# DRI-21700-compactpcb-12s4p-v2.net
KiCad netlist of a schematic drawn in EAGLE
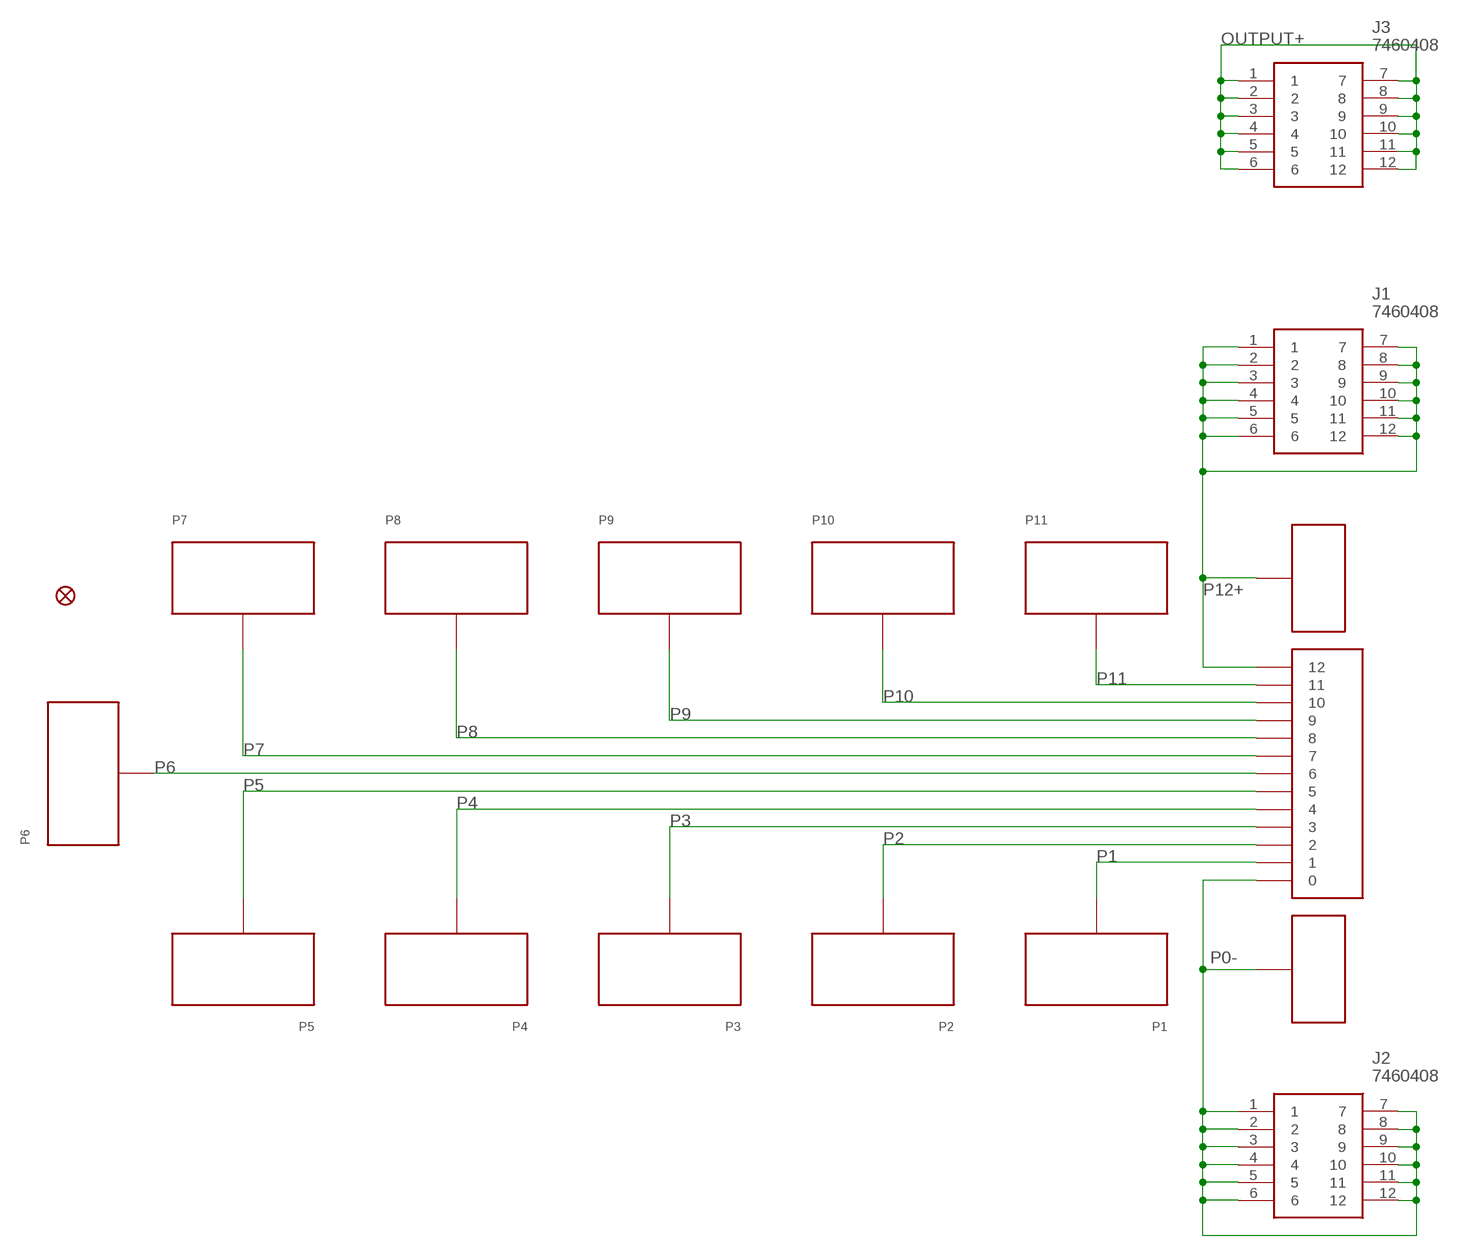
[diagram p0: schematic, sheet 1]

(export (version "E")
  (design (tool "Eeschema 10.0.6"))
  (components
    (comp (ref "FD2")
      (value "FIDUCIAL1X2")
      (footprint "eagle-import:FIDUCIAL-1X2")
      (libsource (lib "eagle-import") (part "FIDUCIAL1X2"))
    )
    (comp (ref "J1")
      (value "7460408")
      (footprint "eagle-import:7460408")
      (fields (field (name "MOUSER_PART_NUMBER") "710-7460408"))
      (libsource (lib "eagle-import") (part "7460408"))
    )
    (comp (ref "J2")
      (value "7460408")
      (footprint "eagle-import:7460408")
      (fields (field (name "MOUSER_PART_NUMBER") "710-7460408"))
      (libsource (lib "eagle-import") (part "7460408"))
    )
    (comp (ref "J3")
      (value "7460408")
      (footprint "eagle-import:7460408")
      (fields (field (name "MOUSER_PART_NUMBER") "710-7460408"))
      (libsource (lib "eagle-import") (part "7460408"))
    )
    (comp (ref "JP1")
      (value "13P-JST-2MM")
      (footprint "eagle-import:13P-JST-2MM")
      (libsource (lib "eagle-import") (part "13P-JST-2MM"))
    )
    (comp (ref "P0")
      (value "BUS-TERM-PAD-")
      (footprint "eagle-import:TERM-PAD-")
      (libsource (lib "eagle-import") (part "BUS-TERM-PAD-"))
    )
    (comp (ref "P1")
      (value "BAT-TERM-L")
      (footprint "eagle-import:BAT-TERM-L")
      (libsource (lib "eagle-import") (part "BAT-TERM-L"))
    )
    (comp (ref "P2")
      (value "BAT-TERM-L")
      (footprint "eagle-import:BAT-TERM-L")
      (libsource (lib "eagle-import") (part "BAT-TERM-L"))
    )
    (comp (ref "P3")
      (value "BAT-TERM-L")
      (footprint "eagle-import:BAT-TERM-L")
      (libsource (lib "eagle-import") (part "BAT-TERM-L"))
    )
    (comp (ref "P4")
      (value "BAT-TERM-L")
      (footprint "eagle-import:BAT-TERM-L")
      (libsource (lib "eagle-import") (part "BAT-TERM-L"))
    )
    (comp (ref "P5")
      (value "BAT-TERM-L")
      (footprint "eagle-import:BAT-TERM-L")
      (libsource (lib "eagle-import") (part "BAT-TERM-L"))
    )
    (comp (ref "P6")
      (value "BAT-TERM-END")
      (footprint "eagle-import:BAT-TERM-END")
      (libsource (lib "eagle-import") (part "BAT-TERM-END"))
    )
    (comp (ref "P7")
      (value "BAT-TERM-L")
      (footprint "eagle-import:BAT-TERM-L")
      (libsource (lib "eagle-import") (part "BAT-TERM-L"))
    )
    (comp (ref "P8")
      (value "BAT-TERM-L")
      (footprint "eagle-import:BAT-TERM-L")
      (libsource (lib "eagle-import") (part "BAT-TERM-L"))
    )
    (comp (ref "P9")
      (value "BAT-TERM-L")
      (footprint "eagle-import:BAT-TERM-L")
      (libsource (lib "eagle-import") (part "BAT-TERM-L"))
    )
    (comp (ref "P10")
      (value "BAT-TERM-L")
      (footprint "eagle-import:BAT-TERM-L")
      (libsource (lib "eagle-import") (part "BAT-TERM-L"))
    )
    (comp (ref "P11")
      (value "BAT-TERM-L")
      (footprint "eagle-import:BAT-TERM-L")
      (libsource (lib "eagle-import") (part "BAT-TERM-L"))
    )
    (comp (ref "P12")
      (value "BUS-TERM-PAD+")
      (footprint "eagle-import:TERM-PAD-")
      (libsource (lib "eagle-import") (part "BUS-TERM-PAD+"))
    )
  )
  (nets
    (net (code "1") (name "/OUTPUT+") (class "Default")
      (node (ref "J3") (pin "1") (pinfunction "1_1") (pintype "bidirectional"))
      (node (ref "J3") (pin "10") (pinfunction "10_10") (pintype "bidirectional"))
      (node (ref "J3") (pin "11") (pinfunction "11_11") (pintype "bidirectional"))
      (node (ref "J3") (pin "12") (pinfunction "12_12") (pintype "bidirectional"))
      (node (ref "J3") (pin "2") (pinfunction "2_2") (pintype "bidirectional"))
      (node (ref "J3") (pin "3") (pinfunction "3_3") (pintype "bidirectional"))
      (node (ref "J3") (pin "4") (pinfunction "4_4") (pintype "bidirectional"))
      (node (ref "J3") (pin "5") (pinfunction "5_5") (pintype "bidirectional"))
      (node (ref "J3") (pin "6") (pinfunction "6_6") (pintype "bidirectional"))
      (node (ref "J3") (pin "7") (pinfunction "7_7") (pintype "bidirectional"))
      (node (ref "J3") (pin "8") (pinfunction "8_8") (pintype "bidirectional"))
      (node (ref "J3") (pin "9") (pinfunction "9_9") (pintype "bidirectional"))
    )
    (net (code "2") (name "/P0-") (class "Default")
      (node (ref "J2") (pin "1") (pinfunction "1_1") (pintype "bidirectional"))
      (node (ref "J2") (pin "10") (pinfunction "10_10") (pintype "bidirectional"))
      (node (ref "J2") (pin "11") (pinfunction "11_11") (pintype "bidirectional"))
      (node (ref "J2") (pin "12") (pinfunction "12_12") (pintype "bidirectional"))
      (node (ref "J2") (pin "2") (pinfunction "2_2") (pintype "bidirectional"))
      (node (ref "J2") (pin "3") (pinfunction "3_3") (pintype "bidirectional"))
      (node (ref "J2") (pin "4") (pinfunction "4_4") (pintype "bidirectional"))
      (node (ref "J2") (pin "5") (pinfunction "5_5") (pintype "bidirectional"))
      (node (ref "J2") (pin "6") (pinfunction "6_6") (pintype "bidirectional"))
      (node (ref "J2") (pin "7") (pinfunction "7_7") (pintype "bidirectional"))
      (node (ref "J2") (pin "8") (pinfunction "8_8") (pintype "bidirectional"))
      (node (ref "J2") (pin "9") (pinfunction "9_9") (pintype "bidirectional"))
      (node (ref "JP1") (pin "P$1") (pinfunction "0_P$1") (pintype "bidirectional"))
      (node (ref "P0") (pin "P$10") (pinfunction "P$0_P$10") (pintype "power_in"))
      (node (ref "P0") (pin "P$100") (pinfunction "P$0_P$100") (pintype "power_in"))
      (node (ref "P0") (pin "P$101") (pinfunction "P$0_P$101") (pintype "power_in"))
      (node (ref "P0") (pin "P$102") (pinfunction "P$0_P$102") (pintype "power_in"))
      (node (ref "P0") (pin "P$103") (pinfunction "P$0_P$103") (pintype "power_in"))
      (node (ref "P0") (pin "P$104") (pinfunction "P$0_P$104") (pintype "power_in"))
      (node (ref "P0") (pin "P$105") (pinfunction "P$0_P$105") (pintype "power_in"))
      (node (ref "P0") (pin "P$106") (pinfunction "P$0_P$106") (pintype "power_in"))
      (node (ref "P0") (pin "P$107") (pinfunction "P$0_P$107") (pintype "power_in"))
      (node (ref "P0") (pin "P$108") (pinfunction "P$0_P$108") (pintype "power_in"))
      (node (ref "P0") (pin "P$109") (pinfunction "P$0_P$109") (pintype "power_in"))
      (node (ref "P0") (pin "P$11") (pinfunction "P$0_P$11") (pintype "power_in"))
      (node (ref "P0") (pin "P$110") (pinfunction "P$0_P$110") (pintype "power_in"))
      (node (ref "P0") (pin "P$12") (pinfunction "P$0_P$12") (pintype "power_in"))
      (node (ref "P0") (pin "P$13") (pinfunction "P$0_P$13") (pintype "power_in"))
      (node (ref "P0") (pin "P$14") (pinfunction "P$0_P$14") (pintype "power_in"))
      (node (ref "P0") (pin "P$15") (pinfunction "P$0_P$15") (pintype "power_in"))
      (node (ref "P0") (pin "P$16") (pinfunction "P$0_P$16") (pintype "power_in"))
      (node (ref "P0") (pin "P$17") (pinfunction "P$0_P$17") (pintype "power_in"))
      (node (ref "P0") (pin "P$18") (pinfunction "P$0_P$18") (pintype "power_in"))
      (node (ref "P0") (pin "P$19") (pinfunction "P$0_P$19") (pintype "power_in"))
      (node (ref "P0") (pin "P$20") (pinfunction "P$0_P$20") (pintype "power_in"))
      (node (ref "P0") (pin "P$21") (pinfunction "P$0_P$21") (pintype "power_in"))
      (node (ref "P0") (pin "P$22") (pinfunction "P$0_P$22") (pintype "power_in"))
      (node (ref "P0") (pin "P$23") (pinfunction "P$0_P$23") (pintype "power_in"))
      (node (ref "P0") (pin "P$24") (pinfunction "P$0_P$24") (pintype "power_in"))
      (node (ref "P0") (pin "P$25") (pinfunction "P$0_P$25") (pintype "power_in"))
      (node (ref "P0") (pin "P$26") (pinfunction "P$0_P$26") (pintype "power_in"))
      (node (ref "P0") (pin "P$27") (pinfunction "P$0_P$27") (pintype "power_in"))
      (node (ref "P0") (pin "P$28") (pinfunction "P$0_P$28") (pintype "power_in"))
      (node (ref "P0") (pin "P$29") (pinfunction "P$0_P$29") (pintype "power_in"))
      (node (ref "P0") (pin "P$3") (pinfunction "P$0_P$3") (pintype "power_in"))
      (node (ref "P0") (pin "P$30") (pinfunction "P$0_P$30") (pintype "power_in"))
      (node (ref "P0") (pin "P$31") (pinfunction "P$0_P$31") (pintype "power_in"))
      (node (ref "P0") (pin "P$32") (pinfunction "P$0_P$32") (pintype "power_in"))
      (node (ref "P0") (pin "P$33") (pinfunction "P$0_P$33") (pintype "power_in"))
      (node (ref "P0") (pin "P$34") (pinfunction "P$0_P$34") (pintype "power_in"))
      (node (ref "P0") (pin "P$35") (pinfunction "P$0_P$35") (pintype "power_in"))
      (node (ref "P0") (pin "P$36") (pinfunction "P$0_P$36") (pintype "power_in"))
      (node (ref "P0") (pin "P$37") (pinfunction "P$0_P$37") (pintype "power_in"))
      (node (ref "P0") (pin "P$38") (pinfunction "P$0_P$38") (pintype "power_in"))
      (node (ref "P0") (pin "P$39") (pinfunction "P$0_P$39") (pintype "power_in"))
      (node (ref "P0") (pin "P$4") (pinfunction "P$0_P$4") (pintype "power_in"))
      (node (ref "P0") (pin "P$40") (pinfunction "P$0_P$40") (pintype "power_in"))
      (node (ref "P0") (pin "P$41") (pinfunction "P$0_P$41") (pintype "power_in"))
      (node (ref "P0") (pin "P$42") (pinfunction "P$0_P$42") (pintype "power_in"))
      (node (ref "P0") (pin "P$43") (pinfunction "P$0_P$43") (pintype "power_in"))
      (node (ref "P0") (pin "P$44") (pinfunction "P$0_P$44") (pintype "power_in"))
      (node (ref "P0") (pin "P$45") (pinfunction "P$0_P$45") (pintype "power_in"))
      (node (ref "P0") (pin "P$46") (pinfunction "P$0_P$46") (pintype "power_in"))
      (node (ref "P0") (pin "P$47") (pinfunction "P$0_P$47") (pintype "power_in"))
      (node (ref "P0") (pin "P$48") (pinfunction "P$0_P$48") (pintype "power_in"))
      (node (ref "P0") (pin "P$49") (pinfunction "P$0_P$49") (pintype "power_in"))
      (node (ref "P0") (pin "P$5") (pinfunction "P$0_P$5") (pintype "power_in"))
      (node (ref "P0") (pin "P$50") (pinfunction "P$0_P$50") (pintype "power_in"))
      (node (ref "P0") (pin "P$51") (pinfunction "P$0_P$51") (pintype "power_in"))
      (node (ref "P0") (pin "P$52") (pinfunction "P$0_P$52") (pintype "power_in"))
      (node (ref "P0") (pin "P$53") (pinfunction "P$0_P$53") (pintype "power_in"))
      (node (ref "P0") (pin "P$54") (pinfunction "P$0_P$54") (pintype "power_in"))
      (node (ref "P0") (pin "P$55") (pinfunction "P$0_P$55") (pintype "power_in"))
      (node (ref "P0") (pin "P$56") (pinfunction "P$0_P$56") (pintype "power_in"))
      (node (ref "P0") (pin "P$57") (pinfunction "P$0_P$57") (pintype "power_in"))
      (node (ref "P0") (pin "P$58") (pinfunction "P$0_P$58") (pintype "power_in"))
      (node (ref "P0") (pin "P$59") (pinfunction "P$0_P$59") (pintype "power_in"))
      (node (ref "P0") (pin "P$6") (pinfunction "P$0_P$6") (pintype "power_in"))
      (node (ref "P0") (pin "P$60") (pinfunction "P$0_P$60") (pintype "power_in"))
      (node (ref "P0") (pin "P$61") (pinfunction "P$0_P$61") (pintype "power_in"))
      (node (ref "P0") (pin "P$62") (pinfunction "P$0_P$62") (pintype "power_in"))
      (node (ref "P0") (pin "P$63") (pinfunction "P$0_P$63") (pintype "power_in"))
      (node (ref "P0") (pin "P$64") (pinfunction "P$0_P$64") (pintype "power_in"))
      (node (ref "P0") (pin "P$65") (pinfunction "P$0_P$65") (pintype "power_in"))
      (node (ref "P0") (pin "P$66") (pinfunction "P$0_P$66") (pintype "power_in"))
      (node (ref "P0") (pin "P$67") (pinfunction "P$0_P$67") (pintype "power_in"))
      (node (ref "P0") (pin "P$68") (pinfunction "P$0_P$68") (pintype "power_in"))
      (node (ref "P0") (pin "P$69") (pinfunction "P$0_P$69") (pintype "power_in"))
      (node (ref "P0") (pin "P$7") (pinfunction "P$0_P$7") (pintype "power_in"))
      (node (ref "P0") (pin "P$70") (pinfunction "P$0_P$70") (pintype "power_in"))
      (node (ref "P0") (pin "P$71") (pinfunction "P$0_P$71") (pintype "power_in"))
      (node (ref "P0") (pin "P$72") (pinfunction "P$0_P$72") (pintype "power_in"))
      (node (ref "P0") (pin "P$73") (pinfunction "P$0_P$73") (pintype "power_in"))
      (node (ref "P0") (pin "P$74") (pinfunction "P$0_P$74") (pintype "power_in"))
      (node (ref "P0") (pin "P$75") (pinfunction "P$0_P$75") (pintype "power_in"))
      (node (ref "P0") (pin "P$76") (pinfunction "P$0_P$76") (pintype "power_in"))
      (node (ref "P0") (pin "P$77") (pinfunction "P$0_P$77") (pintype "power_in"))
      (node (ref "P0") (pin "P$78") (pinfunction "P$0_P$78") (pintype "power_in"))
      (node (ref "P0") (pin "P$79") (pinfunction "P$0_P$79") (pintype "power_in"))
      (node (ref "P0") (pin "P$8") (pinfunction "P$0_P$8") (pintype "power_in"))
      (node (ref "P0") (pin "P$80") (pinfunction "P$0_P$80") (pintype "power_in"))
      (node (ref "P0") (pin "P$81") (pinfunction "P$0_P$81") (pintype "power_in"))
      (node (ref "P0") (pin "P$82") (pinfunction "P$0_P$82") (pintype "power_in"))
      (node (ref "P0") (pin "P$83") (pinfunction "P$0_P$83") (pintype "power_in"))
      (node (ref "P0") (pin "P$84") (pinfunction "P$0_P$84") (pintype "power_in"))
      (node (ref "P0") (pin "P$85") (pinfunction "P$0_P$85") (pintype "power_in"))
      (node (ref "P0") (pin "P$86") (pinfunction "P$0_P$86") (pintype "power_in"))
      (node (ref "P0") (pin "P$87") (pinfunction "P$0_P$87") (pintype "power_in"))
      (node (ref "P0") (pin "P$88") (pinfunction "P$0_P$88") (pintype "power_in"))
      (node (ref "P0") (pin "P$89") (pinfunction "P$0_P$89") (pintype "power_in"))
      (node (ref "P0") (pin "P$9") (pinfunction "P$0_P$9") (pintype "power_in"))
      (node (ref "P0") (pin "P$90") (pinfunction "P$0_P$90") (pintype "power_in"))
      (node (ref "P0") (pin "P$91") (pinfunction "P$0_P$91") (pintype "power_in"))
      (node (ref "P0") (pin "P$92") (pinfunction "P$0_P$92") (pintype "power_in"))
      (node (ref "P0") (pin "P$93") (pinfunction "P$0_P$93") (pintype "power_in"))
      (node (ref "P0") (pin "P$94") (pinfunction "P$0_P$94") (pintype "power_in"))
      (node (ref "P0") (pin "P$95") (pinfunction "P$0_P$95") (pintype "power_in"))
      (node (ref "P0") (pin "P$96") (pinfunction "P$0_P$96") (pintype "power_in"))
      (node (ref "P0") (pin "P$97") (pinfunction "P$0_P$97") (pintype "power_in"))
      (node (ref "P0") (pin "P$98") (pinfunction "P$0_P$98") (pintype "power_in"))
      (node (ref "P0") (pin "P$99") (pinfunction "P$0_P$99") (pintype "power_in"))
    )
    (net (code "3") (name "/P1") (class "Default")
      (node (ref "JP1") (pin "P$2") (pinfunction "1_P$2") (pintype "bidirectional"))
      (node (ref "P1") (pin "P$1") (pinfunction "P$1_P$1") (pintype "power_in"))
      (node (ref "P1") (pin "P$10") (pinfunction "P$1_P$10") (pintype "power_in"))
      (node (ref "P1") (pin "P$100") (pinfunction "P$1_P$100") (pintype "power_in"))
      (node (ref "P1") (pin "P$101") (pinfunction "P$1_P$101") (pintype "power_in"))
      (node (ref "P1") (pin "P$102") (pinfunction "P$1_P$102") (pintype "power_in"))
      (node (ref "P1") (pin "P$103") (pinfunction "P$1_P$103") (pintype "power_in"))
      (node (ref "P1") (pin "P$104") (pinfunction "P$1_P$104") (pintype "power_in"))
      (node (ref "P1") (pin "P$105") (pinfunction "P$1_P$105") (pintype "power_in"))
      (node (ref "P1") (pin "P$106") (pinfunction "P$1_P$106") (pintype "power_in"))
      (node (ref "P1") (pin "P$107") (pinfunction "P$1_P$107") (pintype "power_in"))
      (node (ref "P1") (pin "P$108") (pinfunction "P$1_P$108") (pintype "power_in"))
      (node (ref "P1") (pin "P$109") (pinfunction "P$1_P$109") (pintype "power_in"))
      (node (ref "P1") (pin "P$11") (pinfunction "P$1_P$11") (pintype "power_in"))
      (node (ref "P1") (pin "P$110") (pinfunction "P$1_P$110") (pintype "power_in"))
      (node (ref "P1") (pin "P$111") (pinfunction "P$1_P$111") (pintype "power_in"))
      (node (ref "P1") (pin "P$112") (pinfunction "P$1_P$112") (pintype "power_in"))
      (node (ref "P1") (pin "P$113") (pinfunction "P$1_P$113") (pintype "power_in"))
      (node (ref "P1") (pin "P$114") (pinfunction "P$1_P$114") (pintype "power_in"))
      (node (ref "P1") (pin "P$115") (pinfunction "P$1_P$115") (pintype "power_in"))
      (node (ref "P1") (pin "P$116") (pinfunction "P$1_P$116") (pintype "power_in"))
      (node (ref "P1") (pin "P$117") (pinfunction "P$1_P$117") (pintype "power_in"))
      (node (ref "P1") (pin "P$118") (pinfunction "P$1_P$118") (pintype "power_in"))
      (node (ref "P1") (pin "P$119") (pinfunction "P$1_P$119") (pintype "power_in"))
      (node (ref "P1") (pin "P$12") (pinfunction "P$1_P$12") (pintype "power_in"))
      (node (ref "P1") (pin "P$120") (pinfunction "P$1_P$120") (pintype "power_in"))
      (node (ref "P1") (pin "P$121") (pinfunction "P$1_P$121") (pintype "power_in"))
      (node (ref "P1") (pin "P$122") (pinfunction "P$1_P$122") (pintype "power_in"))
      (node (ref "P1") (pin "P$123") (pinfunction "P$1_P$123") (pintype "power_in"))
      (node (ref "P1") (pin "P$124") (pinfunction "P$1_P$124") (pintype "power_in"))
      (node (ref "P1") (pin "P$125") (pinfunction "P$1_P$125") (pintype "power_in"))
      (node (ref "P1") (pin "P$126") (pinfunction "P$1_P$126") (pintype "power_in"))
      (node (ref "P1") (pin "P$127") (pinfunction "P$1_P$127") (pintype "power_in"))
      (node (ref "P1") (pin "P$128") (pinfunction "P$1_P$128") (pintype "power_in"))
      (node (ref "P1") (pin "P$129") (pinfunction "P$1_P$129") (pintype "power_in"))
      (node (ref "P1") (pin "P$13") (pinfunction "P$1_P$13") (pintype "power_in"))
      (node (ref "P1") (pin "P$130") (pinfunction "P$1_P$130") (pintype "power_in"))
      (node (ref "P1") (pin "P$131") (pinfunction "P$1_P$131") (pintype "power_in"))
      (node (ref "P1") (pin "P$132") (pinfunction "P$1_P$132") (pintype "power_in"))
      (node (ref "P1") (pin "P$133") (pinfunction "P$1_P$133") (pintype "power_in"))
      (node (ref "P1") (pin "P$134") (pinfunction "P$1_P$134") (pintype "power_in"))
      (node (ref "P1") (pin "P$135") (pinfunction "P$1_P$135") (pintype "power_in"))
      (node (ref "P1") (pin "P$136") (pinfunction "P$1_P$136") (pintype "power_in"))
      (node (ref "P1") (pin "P$137") (pinfunction "P$1_P$137") (pintype "power_in"))
      (node (ref "P1") (pin "P$138") (pinfunction "P$1_P$138") (pintype "power_in"))
      (node (ref "P1") (pin "P$139") (pinfunction "P$1_P$139") (pintype "power_in"))
      (node (ref "P1") (pin "P$14") (pinfunction "P$1_P$14") (pintype "power_in"))
      (node (ref "P1") (pin "P$140") (pinfunction "P$1_P$140") (pintype "power_in"))
      (node (ref "P1") (pin "P$141") (pinfunction "P$1_P$141") (pintype "power_in"))
      (node (ref "P1") (pin "P$142") (pinfunction "P$1_P$142") (pintype "power_in"))
      (node (ref "P1") (pin "P$143") (pinfunction "P$1_P$143") (pintype "power_in"))
      (node (ref "P1") (pin "P$144") (pinfunction "P$1_P$144") (pintype "power_in"))
      (node (ref "P1") (pin "P$145") (pinfunction "P$1_P$145") (pintype "power_in"))
      (node (ref "P1") (pin "P$146") (pinfunction "P$1_P$146") (pintype "power_in"))
      (node (ref "P1") (pin "P$147") (pinfunction "P$1_P$147") (pintype "power_in"))
      (node (ref "P1") (pin "P$148") (pinfunction "P$1_P$148") (pintype "power_in"))
      (node (ref "P1") (pin "P$149") (pinfunction "P$1_P$149") (pintype "power_in"))
      (node (ref "P1") (pin "P$15") (pinfunction "P$1_P$15") (pintype "power_in"))
      (node (ref "P1") (pin "P$150") (pinfunction "P$1_P$150") (pintype "power_in"))
      (node (ref "P1") (pin "P$151") (pinfunction "P$1_P$151") (pintype "power_in"))
      (node (ref "P1") (pin "P$152") (pinfunction "P$1_P$152") (pintype "power_in"))
      (node (ref "P1") (pin "P$153") (pinfunction "P$1_P$153") (pintype "power_in"))
      (node (ref "P1") (pin "P$154") (pinfunction "P$1_P$154") (pintype "power_in"))
      (node (ref "P1") (pin "P$155") (pinfunction "P$1_P$155") (pintype "power_in"))
      (node (ref "P1") (pin "P$156") (pinfunction "P$1_P$156") (pintype "power_in"))
      (node (ref "P1") (pin "P$157") (pinfunction "P$1_P$157") (pintype "power_in"))
      (node (ref "P1") (pin "P$158") (pinfunction "P$1_P$158") (pintype "power_in"))
      (node (ref "P1") (pin "P$159") (pinfunction "P$1_P$159") (pintype "power_in"))
      (node (ref "P1") (pin "P$16") (pinfunction "P$1_P$16") (pintype "power_in"))
      (node (ref "P1") (pin "P$160") (pinfunction "P$1_P$160") (pintype "power_in"))
      (node (ref "P1") (pin "P$161") (pinfunction "P$1_P$161") (pintype "power_in"))
      (node (ref "P1") (pin "P$162") (pinfunction "P$1_P$162") (pintype "power_in"))
      (node (ref "P1") (pin "P$163") (pinfunction "P$1_P$163") (pintype "power_in"))
      (node (ref "P1") (pin "P$164") (pinfunction "P$1_P$164") (pintype "power_in"))
      (node (ref "P1") (pin "P$165") (pinfunction "P$1_P$165") (pintype "power_in"))
      (node (ref "P1") (pin "P$166") (pinfunction "P$1_P$166") (pintype "power_in"))
      (node (ref "P1") (pin "P$167") (pinfunction "P$1_P$167") (pintype "power_in"))
      (node (ref "P1") (pin "P$168") (pinfunction "P$1_P$168") (pintype "power_in"))
      (node (ref "P1") (pin "P$169") (pinfunction "P$1_P$169") (pintype "power_in"))
      (node (ref "P1") (pin "P$17") (pinfunction "P$1_P$17") (pintype "power_in"))
      (node (ref "P1") (pin "P$170") (pinfunction "P$1_P$170") (pintype "power_in"))
      (node (ref "P1") (pin "P$171") (pinfunction "P$1_P$171") (pintype "power_in"))
      (node (ref "P1") (pin "P$172") (pinfunction "P$1_P$172") (pintype "power_in"))
      (node (ref "P1") (pin "P$173") (pinfunction "P$1_P$173") (pintype "power_in"))
      (node (ref "P1") (pin "P$174") (pinfunction "P$1_P$174") (pintype "power_in"))
      (node (ref "P1") (pin "P$175") (pinfunction "P$1_P$175") (pintype "power_in"))
      (node (ref "P1") (pin "P$176") (pinfunction "P$1_P$176") (pintype "power_in"))
      (node (ref "P1") (pin "P$177") (pinfunction "P$1_P$177") (pintype "power_in"))
      (node (ref "P1") (pin "P$178") (pinfunction "P$1_P$178") (pintype "power_in"))
      (node (ref "P1") (pin "P$179") (pinfunction "P$1_P$179") (pintype "power_in"))
      (node (ref "P1") (pin "P$18") (pinfunction "P$1_P$18") (pintype "power_in"))
      (node (ref "P1") (pin "P$180") (pinfunction "P$1_P$180") (pintype "power_in"))
      (node (ref "P1") (pin "P$181") (pinfunction "P$1_P$181") (pintype "power_in"))
      (node (ref "P1") (pin "P$182") (pinfunction "P$1_P$182") (pintype "power_in"))
      (node (ref "P1") (pin "P$183") (pinfunction "P$1_P$183") (pintype "power_in"))
      (node (ref "P1") (pin "P$184") (pinfunction "P$1_P$184") (pintype "power_in"))
      (node (ref "P1") (pin "P$185") (pinfunction "P$1_P$185") (pintype "power_in"))
      (node (ref "P1") (pin "P$186") (pinfunction "P$1_P$186") (pintype "power_in"))
      (node (ref "P1") (pin "P$187") (pinfunction "P$1_P$187") (pintype "power_in"))
      (node (ref "P1") (pin "P$188") (pinfunction "P$1_P$188") (pintype "power_in"))
      (node (ref "P1") (pin "P$189") (pinfunction "P$1_P$189") (pintype "power_in"))
      (node (ref "P1") (pin "P$19") (pinfunction "P$1_P$19") (pintype "power_in"))
      (node (ref "P1") (pin "P$190") (pinfunction "P$1_P$190") (pintype "power_in"))
      (node (ref "P1") (pin "P$191") (pinfunction "P$1_P$191") (pintype "power_in"))
      (node (ref "P1") (pin "P$192") (pinfunction "P$1_P$192") (pintype "power_in"))
      (node (ref "P1") (pin "P$193") (pinfunction "P$1_P$193") (pintype "power_in"))
      (node (ref "P1") (pin "P$194") (pinfunction "P$1_P$194") (pintype "power_in"))
      (node (ref "P1") (pin "P$195") (pinfunction "P$1_P$195") (pintype "power_in"))
      (node (ref "P1") (pin "P$196") (pinfunction "P$1_P$196") (pintype "power_in"))
      (node (ref "P1") (pin "P$197") (pinfunction "P$1_P$197") (pintype "power_in"))
      (node (ref "P1") (pin "P$198") (pinfunction "P$1_P$198") (pintype "power_in"))
      (node (ref "P1") (pin "P$199") (pinfunction "P$1_P$199") (pintype "power_in"))
      (node (ref "P1") (pin "P$2") (pinfunction "P$1_P$2") (pintype "power_in"))
      (node (ref "P1") (pin "P$20") (pinfunction "P$1_P$20") (pintype "power_in"))
      (node (ref "P1") (pin "P$200") (pinfunction "P$1_P$200") (pintype "power_in"))
      (node (ref "P1") (pin "P$201") (pinfunction "P$1_P$201") (pintype "power_in"))
      (node (ref "P1") (pin "P$202") (pinfunction "P$1_P$202") (pintype "power_in"))
      (node (ref "P1") (pin "P$203") (pinfunction "P$1_P$203") (pintype "power_in"))
      (node (ref "P1") (pin "P$204") (pinfunction "P$1_P$204") (pintype "power_in"))
      (node (ref "P1") (pin "P$205") (pinfunction "P$1_P$205") (pintype "power_in"))
      (node (ref "P1") (pin "P$206") (pinfunction "P$1_P$206") (pintype "power_in"))
      (node (ref "P1") (pin "P$207") (pinfunction "P$1_P$207") (pintype "power_in"))
      (node (ref "P1") (pin "P$208") (pinfunction "P$1_P$208") (pintype "power_in"))
      (node (ref "P1") (pin "P$209") (pinfunction "P$1_P$209") (pintype "power_in"))
      (node (ref "P1") (pin "P$21") (pinfunction "P$1_P$21") (pintype "power_in"))
      (node (ref "P1") (pin "P$210") (pinfunction "P$1_P$210") (pintype "power_in"))
      (node (ref "P1") (pin "P$211") (pinfunction "P$1_P$211") (pintype "power_in"))
      (node (ref "P1") (pin "P$212") (pinfunction "P$1_P$212") (pintype "power_in"))
      (node (ref "P1") (pin "P$213") (pinfunction "P$1_P$213") (pintype "power_in"))
      (node (ref "P1") (pin "P$214") (pinfunction "P$1_P$214") (pintype "power_in"))
      (node (ref "P1") (pin "P$215") (pinfunction "P$1_P$215") (pintype "power_in"))
      (node (ref "P1") (pin "P$216") (pinfunction "P$1_P$216") (pintype "power_in"))
      (node (ref "P1") (pin "P$217") (pinfunction "P$1_P$217") (pintype "power_in"))
      (node (ref "P1") (pin "P$218") (pinfunction "P$1_P$218") (pintype "power_in"))
      (node (ref "P1") (pin "P$219") (pinfunction "P$1_P$219") (pintype "power_in"))
      (node (ref "P1") (pin "P$22") (pinfunction "P$1_P$22") (pintype "power_in"))
      (node (ref "P1") (pin "P$220") (pinfunction "P$1_P$220") (pintype "power_in"))
      (node (ref "P1") (pin "P$221") (pinfunction "P$1_P$221") (pintype "power_in"))
      (node (ref "P1") (pin "P$222") (pinfunction "P$1_P$222") (pintype "power_in"))
      (node (ref "P1") (pin "P$223") (pinfunction "P$1_P$223") (pintype "power_in"))
      (node (ref "P1") (pin "P$224") (pinfunction "P$1_P$224") (pintype "power_in"))
      (node (ref "P1") (pin "P$225") (pinfunction "P$1_P$225") (pintype "power_in"))
      (node (ref "P1") (pin "P$226") (pinfunction "P$1_P$226") (pintype "power_in"))
      (node (ref "P1") (pin "P$227") (pinfunction "P$1_P$227") (pintype "power_in"))
      (node (ref "P1") (pin "P$228") (pinfunction "P$1_P$228") (pintype "power_in"))
      (node (ref "P1") (pin "P$229") (pinfunction "P$1_P$229") (pintype "power_in"))
      (node (ref "P1") (pin "P$23") (pinfunction "P$1_P$23") (pintype "power_in"))
      (node (ref "P1") (pin "P$230") (pinfunction "P$1_P$230") (pintype "power_in"))
      (node (ref "P1") (pin "P$231") (pinfunction "P$1_P$231") (pintype "power_in"))
      (node (ref "P1") (pin "P$232") (pinfunction "P$1_P$232") (pintype "power_in"))
      (node (ref "P1") (pin "P$233") (pinfunction "P$1_P$233") (pintype "power_in"))
      (node (ref "P1") (pin "P$234") (pinfunction "P$1_P$234") (pintype "power_in"))
      (node (ref "P1") (pin "P$235") (pinfunction "P$1_P$235") (pintype "power_in"))
      (node (ref "P1") (pin "P$236") (pinfunction "P$1_P$236") (pintype "power_in"))
      (node (ref "P1") (pin "P$237") (pinfunction "P$1_P$237") (pintype "power_in"))
      (node (ref "P1") (pin "P$238") (pinfunction "P$1_P$238") (pintype "power_in"))
      (node (ref "P1") (pin "P$239") (pinfunction "P$1_P$239") (pintype "power_in"))
      (node (ref "P1") (pin "P$24") (pinfunction "P$1_P$24") (pintype "power_in"))
      (node (ref "P1") (pin "P$240") (pinfunction "P$1_P$240") (pintype "power_in"))
      (node (ref "P1") (pin "P$241") (pinfunction "P$1_P$241") (pintype "power_in"))
      (node (ref "P1") (pin "P$242") (pinfunction "P$1_P$242") (pintype "power_in"))
      (node (ref "P1") (pin "P$243") (pinfunction "P$1_P$243") (pintype "power_in"))
      (node (ref "P1") (pin "P$244") (pinfunction "P$1_P$244") (pintype "power_in"))
      (node (ref "P1") (pin "P$245") (pinfunction "P$1_P$245") (pintype "power_in"))
      (node (ref "P1") (pin "P$246") (pinfunction "P$1_P$246") (pintype "power_in"))
      (node (ref "P1") (pin "P$247") (pinfunction "P$1_P$247") (pintype "power_in"))
      (node (ref "P1") (pin "P$248") (pinfunction "P$1_P$248") (pintype "power_in"))
      (node (ref "P1") (pin "P$249") (pinfunction "P$1_P$249") (pintype "power_in"))
      (node (ref "P1") (pin "P$25") (pinfunction "P$1_P$25") (pintype "power_in"))
      (node (ref "P1") (pin "P$250") (pinfunction "P$1_P$250") (pintype "power_in"))
      (node (ref "P1") (pin "P$251") (pinfunction "P$1_P$251") (pintype "power_in"))
      (node (ref "P1") (pin "P$252") (pinfunction "P$1_P$252") (pintype "power_in"))
      (node (ref "P1") (pin "P$253") (pinfunction "P$1_P$253") (pintype "power_in"))
      (node (ref "P1") (pin "P$254") (pinfunction "P$1_P$254") (pintype "power_in"))
      (node (ref "P1") (pin "P$255") (pinfunction "P$1_P$255") (pintype "power_in"))
      (node (ref "P1") (pin "P$256") (pinfunction "P$1_P$256") (pintype "power_in"))
      (node (ref "P1") (pin "P$257") (pinfunction "P$1_P$257") (pintype "power_in"))
      (node (ref "P1") (pin "P$258") (pinfunction "P$1_P$258") (pintype "power_in"))
      (node (ref "P1") (pin "P$259") (pinfunction "P$1_P$259") (pintype "power_in"))
      (node (ref "P1") (pin "P$26") (pinfunction "P$1_P$26") (pintype "power_in"))
      (node (ref "P1") (pin "P$260") (pinfunction "P$1_P$260") (pintype "power_in"))
      (node (ref "P1") (pin "P$261") (pinfunction "P$1_P$261") (pintype "power_in"))
      (node (ref "P1") (pin "P$262") (pinfunction "P$1_P$262") (pintype "power_in"))
      (node (ref "P1") (pin "P$263") (pinfunction "P$1_P$263") (pintype "power_in"))
      (node (ref "P1") (pin "P$264") (pinfunction "P$1_P$264") (pintype "power_in"))
      (node (ref "P1") (pin "P$265") (pinfunction "P$1_P$265") (pintype "power_in"))
      (node (ref "P1") (pin "P$266") (pinfunction "P$1_P$266") (pintype "power_in"))
      (node (ref "P1") (pin "P$267") (pinfunction "P$1_P$267") (pintype "power_in"))
      (node (ref "P1") (pin "P$268") (pinfunction "P$1_P$268") (pintype "power_in"))
      (node (ref "P1") (pin "P$269") (pinfunction "P$1_P$269") (pintype "power_in"))
      (node (ref "P1") (pin "P$27") (pinfunction "P$1_P$27") (pintype "power_in"))
      (node (ref "P1") (pin "P$270") (pinfunction "P$1_P$270") (pintype "power_in"))
      (node (ref "P1") (pin "P$271") (pinfunction "P$1_P$271") (pintype "power_in"))
      (node (ref "P1") (pin "P$272") (pinfunction "P$1_P$272") (pintype "power_in"))
      (node (ref "P1") (pin "P$273") (pinfunction "P$1_P$273") (pintype "power_in"))
      (node (ref "P1") (pin "P$274") (pinfunction "P$1_P$274") (pintype "power_in"))
      (node (ref "P1") (pin "P$275") (pinfunction "P$1_P$275") (pintype "power_in"))
      (node (ref "P1") (pin "P$276") (pinfunction "P$1_P$276") (pintype "power_in"))
      (node (ref "P1") (pin "P$277") (pinfunction "P$1_P$277") (pintype "power_in"))
      (node (ref "P1") (pin "P$278") (pinfunction "P$1_P$278") (pintype "power_in"))
      (node (ref "P1") (pin "P$279") (pinfunction "P$1_P$279") (pintype "power_in"))
      (node (ref "P1") (pin "P$28") (pinfunction "P$1_P$28") (pintype "power_in"))
      (node (ref "P1") (pin "P$280") (pinfunction "P$1_P$280") (pintype "power_in"))
      (node (ref "P1") (pin "P$281") (pinfunction "P$1_P$281") (pintype "power_in"))
      (node (ref "P1") (pin "P$282") (pinfunction "P$1_P$282") (pintype "power_in"))
      (node (ref "P1") (pin "P$283") (pinfunction "P$1_P$283") (pintype "power_in"))
      (node (ref "P1") (pin "P$284") (pinfunction "P$1_P$284") (pintype "power_in"))
      (node (ref "P1") (pin "P$285") (pinfunction "P$1_P$285") (pintype "power_in"))
      (node (ref "P1") (pin "P$286") (pinfunction "P$1_P$286") (pintype "power_in"))
      (node (ref "P1") (pin "P$287") (pinfunction "P$1_P$287") (pintype "power_in"))
      (node (ref "P1") (pin "P$288") (pinfunction "P$1_P$288") (pintype "power_in"))
      (node (ref "P1") (pin "P$29") (pinfunction "P$1_P$29") (pintype "power_in"))
      (node (ref "P1") (pin "P$3") (pinfunction "P$1_P$3") (pintype "power_in"))
      (node (ref "P1") (pin "P$30") (pinfunction "P$1_P$30") (pintype "power_in"))
      (node (ref "P1") (pin "P$31") (pinfunction "P$1_P$31") (pintype "power_in"))
      (node (ref "P1") (pin "P$32") (pinfunction "P$1_P$32") (pintype "power_in"))
      (node (ref "P1") (pin "P$33") (pinfunction "P$1_P$33") (pintype "power_in"))
      (node (ref "P1") (pin "P$34") (pinfunction "P$1_P$34") (pintype "power_in"))
      (node (ref "P1") (pin "P$35") (pinfunction "P$1_P$35") (pintype "power_in"))
      (node (ref "P1") (pin "P$36") (pinfunction "P$1_P$36") (pintype "power_in"))
      (node (ref "P1") (pin "P$37") (pinfunction "P$1_P$37") (pintype "power_in"))
      (node (ref "P1") (pin "P$38") (pinfunction "P$1_P$38") (pintype "power_in"))
      (node (ref "P1") (pin "P$39") (pinfunction "P$1_P$39") (pintype "power_in"))
      (node (ref "P1") (pin "P$4") (pinfunction "P$1_P$4") (pintype "power_in"))
      (node (ref "P1") (pin "P$40") (pinfunction "P$1_P$40") (pintype "power_in"))
      (node (ref "P1") (pin "P$41") (pinfunction "P$1_P$41") (pintype "power_in"))
      (node (ref "P1") (pin "P$42") (pinfunction "P$1_P$42") (pintype "power_in"))
      (node (ref "P1") (pin "P$43") (pinfunction "P$1_P$43") (pintype "power_in"))
      (node (ref "P1") (pin "P$44") (pinfunction "P$1_P$44") (pintype "power_in"))
      (node (ref "P1") (pin "P$45") (pinfunction "P$1_P$45") (pintype "power_in"))
      (node (ref "P1") (pin "P$46") (pinfunction "P$1_P$46") (pintype "power_in"))
      (node (ref "P1") (pin "P$47") (pinfunction "P$1_P$47") (pintype "power_in"))
      (node (ref "P1") (pin "P$48") (pinfunction "P$1_P$48") (pintype "power_in"))
      (node (ref "P1") (pin "P$49") (pinfunction "P$1_P$49") (pintype "power_in"))
      (node (ref "P1") (pin "P$5") (pinfunction "P$1_P$5") (pintype "power_in"))
      (node (ref "P1") (pin "P$50") (pinfunction "P$1_P$50") (pintype "power_in"))
      (node (ref "P1") (pin "P$51") (pinfunction "P$1_P$51") (pintype "power_in"))
      (node (ref "P1") (pin "P$52") (pinfunction "P$1_P$52") (pintype "power_in"))
      (node (ref "P1") (pin "P$53") (pinfunction "P$1_P$53") (pintype "power_in"))
      (node (ref "P1") (pin "P$54") (pinfunction "P$1_P$54") (pintype "power_in"))
      (node (ref "P1") (pin "P$55") (pinfunction "P$1_P$55") (pintype "power_in"))
      (node (ref "P1") (pin "P$56") (pinfunction "P$1_P$56") (pintype "power_in"))
      (node (ref "P1") (pin "P$57") (pinfunction "P$1_P$57") (pintype "power_in"))
      (node (ref "P1") (pin "P$58") (pinfunction "P$1_P$58") (pintype "power_in"))
      (node (ref "P1") (pin "P$59") (pinfunction "P$1_P$59") (pintype "power_in"))
      (node (ref "P1") (pin "P$6") (pinfunction "P$1_P$6") (pintype "power_in"))
      (node (ref "P1") (pin "P$60") (pinfunction "P$1_P$60") (pintype "power_in"))
      (node (ref "P1") (pin "P$61") (pinfunction "P$1_P$61") (pintype "power_in"))
      (node (ref "P1") (pin "P$62") (pinfunction "P$1_P$62") (pintype "power_in"))
      (node (ref "P1") (pin "P$63") (pinfunction "P$1_P$63") (pintype "power_in"))
      (node (ref "P1") (pin "P$64") (pinfunction "P$1_P$64") (pintype "power_in"))
      (node (ref "P1") (pin "P$65") (pinfunction "P$1_P$65") (pintype "power_in"))
      (node (ref "P1") (pin "P$66") (pinfunction "P$1_P$66") (pintype "power_in"))
      (node (ref "P1") (pin "P$67") (pinfunction "P$1_P$67") (pintype "power_in"))
      (node (ref "P1") (pin "P$68") (pinfunction "P$1_P$68") (pintype "power_in"))
      (node (ref "P1") (pin "P$69") (pinfunction "P$1_P$69") (pintype "power_in"))
      (node (ref "P1") (pin "P$7") (pinfunction "P$1_P$7") (pintype "power_in"))
      (node (ref "P1") (pin "P$70") (pinfunction "P$1_P$70") (pintype "power_in"))
      (node (ref "P1") (pin "P$71") (pinfunction "P$1_P$71") (pintype "power_in"))
      (node (ref "P1") (pin "P$72") (pinfunction "P$1_P$72") (pintype "power_in"))
      (node (ref "P1") (pin "P$73") (pinfunction "P$1_P$73") (pintype "power_in"))
      (node (ref "P1") (pin "P$74") (pinfunction "P$1_P$74") (pintype "power_in"))
      (node (ref "P1") (pin "P$75") (pinfunction "P$1_P$75") (pintype "power_in"))
      (node (ref "P1") (pin "P$76") (pinfunction "P$1_P$76") (pintype "power_in"))
      (node (ref "P1") (pin "P$77") (pinfunction "P$1_P$77") (pintype "power_in"))
      (node (ref "P1") (pin "P$78") (pinfunction "P$1_P$78") (pintype "power_in"))
      (node (ref "P1") (pin "P$79") (pinfunction "P$1_P$79") (pintype "power_in"))
      (node (ref "P1") (pin "P$8") (pinfunction "P$1_P$8") (pintype "power_in"))
      (node (ref "P1") (pin "P$80") (pinfunction "P$1_P$80") (pintype "power_in"))
      (node (ref "P1") (pin "P$81") (pinfunction "P$1_P$81") (pintype "power_in"))
      (node (ref "P1") (pin "P$82") (pinfunction "P$1_P$82") (pintype "power_in"))
      (node (ref "P1") (pin "P$83") (pinfunction "P$1_P$83") (pintype "power_in"))
      (node (ref "P1") (pin "P$84") (pinfunction "P$1_P$84") (pintype "power_in"))
      (node (ref "P1") (pin "P$85") (pinfunction "P$1_P$85") (pintype "power_in"))
      (node (ref "P1") (pin "P$86") (pinfunction "P$1_P$86") (pintype "power_in"))
      (node (ref "P1") (pin "P$87") (pinfunction "P$1_P$87") (pintype "power_in"))
      (node (ref "P1") (pin "P$88") (pinfunction "P$1_P$88") (pintype "power_in"))
      (node (ref "P1") (pin "P$89") (pinfunction "P$1_P$89") (pintype "power_in"))
      (node (ref "P1") (pin "P$9") (pinfunction "P$1_P$9") (pintype "power_in"))
      (node (ref "P1") (pin "P$90") (pinfunction "P$1_P$90") (pintype "power_in"))
      (node (ref "P1") (pin "P$91") (pinfunction "P$1_P$91") (pintype "power_in"))
      (node (ref "P1") (pin "P$92") (pinfunction "P$1_P$92") (pintype "power_in"))
      (node (ref "P1") (pin "P$93") (pinfunction "P$1_P$93") (pintype "power_in"))
      (node (ref "P1") (pin "P$94") (pinfunction "P$1_P$94") (pintype "power_in"))
      (node (ref "P1") (pin "P$95") (pinfunction "P$1_P$95") (pintype "power_in"))
      (node (ref "P1") (pin "P$96") (pinfunction "P$1_P$96") (pintype "power_in"))
      (node (ref "P1") (pin "P$97") (pinfunction "P$1_P$97") (pintype "power_in"))
      (node (ref "P1") (pin "P$98") (pinfunction "P$1_P$98") (pintype "power_in"))
      (node (ref "P1") (pin "P$99") (pinfunction "P$1_P$99") (pintype "power_in"))
    )
    (net (code "4") (name "/P2") (class "Default")
      (node (ref "JP1") (pin "P$3") (pinfunction "2_P$3") (pintype "bidirectional"))
      (node (ref "P2") (pin "P$1") (pinfunction "P$1_P$1") (pintype "power_in"))
      (node (ref "P2") (pin "P$10") (pinfunction "P$1_P$10") (pintype "power_in"))
      (node (ref "P2") (pin "P$100") (pinfunction "P$1_P$100") (pintype "power_in"))
      (node (ref "P2") (pin "P$101") (pinfunction "P$1_P$101") (pintype "power_in"))
      (node (ref "P2") (pin "P$102") (pinfunction "P$1_P$102") (pintype "power_in"))
      (node (ref "P2") (pin "P$103") (pinfunction "P$1_P$103") (pintype "power_in"))
      (node (ref "P2") (pin "P$104") (pinfunction "P$1_P$104") (pintype "power_in"))
      (node (ref "P2") (pin "P$105") (pinfunction "P$1_P$105") (pintype "power_in"))
      (node (ref "P2") (pin "P$106") (pinfunction "P$1_P$106") (pintype "power_in"))
      (node (ref "P2") (pin "P$107") (pinfunction "P$1_P$107") (pintype "power_in"))
      (node (ref "P2") (pin "P$108") (pinfunction "P$1_P$108") (pintype "power_in"))
      (node (ref "P2") (pin "P$109") (pinfunction "P$1_P$109") (pintype "power_in"))
      (node (ref "P2") (pin "P$11") (pinfunction "P$1_P$11") (pintype "power_in"))
      (node (ref "P2") (pin "P$110") (pinfunction "P$1_P$110") (pintype "power_in"))
      (node (ref "P2") (pin "P$111") (pinfunction "P$1_P$111") (pintype "power_in"))
      (node (ref "P2") (pin "P$112") (pinfunction "P$1_P$112") (pintype "power_in"))
      (node (ref "P2") (pin "P$113") (pinfunction "P$1_P$113") (pintype "power_in"))
      (node (ref "P2") (pin "P$114") (pinfunction "P$1_P$114") (pintype "power_in"))
      (node (ref "P2") (pin "P$115") (pinfunction "P$1_P$115") (pintype "power_in"))
      (node (ref "P2") (pin "P$116") (pinfunction "P$1_P$116") (pintype "power_in"))
      (node (ref "P2") (pin "P$117") (pinfunction "P$1_P$117") (pintype "power_in"))
      (node (ref "P2") (pin "P$118") (pinfunction "P$1_P$118") (pintype "power_in"))
      (node (ref "P2") (pin "P$119") (pinfunction "P$1_P$119") (pintype "power_in"))
      (node (ref "P2") (pin "P$12") (pinfunction "P$1_P$12") (pintype "power_in"))
      (node (ref "P2") (pin "P$120") (pinfunction "P$1_P$120") (pintype "power_in"))
      (node (ref "P2") (pin "P$121") (pinfunction "P$1_P$121") (pintype "power_in"))
      (node (ref "P2") (pin "P$122") (pinfunction "P$1_P$122") (pintype "power_in"))
      (node (ref "P2") (pin "P$123") (pinfunction "P$1_P$123") (pintype "power_in"))
      (node (ref "P2") (pin "P$124") (pinfunction "P$1_P$124") (pintype "power_in"))
      (node (ref "P2") (pin "P$125") (pinfunction "P$1_P$125") (pintype "power_in"))
      (node (ref "P2") (pin "P$126") (pinfunction "P$1_P$126") (pintype "power_in"))
      (node (ref "P2") (pin "P$127") (pinfunction "P$1_P$127") (pintype "power_in"))
      (node (ref "P2") (pin "P$128") (pinfunction "P$1_P$128") (pintype "power_in"))
      (node (ref "P2") (pin "P$129") (pinfunction "P$1_P$129") (pintype "power_in"))
      (node (ref "P2") (pin "P$13") (pinfunction "P$1_P$13") (pintype "power_in"))
      (node (ref "P2") (pin "P$130") (pinfunction "P$1_P$130") (pintype "power_in"))
      (node (ref "P2") (pin "P$131") (pinfunction "P$1_P$131") (pintype "power_in"))
      (node (ref "P2") (pin "P$132") (pinfunction "P$1_P$132") (pintype "power_in"))
      (node (ref "P2") (pin "P$133") (pinfunction "P$1_P$133") (pintype "power_in"))
      (node (ref "P2") (pin "P$134") (pinfunction "P$1_P$134") (pintype "power_in"))
      (node (ref "P2") (pin "P$135") (pinfunction "P$1_P$135") (pintype "power_in"))
      (node (ref "P2") (pin "P$136") (pinfunction "P$1_P$136") (pintype "power_in"))
      (node (ref "P2") (pin "P$137") (pinfunction "P$1_P$137") (pintype "power_in"))
      (node (ref "P2") (pin "P$138") (pinfunction "P$1_P$138") (pintype "power_in"))
      (node (ref "P2") (pin "P$139") (pinfunction "P$1_P$139") (pintype "power_in"))
      (node (ref "P2") (pin "P$14") (pinfunction "P$1_P$14") (pintype "power_in"))
      (node (ref "P2") (pin "P$140") (pinfunction "P$1_P$140") (pintype "power_in"))
      (node (ref "P2") (pin "P$141") (pinfunction "P$1_P$141") (pintype "power_in"))
      (node (ref "P2") (pin "P$142") (pinfunction "P$1_P$142") (pintype "power_in"))
      (node (ref "P2") (pin "P$143") (pinfunction "P$1_P$143") (pintype "power_in"))
      (node (ref "P2") (pin "P$144") (pinfunction "P$1_P$144") (pintype "power_in"))
      (node (ref "P2") (pin "P$145") (pinfunction "P$1_P$145") (pintype "power_in"))
      (node (ref "P2") (pin "P$146") (pinfunction "P$1_P$146") (pintype "power_in"))
      (node (ref "P2") (pin "P$147") (pinfunction "P$1_P$147") (pintype "power_in"))
      (node (ref "P2") (pin "P$148") (pinfunction "P$1_P$148") (pintype "power_in"))
      (node (ref "P2") (pin "P$149") (pinfunction "P$1_P$149") (pintype "power_in"))
      (node (ref "P2") (pin "P$15") (pinfunction "P$1_P$15") (pintype "power_in"))
      (node (ref "P2") (pin "P$150") (pinfunction "P$1_P$150") (pintype "power_in"))
      (node (ref "P2") (pin "P$151") (pinfunction "P$1_P$151") (pintype "power_in"))
      (node (ref "P2") (pin "P$152") (pinfunction "P$1_P$152") (pintype "power_in"))
      (node (ref "P2") (pin "P$153") (pinfunction "P$1_P$153") (pintype "power_in"))
      (node (ref "P2") (pin "P$154") (pinfunction "P$1_P$154") (pintype "power_in"))
      (node (ref "P2") (pin "P$155") (pinfunction "P$1_P$155") (pintype "power_in"))
      (node (ref "P2") (pin "P$156") (pinfunction "P$1_P$156") (pintype "power_in"))
      (node (ref "P2") (pin "P$157") (pinfunction "P$1_P$157") (pintype "power_in"))
      (node (ref "P2") (pin "P$158") (pinfunction "P$1_P$158") (pintype "power_in"))
      (node (ref "P2") (pin "P$159") (pinfunction "P$1_P$159") (pintype "power_in"))
      (node (ref "P2") (pin "P$16") (pinfunction "P$1_P$16") (pintype "power_in"))
      (node (ref "P2") (pin "P$160") (pinfunction "P$1_P$160") (pintype "power_in"))
      (node (ref "P2") (pin "P$161") (pinfunction "P$1_P$161") (pintype "power_in"))
      (node (ref "P2") (pin "P$162") (pinfunction "P$1_P$162") (pintype "power_in"))
      (node (ref "P2") (pin "P$163") (pinfunction "P$1_P$163") (pintype "power_in"))
      (node (ref "P2") (pin "P$164") (pinfunction "P$1_P$164") (pintype "power_in"))
      (node (ref "P2") (pin "P$165") (pinfunction "P$1_P$165") (pintype "power_in"))
      (node (ref "P2") (pin "P$166") (pinfunction "P$1_P$166") (pintype "power_in"))
      (node (ref "P2") (pin "P$167") (pinfunction "P$1_P$167") (pintype "power_in"))
      (node (ref "P2") (pin "P$168") (pinfunction "P$1_P$168") (pintype "power_in"))
      (node (ref "P2") (pin "P$169") (pinfunction "P$1_P$169") (pintype "power_in"))
      (node (ref "P2") (pin "P$17") (pinfunction "P$1_P$17") (pintype "power_in"))
      (node (ref "P2") (pin "P$170") (pinfunction "P$1_P$170") (pintype "power_in"))
      (node (ref "P2") (pin "P$171") (pinfunction "P$1_P$171") (pintype "power_in"))
      (node (ref "P2") (pin "P$172") (pinfunction "P$1_P$172") (pintype "power_in"))
      (node (ref "P2") (pin "P$173") (pinfunction "P$1_P$173") (pintype "power_in"))
      (node (ref "P2") (pin "P$174") (pinfunction "P$1_P$174") (pintype "power_in"))
      (node (ref "P2") (pin "P$175") (pinfunction "P$1_P$175") (pintype "power_in"))
      (node (ref "P2") (pin "P$176") (pinfunction "P$1_P$176") (pintype "power_in"))
      (node (ref "P2") (pin "P$177") (pinfunction "P$1_P$177") (pintype "power_in"))
      (node (ref "P2") (pin "P$178") (pinfunction "P$1_P$178") (pintype "power_in"))
      (node (ref "P2") (pin "P$179") (pinfunction "P$1_P$179") (pintype "power_in"))
      (node (ref "P2") (pin "P$18") (pinfunction "P$1_P$18") (pintype "power_in"))
      (node (ref "P2") (pin "P$180") (pinfunction "P$1_P$180") (pintype "power_in"))
      (node (ref "P2") (pin "P$181") (pinfunction "P$1_P$181") (pintype "power_in"))
      (node (ref "P2") (pin "P$182") (pinfunction "P$1_P$182") (pintype "power_in"))
      (node (ref "P2") (pin "P$183") (pinfunction "P$1_P$183") (pintype "power_in"))
      (node (ref "P2") (pin "P$184") (pinfunction "P$1_P$184") (pintype "power_in"))
      (node (ref "P2") (pin "P$185") (pinfunction "P$1_P$185") (pintype "power_in"))
      (node (ref "P2") (pin "P$186") (pinfunction "P$1_P$186") (pintype "power_in"))
      (node (ref "P2") (pin "P$187") (pinfunction "P$1_P$187") (pintype "power_in"))
      (node (ref "P2") (pin "P$188") (pinfunction "P$1_P$188") (pintype "power_in"))
      (node (ref "P2") (pin "P$189") (pinfunction "P$1_P$189") (pintype "power_in"))
      (node (ref "P2") (pin "P$19") (pinfunction "P$1_P$19") (pintype "power_in"))
      (node (ref "P2") (pin "P$190") (pinfunction "P$1_P$190") (pintype "power_in"))
      (node (ref "P2") (pin "P$191") (pinfunction "P$1_P$191") (pintype "power_in"))
      (node (ref "P2") (pin "P$192") (pinfunction "P$1_P$192") (pintype "power_in"))
      (node (ref "P2") (pin "P$193") (pinfunction "P$1_P$193") (pintype "power_in"))
      (node (ref "P2") (pin "P$194") (pinfunction "P$1_P$194") (pintype "power_in"))
      (node (ref "P2") (pin "P$195") (pinfunction "P$1_P$195") (pintype "power_in"))
      (node (ref "P2") (pin "P$196") (pinfunction "P$1_P$196") (pintype "power_in"))
      (node (ref "P2") (pin "P$197") (pinfunction "P$1_P$197") (pintype "power_in"))
      (node (ref "P2") (pin "P$198") (pinfunction "P$1_P$198") (pintype "power_in"))
      (node (ref "P2") (pin "P$199") (pinfunction "P$1_P$199") (pintype "power_in"))
      (node (ref "P2") (pin "P$2") (pinfunction "P$1_P$2") (pintype "power_in"))
      (node (ref "P2") (pin "P$20") (pinfunction "P$1_P$20") (pintype "power_in"))
      (node (ref "P2") (pin "P$200") (pinfunction "P$1_P$200") (pintype "power_in"))
      (node (ref "P2") (pin "P$201") (pinfunction "P$1_P$201") (pintype "power_in"))
      (node (ref "P2") (pin "P$202") (pinfunction "P$1_P$202") (pintype "power_in"))
      (node (ref "P2") (pin "P$203") (pinfunction "P$1_P$203") (pintype "power_in"))
      (node (ref "P2") (pin "P$204") (pinfunction "P$1_P$204") (pintype "power_in"))
      (node (ref "P2") (pin "P$205") (pinfunction "P$1_P$205") (pintype "power_in"))
      (node (ref "P2") (pin "P$206") (pinfunction "P$1_P$206") (pintype "power_in"))
      (node (ref "P2") (pin "P$207") (pinfunction "P$1_P$207") (pintype "power_in"))
      (node (ref "P2") (pin "P$208") (pinfunction "P$1_P$208") (pintype "power_in"))
      (node (ref "P2") (pin "P$209") (pinfunction "P$1_P$209") (pintype "power_in"))
      (node (ref "P2") (pin "P$21") (pinfunction "P$1_P$21") (pintype "power_in"))
      (node (ref "P2") (pin "P$210") (pinfunction "P$1_P$210") (pintype "power_in"))
      (node (ref "P2") (pin "P$211") (pinfunction "P$1_P$211") (pintype "power_in"))
      (node (ref "P2") (pin "P$212") (pinfunction "P$1_P$212") (pintype "power_in"))
      (node (ref "P2") (pin "P$213") (pinfunction "P$1_P$213") (pintype "power_in"))
      (node (ref "P2") (pin "P$214") (pinfunction "P$1_P$214") (pintype "power_in"))
      (node (ref "P2") (pin "P$215") (pinfunction "P$1_P$215") (pintype "power_in"))
      (node (ref "P2") (pin "P$216") (pinfunction "P$1_P$216") (pintype "power_in"))
      (node (ref "P2") (pin "P$217") (pinfunction "P$1_P$217") (pintype "power_in"))
      (node (ref "P2") (pin "P$218") (pinfunction "P$1_P$218") (pintype "power_in"))
      (node (ref "P2") (pin "P$219") (pinfunction "P$1_P$219") (pintype "power_in"))
      (node (ref "P2") (pin "P$22") (pinfunction "P$1_P$22") (pintype "power_in"))
      (node (ref "P2") (pin "P$220") (pinfunction "P$1_P$220") (pintype "power_in"))
      (node (ref "P2") (pin "P$221") (pinfunction "P$1_P$221") (pintype "power_in"))
      (node (ref "P2") (pin "P$222") (pinfunction "P$1_P$222") (pintype "power_in"))
      (node (ref "P2") (pin "P$223") (pinfunction "P$1_P$223") (pintype "power_in"))
      (node (ref "P2") (pin "P$224") (pinfunction "P$1_P$224") (pintype "power_in"))
      (node (ref "P2") (pin "P$225") (pinfunction "P$1_P$225") (pintype "power_in"))
      (node (ref "P2") (pin "P$226") (pinfunction "P$1_P$226") (pintype "power_in"))
      (node (ref "P2") (pin "P$227") (pinfunction "P$1_P$227") (pintype "power_in"))
      (node (ref "P2") (pin "P$228") (pinfunction "P$1_P$228") (pintype "power_in"))
      (node (ref "P2") (pin "P$229") (pinfunction "P$1_P$229") (pintype "power_in"))
      (node (ref "P2") (pin "P$23") (pinfunction "P$1_P$23") (pintype "power_in"))
      (node (ref "P2") (pin "P$230") (pinfunction "P$1_P$230") (pintype "power_in"))
      (node (ref "P2") (pin "P$231") (pinfunction "P$1_P$231") (pintype "power_in"))
      (node (ref "P2") (pin "P$232") (pinfunction "P$1_P$232") (pintype "power_in"))
      (node (ref "P2") (pin "P$233") (pinfunction "P$1_P$233") (pintype "power_in"))
      (node (ref "P2") (pin "P$234") (pinfunction "P$1_P$234") (pintype "power_in"))
      (node (ref "P2") (pin "P$235") (pinfunction "P$1_P$235") (pintype "power_in"))
      (node (ref "P2") (pin "P$236") (pinfunction "P$1_P$236") (pintype "power_in"))
      (node (ref "P2") (pin "P$237") (pinfunction "P$1_P$237") (pintype "power_in"))
      (node (ref "P2") (pin "P$238") (pinfunction "P$1_P$238") (pintype "power_in"))
      (node (ref "P2") (pin "P$239") (pinfunction "P$1_P$239") (pintype "power_in"))
      (node (ref "P2") (pin "P$24") (pinfunction "P$1_P$24") (pintype "power_in"))
      (node (ref "P2") (pin "P$240") (pinfunction "P$1_P$240") (pintype "power_in"))
      (node (ref "P2") (pin "P$241") (pinfunction "P$1_P$241") (pintype "power_in"))
      (node (ref "P2") (pin "P$242") (pinfunction "P$1_P$242") (pintype "power_in"))
      (node (ref "P2") (pin "P$243") (pinfunction "P$1_P$243") (pintype "power_in"))
      (node (ref "P2") (pin "P$244") (pinfunction "P$1_P$244") (pintype "power_in"))
      (node (ref "P2") (pin "P$245") (pinfunction "P$1_P$245") (pintype "power_in"))
      (node (ref "P2") (pin "P$246") (pinfunction "P$1_P$246") (pintype "power_in"))
      (node (ref "P2") (pin "P$247") (pinfunction "P$1_P$247") (pintype "power_in"))
      (node (ref "P2") (pin "P$248") (pinfunction "P$1_P$248") (pintype "power_in"))
      (node (ref "P2") (pin "P$249") (pinfunction "P$1_P$249") (pintype "power_in"))
      (node (ref "P2") (pin "P$25") (pinfunction "P$1_P$25") (pintype "power_in"))
      (node (ref "P2") (pin "P$250") (pinfunction "P$1_P$250") (pintype "power_in"))
      (node (ref "P2") (pin "P$251") (pinfunction "P$1_P$251") (pintype "power_in"))
      (node (ref "P2") (pin "P$252") (pinfunction "P$1_P$252") (pintype "power_in"))
      (node (ref "P2") (pin "P$253") (pinfunction "P$1_P$253") (pintype "power_in"))
      (node (ref "P2") (pin "P$254") (pinfunction "P$1_P$254") (pintype "power_in"))
      (node (ref "P2") (pin "P$255") (pinfunction "P$1_P$255") (pintype "power_in"))
      (node (ref "P2") (pin "P$256") (pinfunction "P$1_P$256") (pintype "power_in"))
      (node (ref "P2") (pin "P$257") (pinfunction "P$1_P$257") (pintype "power_in"))
      (node (ref "P2") (pin "P$258") (pinfunction "P$1_P$258") (pintype "power_in"))
      (node (ref "P2") (pin "P$259") (pinfunction "P$1_P$259") (pintype "power_in"))
      (node (ref "P2") (pin "P$26") (pinfunction "P$1_P$26") (pintype "power_in"))
      (node (ref "P2") (pin "P$260") (pinfunction "P$1_P$260") (pintype "power_in"))
      (node (ref "P2") (pin "P$261") (pinfunction "P$1_P$261") (pintype "power_in"))
      (node (ref "P2") (pin "P$262") (pinfunction "P$1_P$262") (pintype "power_in"))
      (node (ref "P2") (pin "P$263") (pinfunction "P$1_P$263") (pintype "power_in"))
      (node (ref "P2") (pin "P$264") (pinfunction "P$1_P$264") (pintype "power_in"))
      (node (ref "P2") (pin "P$265") (pinfunction "P$1_P$265") (pintype "power_in"))
      (node (ref "P2") (pin "P$266") (pinfunction "P$1_P$266") (pintype "power_in"))
      (node (ref "P2") (pin "P$267") (pinfunction "P$1_P$267") (pintype "power_in"))
      (node (ref "P2") (pin "P$268") (pinfunction "P$1_P$268") (pintype "power_in"))
      (node (ref "P2") (pin "P$269") (pinfunction "P$1_P$269") (pintype "power_in"))
      (node (ref "P2") (pin "P$27") (pinfunction "P$1_P$27") (pintype "power_in"))
      (node (ref "P2") (pin "P$270") (pinfunction "P$1_P$270") (pintype "power_in"))
      (node (ref "P2") (pin "P$271") (pinfunction "P$1_P$271") (pintype "power_in"))
      (node (ref "P2") (pin "P$272") (pinfunction "P$1_P$272") (pintype "power_in"))
      (node (ref "P2") (pin "P$273") (pinfunction "P$1_P$273") (pintype "power_in"))
      (node (ref "P2") (pin "P$274") (pinfunction "P$1_P$274") (pintype "power_in"))
      (node (ref "P2") (pin "P$275") (pinfunction "P$1_P$275") (pintype "power_in"))
      (node (ref "P2") (pin "P$276") (pinfunction "P$1_P$276") (pintype "power_in"))
      (node (ref "P2") (pin "P$277") (pinfunction "P$1_P$277") (pintype "power_in"))
      (node (ref "P2") (pin "P$278") (pinfunction "P$1_P$278") (pintype "power_in"))
      (node (ref "P2") (pin "P$279") (pinfunction "P$1_P$279") (pintype "power_in"))
      (node (ref "P2") (pin "P$28") (pinfunction "P$1_P$28") (pintype "power_in"))
      (node (ref "P2") (pin "P$280") (pinfunction "P$1_P$280") (pintype "power_in"))
      (node (ref "P2") (pin "P$281") (pinfunction "P$1_P$281") (pintype "power_in"))
      (node (ref "P2") (pin "P$282") (pinfunction "P$1_P$282") (pintype "power_in"))
      (node (ref "P2") (pin "P$283") (pinfunction "P$1_P$283") (pintype "power_in"))
      (node (ref "P2") (pin "P$284") (pinfunction "P$1_P$284") (pintype "power_in"))
      (node (ref "P2") (pin "P$285") (pinfunction "P$1_P$285") (pintype "power_in"))
      (node (ref "P2") (pin "P$286") (pinfunction "P$1_P$286") (pintype "power_in"))
      (node (ref "P2") (pin "P$287") (pinfunction "P$1_P$287") (pintype "power_in"))
      (node (ref "P2") (pin "P$288") (pinfunction "P$1_P$288") (pintype "power_in"))
      (node (ref "P2") (pin "P$29") (pinfunction "P$1_P$29") (pintype "power_in"))
      (node (ref "P2") (pin "P$3") (pinfunction "P$1_P$3") (pintype "power_in"))
      (node (ref "P2") (pin "P$30") (pinfunction "P$1_P$30") (pintype "power_in"))
      (node (ref "P2") (pin "P$31") (pinfunction "P$1_P$31") (pintype "power_in"))
      (node (ref "P2") (pin "P$32") (pinfunction "P$1_P$32") (pintype "power_in"))
      (node (ref "P2") (pin "P$33") (pinfunction "P$1_P$33") (pintype "power_in"))
      (node (ref "P2") (pin "P$34") (pinfunction "P$1_P$34") (pintype "power_in"))
      (node (ref "P2") (pin "P$35") (pinfunction "P$1_P$35") (pintype "power_in"))
      (node (ref "P2") (pin "P$36") (pinfunction "P$1_P$36") (pintype "power_in"))
      (node (ref "P2") (pin "P$37") (pinfunction "P$1_P$37") (pintype "power_in"))
      (node (ref "P2") (pin "P$38") (pinfunction "P$1_P$38") (pintype "power_in"))
      (node (ref "P2") (pin "P$39") (pinfunction "P$1_P$39") (pintype "power_in"))
      (node (ref "P2") (pin "P$4") (pinfunction "P$1_P$4") (pintype "power_in"))
      (node (ref "P2") (pin "P$40") (pinfunction "P$1_P$40") (pintype "power_in"))
      (node (ref "P2") (pin "P$41") (pinfunction "P$1_P$41") (pintype "power_in"))
      (node (ref "P2") (pin "P$42") (pinfunction "P$1_P$42") (pintype "power_in"))
      (node (ref "P2") (pin "P$43") (pinfunction "P$1_P$43") (pintype "power_in"))
      (node (ref "P2") (pin "P$44") (pinfunction "P$1_P$44") (pintype "power_in"))
      (node (ref "P2") (pin "P$45") (pinfunction "P$1_P$45") (pintype "power_in"))
      (node (ref "P2") (pin "P$46") (pinfunction "P$1_P$46") (pintype "power_in"))
      (node (ref "P2") (pin "P$47") (pinfunction "P$1_P$47") (pintype "power_in"))
      (node (ref "P2") (pin "P$48") (pinfunction "P$1_P$48") (pintype "power_in"))
      (node (ref "P2") (pin "P$49") (pinfunction "P$1_P$49") (pintype "power_in"))
      (node (ref "P2") (pin "P$5") (pinfunction "P$1_P$5") (pintype "power_in"))
      (node (ref "P2") (pin "P$50") (pinfunction "P$1_P$50") (pintype "power_in"))
      (node (ref "P2") (pin "P$51") (pinfunction "P$1_P$51") (pintype "power_in"))
      (node (ref "P2") (pin "P$52") (pinfunction "P$1_P$52") (pintype "power_in"))
      (node (ref "P2") (pin "P$53") (pinfunction "P$1_P$53") (pintype "power_in"))
      (node (ref "P2") (pin "P$54") (pinfunction "P$1_P$54") (pintype "power_in"))
      (node (ref "P2") (pin "P$55") (pinfunction "P$1_P$55") (pintype "power_in"))
      (node (ref "P2") (pin "P$56") (pinfunction "P$1_P$56") (pintype "power_in"))
      (node (ref "P2") (pin "P$57") (pinfunction "P$1_P$57") (pintype "power_in"))
      (node (ref "P2") (pin "P$58") (pinfunction "P$1_P$58") (pintype "power_in"))
      (node (ref "P2") (pin "P$59") (pinfunction "P$1_P$59") (pintype "power_in"))
      (node (ref "P2") (pin "P$6") (pinfunction "P$1_P$6") (pintype "power_in"))
      (node (ref "P2") (pin "P$60") (pinfunction "P$1_P$60") (pintype "power_in"))
      (node (ref "P2") (pin "P$61") (pinfunction "P$1_P$61") (pintype "power_in"))
      (node (ref "P2") (pin "P$62") (pinfunction "P$1_P$62") (pintype "power_in"))
      (node (ref "P2") (pin "P$63") (pinfunction "P$1_P$63") (pintype "power_in"))
      (node (ref "P2") (pin "P$64") (pinfunction "P$1_P$64") (pintype "power_in"))
      (node (ref "P2") (pin "P$65") (pinfunction "P$1_P$65") (pintype "power_in"))
      (node (ref "P2") (pin "P$66") (pinfunction "P$1_P$66") (pintype "power_in"))
      (node (ref "P2") (pin "P$67") (pinfunction "P$1_P$67") (pintype "power_in"))
      (node (ref "P2") (pin "P$68") (pinfunction "P$1_P$68") (pintype "power_in"))
      (node (ref "P2") (pin "P$69") (pinfunction "P$1_P$69") (pintype "power_in"))
      (node (ref "P2") (pin "P$7") (pinfunction "P$1_P$7") (pintype "power_in"))
      (node (ref "P2") (pin "P$70") (pinfunction "P$1_P$70") (pintype "power_in"))
      (node (ref "P2") (pin "P$71") (pinfunction "P$1_P$71") (pintype "power_in"))
      (node (ref "P2") (pin "P$72") (pinfunction "P$1_P$72") (pintype "power_in"))
      (node (ref "P2") (pin "P$73") (pinfunction "P$1_P$73") (pintype "power_in"))
      (node (ref "P2") (pin "P$74") (pinfunction "P$1_P$74") (pintype "power_in"))
      (node (ref "P2") (pin "P$75") (pinfunction "P$1_P$75") (pintype "power_in"))
      (node (ref "P2") (pin "P$76") (pinfunction "P$1_P$76") (pintype "power_in"))
      (node (ref "P2") (pin "P$77") (pinfunction "P$1_P$77") (pintype "power_in"))
      (node (ref "P2") (pin "P$78") (pinfunction "P$1_P$78") (pintype "power_in"))
      (node (ref "P2") (pin "P$79") (pinfunction "P$1_P$79") (pintype "power_in"))
      (node (ref "P2") (pin "P$8") (pinfunction "P$1_P$8") (pintype "power_in"))
      (node (ref "P2") (pin "P$80") (pinfunction "P$1_P$80") (pintype "power_in"))
      (node (ref "P2") (pin "P$81") (pinfunction "P$1_P$81") (pintype "power_in"))
      (node (ref "P2") (pin "P$82") (pinfunction "P$1_P$82") (pintype "power_in"))
      (node (ref "P2") (pin "P$83") (pinfunction "P$1_P$83") (pintype "power_in"))
      (node (ref "P2") (pin "P$84") (pinfunction "P$1_P$84") (pintype "power_in"))
      (node (ref "P2") (pin "P$85") (pinfunction "P$1_P$85") (pintype "power_in"))
      (node (ref "P2") (pin "P$86") (pinfunction "P$1_P$86") (pintype "power_in"))
      (node (ref "P2") (pin "P$87") (pinfunction "P$1_P$87") (pintype "power_in"))
      (node (ref "P2") (pin "P$88") (pinfunction "P$1_P$88") (pintype "power_in"))
      (node (ref "P2") (pin "P$89") (pinfunction "P$1_P$89") (pintype "power_in"))
      (node (ref "P2") (pin "P$9") (pinfunction "P$1_P$9") (pintype "power_in"))
      (node (ref "P2") (pin "P$90") (pinfunction "P$1_P$90") (pintype "power_in"))
      (node (ref "P2") (pin "P$91") (pinfunction "P$1_P$91") (pintype "power_in"))
      (node (ref "P2") (pin "P$92") (pinfunction "P$1_P$92") (pintype "power_in"))
      (node (ref "P2") (pin "P$93") (pinfunction "P$1_P$93") (pintype "power_in"))
      (node (ref "P2") (pin "P$94") (pinfunction "P$1_P$94") (pintype "power_in"))
      (node (ref "P2") (pin "P$95") (pinfunction "P$1_P$95") (pintype "power_in"))
      (node (ref "P2") (pin "P$96") (pinfunction "P$1_P$96") (pintype "power_in"))
      (node (ref "P2") (pin "P$97") (pinfunction "P$1_P$97") (pintype "power_in"))
      (node (ref "P2") (pin "P$98") (pinfunction "P$1_P$98") (pintype "power_in"))
      (node (ref "P2") (pin "P$99") (pinfunction "P$1_P$99") (pintype "power_in"))
    )
    (net (code "5") (name "/P3") (class "Default")
      (node (ref "JP1") (pin "P$4") (pinfunction "3_P$4") (pintype "bidirectional"))
      (node (ref "P3") (pin "P$1") (pinfunction "P$1_P$1") (pintype "power_in"))
      (node (ref "P3") (pin "P$10") (pinfunction "P$1_P$10") (pintype "power_in"))
      (node (ref "P3") (pin "P$100") (pinfunction "P$1_P$100") (pintype "power_in"))
      (node (ref "P3") (pin "P$101") (pinfunction "P$1_P$101") (pintype "power_in"))
      (node (ref "P3") (pin "P$102") (pinfunction "P$1_P$102") (pintype "power_in"))
      (node (ref "P3") (pin "P$103") (pinfunction "P$1_P$103") (pintype "power_in"))
      (node (ref "P3") (pin "P$104") (pinfunction "P$1_P$104") (pintype "power_in"))
      (node (ref "P3") (pin "P$105") (pinfunction "P$1_P$105") (pintype "power_in"))
      (node (ref "P3") (pin "P$106") (pinfunction "P$1_P$106") (pintype "power_in"))
      (node (ref "P3") (pin "P$107") (pinfunction "P$1_P$107") (pintype "power_in"))
      (node (ref "P3") (pin "P$108") (pinfunction "P$1_P$108") (pintype "power_in"))
      (node (ref "P3") (pin "P$109") (pinfunction "P$1_P$109") (pintype "power_in"))
      (node (ref "P3") (pin "P$11") (pinfunction "P$1_P$11") (pintype "power_in"))
      (node (ref "P3") (pin "P$110") (pinfunction "P$1_P$110") (pintype "power_in"))
      (node (ref "P3") (pin "P$111") (pinfunction "P$1_P$111") (pintype "power_in"))
      (node (ref "P3") (pin "P$112") (pinfunction "P$1_P$112") (pintype "power_in"))
      (node (ref "P3") (pin "P$113") (pinfunction "P$1_P$113") (pintype "power_in"))
      (node (ref "P3") (pin "P$114") (pinfunction "P$1_P$114") (pintype "power_in"))
      (node (ref "P3") (pin "P$115") (pinfunction "P$1_P$115") (pintype "power_in"))
      (node (ref "P3") (pin "P$116") (pinfunction "P$1_P$116") (pintype "power_in"))
      (node (ref "P3") (pin "P$117") (pinfunction "P$1_P$117") (pintype "power_in"))
      (node (ref "P3") (pin "P$118") (pinfunction "P$1_P$118") (pintype "power_in"))
      (node (ref "P3") (pin "P$119") (pinfunction "P$1_P$119") (pintype "power_in"))
      (node (ref "P3") (pin "P$12") (pinfunction "P$1_P$12") (pintype "power_in"))
      (node (ref "P3") (pin "P$120") (pinfunction "P$1_P$120") (pintype "power_in"))
      (node (ref "P3") (pin "P$121") (pinfunction "P$1_P$121") (pintype "power_in"))
      (node (ref "P3") (pin "P$122") (pinfunction "P$1_P$122") (pintype "power_in"))
      (node (ref "P3") (pin "P$123") (pinfunction "P$1_P$123") (pintype "power_in"))
      (node (ref "P3") (pin "P$124") (pinfunction "P$1_P$124") (pintype "power_in"))
      (node (ref "P3") (pin "P$125") (pinfunction "P$1_P$125") (pintype "power_in"))
      (node (ref "P3") (pin "P$126") (pinfunction "P$1_P$126") (pintype "power_in"))
      (node (ref "P3") (pin "P$127") (pinfunction "P$1_P$127") (pintype "power_in"))
      (node (ref "P3") (pin "P$128") (pinfunction "P$1_P$128") (pintype "power_in"))
      (node (ref "P3") (pin "P$129") (pinfunction "P$1_P$129") (pintype "power_in"))
      (node (ref "P3") (pin "P$13") (pinfunction "P$1_P$13") (pintype "power_in"))
      (node (ref "P3") (pin "P$130") (pinfunction "P$1_P$130") (pintype "power_in"))
      (node (ref "P3") (pin "P$131") (pinfunction "P$1_P$131") (pintype "power_in"))
      (node (ref "P3") (pin "P$132") (pinfunction "P$1_P$132") (pintype "power_in"))
      (node (ref "P3") (pin "P$133") (pinfunction "P$1_P$133") (pintype "power_in"))
      (node (ref "P3") (pin "P$134") (pinfunction "P$1_P$134") (pintype "power_in"))
      (node (ref "P3") (pin "P$135") (pinfunction "P$1_P$135") (pintype "power_in"))
      (node (ref "P3") (pin "P$136") (pinfunction "P$1_P$136") (pintype "power_in"))
      (node (ref "P3") (pin "P$137") (pinfunction "P$1_P$137") (pintype "power_in"))
      (node (ref "P3") (pin "P$138") (pinfunction "P$1_P$138") (pintype "power_in"))
      (node (ref "P3") (pin "P$139") (pinfunction "P$1_P$139") (pintype "power_in"))
      (node (ref "P3") (pin "P$14") (pinfunction "P$1_P$14") (pintype "power_in"))
      (node (ref "P3") (pin "P$140") (pinfunction "P$1_P$140") (pintype "power_in"))
      (node (ref "P3") (pin "P$141") (pinfunction "P$1_P$141") (pintype "power_in"))
      (node (ref "P3") (pin "P$142") (pinfunction "P$1_P$142") (pintype "power_in"))
      (node (ref "P3") (pin "P$143") (pinfunction "P$1_P$143") (pintype "power_in"))
      (node (ref "P3") (pin "P$144") (pinfunction "P$1_P$144") (pintype "power_in"))
      (node (ref "P3") (pin "P$145") (pinfunction "P$1_P$145") (pintype "power_in"))
      (node (ref "P3") (pin "P$146") (pinfunction "P$1_P$146") (pintype "power_in"))
      (node (ref "P3") (pin "P$147") (pinfunction "P$1_P$147") (pintype "power_in"))
      (node (ref "P3") (pin "P$148") (pinfunction "P$1_P$148") (pintype "power_in"))
      (node (ref "P3") (pin "P$149") (pinfunction "P$1_P$149") (pintype "power_in"))
      (node (ref "P3") (pin "P$15") (pinfunction "P$1_P$15") (pintype "power_in"))
      (node (ref "P3") (pin "P$150") (pinfunction "P$1_P$150") (pintype "power_in"))
      (node (ref "P3") (pin "P$151") (pinfunction "P$1_P$151") (pintype "power_in"))
      (node (ref "P3") (pin "P$152") (pinfunction "P$1_P$152") (pintype "power_in"))
      (node (ref "P3") (pin "P$153") (pinfunction "P$1_P$153") (pintype "power_in"))
      (node (ref "P3") (pin "P$154") (pinfunction "P$1_P$154") (pintype "power_in"))
      (node (ref "P3") (pin "P$155") (pinfunction "P$1_P$155") (pintype "power_in"))
      (node (ref "P3") (pin "P$156") (pinfunction "P$1_P$156") (pintype "power_in"))
      (node (ref "P3") (pin "P$157") (pinfunction "P$1_P$157") (pintype "power_in"))
      (node (ref "P3") (pin "P$158") (pinfunction "P$1_P$158") (pintype "power_in"))
      (node (ref "P3") (pin "P$159") (pinfunction "P$1_P$159") (pintype "power_in"))
      (node (ref "P3") (pin "P$16") (pinfunction "P$1_P$16") (pintype "power_in"))
      (node (ref "P3") (pin "P$160") (pinfunction "P$1_P$160") (pintype "power_in"))
      (node (ref "P3") (pin "P$161") (pinfunction "P$1_P$161") (pintype "power_in"))
      (node (ref "P3") (pin "P$162") (pinfunction "P$1_P$162") (pintype "power_in"))
      (node (ref "P3") (pin "P$163") (pinfunction "P$1_P$163") (pintype "power_in"))
      (node (ref "P3") (pin "P$164") (pinfunction "P$1_P$164") (pintype "power_in"))
      (node (ref "P3") (pin "P$165") (pinfunction "P$1_P$165") (pintype "power_in"))
      (node (ref "P3") (pin "P$166") (pinfunction "P$1_P$166") (pintype "power_in"))
      (node (ref "P3") (pin "P$167") (pinfunction "P$1_P$167") (pintype "power_in"))
      (node (ref "P3") (pin "P$168") (pinfunction "P$1_P$168") (pintype "power_in"))
      (node (ref "P3") (pin "P$169") (pinfunction "P$1_P$169") (pintype "power_in"))
      (node (ref "P3") (pin "P$17") (pinfunction "P$1_P$17") (pintype "power_in"))
      (node (ref "P3") (pin "P$170") (pinfunction "P$1_P$170") (pintype "power_in"))
      (node (ref "P3") (pin "P$171") (pinfunction "P$1_P$171") (pintype "power_in"))
      (node (ref "P3") (pin "P$172") (pinfunction "P$1_P$172") (pintype "power_in"))
      (node (ref "P3") (pin "P$173") (pinfunction "P$1_P$173") (pintype "power_in"))
      (node (ref "P3") (pin "P$174") (pinfunction "P$1_P$174") (pintype "power_in"))
      (node (ref "P3") (pin "P$175") (pinfunction "P$1_P$175") (pintype "power_in"))
      (node (ref "P3") (pin "P$176") (pinfunction "P$1_P$176") (pintype "power_in"))
      (node (ref "P3") (pin "P$177") (pinfunction "P$1_P$177") (pintype "power_in"))
      (node (ref "P3") (pin "P$178") (pinfunction "P$1_P$178") (pintype "power_in"))
      (node (ref "P3") (pin "P$179") (pinfunction "P$1_P$179") (pintype "power_in"))
      (node (ref "P3") (pin "P$18") (pinfunction "P$1_P$18") (pintype "power_in"))
      (node (ref "P3") (pin "P$180") (pinfunction "P$1_P$180") (pintype "power_in"))
      (node (ref "P3") (pin "P$181") (pinfunction "P$1_P$181") (pintype "power_in"))
      (node (ref "P3") (pin "P$182") (pinfunction "P$1_P$182") (pintype "power_in"))
      (node (ref "P3") (pin "P$183") (pinfunction "P$1_P$183") (pintype "power_in"))
      (node (ref "P3") (pin "P$184") (pinfunction "P$1_P$184") (pintype "power_in"))
      (node (ref "P3") (pin "P$185") (pinfunction "P$1_P$185") (pintype "power_in"))
      (node (ref "P3") (pin "P$186") (pinfunction "P$1_P$186") (pintype "power_in"))
      (node (ref "P3") (pin "P$187") (pinfunction "P$1_P$187") (pintype "power_in"))
      (node (ref "P3") (pin "P$188") (pinfunction "P$1_P$188") (pintype "power_in"))
      (node (ref "P3") (pin "P$189") (pinfunction "P$1_P$189") (pintype "power_in"))
      (node (ref "P3") (pin "P$19") (pinfunction "P$1_P$19") (pintype "power_in"))
      (node (ref "P3") (pin "P$190") (pinfunction "P$1_P$190") (pintype "power_in"))
      (node (ref "P3") (pin "P$191") (pinfunction "P$1_P$191") (pintype "power_in"))
      (node (ref "P3") (pin "P$192") (pinfunction "P$1_P$192") (pintype "power_in"))
      (node (ref "P3") (pin "P$193") (pinfunction "P$1_P$193") (pintype "power_in"))
      (node (ref "P3") (pin "P$194") (pinfunction "P$1_P$194") (pintype "power_in"))
      (node (ref "P3") (pin "P$195") (pinfunction "P$1_P$195") (pintype "power_in"))
      (node (ref "P3") (pin "P$196") (pinfunction "P$1_P$196") (pintype "power_in"))
      (node (ref "P3") (pin "P$197") (pinfunction "P$1_P$197") (pintype "power_in"))
      (node (ref "P3") (pin "P$198") (pinfunction "P$1_P$198") (pintype "power_in"))
      (node (ref "P3") (pin "P$199") (pinfunction "P$1_P$199") (pintype "power_in"))
      (node (ref "P3") (pin "P$2") (pinfunction "P$1_P$2") (pintype "power_in"))
      (node (ref "P3") (pin "P$20") (pinfunction "P$1_P$20") (pintype "power_in"))
      (node (ref "P3") (pin "P$200") (pinfunction "P$1_P$200") (pintype "power_in"))
      (node (ref "P3") (pin "P$201") (pinfunction "P$1_P$201") (pintype "power_in"))
      (node (ref "P3") (pin "P$202") (pinfunction "P$1_P$202") (pintype "power_in"))
      (node (ref "P3") (pin "P$203") (pinfunction "P$1_P$203") (pintype "power_in"))
      (node (ref "P3") (pin "P$204") (pinfunction "P$1_P$204") (pintype "power_in"))
      (node (ref "P3") (pin "P$205") (pinfunction "P$1_P$205") (pintype "power_in"))
      (node (ref "P3") (pin "P$206") (pinfunction "P$1_P$206") (pintype "power_in"))
      (node (ref "P3") (pin "P$207") (pinfunction "P$1_P$207") (pintype "power_in"))
      (node (ref "P3") (pin "P$208") (pinfunction "P$1_P$208") (pintype "power_in"))
      (node (ref "P3") (pin "P$209") (pinfunction "P$1_P$209") (pintype "power_in"))
      (node (ref "P3") (pin "P$21") (pinfunction "P$1_P$21") (pintype "power_in"))
      (node (ref "P3") (pin "P$210") (pinfunction "P$1_P$210") (pintype "power_in"))
      (node (ref "P3") (pin "P$211") (pinfunction "P$1_P$211") (pintype "power_in"))
      (node (ref "P3") (pin "P$212") (pinfunction "P$1_P$212") (pintype "power_in"))
      (node (ref "P3") (pin "P$213") (pinfunction "P$1_P$213") (pintype "power_in"))
      (node (ref "P3") (pin "P$214") (pinfunction "P$1_P$214") (pintype "power_in"))
      (node (ref "P3") (pin "P$215") (pinfunction "P$1_P$215") (pintype "power_in"))
      (node (ref "P3") (pin "P$216") (pinfunction "P$1_P$216") (pintype "power_in"))
      (node (ref "P3") (pin "P$217") (pinfunction "P$1_P$217") (pintype "power_in"))
      (node (ref "P3") (pin "P$218") (pinfunction "P$1_P$218") (pintype "power_in"))
      (node (ref "P3") (pin "P$219") (pinfunction "P$1_P$219") (pintype "power_in"))
      (node (ref "P3") (pin "P$22") (pinfunction "P$1_P$22") (pintype "power_in"))
      (node (ref "P3") (pin "P$220") (pinfunction "P$1_P$220") (pintype "power_in"))
      (node (ref "P3") (pin "P$221") (pinfunction "P$1_P$221") (pintype "power_in"))
      (node (ref "P3") (pin "P$222") (pinfunction "P$1_P$222") (pintype "power_in"))
      (node (ref "P3") (pin "P$223") (pinfunction "P$1_P$223") (pintype "power_in"))
      (node (ref "P3") (pin "P$224") (pinfunction "P$1_P$224") (pintype "power_in"))
      (node (ref "P3") (pin "P$225") (pinfunction "P$1_P$225") (pintype "power_in"))
      (node (ref "P3") (pin "P$226") (pinfunction "P$1_P$226") (pintype "power_in"))
      (node (ref "P3") (pin "P$227") (pinfunction "P$1_P$227") (pintype "power_in"))
      (node (ref "P3") (pin "P$228") (pinfunction "P$1_P$228") (pintype "power_in"))
      (node (ref "P3") (pin "P$229") (pinfunction "P$1_P$229") (pintype "power_in"))
      (node (ref "P3") (pin "P$23") (pinfunction "P$1_P$23") (pintype "power_in"))
      (node (ref "P3") (pin "P$230") (pinfunction "P$1_P$230") (pintype "power_in"))
      (node (ref "P3") (pin "P$231") (pinfunction "P$1_P$231") (pintype "power_in"))
      (node (ref "P3") (pin "P$232") (pinfunction "P$1_P$232") (pintype "power_in"))
      (node (ref "P3") (pin "P$233") (pinfunction "P$1_P$233") (pintype "power_in"))
      (node (ref "P3") (pin "P$234") (pinfunction "P$1_P$234") (pintype "power_in"))
      (node (ref "P3") (pin "P$235") (pinfunction "P$1_P$235") (pintype "power_in"))
      (node (ref "P3") (pin "P$236") (pinfunction "P$1_P$236") (pintype "power_in"))
      (node (ref "P3") (pin "P$237") (pinfunction "P$1_P$237") (pintype "power_in"))
      (node (ref "P3") (pin "P$238") (pinfunction "P$1_P$238") (pintype "power_in"))
      (node (ref "P3") (pin "P$239") (pinfunction "P$1_P$239") (pintype "power_in"))
      (node (ref "P3") (pin "P$24") (pinfunction "P$1_P$24") (pintype "power_in"))
      (node (ref "P3") (pin "P$240") (pinfunction "P$1_P$240") (pintype "power_in"))
      (node (ref "P3") (pin "P$241") (pinfunction "P$1_P$241") (pintype "power_in"))
      (node (ref "P3") (pin "P$242") (pinfunction "P$1_P$242") (pintype "power_in"))
      (node (ref "P3") (pin "P$243") (pinfunction "P$1_P$243") (pintype "power_in"))
      (node (ref "P3") (pin "P$244") (pinfunction "P$1_P$244") (pintype "power_in"))
      (node (ref "P3") (pin "P$245") (pinfunction "P$1_P$245") (pintype "power_in"))
      (node (ref "P3") (pin "P$246") (pinfunction "P$1_P$246") (pintype "power_in"))
      (node (ref "P3") (pin "P$247") (pinfunction "P$1_P$247") (pintype "power_in"))
      (node (ref "P3") (pin "P$248") (pinfunction "P$1_P$248") (pintype "power_in"))
      (node (ref "P3") (pin "P$249") (pinfunction "P$1_P$249") (pintype "power_in"))
      (node (ref "P3") (pin "P$25") (pinfunction "P$1_P$25") (pintype "power_in"))
      (node (ref "P3") (pin "P$250") (pinfunction "P$1_P$250") (pintype "power_in"))
      (node (ref "P3") (pin "P$251") (pinfunction "P$1_P$251") (pintype "power_in"))
      (node (ref "P3") (pin "P$252") (pinfunction "P$1_P$252") (pintype "power_in"))
      (node (ref "P3") (pin "P$253") (pinfunction "P$1_P$253") (pintype "power_in"))
      (node (ref "P3") (pin "P$254") (pinfunction "P$1_P$254") (pintype "power_in"))
      (node (ref "P3") (pin "P$255") (pinfunction "P$1_P$255") (pintype "power_in"))
      (node (ref "P3") (pin "P$256") (pinfunction "P$1_P$256") (pintype "power_in"))
      (node (ref "P3") (pin "P$257") (pinfunction "P$1_P$257") (pintype "power_in"))
      (node (ref "P3") (pin "P$258") (pinfunction "P$1_P$258") (pintype "power_in"))
      (node (ref "P3") (pin "P$259") (pinfunction "P$1_P$259") (pintype "power_in"))
      (node (ref "P3") (pin "P$26") (pinfunction "P$1_P$26") (pintype "power_in"))
      (node (ref "P3") (pin "P$260") (pinfunction "P$1_P$260") (pintype "power_in"))
      (node (ref "P3") (pin "P$261") (pinfunction "P$1_P$261") (pintype "power_in"))
      (node (ref "P3") (pin "P$262") (pinfunction "P$1_P$262") (pintype "power_in"))
      (node (ref "P3") (pin "P$263") (pinfunction "P$1_P$263") (pintype "power_in"))
      (node (ref "P3") (pin "P$264") (pinfunction "P$1_P$264") (pintype "power_in"))
      (node (ref "P3") (pin "P$265") (pinfunction "P$1_P$265") (pintype "power_in"))
      (node (ref "P3") (pin "P$266") (pinfunction "P$1_P$266") (pintype "power_in"))
      (node (ref "P3") (pin "P$267") (pinfunction "P$1_P$267") (pintype "power_in"))
      (node (ref "P3") (pin "P$268") (pinfunction "P$1_P$268") (pintype "power_in"))
      (node (ref "P3") (pin "P$269") (pinfunction "P$1_P$269") (pintype "power_in"))
      (node (ref "P3") (pin "P$27") (pinfunction "P$1_P$27") (pintype "power_in"))
      (node (ref "P3") (pin "P$270") (pinfunction "P$1_P$270") (pintype "power_in"))
      (node (ref "P3") (pin "P$271") (pinfunction "P$1_P$271") (pintype "power_in"))
      (node (ref "P3") (pin "P$272") (pinfunction "P$1_P$272") (pintype "power_in"))
      (node (ref "P3") (pin "P$273") (pinfunction "P$1_P$273") (pintype "power_in"))
      (node (ref "P3") (pin "P$274") (pinfunction "P$1_P$274") (pintype "power_in"))
      (node (ref "P3") (pin "P$275") (pinfunction "P$1_P$275") (pintype "power_in"))
      (node (ref "P3") (pin "P$276") (pinfunction "P$1_P$276") (pintype "power_in"))
      (node (ref "P3") (pin "P$277") (pinfunction "P$1_P$277") (pintype "power_in"))
      (node (ref "P3") (pin "P$278") (pinfunction "P$1_P$278") (pintype "power_in"))
      (node (ref "P3") (pin "P$279") (pinfunction "P$1_P$279") (pintype "power_in"))
      (node (ref "P3") (pin "P$28") (pinfunction "P$1_P$28") (pintype "power_in"))
      (node (ref "P3") (pin "P$280") (pinfunction "P$1_P$280") (pintype "power_in"))
      (node (ref "P3") (pin "P$281") (pinfunction "P$1_P$281") (pintype "power_in"))
      (node (ref "P3") (pin "P$282") (pinfunction "P$1_P$282") (pintype "power_in"))
      (node (ref "P3") (pin "P$283") (pinfunction "P$1_P$283") (pintype "power_in"))
      (node (ref "P3") (pin "P$284") (pinfunction "P$1_P$284") (pintype "power_in"))
      (node (ref "P3") (pin "P$285") (pinfunction "P$1_P$285") (pintype "power_in"))
      (node (ref "P3") (pin "P$286") (pinfunction "P$1_P$286") (pintype "power_in"))
      (node (ref "P3") (pin "P$287") (pinfunction "P$1_P$287") (pintype "power_in"))
      (node (ref "P3") (pin "P$288") (pinfunction "P$1_P$288") (pintype "power_in"))
      (node (ref "P3") (pin "P$29") (pinfunction "P$1_P$29") (pintype "power_in"))
      (node (ref "P3") (pin "P$3") (pinfunction "P$1_P$3") (pintype "power_in"))
      (node (ref "P3") (pin "P$30") (pinfunction "P$1_P$30") (pintype "power_in"))
      (node (ref "P3") (pin "P$31") (pinfunction "P$1_P$31") (pintype "power_in"))
      (node (ref "P3") (pin "P$32") (pinfunction "P$1_P$32") (pintype "power_in"))
      (node (ref "P3") (pin "P$33") (pinfunction "P$1_P$33") (pintype "power_in"))
      (node (ref "P3") (pin "P$34") (pinfunction "P$1_P$34") (pintype "power_in"))
      (node (ref "P3") (pin "P$35") (pinfunction "P$1_P$35") (pintype "power_in"))
      (node (ref "P3") (pin "P$36") (pinfunction "P$1_P$36") (pintype "power_in"))
      (node (ref "P3") (pin "P$37") (pinfunction "P$1_P$37") (pintype "power_in"))
      (node (ref "P3") (pin "P$38") (pinfunction "P$1_P$38") (pintype "power_in"))
      (node (ref "P3") (pin "P$39") (pinfunction "P$1_P$39") (pintype "power_in"))
      (node (ref "P3") (pin "P$4") (pinfunction "P$1_P$4") (pintype "power_in"))
      (node (ref "P3") (pin "P$40") (pinfunction "P$1_P$40") (pintype "power_in"))
      (node (ref "P3") (pin "P$41") (pinfunction "P$1_P$41") (pintype "power_in"))
      (node (ref "P3") (pin "P$42") (pinfunction "P$1_P$42") (pintype "power_in"))
      (node (ref "P3") (pin "P$43") (pinfunction "P$1_P$43") (pintype "power_in"))
      (node (ref "P3") (pin "P$44") (pinfunction "P$1_P$44") (pintype "power_in"))
      (node (ref "P3") (pin "P$45") (pinfunction "P$1_P$45") (pintype "power_in"))
      (node (ref "P3") (pin "P$46") (pinfunction "P$1_P$46") (pintype "power_in"))
      (node (ref "P3") (pin "P$47") (pinfunction "P$1_P$47") (pintype "power_in"))
      (node (ref "P3") (pin "P$48") (pinfunction "P$1_P$48") (pintype "power_in"))
      (node (ref "P3") (pin "P$49") (pinfunction "P$1_P$49") (pintype "power_in"))
      (node (ref "P3") (pin "P$5") (pinfunction "P$1_P$5") (pintype "power_in"))
      (node (ref "P3") (pin "P$50") (pinfunction "P$1_P$50") (pintype "power_in"))
      (node (ref "P3") (pin "P$51") (pinfunction "P$1_P$51") (pintype "power_in"))
      (node (ref "P3") (pin "P$52") (pinfunction "P$1_P$52") (pintype "power_in"))
      (node (ref "P3") (pin "P$53") (pinfunction "P$1_P$53") (pintype "power_in"))
      (node (ref "P3") (pin "P$54") (pinfunction "P$1_P$54") (pintype "power_in"))
      (node (ref "P3") (pin "P$55") (pinfunction "P$1_P$55") (pintype "power_in"))
      (node (ref "P3") (pin "P$56") (pinfunction "P$1_P$56") (pintype "power_in"))
      (node (ref "P3") (pin "P$57") (pinfunction "P$1_P$57") (pintype "power_in"))
      (node (ref "P3") (pin "P$58") (pinfunction "P$1_P$58") (pintype "power_in"))
      (node (ref "P3") (pin "P$59") (pinfunction "P$1_P$59") (pintype "power_in"))
      (node (ref "P3") (pin "P$6") (pinfunction "P$1_P$6") (pintype "power_in"))
      (node (ref "P3") (pin "P$60") (pinfunction "P$1_P$60") (pintype "power_in"))
      (node (ref "P3") (pin "P$61") (pinfunction "P$1_P$61") (pintype "power_in"))
      (node (ref "P3") (pin "P$62") (pinfunction "P$1_P$62") (pintype "power_in"))
      (node (ref "P3") (pin "P$63") (pinfunction "P$1_P$63") (pintype "power_in"))
      (node (ref "P3") (pin "P$64") (pinfunction "P$1_P$64") (pintype "power_in"))
      (node (ref "P3") (pin "P$65") (pinfunction "P$1_P$65") (pintype "power_in"))
      (node (ref "P3") (pin "P$66") (pinfunction "P$1_P$66") (pintype "power_in"))
      (node (ref "P3") (pin "P$67") (pinfunction "P$1_P$67") (pintype "power_in"))
      (node (ref "P3") (pin "P$68") (pinfunction "P$1_P$68") (pintype "power_in"))
      (node (ref "P3") (pin "P$69") (pinfunction "P$1_P$69") (pintype "power_in"))
      (node (ref "P3") (pin "P$7") (pinfunction "P$1_P$7") (pintype "power_in"))
      (node (ref "P3") (pin "P$70") (pinfunction "P$1_P$70") (pintype "power_in"))
      (node (ref "P3") (pin "P$71") (pinfunction "P$1_P$71") (pintype "power_in"))
      (node (ref "P3") (pin "P$72") (pinfunction "P$1_P$72") (pintype "power_in"))
      (node (ref "P3") (pin "P$73") (pinfunction "P$1_P$73") (pintype "power_in"))
      (node (ref "P3") (pin "P$74") (pinfunction "P$1_P$74") (pintype "power_in"))
      (node (ref "P3") (pin "P$75") (pinfunction "P$1_P$75") (pintype "power_in"))
      (node (ref "P3") (pin "P$76") (pinfunction "P$1_P$76") (pintype "power_in"))
      (node (ref "P3") (pin "P$77") (pinfunction "P$1_P$77") (pintype "power_in"))
      (node (ref "P3") (pin "P$78") (pinfunction "P$1_P$78") (pintype "power_in"))
      (node (ref "P3") (pin "P$79") (pinfunction "P$1_P$79") (pintype "power_in"))
      (node (ref "P3") (pin "P$8") (pinfunction "P$1_P$8") (pintype "power_in"))
      (node (ref "P3") (pin "P$80") (pinfunction "P$1_P$80") (pintype "power_in"))
      (node (ref "P3") (pin "P$81") (pinfunction "P$1_P$81") (pintype "power_in"))
      (node (ref "P3") (pin "P$82") (pinfunction "P$1_P$82") (pintype "power_in"))
      (node (ref "P3") (pin "P$83") (pinfunction "P$1_P$83") (pintype "power_in"))
      (node (ref "P3") (pin "P$84") (pinfunction "P$1_P$84") (pintype "power_in"))
      (node (ref "P3") (pin "P$85") (pinfunction "P$1_P$85") (pintype "power_in"))
      (node (ref "P3") (pin "P$86") (pinfunction "P$1_P$86") (pintype "power_in"))
      (node (ref "P3") (pin "P$87") (pinfunction "P$1_P$87") (pintype "power_in"))
      (node (ref "P3") (pin "P$88") (pinfunction "P$1_P$88") (pintype "power_in"))
      (node (ref "P3") (pin "P$89") (pinfunction "P$1_P$89") (pintype "power_in"))
      (node (ref "P3") (pin "P$9") (pinfunction "P$1_P$9") (pintype "power_in"))
      (node (ref "P3") (pin "P$90") (pinfunction "P$1_P$90") (pintype "power_in"))
      (node (ref "P3") (pin "P$91") (pinfunction "P$1_P$91") (pintype "power_in"))
      (node (ref "P3") (pin "P$92") (pinfunction "P$1_P$92") (pintype "power_in"))
      (node (ref "P3") (pin "P$93") (pinfunction "P$1_P$93") (pintype "power_in"))
      (node (ref "P3") (pin "P$94") (pinfunction "P$1_P$94") (pintype "power_in"))
      (node (ref "P3") (pin "P$95") (pinfunction "P$1_P$95") (pintype "power_in"))
      (node (ref "P3") (pin "P$96") (pinfunction "P$1_P$96") (pintype "power_in"))
      (node (ref "P3") (pin "P$97") (pinfunction "P$1_P$97") (pintype "power_in"))
      (node (ref "P3") (pin "P$98") (pinfunction "P$1_P$98") (pintype "power_in"))
      (node (ref "P3") (pin "P$99") (pinfunction "P$1_P$99") (pintype "power_in"))
    )
    (net (code "6") (name "/P4") (class "Default")
      (node (ref "JP1") (pin "P$5") (pinfunction "4_P$5") (pintype "bidirectional"))
      (node (ref "P4") (pin "P$1") (pinfunction "P$1_P$1") (pintype "power_in"))
      (node (ref "P4") (pin "P$10") (pinfunction "P$1_P$10") (pintype "power_in"))
      (node (ref "P4") (pin "P$100") (pinfunction "P$1_P$100") (pintype "power_in"))
      (node (ref "P4") (pin "P$101") (pinfunction "P$1_P$101") (pintype "power_in"))
      (node (ref "P4") (pin "P$102") (pinfunction "P$1_P$102") (pintype "power_in"))
      (node (ref "P4") (pin "P$103") (pinfunction "P$1_P$103") (pintype "power_in"))
      (node (ref "P4") (pin "P$104") (pinfunction "P$1_P$104") (pintype "power_in"))
      (node (ref "P4") (pin "P$105") (pinfunction "P$1_P$105") (pintype "power_in"))
      (node (ref "P4") (pin "P$106") (pinfunction "P$1_P$106") (pintype "power_in"))
      (node (ref "P4") (pin "P$107") (pinfunction "P$1_P$107") (pintype "power_in"))
      (node (ref "P4") (pin "P$108") (pinfunction "P$1_P$108") (pintype "power_in"))
      (node (ref "P4") (pin "P$109") (pinfunction "P$1_P$109") (pintype "power_in"))
      (node (ref "P4") (pin "P$11") (pinfunction "P$1_P$11") (pintype "power_in"))
      (node (ref "P4") (pin "P$110") (pinfunction "P$1_P$110") (pintype "power_in"))
      (node (ref "P4") (pin "P$111") (pinfunction "P$1_P$111") (pintype "power_in"))
      (node (ref "P4") (pin "P$112") (pinfunction "P$1_P$112") (pintype "power_in"))
      (node (ref "P4") (pin "P$113") (pinfunction "P$1_P$113") (pintype "power_in"))
      (node (ref "P4") (pin "P$114") (pinfunction "P$1_P$114") (pintype "power_in"))
      (node (ref "P4") (pin "P$115") (pinfunction "P$1_P$115") (pintype "power_in"))
      (node (ref "P4") (pin "P$116") (pinfunction "P$1_P$116") (pintype "power_in"))
      (node (ref "P4") (pin "P$117") (pinfunction "P$1_P$117") (pintype "power_in"))
      (node (ref "P4") (pin "P$118") (pinfunction "P$1_P$118") (pintype "power_in"))
      (node (ref "P4") (pin "P$119") (pinfunction "P$1_P$119") (pintype "power_in"))
      (node (ref "P4") (pin "P$12") (pinfunction "P$1_P$12") (pintype "power_in"))
      (node (ref "P4") (pin "P$120") (pinfunction "P$1_P$120") (pintype "power_in"))
      (node (ref "P4") (pin "P$121") (pinfunction "P$1_P$121") (pintype "power_in"))
      (node (ref "P4") (pin "P$122") (pinfunction "P$1_P$122") (pintype "power_in"))
      (node (ref "P4") (pin "P$123") (pinfunction "P$1_P$123") (pintype "power_in"))
      (node (ref "P4") (pin "P$124") (pinfunction "P$1_P$124") (pintype "power_in"))
      (node (ref "P4") (pin "P$125") (pinfunction "P$1_P$125") (pintype "power_in"))
      (node (ref "P4") (pin "P$126") (pinfunction "P$1_P$126") (pintype "power_in"))
      (node (ref "P4") (pin "P$127") (pinfunction "P$1_P$127") (pintype "power_in"))
      (node (ref "P4") (pin "P$128") (pinfunction "P$1_P$128") (pintype "power_in"))
      (node (ref "P4") (pin "P$129") (pinfunction "P$1_P$129") (pintype "power_in"))
      (node (ref "P4") (pin "P$13") (pinfunction "P$1_P$13") (pintype "power_in"))
      (node (ref "P4") (pin "P$130") (pinfunction "P$1_P$130") (pintype "power_in"))
      (node (ref "P4") (pin "P$131") (pinfunction "P$1_P$131") (pintype "power_in"))
      (node (ref "P4") (pin "P$132") (pinfunction "P$1_P$132") (pintype "power_in"))
      (node (ref "P4") (pin "P$133") (pinfunction "P$1_P$133") (pintype "power_in"))
      (node (ref "P4") (pin "P$134") (pinfunction "P$1_P$134") (pintype "power_in"))
      (node (ref "P4") (pin "P$135") (pinfunction "P$1_P$135") (pintype "power_in"))
      (node (ref "P4") (pin "P$136") (pinfunction "P$1_P$136") (pintype "power_in"))
      (node (ref "P4") (pin "P$137") (pinfunction "P$1_P$137") (pintype "power_in"))
      (node (ref "P4") (pin "P$138") (pinfunction "P$1_P$138") (pintype "power_in"))
      (node (ref "P4") (pin "P$139") (pinfunction "P$1_P$139") (pintype "power_in"))
      (node (ref "P4") (pin "P$14") (pinfunction "P$1_P$14") (pintype "power_in"))
      (node (ref "P4") (pin "P$140") (pinfunction "P$1_P$140") (pintype "power_in"))
      (node (ref "P4") (pin "P$141") (pinfunction "P$1_P$141") (pintype "power_in"))
      (node (ref "P4") (pin "P$142") (pinfunction "P$1_P$142") (pintype "power_in"))
      (node (ref "P4") (pin "P$143") (pinfunction "P$1_P$143") (pintype "power_in"))
      (node (ref "P4") (pin "P$144") (pinfunction "P$1_P$144") (pintype "power_in"))
      (node (ref "P4") (pin "P$145") (pinfunction "P$1_P$145") (pintype "power_in"))
      (node (ref "P4") (pin "P$146") (pinfunction "P$1_P$146") (pintype "power_in"))
      (node (ref "P4") (pin "P$147") (pinfunction "P$1_P$147") (pintype "power_in"))
      (node (ref "P4") (pin "P$148") (pinfunction "P$1_P$148") (pintype "power_in"))
      (node (ref "P4") (pin "P$149") (pinfunction "P$1_P$149") (pintype "power_in"))
      (node (ref "P4") (pin "P$15") (pinfunction "P$1_P$15") (pintype "power_in"))
      (node (ref "P4") (pin "P$150") (pinfunction "P$1_P$150") (pintype "power_in"))
      (node (ref "P4") (pin "P$151") (pinfunction "P$1_P$151") (pintype "power_in"))
      (node (ref "P4") (pin "P$152") (pinfunction "P$1_P$152") (pintype "power_in"))
      (node (ref "P4") (pin "P$153") (pinfunction "P$1_P$153") (pintype "power_in"))
      (node (ref "P4") (pin "P$154") (pinfunction "P$1_P$154") (pintype "power_in"))
      (node (ref "P4") (pin "P$155") (pinfunction "P$1_P$155") (pintype "power_in"))
      (node (ref "P4") (pin "P$156") (pinfunction "P$1_P$156") (pintype "power_in"))
      (node (ref "P4") (pin "P$157") (pinfunction "P$1_P$157") (pintype "power_in"))
      (node (ref "P4") (pin "P$158") (pinfunction "P$1_P$158") (pintype "power_in"))
      (node (ref "P4") (pin "P$159") (pinfunction "P$1_P$159") (pintype "power_in"))
      (node (ref "P4") (pin "P$16") (pinfunction "P$1_P$16") (pintype "power_in"))
      (node (ref "P4") (pin "P$160") (pinfunction "P$1_P$160") (pintype "power_in"))
      (node (ref "P4") (pin "P$161") (pinfunction "P$1_P$161") (pintype "power_in"))
      (node (ref "P4") (pin "P$162") (pinfunction "P$1_P$162") (pintype "power_in"))
      (node (ref "P4") (pin "P$163") (pinfunction "P$1_P$163") (pintype "power_in"))
      (node (ref "P4") (pin "P$164") (pinfunction "P$1_P$164") (pintype "power_in"))
      (node (ref "P4") (pin "P$165") (pinfunction "P$1_P$165") (pintype "power_in"))
      (node (ref "P4") (pin "P$166") (pinfunction "P$1_P$166") (pintype "power_in"))
      (node (ref "P4") (pin "P$167") (pinfunction "P$1_P$167") (pintype "power_in"))
      (node (ref "P4") (pin "P$168") (pinfunction "P$1_P$168") (pintype "power_in"))
      (node (ref "P4") (pin "P$169") (pinfunction "P$1_P$169") (pintype "power_in"))
      (node (ref "P4") (pin "P$17") (pinfunction "P$1_P$17") (pintype "power_in"))
      (node (ref "P4") (pin "P$170") (pinfunction "P$1_P$170") (pintype "power_in"))
      (node (ref "P4") (pin "P$171") (pinfunction "P$1_P$171") (pintype "power_in"))
      (node (ref "P4") (pin "P$172") (pinfunction "P$1_P$172") (pintype "power_in"))
      (node (ref "P4") (pin "P$173") (pinfunction "P$1_P$173") (pintype "power_in"))
      (node (ref "P4") (pin "P$174") (pinfunction "P$1_P$174") (pintype "power_in"))
      (node (ref "P4") (pin "P$175") (pinfunction "P$1_P$175") (pintype "power_in"))
      (node (ref "P4") (pin "P$176") (pinfunction "P$1_P$176") (pintype "power_in"))
      (node (ref "P4") (pin "P$177") (pinfunction "P$1_P$177") (pintype "power_in"))
      (node (ref "P4") (pin "P$178") (pinfunction "P$1_P$178") (pintype "power_in"))
      (node (ref "P4") (pin "P$179") (pinfunction "P$1_P$179") (pintype "power_in"))
      (node (ref "P4") (pin "P$18") (pinfunction "P$1_P$18") (pintype "power_in"))
      (node (ref "P4") (pin "P$180") (pinfunction "P$1_P$180") (pintype "power_in"))
      (node (ref "P4") (pin "P$181") (pinfunction "P$1_P$181") (pintype "power_in"))
      (node (ref "P4") (pin "P$182") (pinfunction "P$1_P$182") (pintype "power_in"))
      (node (ref "P4") (pin "P$183") (pinfunction "P$1_P$183") (pintype "power_in"))
      (node (ref "P4") (pin "P$184") (pinfunction "P$1_P$184") (pintype "power_in"))
      (node (ref "P4") (pin "P$185") (pinfunction "P$1_P$185") (pintype "power_in"))
      (node (ref "P4") (pin "P$186") (pinfunction "P$1_P$186") (pintype "power_in"))
      (node (ref "P4") (pin "P$187") (pinfunction "P$1_P$187") (pintype "power_in"))
      (node (ref "P4") (pin "P$188") (pinfunction "P$1_P$188") (pintype "power_in"))
      (node (ref "P4") (pin "P$189") (pinfunction "P$1_P$189") (pintype "power_in"))
      (node (ref "P4") (pin "P$19") (pinfunction "P$1_P$19") (pintype "power_in"))
      (node (ref "P4") (pin "P$190") (pinfunction "P$1_P$190") (pintype "power_in"))
      (node (ref "P4") (pin "P$191") (pinfunction "P$1_P$191") (pintype "power_in"))
      (node (ref "P4") (pin "P$192") (pinfunction "P$1_P$192") (pintype "power_in"))
      (node (ref "P4") (pin "P$193") (pinfunction "P$1_P$193") (pintype "power_in"))
      (node (ref "P4") (pin "P$194") (pinfunction "P$1_P$194") (pintype "power_in"))
      (node (ref "P4") (pin "P$195") (pinfunction "P$1_P$195") (pintype "power_in"))
      (node (ref "P4") (pin "P$196") (pinfunction "P$1_P$196") (pintype "power_in"))
      (node (ref "P4") (pin "P$197") (pinfunction "P$1_P$197") (pintype "power_in"))
      (node (ref "P4") (pin "P$198") (pinfunction "P$1_P$198") (pintype "power_in"))
      (node (ref "P4") (pin "P$199") (pinfunction "P$1_P$199") (pintype "power_in"))
      (node (ref "P4") (pin "P$2") (pinfunction "P$1_P$2") (pintype "power_in"))
      (node (ref "P4") (pin "P$20") (pinfunction "P$1_P$20") (pintype "power_in"))
      (node (ref "P4") (pin "P$200") (pinfunction "P$1_P$200") (pintype "power_in"))
      (node (ref "P4") (pin "P$201") (pinfunction "P$1_P$201") (pintype "power_in"))
      (node (ref "P4") (pin "P$202") (pinfunction "P$1_P$202") (pintype "power_in"))
      (node (ref "P4") (pin "P$203") (pinfunction "P$1_P$203") (pintype "power_in"))
      (node (ref "P4") (pin "P$204") (pinfunction "P$1_P$204") (pintype "power_in"))
      (node (ref "P4") (pin "P$205") (pinfunction "P$1_P$205") (pintype "power_in"))
      (node (ref "P4") (pin "P$206") (pinfunction "P$1_P$206") (pintype "power_in"))
      (node (ref "P4") (pin "P$207") (pinfunction "P$1_P$207") (pintype "power_in"))
      (node (ref "P4") (pin "P$208") (pinfunction "P$1_P$208") (pintype "power_in"))
      (node (ref "P4") (pin "P$209") (pinfunction "P$1_P$209") (pintype "power_in"))
      (node (ref "P4") (pin "P$21") (pinfunction "P$1_P$21") (pintype "power_in"))
      (node (ref "P4") (pin "P$210") (pinfunction "P$1_P$210") (pintype "power_in"))
      (node (ref "P4") (pin "P$211") (pinfunction "P$1_P$211") (pintype "power_in"))
      (node (ref "P4") (pin "P$212") (pinfunction "P$1_P$212") (pintype "power_in"))
      (node (ref "P4") (pin "P$213") (pinfunction "P$1_P$213") (pintype "power_in"))
      (node (ref "P4") (pin "P$214") (pinfunction "P$1_P$214") (pintype "power_in"))
      (node (ref "P4") (pin "P$215") (pinfunction "P$1_P$215") (pintype "power_in"))
      (node (ref "P4") (pin "P$216") (pinfunction "P$1_P$216") (pintype "power_in"))
      (node (ref "P4") (pin "P$217") (pinfunction "P$1_P$217") (pintype "power_in"))
      (node (ref "P4") (pin "P$218") (pinfunction "P$1_P$218") (pintype "power_in"))
      (node (ref "P4") (pin "P$219") (pinfunction "P$1_P$219") (pintype "power_in"))
      (node (ref "P4") (pin "P$22") (pinfunction "P$1_P$22") (pintype "power_in"))
      (node (ref "P4") (pin "P$220") (pinfunction "P$1_P$220") (pintype "power_in"))
      (node (ref "P4") (pin "P$221") (pinfunction "P$1_P$221") (pintype "power_in"))
      (node (ref "P4") (pin "P$222") (pinfunction "P$1_P$222") (pintype "power_in"))
      (node (ref "P4") (pin "P$223") (pinfunction "P$1_P$223") (pintype "power_in"))
      (node (ref "P4") (pin "P$224") (pinfunction "P$1_P$224") (pintype "power_in"))
      (node (ref "P4") (pin "P$225") (pinfunction "P$1_P$225") (pintype "power_in"))
      (node (ref "P4") (pin "P$226") (pinfunction "P$1_P$226") (pintype "power_in"))
      (node (ref "P4") (pin "P$227") (pinfunction "P$1_P$227") (pintype "power_in"))
      (node (ref "P4") (pin "P$228") (pinfunction "P$1_P$228") (pintype "power_in"))
      (node (ref "P4") (pin "P$229") (pinfunction "P$1_P$229") (pintype "power_in"))
      (node (ref "P4") (pin "P$23") (pinfunction "P$1_P$23") (pintype "power_in"))
      (node (ref "P4") (pin "P$230") (pinfunction "P$1_P$230") (pintype "power_in"))
      (node (ref "P4") (pin "P$231") (pinfunction "P$1_P$231") (pintype "power_in"))
      (node (ref "P4") (pin "P$232") (pinfunction "P$1_P$232") (pintype "power_in"))
      (node (ref "P4") (pin "P$233") (pinfunction "P$1_P$233") (pintype "power_in"))
      (node (ref "P4") (pin "P$234") (pinfunction "P$1_P$234") (pintype "power_in"))
      (node (ref "P4") (pin "P$235") (pinfunction "P$1_P$235") (pintype "power_in"))
      (node (ref "P4") (pin "P$236") (pinfunction "P$1_P$236") (pintype "power_in"))
      (node (ref "P4") (pin "P$237") (pinfunction "P$1_P$237") (pintype "power_in"))
      (node (ref "P4") (pin "P$238") (pinfunction "P$1_P$238") (pintype "power_in"))
      (node (ref "P4") (pin "P$239") (pinfunction "P$1_P$239") (pintype "power_in"))
      (node (ref "P4") (pin "P$24") (pinfunction "P$1_P$24") (pintype "power_in"))
      (node (ref "P4") (pin "P$240") (pinfunction "P$1_P$240") (pintype "power_in"))
      (node (ref "P4") (pin "P$241") (pinfunction "P$1_P$241") (pintype "power_in"))
      (node (ref "P4") (pin "P$242") (pinfunction "P$1_P$242") (pintype "power_in"))
      (node (ref "P4") (pin "P$243") (pinfunction "P$1_P$243") (pintype "power_in"))
      (node (ref "P4") (pin "P$244") (pinfunction "P$1_P$244") (pintype "power_in"))
      (node (ref "P4") (pin "P$245") (pinfunction "P$1_P$245") (pintype "power_in"))
      (node (ref "P4") (pin "P$246") (pinfunction "P$1_P$246") (pintype "power_in"))
      (node (ref "P4") (pin "P$247") (pinfunction "P$1_P$247") (pintype "power_in"))
      (node (ref "P4") (pin "P$248") (pinfunction "P$1_P$248") (pintype "power_in"))
      (node (ref "P4") (pin "P$249") (pinfunction "P$1_P$249") (pintype "power_in"))
      (node (ref "P4") (pin "P$25") (pinfunction "P$1_P$25") (pintype "power_in"))
      (node (ref "P4") (pin "P$250") (pinfunction "P$1_P$250") (pintype "power_in"))
      (node (ref "P4") (pin "P$251") (pinfunction "P$1_P$251") (pintype "power_in"))
      (node (ref "P4") (pin "P$252") (pinfunction "P$1_P$252") (pintype "power_in"))
      (node (ref "P4") (pin "P$253") (pinfunction "P$1_P$253") (pintype "power_in"))
      (node (ref "P4") (pin "P$254") (pinfunction "P$1_P$254") (pintype "power_in"))
      (node (ref "P4") (pin "P$255") (pinfunction "P$1_P$255") (pintype "power_in"))
      (node (ref "P4") (pin "P$256") (pinfunction "P$1_P$256") (pintype "power_in"))
      (node (ref "P4") (pin "P$257") (pinfunction "P$1_P$257") (pintype "power_in"))
      (node (ref "P4") (pin "P$258") (pinfunction "P$1_P$258") (pintype "power_in"))
      (node (ref "P4") (pin "P$259") (pinfunction "P$1_P$259") (pintype "power_in"))
      (node (ref "P4") (pin "P$26") (pinfunction "P$1_P$26") (pintype "power_in"))
      (node (ref "P4") (pin "P$260") (pinfunction "P$1_P$260") (pintype "power_in"))
      (node (ref "P4") (pin "P$261") (pinfunction "P$1_P$261") (pintype "power_in"))
      (node (ref "P4") (pin "P$262") (pinfunction "P$1_P$262") (pintype "power_in"))
      (node (ref "P4") (pin "P$263") (pinfunction "P$1_P$263") (pintype "power_in"))
      (node (ref "P4") (pin "P$264") (pinfunction "P$1_P$264") (pintype "power_in"))
      (node (ref "P4") (pin "P$265") (pinfunction "P$1_P$265") (pintype "power_in"))
      (node (ref "P4") (pin "P$266") (pinfunction "P$1_P$266") (pintype "power_in"))
      (node (ref "P4") (pin "P$267") (pinfunction "P$1_P$267") (pintype "power_in"))
      (node (ref "P4") (pin "P$268") (pinfunction "P$1_P$268") (pintype "power_in"))
      (node (ref "P4") (pin "P$269") (pinfunction "P$1_P$269") (pintype "power_in"))
      (node (ref "P4") (pin "P$27") (pinfunction "P$1_P$27") (pintype "power_in"))
      (node (ref "P4") (pin "P$270") (pinfunction "P$1_P$270") (pintype "power_in"))
      (node (ref "P4") (pin "P$271") (pinfunction "P$1_P$271") (pintype "power_in"))
      (node (ref "P4") (pin "P$272") (pinfunction "P$1_P$272") (pintype "power_in"))
      (node (ref "P4") (pin "P$273") (pinfunction "P$1_P$273") (pintype "power_in"))
      (node (ref "P4") (pin "P$274") (pinfunction "P$1_P$274") (pintype "power_in"))
      (node (ref "P4") (pin "P$275") (pinfunction "P$1_P$275") (pintype "power_in"))
      (node (ref "P4") (pin "P$276") (pinfunction "P$1_P$276") (pintype "power_in"))
      (node (ref "P4") (pin "P$277") (pinfunction "P$1_P$277") (pintype "power_in"))
      (node (ref "P4") (pin "P$278") (pinfunction "P$1_P$278") (pintype "power_in"))
      (node (ref "P4") (pin "P$279") (pinfunction "P$1_P$279") (pintype "power_in"))
      (node (ref "P4") (pin "P$28") (pinfunction "P$1_P$28") (pintype "power_in"))
      (node (ref "P4") (pin "P$280") (pinfunction "P$1_P$280") (pintype "power_in"))
      (node (ref "P4") (pin "P$281") (pinfunction "P$1_P$281") (pintype "power_in"))
      (node (ref "P4") (pin "P$282") (pinfunction "P$1_P$282") (pintype "power_in"))
      (node (ref "P4") (pin "P$283") (pinfunction "P$1_P$283") (pintype "power_in"))
      (node (ref "P4") (pin "P$284") (pinfunction "P$1_P$284") (pintype "power_in"))
      (node (ref "P4") (pin "P$285") (pinfunction "P$1_P$285") (pintype "power_in"))
      (node (ref "P4") (pin "P$286") (pinfunction "P$1_P$286") (pintype "power_in"))
      (node (ref "P4") (pin "P$287") (pinfunction "P$1_P$287") (pintype "power_in"))
      (node (ref "P4") (pin "P$288") (pinfunction "P$1_P$288") (pintype "power_in"))
      (node (ref "P4") (pin "P$29") (pinfunction "P$1_P$29") (pintype "power_in"))
      (node (ref "P4") (pin "P$3") (pinfunction "P$1_P$3") (pintype "power_in"))
      (node (ref "P4") (pin "P$30") (pinfunction "P$1_P$30") (pintype "power_in"))
      (node (ref "P4") (pin "P$31") (pinfunction "P$1_P$31") (pintype "power_in"))
      (node (ref "P4") (pin "P$32") (pinfunction "P$1_P$32") (pintype "power_in"))
      (node (ref "P4") (pin "P$33") (pinfunction "P$1_P$33") (pintype "power_in"))
      (node (ref "P4") (pin "P$34") (pinfunction "P$1_P$34") (pintype "power_in"))
      (node (ref "P4") (pin "P$35") (pinfunction "P$1_P$35") (pintype "power_in"))
      (node (ref "P4") (pin "P$36") (pinfunction "P$1_P$36") (pintype "power_in"))
      (node (ref "P4") (pin "P$37") (pinfunction "P$1_P$37") (pintype "power_in"))
      (node (ref "P4") (pin "P$38") (pinfunction "P$1_P$38") (pintype "power_in"))
      (node (ref "P4") (pin "P$39") (pinfunction "P$1_P$39") (pintype "power_in"))
      (node (ref "P4") (pin "P$4") (pinfunction "P$1_P$4") (pintype "power_in"))
      (node (ref "P4") (pin "P$40") (pinfunction "P$1_P$40") (pintype "power_in"))
      (node (ref "P4") (pin "P$41") (pinfunction "P$1_P$41") (pintype "power_in"))
      (node (ref "P4") (pin "P$42") (pinfunction "P$1_P$42") (pintype "power_in"))
      (node (ref "P4") (pin "P$43") (pinfunction "P$1_P$43") (pintype "power_in"))
      (node (ref "P4") (pin "P$44") (pinfunction "P$1_P$44") (pintype "power_in"))
      (node (ref "P4") (pin "P$45") (pinfunction "P$1_P$45") (pintype "power_in"))
      (node (ref "P4") (pin "P$46") (pinfunction "P$1_P$46") (pintype "power_in"))
      (node (ref "P4") (pin "P$47") (pinfunction "P$1_P$47") (pintype "power_in"))
      (node (ref "P4") (pin "P$48") (pinfunction "P$1_P$48") (pintype "power_in"))
      (node (ref "P4") (pin "P$49") (pinfunction "P$1_P$49") (pintype "power_in"))
      (node (ref "P4") (pin "P$5") (pinfunction "P$1_P$5") (pintype "power_in"))
      (node (ref "P4") (pin "P$50") (pinfunction "P$1_P$50") (pintype "power_in"))
      (node (ref "P4") (pin "P$51") (pinfunction "P$1_P$51") (pintype "power_in"))
      (node (ref "P4") (pin "P$52") (pinfunction "P$1_P$52") (pintype "power_in"))
      (node (ref "P4") (pin "P$53") (pinfunction "P$1_P$53") (pintype "power_in"))
      (node (ref "P4") (pin "P$54") (pinfunction "P$1_P$54") (pintype "power_in"))
      (node (ref "P4") (pin "P$55") (pinfunction "P$1_P$55") (pintype "power_in"))
      (node (ref "P4") (pin "P$56") (pinfunction "P$1_P$56") (pintype "power_in"))
      (node (ref "P4") (pin "P$57") (pinfunction "P$1_P$57") (pintype "power_in"))
      (node (ref "P4") (pin "P$58") (pinfunction "P$1_P$58") (pintype "power_in"))
      (node (ref "P4") (pin "P$59") (pinfunction "P$1_P$59") (pintype "power_in"))
      (node (ref "P4") (pin "P$6") (pinfunction "P$1_P$6") (pintype "power_in"))
      (node (ref "P4") (pin "P$60") (pinfunction "P$1_P$60") (pintype "power_in"))
      (node (ref "P4") (pin "P$61") (pinfunction "P$1_P$61") (pintype "power_in"))
      (node (ref "P4") (pin "P$62") (pinfunction "P$1_P$62") (pintype "power_in"))
      (node (ref "P4") (pin "P$63") (pinfunction "P$1_P$63") (pintype "power_in"))
      (node (ref "P4") (pin "P$64") (pinfunction "P$1_P$64") (pintype "power_in"))
      (node (ref "P4") (pin "P$65") (pinfunction "P$1_P$65") (pintype "power_in"))
      (node (ref "P4") (pin "P$66") (pinfunction "P$1_P$66") (pintype "power_in"))
      (node (ref "P4") (pin "P$67") (pinfunction "P$1_P$67") (pintype "power_in"))
      (node (ref "P4") (pin "P$68") (pinfunction "P$1_P$68") (pintype "power_in"))
      (node (ref "P4") (pin "P$69") (pinfunction "P$1_P$69") (pintype "power_in"))
      (node (ref "P4") (pin "P$7") (pinfunction "P$1_P$7") (pintype "power_in"))
      (node (ref "P4") (pin "P$70") (pinfunction "P$1_P$70") (pintype "power_in"))
      (node (ref "P4") (pin "P$71") (pinfunction "P$1_P$71") (pintype "power_in"))
      (node (ref "P4") (pin "P$72") (pinfunction "P$1_P$72") (pintype "power_in"))
      (node (ref "P4") (pin "P$73") (pinfunction "P$1_P$73") (pintype "power_in"))
      (node (ref "P4") (pin "P$74") (pinfunction "P$1_P$74") (pintype "power_in"))
      (node (ref "P4") (pin "P$75") (pinfunction "P$1_P$75") (pintype "power_in"))
      (node (ref "P4") (pin "P$76") (pinfunction "P$1_P$76") (pintype "power_in"))
      (node (ref "P4") (pin "P$77") (pinfunction "P$1_P$77") (pintype "power_in"))
      (node (ref "P4") (pin "P$78") (pinfunction "P$1_P$78") (pintype "power_in"))
      (node (ref "P4") (pin "P$79") (pinfunction "P$1_P$79") (pintype "power_in"))
      (node (ref "P4") (pin "P$8") (pinfunction "P$1_P$8") (pintype "power_in"))
      (node (ref "P4") (pin "P$80") (pinfunction "P$1_P$80") (pintype "power_in"))
      (node (ref "P4") (pin "P$81") (pinfunction "P$1_P$81") (pintype "power_in"))
      (node (ref "P4") (pin "P$82") (pinfunction "P$1_P$82") (pintype "power_in"))
      (node (ref "P4") (pin "P$83") (pinfunction "P$1_P$83") (pintype "power_in"))
      (node (ref "P4") (pin "P$84") (pinfunction "P$1_P$84") (pintype "power_in"))
      (node (ref "P4") (pin "P$85") (pinfunction "P$1_P$85") (pintype "power_in"))
      (node (ref "P4") (pin "P$86") (pinfunction "P$1_P$86") (pintype "power_in"))
      (node (ref "P4") (pin "P$87") (pinfunction "P$1_P$87") (pintype "power_in"))
      (node (ref "P4") (pin "P$88") (pinfunction "P$1_P$88") (pintype "power_in"))
      (node (ref "P4") (pin "P$89") (pinfunction "P$1_P$89") (pintype "power_in"))
      (node (ref "P4") (pin "P$9") (pinfunction "P$1_P$9") (pintype "power_in"))
      (node (ref "P4") (pin "P$90") (pinfunction "P$1_P$90") (pintype "power_in"))
      (node (ref "P4") (pin "P$91") (pinfunction "P$1_P$91") (pintype "power_in"))
      (node (ref "P4") (pin "P$92") (pinfunction "P$1_P$92") (pintype "power_in"))
      (node (ref "P4") (pin "P$93") (pinfunction "P$1_P$93") (pintype "power_in"))
      (node (ref "P4") (pin "P$94") (pinfunction "P$1_P$94") (pintype "power_in"))
      (node (ref "P4") (pin "P$95") (pinfunction "P$1_P$95") (pintype "power_in"))
      (node (ref "P4") (pin "P$96") (pinfunction "P$1_P$96") (pintype "power_in"))
      (node (ref "P4") (pin "P$97") (pinfunction "P$1_P$97") (pintype "power_in"))
      (node (ref "P4") (pin "P$98") (pinfunction "P$1_P$98") (pintype "power_in"))
      (node (ref "P4") (pin "P$99") (pinfunction "P$1_P$99") (pintype "power_in"))
    )
    (net (code "7") (name "/P5") (class "Default")
      (node (ref "JP1") (pin "P$6") (pinfunction "5_P$6") (pintype "bidirectional"))
      (node (ref "P5") (pin "P$1") (pinfunction "P$1_P$1") (pintype "power_in"))
      (node (ref "P5") (pin "P$10") (pinfunction "P$1_P$10") (pintype "power_in"))
      (node (ref "P5") (pin "P$100") (pinfunction "P$1_P$100") (pintype "power_in"))
      (node (ref "P5") (pin "P$101") (pinfunction "P$1_P$101") (pintype "power_in"))
      (node (ref "P5") (pin "P$102") (pinfunction "P$1_P$102") (pintype "power_in"))
      (node (ref "P5") (pin "P$103") (pinfunction "P$1_P$103") (pintype "power_in"))
      (node (ref "P5") (pin "P$104") (pinfunction "P$1_P$104") (pintype "power_in"))
      (node (ref "P5") (pin "P$105") (pinfunction "P$1_P$105") (pintype "power_in"))
      (node (ref "P5") (pin "P$106") (pinfunction "P$1_P$106") (pintype "power_in"))
      (node (ref "P5") (pin "P$107") (pinfunction "P$1_P$107") (pintype "power_in"))
      (node (ref "P5") (pin "P$108") (pinfunction "P$1_P$108") (pintype "power_in"))
      (node (ref "P5") (pin "P$109") (pinfunction "P$1_P$109") (pintype "power_in"))
      (node (ref "P5") (pin "P$11") (pinfunction "P$1_P$11") (pintype "power_in"))
      (node (ref "P5") (pin "P$110") (pinfunction "P$1_P$110") (pintype "power_in"))
      (node (ref "P5") (pin "P$111") (pinfunction "P$1_P$111") (pintype "power_in"))
      (node (ref "P5") (pin "P$112") (pinfunction "P$1_P$112") (pintype "power_in"))
      (node (ref "P5") (pin "P$113") (pinfunction "P$1_P$113") (pintype "power_in"))
      (node (ref "P5") (pin "P$114") (pinfunction "P$1_P$114") (pintype "power_in"))
      (node (ref "P5") (pin "P$115") (pinfunction "P$1_P$115") (pintype "power_in"))
      (node (ref "P5") (pin "P$116") (pinfunction "P$1_P$116") (pintype "power_in"))
      (node (ref "P5") (pin "P$117") (pinfunction "P$1_P$117") (pintype "power_in"))
      (node (ref "P5") (pin "P$118") (pinfunction "P$1_P$118") (pintype "power_in"))
      (node (ref "P5") (pin "P$119") (pinfunction "P$1_P$119") (pintype "power_in"))
      (node (ref "P5") (pin "P$12") (pinfunction "P$1_P$12") (pintype "power_in"))
      (node (ref "P5") (pin "P$120") (pinfunction "P$1_P$120") (pintype "power_in"))
      (node (ref "P5") (pin "P$121") (pinfunction "P$1_P$121") (pintype "power_in"))
      (node (ref "P5") (pin "P$122") (pinfunction "P$1_P$122") (pintype "power_in"))
      (node (ref "P5") (pin "P$123") (pinfunction "P$1_P$123") (pintype "power_in"))
      (node (ref "P5") (pin "P$124") (pinfunction "P$1_P$124") (pintype "power_in"))
      (node (ref "P5") (pin "P$125") (pinfunction "P$1_P$125") (pintype "power_in"))
      (node (ref "P5") (pin "P$126") (pinfunction "P$1_P$126") (pintype "power_in"))
      (node (ref "P5") (pin "P$127") (pinfunction "P$1_P$127") (pintype "power_in"))
      (node (ref "P5") (pin "P$128") (pinfunction "P$1_P$128") (pintype "power_in"))
      (node (ref "P5") (pin "P$129") (pinfunction "P$1_P$129") (pintype "power_in"))
      (node (ref "P5") (pin "P$13") (pinfunction "P$1_P$13") (pintype "power_in"))
      (node (ref "P5") (pin "P$130") (pinfunction "P$1_P$130") (pintype "power_in"))
      (node (ref "P5") (pin "P$131") (pinfunction "P$1_P$131") (pintype "power_in"))
      (node (ref "P5") (pin "P$132") (pinfunction "P$1_P$132") (pintype "power_in"))
      (node (ref "P5") (pin "P$133") (pinfunction "P$1_P$133") (pintype "power_in"))
      (node (ref "P5") (pin "P$134") (pinfunction "P$1_P$134") (pintype "power_in"))
      (node (ref "P5") (pin "P$135") (pinfunction "P$1_P$135") (pintype "power_in"))
      (node (ref "P5") (pin "P$136") (pinfunction "P$1_P$136") (pintype "power_in"))
      (node (ref "P5") (pin "P$137") (pinfunction "P$1_P$137") (pintype "power_in"))
      (node (ref "P5") (pin "P$138") (pinfunction "P$1_P$138") (pintype "power_in"))
      (node (ref "P5") (pin "P$139") (pinfunction "P$1_P$139") (pintype "power_in"))
      (node (ref "P5") (pin "P$14") (pinfunction "P$1_P$14") (pintype "power_in"))
      (node (ref "P5") (pin "P$140") (pinfunction "P$1_P$140") (pintype "power_in"))
      (node (ref "P5") (pin "P$141") (pinfunction "P$1_P$141") (pintype "power_in"))
      (node (ref "P5") (pin "P$142") (pinfunction "P$1_P$142") (pintype "power_in"))
      (node (ref "P5") (pin "P$143") (pinfunction "P$1_P$143") (pintype "power_in"))
      (node (ref "P5") (pin "P$144") (pinfunction "P$1_P$144") (pintype "power_in"))
      (node (ref "P5") (pin "P$145") (pinfunction "P$1_P$145") (pintype "power_in"))
      (node (ref "P5") (pin "P$146") (pinfunction "P$1_P$146") (pintype "power_in"))
      (node (ref "P5") (pin "P$147") (pinfunction "P$1_P$147") (pintype "power_in"))
      (node (ref "P5") (pin "P$148") (pinfunction "P$1_P$148") (pintype "power_in"))
      (node (ref "P5") (pin "P$149") (pinfunction "P$1_P$149") (pintype "power_in"))
      (node (ref "P5") (pin "P$15") (pinfunction "P$1_P$15") (pintype "power_in"))
      (node (ref "P5") (pin "P$150") (pinfunction "P$1_P$150") (pintype "power_in"))
      (node (ref "P5") (pin "P$151") (pinfunction "P$1_P$151") (pintype "power_in"))
      (node (ref "P5") (pin "P$152") (pinfunction "P$1_P$152") (pintype "power_in"))
      (node (ref "P5") (pin "P$153") (pinfunction "P$1_P$153") (pintype "power_in"))
      (node (ref "P5") (pin "P$154") (pinfunction "P$1_P$154") (pintype "power_in"))
      (node (ref "P5") (pin "P$155") (pinfunction "P$1_P$155") (pintype "power_in"))
      (node (ref "P5") (pin "P$156") (pinfunction "P$1_P$156") (pintype "power_in"))
      (node (ref "P5") (pin "P$157") (pinfunction "P$1_P$157") (pintype "power_in"))
      (node (ref "P5") (pin "P$158") (pinfunction "P$1_P$158") (pintype "power_in"))
      (node (ref "P5") (pin "P$159") (pinfunction "P$1_P$159") (pintype "power_in"))
      (node (ref "P5") (pin "P$16") (pinfunction "P$1_P$16") (pintype "power_in"))
      (node (ref "P5") (pin "P$160") (pinfunction "P$1_P$160") (pintype "power_in"))
      (node (ref "P5") (pin "P$161") (pinfunction "P$1_P$161") (pintype "power_in"))
      (node (ref "P5") (pin "P$162") (pinfunction "P$1_P$162") (pintype "power_in"))
      (node (ref "P5") (pin "P$163") (pinfunction "P$1_P$163") (pintype "power_in"))
      (node (ref "P5") (pin "P$164") (pinfunction "P$1_P$164") (pintype "power_in"))
      (node (ref "P5") (pin "P$165") (pinfunction "P$1_P$165") (pintype "power_in"))
      (node (ref "P5") (pin "P$166") (pinfunction "P$1_P$166") (pintype "power_in"))
      (node (ref "P5") (pin "P$167") (pinfunction "P$1_P$167") (pintype "power_in"))
      (node (ref "P5") (pin "P$168") (pinfunction "P$1_P$168") (pintype "power_in"))
      (node (ref "P5") (pin "P$169") (pinfunction "P$1_P$169") (pintype "power_in"))
      (node (ref "P5") (pin "P$17") (pinfunction "P$1_P$17") (pintype "power_in"))
      (node (ref "P5") (pin "P$170") (pinfunction "P$1_P$170") (pintype "power_in"))
      (node (ref "P5") (pin "P$171") (pinfunction "P$1_P$171") (pintype "power_in"))
      (node (ref "P5") (pin "P$172") (pinfunction "P$1_P$172") (pintype "power_in"))
      (node (ref "P5") (pin "P$173") (pinfunction "P$1_P$173") (pintype "power_in"))
      (node (ref "P5") (pin "P$174") (pinfunction "P$1_P$174") (pintype "power_in"))
      (node (ref "P5") (pin "P$175") (pinfunction "P$1_P$175") (pintype "power_in"))
      (node (ref "P5") (pin "P$176") (pinfunction "P$1_P$176") (pintype "power_in"))
      (node (ref "P5") (pin "P$177") (pinfunction "P$1_P$177") (pintype "power_in"))
      (node (ref "P5") (pin "P$178") (pinfunction "P$1_P$178") (pintype "power_in"))
      (node (ref "P5") (pin "P$179") (pinfunction "P$1_P$179") (pintype "power_in"))
      (node (ref "P5") (pin "P$18") (pinfunction "P$1_P$18") (pintype "power_in"))
      (node (ref "P5") (pin "P$180") (pinfunction "P$1_P$180") (pintype "power_in"))
      (node (ref "P5") (pin "P$181") (pinfunction "P$1_P$181") (pintype "power_in"))
      (node (ref "P5") (pin "P$182") (pinfunction "P$1_P$182") (pintype "power_in"))
      (node (ref "P5") (pin "P$183") (pinfunction "P$1_P$183") (pintype "power_in"))
      (node (ref "P5") (pin "P$184") (pinfunction "P$1_P$184") (pintype "power_in"))
      (node (ref "P5") (pin "P$185") (pinfunction "P$1_P$185") (pintype "power_in"))
      (node (ref "P5") (pin "P$186") (pinfunction "P$1_P$186") (pintype "power_in"))
      (node (ref "P5") (pin "P$187") (pinfunction "P$1_P$187") (pintype "power_in"))
      (node (ref "P5") (pin "P$188") (pinfunction "P$1_P$188") (pintype "power_in"))
      (node (ref "P5") (pin "P$189") (pinfunction "P$1_P$189") (pintype "power_in"))
      (node (ref "P5") (pin "P$19") (pinfunction "P$1_P$19") (pintype "power_in"))
      (node (ref "P5") (pin "P$190") (pinfunction "P$1_P$190") (pintype "power_in"))
      (node (ref "P5") (pin "P$191") (pinfunction "P$1_P$191") (pintype "power_in"))
      (node (ref "P5") (pin "P$192") (pinfunction "P$1_P$192") (pintype "power_in"))
      (node (ref "P5") (pin "P$193") (pinfunction "P$1_P$193") (pintype "power_in"))
      (node (ref "P5") (pin "P$194") (pinfunction "P$1_P$194") (pintype "power_in"))
      (node (ref "P5") (pin "P$195") (pinfunction "P$1_P$195") (pintype "power_in"))
      (node (ref "P5") (pin "P$196") (pinfunction "P$1_P$196") (pintype "power_in"))
      (node (ref "P5") (pin "P$197") (pinfunction "P$1_P$197") (pintype "power_in"))
      (node (ref "P5") (pin "P$198") (pinfunction "P$1_P$198") (pintype "power_in"))
      (node (ref "P5") (pin "P$199") (pinfunction "P$1_P$199") (pintype "power_in"))
      (node (ref "P5") (pin "P$2") (pinfunction "P$1_P$2") (pintype "power_in"))
      (node (ref "P5") (pin "P$20") (pinfunction "P$1_P$20") (pintype "power_in"))
      (node (ref "P5") (pin "P$200") (pinfunction "P$1_P$200") (pintype "power_in"))
      (node (ref "P5") (pin "P$201") (pinfunction "P$1_P$201") (pintype "power_in"))
      (node (ref "P5") (pin "P$202") (pinfunction "P$1_P$202") (pintype "power_in"))
      (node (ref "P5") (pin "P$203") (pinfunction "P$1_P$203") (pintype "power_in"))
      (node (ref "P5") (pin "P$204") (pinfunction "P$1_P$204") (pintype "power_in"))
      (node (ref "P5") (pin "P$205") (pinfunction "P$1_P$205") (pintype "power_in"))
      (node (ref "P5") (pin "P$206") (pinfunction "P$1_P$206") (pintype "power_in"))
      (node (ref "P5") (pin "P$207") (pinfunction "P$1_P$207") (pintype "power_in"))
      (node (ref "P5") (pin "P$208") (pinfunction "P$1_P$208") (pintype "power_in"))
      (node (ref "P5") (pin "P$209") (pinfunction "P$1_P$209") (pintype "power_in"))
      (node (ref "P5") (pin "P$21") (pinfunction "P$1_P$21") (pintype "power_in"))
      (node (ref "P5") (pin "P$210") (pinfunction "P$1_P$210") (pintype "power_in"))
      (node (ref "P5") (pin "P$211") (pinfunction "P$1_P$211") (pintype "power_in"))
      (node (ref "P5") (pin "P$212") (pinfunction "P$1_P$212") (pintype "power_in"))
      (node (ref "P5") (pin "P$213") (pinfunction "P$1_P$213") (pintype "power_in"))
      (node (ref "P5") (pin "P$214") (pinfunction "P$1_P$214") (pintype "power_in"))
      (node (ref "P5") (pin "P$215") (pinfunction "P$1_P$215") (pintype "power_in"))
      (node (ref "P5") (pin "P$216") (pinfunction "P$1_P$216") (pintype "power_in"))
      (node (ref "P5") (pin "P$217") (pinfunction "P$1_P$217") (pintype "power_in"))
      (node (ref "P5") (pin "P$218") (pinfunction "P$1_P$218") (pintype "power_in"))
      (node (ref "P5") (pin "P$219") (pinfunction "P$1_P$219") (pintype "power_in"))
      (node (ref "P5") (pin "P$22") (pinfunction "P$1_P$22") (pintype "power_in"))
      (node (ref "P5") (pin "P$220") (pinfunction "P$1_P$220") (pintype "power_in"))
      (node (ref "P5") (pin "P$221") (pinfunction "P$1_P$221") (pintype "power_in"))
      (node (ref "P5") (pin "P$222") (pinfunction "P$1_P$222") (pintype "power_in"))
      (node (ref "P5") (pin "P$223") (pinfunction "P$1_P$223") (pintype "power_in"))
      (node (ref "P5") (pin "P$224") (pinfunction "P$1_P$224") (pintype "power_in"))
      (node (ref "P5") (pin "P$225") (pinfunction "P$1_P$225") (pintype "power_in"))
      (node (ref "P5") (pin "P$226") (pinfunction "P$1_P$226") (pintype "power_in"))
      (node (ref "P5") (pin "P$227") (pinfunction "P$1_P$227") (pintype "power_in"))
      (node (ref "P5") (pin "P$228") (pinfunction "P$1_P$228") (pintype "power_in"))
      (node (ref "P5") (pin "P$229") (pinfunction "P$1_P$229") (pintype "power_in"))
      (node (ref "P5") (pin "P$23") (pinfunction "P$1_P$23") (pintype "power_in"))
      (node (ref "P5") (pin "P$230") (pinfunction "P$1_P$230") (pintype "power_in"))
      (node (ref "P5") (pin "P$231") (pinfunction "P$1_P$231") (pintype "power_in"))
      (node (ref "P5") (pin "P$232") (pinfunction "P$1_P$232") (pintype "power_in"))
      (node (ref "P5") (pin "P$233") (pinfunction "P$1_P$233") (pintype "power_in"))
      (node (ref "P5") (pin "P$234") (pinfunction "P$1_P$234") (pintype "power_in"))
      (node (ref "P5") (pin "P$235") (pinfunction "P$1_P$235") (pintype "power_in"))
      (node (ref "P5") (pin "P$236") (pinfunction "P$1_P$236") (pintype "power_in"))
      (node (ref "P5") (pin "P$237") (pinfunction "P$1_P$237") (pintype "power_in"))
      (node (ref "P5") (pin "P$238") (pinfunction "P$1_P$238") (pintype "power_in"))
      (node (ref "P5") (pin "P$239") (pinfunction "P$1_P$239") (pintype "power_in"))
      (node (ref "P5") (pin "P$24") (pinfunction "P$1_P$24") (pintype "power_in"))
      (node (ref "P5") (pin "P$240") (pinfunction "P$1_P$240") (pintype "power_in"))
      (node (ref "P5") (pin "P$241") (pinfunction "P$1_P$241") (pintype "power_in"))
      (node (ref "P5") (pin "P$242") (pinfunction "P$1_P$242") (pintype "power_in"))
      (node (ref "P5") (pin "P$243") (pinfunction "P$1_P$243") (pintype "power_in"))
      (node (ref "P5") (pin "P$244") (pinfunction "P$1_P$244") (pintype "power_in"))
      (node (ref "P5") (pin "P$245") (pinfunction "P$1_P$245") (pintype "power_in"))
      (node (ref "P5") (pin "P$246") (pinfunction "P$1_P$246") (pintype "power_in"))
      (node (ref "P5") (pin "P$247") (pinfunction "P$1_P$247") (pintype "power_in"))
      (node (ref "P5") (pin "P$248") (pinfunction "P$1_P$248") (pintype "power_in"))
      (node (ref "P5") (pin "P$249") (pinfunction "P$1_P$249") (pintype "power_in"))
      (node (ref "P5") (pin "P$25") (pinfunction "P$1_P$25") (pintype "power_in"))
      (node (ref "P5") (pin "P$250") (pinfunction "P$1_P$250") (pintype "power_in"))
      (node (ref "P5") (pin "P$251") (pinfunction "P$1_P$251") (pintype "power_in"))
      (node (ref "P5") (pin "P$252") (pinfunction "P$1_P$252") (pintype "power_in"))
      (node (ref "P5") (pin "P$253") (pinfunction "P$1_P$253") (pintype "power_in"))
      (node (ref "P5") (pin "P$254") (pinfunction "P$1_P$254") (pintype "power_in"))
      (node (ref "P5") (pin "P$255") (pinfunction "P$1_P$255") (pintype "power_in"))
      (node (ref "P5") (pin "P$256") (pinfunction "P$1_P$256") (pintype "power_in"))
      (node (ref "P5") (pin "P$257") (pinfunction "P$1_P$257") (pintype "power_in"))
      (node (ref "P5") (pin "P$258") (pinfunction "P$1_P$258") (pintype "power_in"))
      (node (ref "P5") (pin "P$259") (pinfunction "P$1_P$259") (pintype "power_in"))
      (node (ref "P5") (pin "P$26") (pinfunction "P$1_P$26") (pintype "power_in"))
      (node (ref "P5") (pin "P$260") (pinfunction "P$1_P$260") (pintype "power_in"))
      (node (ref "P5") (pin "P$261") (pinfunction "P$1_P$261") (pintype "power_in"))
      (node (ref "P5") (pin "P$262") (pinfunction "P$1_P$262") (pintype "power_in"))
      (node (ref "P5") (pin "P$263") (pinfunction "P$1_P$263") (pintype "power_in"))
      (node (ref "P5") (pin "P$264") (pinfunction "P$1_P$264") (pintype "power_in"))
      (node (ref "P5") (pin "P$265") (pinfunction "P$1_P$265") (pintype "power_in"))
      (node (ref "P5") (pin "P$266") (pinfunction "P$1_P$266") (pintype "power_in"))
      (node (ref "P5") (pin "P$267") (pinfunction "P$1_P$267") (pintype "power_in"))
      (node (ref "P5") (pin "P$268") (pinfunction "P$1_P$268") (pintype "power_in"))
      (node (ref "P5") (pin "P$269") (pinfunction "P$1_P$269") (pintype "power_in"))
      (node (ref "P5") (pin "P$27") (pinfunction "P$1_P$27") (pintype "power_in"))
      (node (ref "P5") (pin "P$270") (pinfunction "P$1_P$270") (pintype "power_in"))
      (node (ref "P5") (pin "P$271") (pinfunction "P$1_P$271") (pintype "power_in"))
      (node (ref "P5") (pin "P$272") (pinfunction "P$1_P$272") (pintype "power_in"))
      (node (ref "P5") (pin "P$273") (pinfunction "P$1_P$273") (pintype "power_in"))
      (node (ref "P5") (pin "P$274") (pinfunction "P$1_P$274") (pintype "power_in"))
      (node (ref "P5") (pin "P$275") (pinfunction "P$1_P$275") (pintype "power_in"))
      (node (ref "P5") (pin "P$276") (pinfunction "P$1_P$276") (pintype "power_in"))
      (node (ref "P5") (pin "P$277") (pinfunction "P$1_P$277") (pintype "power_in"))
      (node (ref "P5") (pin "P$278") (pinfunction "P$1_P$278") (pintype "power_in"))
      (node (ref "P5") (pin "P$279") (pinfunction "P$1_P$279") (pintype "power_in"))
      (node (ref "P5") (pin "P$28") (pinfunction "P$1_P$28") (pintype "power_in"))
      (node (ref "P5") (pin "P$280") (pinfunction "P$1_P$280") (pintype "power_in"))
      (node (ref "P5") (pin "P$281") (pinfunction "P$1_P$281") (pintype "power_in"))
      (node (ref "P5") (pin "P$282") (pinfunction "P$1_P$282") (pintype "power_in"))
      (node (ref "P5") (pin "P$283") (pinfunction "P$1_P$283") (pintype "power_in"))
      (node (ref "P5") (pin "P$284") (pinfunction "P$1_P$284") (pintype "power_in"))
      (node (ref "P5") (pin "P$285") (pinfunction "P$1_P$285") (pintype "power_in"))
      (node (ref "P5") (pin "P$286") (pinfunction "P$1_P$286") (pintype "power_in"))
      (node (ref "P5") (pin "P$287") (pinfunction "P$1_P$287") (pintype "power_in"))
      (node (ref "P5") (pin "P$288") (pinfunction "P$1_P$288") (pintype "power_in"))
      (node (ref "P5") (pin "P$29") (pinfunction "P$1_P$29") (pintype "power_in"))
      (node (ref "P5") (pin "P$3") (pinfunction "P$1_P$3") (pintype "power_in"))
      (node (ref "P5") (pin "P$30") (pinfunction "P$1_P$30") (pintype "power_in"))
      (node (ref "P5") (pin "P$31") (pinfunction "P$1_P$31") (pintype "power_in"))
      (node (ref "P5") (pin "P$32") (pinfunction "P$1_P$32") (pintype "power_in"))
      (node (ref "P5") (pin "P$33") (pinfunction "P$1_P$33") (pintype "power_in"))
      (node (ref "P5") (pin "P$34") (pinfunction "P$1_P$34") (pintype "power_in"))
      (node (ref "P5") (pin "P$35") (pinfunction "P$1_P$35") (pintype "power_in"))
      (node (ref "P5") (pin "P$36") (pinfunction "P$1_P$36") (pintype "power_in"))
      (node (ref "P5") (pin "P$37") (pinfunction "P$1_P$37") (pintype "power_in"))
      (node (ref "P5") (pin "P$38") (pinfunction "P$1_P$38") (pintype "power_in"))
      (node (ref "P5") (pin "P$39") (pinfunction "P$1_P$39") (pintype "power_in"))
      (node (ref "P5") (pin "P$4") (pinfunction "P$1_P$4") (pintype "power_in"))
      (node (ref "P5") (pin "P$40") (pinfunction "P$1_P$40") (pintype "power_in"))
      (node (ref "P5") (pin "P$41") (pinfunction "P$1_P$41") (pintype "power_in"))
      (node (ref "P5") (pin "P$42") (pinfunction "P$1_P$42") (pintype "power_in"))
      (node (ref "P5") (pin "P$43") (pinfunction "P$1_P$43") (pintype "power_in"))
      (node (ref "P5") (pin "P$44") (pinfunction "P$1_P$44") (pintype "power_in"))
      (node (ref "P5") (pin "P$45") (pinfunction "P$1_P$45") (pintype "power_in"))
      (node (ref "P5") (pin "P$46") (pinfunction "P$1_P$46") (pintype "power_in"))
      (node (ref "P5") (pin "P$47") (pinfunction "P$1_P$47") (pintype "power_in"))
      (node (ref "P5") (pin "P$48") (pinfunction "P$1_P$48") (pintype "power_in"))
      (node (ref "P5") (pin "P$49") (pinfunction "P$1_P$49") (pintype "power_in"))
      (node (ref "P5") (pin "P$5") (pinfunction "P$1_P$5") (pintype "power_in"))
      (node (ref "P5") (pin "P$50") (pinfunction "P$1_P$50") (pintype "power_in"))
      (node (ref "P5") (pin "P$51") (pinfunction "P$1_P$51") (pintype "power_in"))
      (node (ref "P5") (pin "P$52") (pinfunction "P$1_P$52") (pintype "power_in"))
      (node (ref "P5") (pin "P$53") (pinfunction "P$1_P$53") (pintype "power_in"))
      (node (ref "P5") (pin "P$54") (pinfunction "P$1_P$54") (pintype "power_in"))
      (node (ref "P5") (pin "P$55") (pinfunction "P$1_P$55") (pintype "power_in"))
      (node (ref "P5") (pin "P$56") (pinfunction "P$1_P$56") (pintype "power_in"))
      (node (ref "P5") (pin "P$57") (pinfunction "P$1_P$57") (pintype "power_in"))
      (node (ref "P5") (pin "P$58") (pinfunction "P$1_P$58") (pintype "power_in"))
      (node (ref "P5") (pin "P$59") (pinfunction "P$1_P$59") (pintype "power_in"))
      (node (ref "P5") (pin "P$6") (pinfunction "P$1_P$6") (pintype "power_in"))
      (node (ref "P5") (pin "P$60") (pinfunction "P$1_P$60") (pintype "power_in"))
      (node (ref "P5") (pin "P$61") (pinfunction "P$1_P$61") (pintype "power_in"))
      (node (ref "P5") (pin "P$62") (pinfunction "P$1_P$62") (pintype "power_in"))
      (node (ref "P5") (pin "P$63") (pinfunction "P$1_P$63") (pintype "power_in"))
      (node (ref "P5") (pin "P$64") (pinfunction "P$1_P$64") (pintype "power_in"))
      (node (ref "P5") (pin "P$65") (pinfunction "P$1_P$65") (pintype "power_in"))
      (node (ref "P5") (pin "P$66") (pinfunction "P$1_P$66") (pintype "power_in"))
      (node (ref "P5") (pin "P$67") (pinfunction "P$1_P$67") (pintype "power_in"))
      (node (ref "P5") (pin "P$68") (pinfunction "P$1_P$68") (pintype "power_in"))
      (node (ref "P5") (pin "P$69") (pinfunction "P$1_P$69") (pintype "power_in"))
      (node (ref "P5") (pin "P$7") (pinfunction "P$1_P$7") (pintype "power_in"))
      (node (ref "P5") (pin "P$70") (pinfunction "P$1_P$70") (pintype "power_in"))
      (node (ref "P5") (pin "P$71") (pinfunction "P$1_P$71") (pintype "power_in"))
      (node (ref "P5") (pin "P$72") (pinfunction "P$1_P$72") (pintype "power_in"))
      (node (ref "P5") (pin "P$73") (pinfunction "P$1_P$73") (pintype "power_in"))
      (node (ref "P5") (pin "P$74") (pinfunction "P$1_P$74") (pintype "power_in"))
      (node (ref "P5") (pin "P$75") (pinfunction "P$1_P$75") (pintype "power_in"))
      (node (ref "P5") (pin "P$76") (pinfunction "P$1_P$76") (pintype "power_in"))
      (node (ref "P5") (pin "P$77") (pinfunction "P$1_P$77") (pintype "power_in"))
      (node (ref "P5") (pin "P$78") (pinfunction "P$1_P$78") (pintype "power_in"))
      (node (ref "P5") (pin "P$79") (pinfunction "P$1_P$79") (pintype "power_in"))
      (node (ref "P5") (pin "P$8") (pinfunction "P$1_P$8") (pintype "power_in"))
      (node (ref "P5") (pin "P$80") (pinfunction "P$1_P$80") (pintype "power_in"))
      (node (ref "P5") (pin "P$81") (pinfunction "P$1_P$81") (pintype "power_in"))
      (node (ref "P5") (pin "P$82") (pinfunction "P$1_P$82") (pintype "power_in"))
      (node (ref "P5") (pin "P$83") (pinfunction "P$1_P$83") (pintype "power_in"))
      (node (ref "P5") (pin "P$84") (pinfunction "P$1_P$84") (pintype "power_in"))
      (node (ref "P5") (pin "P$85") (pinfunction "P$1_P$85") (pintype "power_in"))
      (node (ref "P5") (pin "P$86") (pinfunction "P$1_P$86") (pintype "power_in"))
      (node (ref "P5") (pin "P$87") (pinfunction "P$1_P$87") (pintype "power_in"))
      (node (ref "P5") (pin "P$88") (pinfunction "P$1_P$88") (pintype "power_in"))
      (node (ref "P5") (pin "P$89") (pinfunction "P$1_P$89") (pintype "power_in"))
      (node (ref "P5") (pin "P$9") (pinfunction "P$1_P$9") (pintype "power_in"))
      (node (ref "P5") (pin "P$90") (pinfunction "P$1_P$90") (pintype "power_in"))
      (node (ref "P5") (pin "P$91") (pinfunction "P$1_P$91") (pintype "power_in"))
      (node (ref "P5") (pin "P$92") (pinfunction "P$1_P$92") (pintype "power_in"))
      (node (ref "P5") (pin "P$93") (pinfunction "P$1_P$93") (pintype "power_in"))
      (node (ref "P5") (pin "P$94") (pinfunction "P$1_P$94") (pintype "power_in"))
      (node (ref "P5") (pin "P$95") (pinfunction "P$1_P$95") (pintype "power_in"))
      (node (ref "P5") (pin "P$96") (pinfunction "P$1_P$96") (pintype "power_in"))
      (node (ref "P5") (pin "P$97") (pinfunction "P$1_P$97") (pintype "power_in"))
      (node (ref "P5") (pin "P$98") (pinfunction "P$1_P$98") (pintype "power_in"))
      (node (ref "P5") (pin "P$99") (pinfunction "P$1_P$99") (pintype "power_in"))
    )
    (net (code "8") (name "/P6") (class "Default")
      (node (ref "JP1") (pin "P$7") (pinfunction "6_P$7") (pintype "bidirectional"))
      (node (ref "P6") (pin "P$1") (pinfunction "P$1_P$1") (pintype "power_in"))
      (node (ref "P6") (pin "P$10") (pinfunction "P$1_P$10") (pintype "power_in"))
      (node (ref "P6") (pin "P$100") (pinfunction "P$1_P$100") (pintype "power_in"))
      (node (ref "P6") (pin "P$101") (pinfunction "P$1_P$101") (pintype "power_in"))
      (node (ref "P6") (pin "P$102") (pinfunction "P$1_P$102") (pintype "power_in"))
      (node (ref "P6") (pin "P$103") (pinfunction "P$1_P$103") (pintype "power_in"))
      (node (ref "P6") (pin "P$104") (pinfunction "P$1_P$104") (pintype "power_in"))
      (node (ref "P6") (pin "P$105") (pinfunction "P$1_P$105") (pintype "power_in"))
      (node (ref "P6") (pin "P$106") (pinfunction "P$1_P$106") (pintype "power_in"))
      (node (ref "P6") (pin "P$107") (pinfunction "P$1_P$107") (pintype "power_in"))
      (node (ref "P6") (pin "P$108") (pinfunction "P$1_P$108") (pintype "power_in"))
      (node (ref "P6") (pin "P$109") (pinfunction "P$1_P$109") (pintype "power_in"))
      (node (ref "P6") (pin "P$11") (pinfunction "P$1_P$11") (pintype "power_in"))
      (node (ref "P6") (pin "P$110") (pinfunction "P$1_P$110") (pintype "power_in"))
      (node (ref "P6") (pin "P$111") (pinfunction "P$1_P$111") (pintype "power_in"))
      (node (ref "P6") (pin "P$112") (pinfunction "P$1_P$112") (pintype "power_in"))
      (node (ref "P6") (pin "P$113") (pinfunction "P$1_P$113") (pintype "power_in"))
      (node (ref "P6") (pin "P$114") (pinfunction "P$1_P$114") (pintype "power_in"))
      (node (ref "P6") (pin "P$115") (pinfunction "P$1_P$115") (pintype "power_in"))
      (node (ref "P6") (pin "P$116") (pinfunction "P$1_P$116") (pintype "power_in"))
      (node (ref "P6") (pin "P$117") (pinfunction "P$1_P$117") (pintype "power_in"))
      (node (ref "P6") (pin "P$118") (pinfunction "P$1_P$118") (pintype "power_in"))
      (node (ref "P6") (pin "P$119") (pinfunction "P$1_P$119") (pintype "power_in"))
      (node (ref "P6") (pin "P$12") (pinfunction "P$1_P$12") (pintype "power_in"))
      (node (ref "P6") (pin "P$120") (pinfunction "P$1_P$120") (pintype "power_in"))
      (node (ref "P6") (pin "P$121") (pinfunction "P$1_P$121") (pintype "power_in"))
      (node (ref "P6") (pin "P$122") (pinfunction "P$1_P$122") (pintype "power_in"))
      (node (ref "P6") (pin "P$123") (pinfunction "P$1_P$123") (pintype "power_in"))
      (node (ref "P6") (pin "P$124") (pinfunction "P$1_P$124") (pintype "power_in"))
      (node (ref "P6") (pin "P$125") (pinfunction "P$1_P$125") (pintype "power_in"))
      (node (ref "P6") (pin "P$126") (pinfunction "P$1_P$126") (pintype "power_in"))
      (node (ref "P6") (pin "P$127") (pinfunction "P$1_P$127") (pintype "power_in"))
      (node (ref "P6") (pin "P$128") (pinfunction "P$1_P$128") (pintype "power_in"))
      (node (ref "P6") (pin "P$129") (pinfunction "P$1_P$129") (pintype "power_in"))
      (node (ref "P6") (pin "P$13") (pinfunction "P$1_P$13") (pintype "power_in"))
      (node (ref "P6") (pin "P$130") (pinfunction "P$1_P$130") (pintype "power_in"))
      (node (ref "P6") (pin "P$131") (pinfunction "P$1_P$131") (pintype "power_in"))
      (node (ref "P6") (pin "P$132") (pinfunction "P$1_P$132") (pintype "power_in"))
      (node (ref "P6") (pin "P$133") (pinfunction "P$1_P$133") (pintype "power_in"))
      (node (ref "P6") (pin "P$134") (pinfunction "P$1_P$134") (pintype "power_in"))
      (node (ref "P6") (pin "P$135") (pinfunction "P$1_P$135") (pintype "power_in"))
      (node (ref "P6") (pin "P$136") (pinfunction "P$1_P$136") (pintype "power_in"))
      (node (ref "P6") (pin "P$137") (pinfunction "P$1_P$137") (pintype "power_in"))
      (node (ref "P6") (pin "P$138") (pinfunction "P$1_P$138") (pintype "power_in"))
      (node (ref "P6") (pin "P$139") (pinfunction "P$1_P$139") (pintype "power_in"))
      (node (ref "P6") (pin "P$14") (pinfunction "P$1_P$14") (pintype "power_in"))
      (node (ref "P6") (pin "P$140") (pinfunction "P$1_P$140") (pintype "power_in"))
      (node (ref "P6") (pin "P$141") (pinfunction "P$1_P$141") (pintype "power_in"))
      (node (ref "P6") (pin "P$142") (pinfunction "P$1_P$142") (pintype "power_in"))
      (node (ref "P6") (pin "P$143") (pinfunction "P$1_P$143") (pintype "power_in"))
      (node (ref "P6") (pin "P$144") (pinfunction "P$1_P$144") (pintype "power_in"))
      (node (ref "P6") (pin "P$145") (pinfunction "P$1_P$145") (pintype "power_in"))
      (node (ref "P6") (pin "P$146") (pinfunction "P$1_P$146") (pintype "power_in"))
      (node (ref "P6") (pin "P$147") (pinfunction "P$1_P$147") (pintype "power_in"))
      (node (ref "P6") (pin "P$148") (pinfunction "P$1_P$148") (pintype "power_in"))
      (node (ref "P6") (pin "P$149") (pinfunction "P$1_P$149") (pintype "power_in"))
      (node (ref "P6") (pin "P$15") (pinfunction "P$1_P$15") (pintype "power_in"))
      (node (ref "P6") (pin "P$150") (pinfunction "P$1_P$150") (pintype "power_in"))
      (node (ref "P6") (pin "P$151") (pinfunction "P$1_P$151") (pintype "power_in"))
      (node (ref "P6") (pin "P$152") (pinfunction "P$1_P$152") (pintype "power_in"))
      (node (ref "P6") (pin "P$153") (pinfunction "P$1_P$153") (pintype "power_in"))
      (node (ref "P6") (pin "P$154") (pinfunction "P$1_P$154") (pintype "power_in"))
      (node (ref "P6") (pin "P$155") (pinfunction "P$1_P$155") (pintype "power_in"))
      (node (ref "P6") (pin "P$156") (pinfunction "P$1_P$156") (pintype "power_in"))
      (node (ref "P6") (pin "P$157") (pinfunction "P$1_P$157") (pintype "power_in"))
      (node (ref "P6") (pin "P$158") (pinfunction "P$1_P$158") (pintype "power_in"))
      (node (ref "P6") (pin "P$159") (pinfunction "P$1_P$159") (pintype "power_in"))
      (node (ref "P6") (pin "P$16") (pinfunction "P$1_P$16") (pintype "power_in"))
      (node (ref "P6") (pin "P$160") (pinfunction "P$1_P$160") (pintype "power_in"))
      (node (ref "P6") (pin "P$161") (pinfunction "P$1_P$161") (pintype "power_in"))
      (node (ref "P6") (pin "P$162") (pinfunction "P$1_P$162") (pintype "power_in"))
      (node (ref "P6") (pin "P$163") (pinfunction "P$1_P$163") (pintype "power_in"))
      (node (ref "P6") (pin "P$164") (pinfunction "P$1_P$164") (pintype "power_in"))
      (node (ref "P6") (pin "P$165") (pinfunction "P$1_P$165") (pintype "power_in"))
      (node (ref "P6") (pin "P$166") (pinfunction "P$1_P$166") (pintype "power_in"))
      (node (ref "P6") (pin "P$167") (pinfunction "P$1_P$167") (pintype "power_in"))
      (node (ref "P6") (pin "P$168") (pinfunction "P$1_P$168") (pintype "power_in"))
      (node (ref "P6") (pin "P$169") (pinfunction "P$1_P$169") (pintype "power_in"))
      (node (ref "P6") (pin "P$17") (pinfunction "P$1_P$17") (pintype "power_in"))
      (node (ref "P6") (pin "P$170") (pinfunction "P$1_P$170") (pintype "power_in"))
      (node (ref "P6") (pin "P$171") (pinfunction "P$1_P$171") (pintype "power_in"))
      (node (ref "P6") (pin "P$172") (pinfunction "P$1_P$172") (pintype "power_in"))
      (node (ref "P6") (pin "P$173") (pinfunction "P$1_P$173") (pintype "power_in"))
      (node (ref "P6") (pin "P$174") (pinfunction "P$1_P$174") (pintype "power_in"))
      (node (ref "P6") (pin "P$175") (pinfunction "P$1_P$175") (pintype "power_in"))
      (node (ref "P6") (pin "P$176") (pinfunction "P$1_P$176") (pintype "power_in"))
      (node (ref "P6") (pin "P$177") (pinfunction "P$1_P$177") (pintype "power_in"))
      (node (ref "P6") (pin "P$178") (pinfunction "P$1_P$178") (pintype "power_in"))
      (node (ref "P6") (pin "P$179") (pinfunction "P$1_P$179") (pintype "power_in"))
      (node (ref "P6") (pin "P$18") (pinfunction "P$1_P$18") (pintype "power_in"))
      (node (ref "P6") (pin "P$180") (pinfunction "P$1_P$180") (pintype "power_in"))
      (node (ref "P6") (pin "P$181") (pinfunction "P$1_P$181") (pintype "power_in"))
      (node (ref "P6") (pin "P$182") (pinfunction "P$1_P$182") (pintype "power_in"))
      (node (ref "P6") (pin "P$183") (pinfunction "P$1_P$183") (pintype "power_in"))
      (node (ref "P6") (pin "P$184") (pinfunction "P$1_P$184") (pintype "power_in"))
      (node (ref "P6") (pin "P$185") (pinfunction "P$1_P$185") (pintype "power_in"))
      (node (ref "P6") (pin "P$186") (pinfunction "P$1_P$186") (pintype "power_in"))
      (node (ref "P6") (pin "P$187") (pinfunction "P$1_P$187") (pintype "power_in"))
      (node (ref "P6") (pin "P$188") (pinfunction "P$1_P$188") (pintype "power_in"))
      (node (ref "P6") (pin "P$189") (pinfunction "P$1_P$189") (pintype "power_in"))
      (node (ref "P6") (pin "P$19") (pinfunction "P$1_P$19") (pintype "power_in"))
      (node (ref "P6") (pin "P$190") (pinfunction "P$1_P$190") (pintype "power_in"))
      (node (ref "P6") (pin "P$191") (pinfunction "P$1_P$191") (pintype "power_in"))
      (node (ref "P6") (pin "P$192") (pinfunction "P$1_P$192") (pintype "power_in"))
      (node (ref "P6") (pin "P$193") (pinfunction "P$1_P$193") (pintype "power_in"))
      (node (ref "P6") (pin "P$194") (pinfunction "P$1_P$194") (pintype "power_in"))
      (node (ref "P6") (pin "P$195") (pinfunction "P$1_P$195") (pintype "power_in"))
      (node (ref "P6") (pin "P$196") (pinfunction "P$1_P$196") (pintype "power_in"))
      (node (ref "P6") (pin "P$197") (pinfunction "P$1_P$197") (pintype "power_in"))
      (node (ref "P6") (pin "P$198") (pinfunction "P$1_P$198") (pintype "power_in"))
      (node (ref "P6") (pin "P$199") (pinfunction "P$1_P$199") (pintype "power_in"))
      (node (ref "P6") (pin "P$2") (pinfunction "P$1_P$2") (pintype "power_in"))
      (node (ref "P6") (pin "P$20") (pinfunction "P$1_P$20") (pintype "power_in"))
      (node (ref "P6") (pin "P$200") (pinfunction "P$1_P$200") (pintype "power_in"))
      (node (ref "P6") (pin "P$201") (pinfunction "P$1_P$201") (pintype "power_in"))
      (node (ref "P6") (pin "P$202") (pinfunction "P$1_P$202") (pintype "power_in"))
      (node (ref "P6") (pin "P$203") (pinfunction "P$1_P$203") (pintype "power_in"))
      (node (ref "P6") (pin "P$204") (pinfunction "P$1_P$204") (pintype "power_in"))
      (node (ref "P6") (pin "P$205") (pinfunction "P$1_P$205") (pintype "power_in"))
      (node (ref "P6") (pin "P$206") (pinfunction "P$1_P$206") (pintype "power_in"))
      (node (ref "P6") (pin "P$207") (pinfunction "P$1_P$207") (pintype "power_in"))
      (node (ref "P6") (pin "P$208") (pinfunction "P$1_P$208") (pintype "power_in"))
      (node (ref "P6") (pin "P$209") (pinfunction "P$1_P$209") (pintype "power_in"))
      (node (ref "P6") (pin "P$21") (pinfunction "P$1_P$21") (pintype "power_in"))
      (node (ref "P6") (pin "P$210") (pinfunction "P$1_P$210") (pintype "power_in"))
      (node (ref "P6") (pin "P$211") (pinfunction "P$1_P$211") (pintype "power_in"))
      (node (ref "P6") (pin "P$212") (pinfunction "P$1_P$212") (pintype "power_in"))
      (node (ref "P6") (pin "P$213") (pinfunction "P$1_P$213") (pintype "power_in"))
      (node (ref "P6") (pin "P$214") (pinfunction "P$1_P$214") (pintype "power_in"))
      (node (ref "P6") (pin "P$215") (pinfunction "P$1_P$215") (pintype "power_in"))
      (node (ref "P6") (pin "P$216") (pinfunction "P$1_P$216") (pintype "power_in"))
      (node (ref "P6") (pin "P$217") (pinfunction "P$1_P$217") (pintype "power_in"))
      (node (ref "P6") (pin "P$218") (pinfunction "P$1_P$218") (pintype "power_in"))
      (node (ref "P6") (pin "P$219") (pinfunction "P$1_P$219") (pintype "power_in"))
      (node (ref "P6") (pin "P$22") (pinfunction "P$1_P$22") (pintype "power_in"))
      (node (ref "P6") (pin "P$220") (pinfunction "P$1_P$220") (pintype "power_in"))
      (node (ref "P6") (pin "P$221") (pinfunction "P$1_P$221") (pintype "power_in"))
      (node (ref "P6") (pin "P$222") (pinfunction "P$1_P$222") (pintype "power_in"))
      (node (ref "P6") (pin "P$223") (pinfunction "P$1_P$223") (pintype "power_in"))
      (node (ref "P6") (pin "P$224") (pinfunction "P$1_P$224") (pintype "power_in"))
      (node (ref "P6") (pin "P$225") (pinfunction "P$1_P$225") (pintype "power_in"))
      (node (ref "P6") (pin "P$226") (pinfunction "P$1_P$226") (pintype "power_in"))
      (node (ref "P6") (pin "P$227") (pinfunction "P$1_P$227") (pintype "power_in"))
      (node (ref "P6") (pin "P$228") (pinfunction "P$1_P$228") (pintype "power_in"))
      (node (ref "P6") (pin "P$229") (pinfunction "P$1_P$229") (pintype "power_in"))
      (node (ref "P6") (pin "P$23") (pinfunction "P$1_P$23") (pintype "power_in"))
      (node (ref "P6") (pin "P$230") (pinfunction "P$1_P$230") (pintype "power_in"))
      (node (ref "P6") (pin "P$231") (pinfunction "P$1_P$231") (pintype "power_in"))
      (node (ref "P6") (pin "P$232") (pinfunction "P$1_P$232") (pintype "power_in"))
      (node (ref "P6") (pin "P$233") (pinfunction "P$1_P$233") (pintype "power_in"))
      (node (ref "P6") (pin "P$234") (pinfunction "P$1_P$234") (pintype "power_in"))
      (node (ref "P6") (pin "P$235") (pinfunction "P$1_P$235") (pintype "power_in"))
      (node (ref "P6") (pin "P$236") (pinfunction "P$1_P$236") (pintype "power_in"))
      (node (ref "P6") (pin "P$237") (pinfunction "P$1_P$237") (pintype "power_in"))
      (node (ref "P6") (pin "P$238") (pinfunction "P$1_P$238") (pintype "power_in"))
      (node (ref "P6") (pin "P$239") (pinfunction "P$1_P$239") (pintype "power_in"))
      (node (ref "P6") (pin "P$24") (pinfunction "P$1_P$24") (pintype "power_in"))
      (node (ref "P6") (pin "P$240") (pinfunction "P$1_P$240") (pintype "power_in"))
      (node (ref "P6") (pin "P$241") (pinfunction "P$1_P$241") (pintype "power_in"))
      (node (ref "P6") (pin "P$242") (pinfunction "P$1_P$242") (pintype "power_in"))
      (node (ref "P6") (pin "P$243") (pinfunction "P$1_P$243") (pintype "power_in"))
      (node (ref "P6") (pin "P$244") (pinfunction "P$1_P$244") (pintype "power_in"))
      (node (ref "P6") (pin "P$245") (pinfunction "P$1_P$245") (pintype "power_in"))
      (node (ref "P6") (pin "P$246") (pinfunction "P$1_P$246") (pintype "power_in"))
      (node (ref "P6") (pin "P$247") (pinfunction "P$1_P$247") (pintype "power_in"))
      (node (ref "P6") (pin "P$248") (pinfunction "P$1_P$248") (pintype "power_in"))
      (node (ref "P6") (pin "P$249") (pinfunction "P$1_P$249") (pintype "power_in"))
      (node (ref "P6") (pin "P$25") (pinfunction "P$1_P$25") (pintype "power_in"))
      (node (ref "P6") (pin "P$250") (pinfunction "P$1_P$250") (pintype "power_in"))
      (node (ref "P6") (pin "P$251") (pinfunction "P$1_P$251") (pintype "power_in"))
      (node (ref "P6") (pin "P$252") (pinfunction "P$1_P$252") (pintype "power_in"))
      (node (ref "P6") (pin "P$253") (pinfunction "P$1_P$253") (pintype "power_in"))
      (node (ref "P6") (pin "P$254") (pinfunction "P$1_P$254") (pintype "power_in"))
      (node (ref "P6") (pin "P$255") (pinfunction "P$1_P$255") (pintype "power_in"))
      (node (ref "P6") (pin "P$256") (pinfunction "P$1_P$256") (pintype "power_in"))
      (node (ref "P6") (pin "P$257") (pinfunction "P$1_P$257") (pintype "power_in"))
      (node (ref "P6") (pin "P$258") (pinfunction "P$1_P$258") (pintype "power_in"))
      (node (ref "P6") (pin "P$259") (pinfunction "P$1_P$259") (pintype "power_in"))
      (node (ref "P6") (pin "P$26") (pinfunction "P$1_P$26") (pintype "power_in"))
      (node (ref "P6") (pin "P$260") (pinfunction "P$1_P$260") (pintype "power_in"))
      (node (ref "P6") (pin "P$261") (pinfunction "P$1_P$261") (pintype "power_in"))
      (node (ref "P6") (pin "P$262") (pinfunction "P$1_P$262") (pintype "power_in"))
      (node (ref "P6") (pin "P$263") (pinfunction "P$1_P$263") (pintype "power_in"))
      (node (ref "P6") (pin "P$264") (pinfunction "P$1_P$264") (pintype "power_in"))
      (node (ref "P6") (pin "P$265") (pinfunction "P$1_P$265") (pintype "power_in"))
      (node (ref "P6") (pin "P$266") (pinfunction "P$1_P$266") (pintype "power_in"))
      (node (ref "P6") (pin "P$267") (pinfunction "P$1_P$267") (pintype "power_in"))
      (node (ref "P6") (pin "P$268") (pinfunction "P$1_P$268") (pintype "power_in"))
      (node (ref "P6") (pin "P$269") (pinfunction "P$1_P$269") (pintype "power_in"))
      (node (ref "P6") (pin "P$27") (pinfunction "P$1_P$27") (pintype "power_in"))
      (node (ref "P6") (pin "P$270") (pinfunction "P$1_P$270") (pintype "power_in"))
      (node (ref "P6") (pin "P$271") (pinfunction "P$1_P$271") (pintype "power_in"))
      (node (ref "P6") (pin "P$272") (pinfunction "P$1_P$272") (pintype "power_in"))
      (node (ref "P6") (pin "P$273") (pinfunction "P$1_P$273") (pintype "power_in"))
      (node (ref "P6") (pin "P$274") (pinfunction "P$1_P$274") (pintype "power_in"))
      (node (ref "P6") (pin "P$275") (pinfunction "P$1_P$275") (pintype "power_in"))
      (node (ref "P6") (pin "P$276") (pinfunction "P$1_P$276") (pintype "power_in"))
      (node (ref "P6") (pin "P$277") (pinfunction "P$1_P$277") (pintype "power_in"))
      (node (ref "P6") (pin "P$278") (pinfunction "P$1_P$278") (pintype "power_in"))
      (node (ref "P6") (pin "P$279") (pinfunction "P$1_P$279") (pintype "power_in"))
      (node (ref "P6") (pin "P$28") (pinfunction "P$1_P$28") (pintype "power_in"))
      (node (ref "P6") (pin "P$280") (pinfunction "P$1_P$280") (pintype "power_in"))
      (node (ref "P6") (pin "P$281") (pinfunction "P$1_P$281") (pintype "power_in"))
      (node (ref "P6") (pin "P$282") (pinfunction "P$1_P$282") (pintype "power_in"))
      (node (ref "P6") (pin "P$283") (pinfunction "P$1_P$283") (pintype "power_in"))
      (node (ref "P6") (pin "P$284") (pinfunction "P$1_P$284") (pintype "power_in"))
      (node (ref "P6") (pin "P$285") (pinfunction "P$1_P$285") (pintype "power_in"))
      (node (ref "P6") (pin "P$286") (pinfunction "P$1_P$286") (pintype "power_in"))
      (node (ref "P6") (pin "P$287") (pinfunction "P$1_P$287") (pintype "power_in"))
      (node (ref "P6") (pin "P$288") (pinfunction "P$1_P$288") (pintype "power_in"))
      (node (ref "P6") (pin "P$289") (pinfunction "P$1_P$289") (pintype "power_in"))
      (node (ref "P6") (pin "P$29") (pinfunction "P$1_P$29") (pintype "power_in"))
      (node (ref "P6") (pin "P$290") (pinfunction "P$1_P$290") (pintype "power_in"))
      (node (ref "P6") (pin "P$291") (pinfunction "P$1_P$291") (pintype "power_in"))
      (node (ref "P6") (pin "P$292") (pinfunction "P$1_P$292") (pintype "power_in"))
      (node (ref "P6") (pin "P$293") (pinfunction "P$1_P$293") (pintype "power_in"))
      (node (ref "P6") (pin "P$294") (pinfunction "P$1_P$294") (pintype "power_in"))
      (node (ref "P6") (pin "P$295") (pinfunction "P$1_P$295") (pintype "power_in"))
      (node (ref "P6") (pin "P$296") (pinfunction "P$1_P$296") (pintype "power_in"))
      (node (ref "P6") (pin "P$297") (pinfunction "P$1_P$297") (pintype "power_in"))
      (node (ref "P6") (pin "P$298") (pinfunction "P$1_P$298") (pintype "power_in"))
      (node (ref "P6") (pin "P$299") (pinfunction "P$1_P$299") (pintype "power_in"))
      (node (ref "P6") (pin "P$3") (pinfunction "P$1_P$3") (pintype "power_in"))
      (node (ref "P6") (pin "P$30") (pinfunction "P$1_P$30") (pintype "power_in"))
      (node (ref "P6") (pin "P$300") (pinfunction "P$1_P$300") (pintype "power_in"))
      (node (ref "P6") (pin "P$301") (pinfunction "P$1_P$301") (pintype "power_in"))
      (node (ref "P6") (pin "P$302") (pinfunction "P$1_P$302") (pintype "power_in"))
      (node (ref "P6") (pin "P$303") (pinfunction "P$1_P$303") (pintype "power_in"))
      (node (ref "P6") (pin "P$304") (pinfunction "P$1_P$304") (pintype "power_in"))
      (node (ref "P6") (pin "P$305") (pinfunction "P$1_P$305") (pintype "power_in"))
      (node (ref "P6") (pin "P$306") (pinfunction "P$1_P$306") (pintype "power_in"))
      (node (ref "P6") (pin "P$307") (pinfunction "P$1_P$307") (pintype "power_in"))
      (node (ref "P6") (pin "P$308") (pinfunction "P$1_P$308") (pintype "power_in"))
      (node (ref "P6") (pin "P$309") (pinfunction "P$1_P$309") (pintype "power_in"))
      (node (ref "P6") (pin "P$31") (pinfunction "P$1_P$31") (pintype "power_in"))
      (node (ref "P6") (pin "P$310") (pinfunction "P$1_P$310") (pintype "power_in"))
      (node (ref "P6") (pin "P$311") (pinfunction "P$1_P$311") (pintype "power_in"))
      (node (ref "P6") (pin "P$312") (pinfunction "P$1_P$312") (pintype "power_in"))
      (node (ref "P6") (pin "P$313") (pinfunction "P$1_P$313") (pintype "power_in"))
      (node (ref "P6") (pin "P$314") (pinfunction "P$1_P$314") (pintype "power_in"))
      (node (ref "P6") (pin "P$315") (pinfunction "P$1_P$315") (pintype "power_in"))
      (node (ref "P6") (pin "P$316") (pinfunction "P$1_P$316") (pintype "power_in"))
      (node (ref "P6") (pin "P$317") (pinfunction "P$1_P$317") (pintype "power_in"))
      (node (ref "P6") (pin "P$318") (pinfunction "P$1_P$318") (pintype "power_in"))
      (node (ref "P6") (pin "P$319") (pinfunction "P$1_P$319") (pintype "power_in"))
      (node (ref "P6") (pin "P$32") (pinfunction "P$1_P$32") (pintype "power_in"))
      (node (ref "P6") (pin "P$320") (pinfunction "P$1_P$320") (pintype "power_in"))
      (node (ref "P6") (pin "P$321") (pinfunction "P$1_P$321") (pintype "power_in"))
      (node (ref "P6") (pin "P$322") (pinfunction "P$1_P$322") (pintype "power_in"))
      (node (ref "P6") (pin "P$323") (pinfunction "P$1_P$323") (pintype "power_in"))
      (node (ref "P6") (pin "P$324") (pinfunction "P$1_P$324") (pintype "power_in"))
      (node (ref "P6") (pin "P$325") (pinfunction "P$1_P$325") (pintype "power_in"))
      (node (ref "P6") (pin "P$326") (pinfunction "P$1_P$326") (pintype "power_in"))
      (node (ref "P6") (pin "P$327") (pinfunction "P$1_P$327") (pintype "power_in"))
      (node (ref "P6") (pin "P$328") (pinfunction "P$1_P$328") (pintype "power_in"))
      (node (ref "P6") (pin "P$329") (pinfunction "P$1_P$329") (pintype "power_in"))
      (node (ref "P6") (pin "P$33") (pinfunction "P$1_P$33") (pintype "power_in"))
      (node (ref "P6") (pin "P$330") (pinfunction "P$1_P$330") (pintype "power_in"))
      (node (ref "P6") (pin "P$331") (pinfunction "P$1_P$331") (pintype "power_in"))
      (node (ref "P6") (pin "P$332") (pinfunction "P$1_P$332") (pintype "power_in"))
      (node (ref "P6") (pin "P$333") (pinfunction "P$1_P$333") (pintype "power_in"))
      (node (ref "P6") (pin "P$334") (pinfunction "P$1_P$334") (pintype "power_in"))
      (node (ref "P6") (pin "P$335") (pinfunction "P$1_P$335") (pintype "power_in"))
      (node (ref "P6") (pin "P$336") (pinfunction "P$1_P$336") (pintype "power_in"))
      (node (ref "P6") (pin "P$337") (pinfunction "P$1_P$337") (pintype "power_in"))
      (node (ref "P6") (pin "P$338") (pinfunction "P$1_P$338") (pintype "power_in"))
      (node (ref "P6") (pin "P$339") (pinfunction "P$1_P$339") (pintype "power_in"))
      (node (ref "P6") (pin "P$34") (pinfunction "P$1_P$34") (pintype "power_in"))
      (node (ref "P6") (pin "P$340") (pinfunction "P$1_P$340") (pintype "power_in"))
      (node (ref "P6") (pin "P$341") (pinfunction "P$1_P$341") (pintype "power_in"))
      (node (ref "P6") (pin "P$342") (pinfunction "P$1_P$342") (pintype "power_in"))
      (node (ref "P6") (pin "P$343") (pinfunction "P$1_P$343") (pintype "power_in"))
      (node (ref "P6") (pin "P$344") (pinfunction "P$1_P$344") (pintype "power_in"))
      (node (ref "P6") (pin "P$345") (pinfunction "P$1_P$345") (pintype "power_in"))
      (node (ref "P6") (pin "P$346") (pinfunction "P$1_P$346") (pintype "power_in"))
      (node (ref "P6") (pin "P$347") (pinfunction "P$1_P$347") (pintype "power_in"))
      (node (ref "P6") (pin "P$348") (pinfunction "P$1_P$348") (pintype "power_in"))
      (node (ref "P6") (pin "P$349") (pinfunction "P$1_P$349") (pintype "power_in"))
      (node (ref "P6") (pin "P$35") (pinfunction "P$1_P$35") (pintype "power_in"))
      (node (ref "P6") (pin "P$350") (pinfunction "P$1_P$350") (pintype "power_in"))
      (node (ref "P6") (pin "P$351") (pinfunction "P$1_P$351") (pintype "power_in"))
      (node (ref "P6") (pin "P$352") (pinfunction "P$1_P$352") (pintype "power_in"))
      (node (ref "P6") (pin "P$353") (pinfunction "P$1_P$353") (pintype "power_in"))
      (node (ref "P6") (pin "P$354") (pinfunction "P$1_P$354") (pintype "power_in"))
      (node (ref "P6") (pin "P$355") (pinfunction "P$1_P$355") (pintype "power_in"))
      (node (ref "P6") (pin "P$356") (pinfunction "P$1_P$356") (pintype "power_in"))
      (node (ref "P6") (pin "P$357") (pinfunction "P$1_P$357") (pintype "power_in"))
      (node (ref "P6") (pin "P$358") (pinfunction "P$1_P$358") (pintype "power_in"))
      (node (ref "P6") (pin "P$359") (pinfunction "P$1_P$359") (pintype "power_in"))
      (node (ref "P6") (pin "P$36") (pinfunction "P$1_P$36") (pintype "power_in"))
      (node (ref "P6") (pin "P$360") (pinfunction "P$1_P$360") (pintype "power_in"))
      (node (ref "P6") (pin "P$361") (pinfunction "P$1_P$361") (pintype "power_in"))
      (node (ref "P6") (pin "P$362") (pinfunction "P$1_P$362") (pintype "power_in"))
      (node (ref "P6") (pin "P$363") (pinfunction "P$1_P$363") (pintype "power_in"))
      (node (ref "P6") (pin "P$364") (pinfunction "P$1_P$364") (pintype "power_in"))
      (node (ref "P6") (pin "P$365") (pinfunction "P$1_P$365") (pintype "power_in"))
      (node (ref "P6") (pin "P$366") (pinfunction "P$1_P$366") (pintype "power_in"))
      (node (ref "P6") (pin "P$367") (pinfunction "P$1_P$367") (pintype "power_in"))
      (node (ref "P6") (pin "P$368") (pinfunction "P$1_P$368") (pintype "power_in"))
      (node (ref "P6") (pin "P$369") (pinfunction "P$1_P$369") (pintype "power_in"))
      (node (ref "P6") (pin "P$37") (pinfunction "P$1_P$37") (pintype "power_in"))
      (node (ref "P6") (pin "P$370") (pinfunction "P$1_P$370") (pintype "power_in"))
      (node (ref "P6") (pin "P$371") (pinfunction "P$1_P$371") (pintype "power_in"))
      (node (ref "P6") (pin "P$372") (pinfunction "P$1_P$372") (pintype "power_in"))
      (node (ref "P6") (pin "P$373") (pinfunction "P$1_P$373") (pintype "power_in"))
      (node (ref "P6") (pin "P$374") (pinfunction "P$1_P$374") (pintype "power_in"))
      (node (ref "P6") (pin "P$375") (pinfunction "P$1_P$375") (pintype "power_in"))
      (node (ref "P6") (pin "P$376") (pinfunction "P$1_P$376") (pintype "power_in"))
      (node (ref "P6") (pin "P$377") (pinfunction "P$1_P$377") (pintype "power_in"))
      (node (ref "P6") (pin "P$378") (pinfunction "P$1_P$378") (pintype "power_in"))
      (node (ref "P6") (pin "P$379") (pinfunction "P$1_P$379") (pintype "power_in"))
      (node (ref "P6") (pin "P$38") (pinfunction "P$1_P$38") (pintype "power_in"))
      (node (ref "P6") (pin "P$380") (pinfunction "P$1_P$380") (pintype "power_in"))
      (node (ref "P6") (pin "P$381") (pinfunction "P$1_P$381") (pintype "power_in"))
      (node (ref "P6") (pin "P$382") (pinfunction "P$1_P$382") (pintype "power_in"))
      (node (ref "P6") (pin "P$383") (pinfunction "P$1_P$383") (pintype "power_in"))
      (node (ref "P6") (pin "P$384") (pinfunction "P$1_P$384") (pintype "power_in"))
      (node (ref "P6") (pin "P$385") (pinfunction "P$1_P$385") (pintype "power_in"))
      (node (ref "P6") (pin "P$386") (pinfunction "P$1_P$386") (pintype "power_in"))
      (node (ref "P6") (pin "P$387") (pinfunction "P$1_P$387") (pintype "power_in"))
      (node (ref "P6") (pin "P$388") (pinfunction "P$1_P$388") (pintype "power_in"))
      (node (ref "P6") (pin "P$389") (pinfunction "P$1_P$389") (pintype "power_in"))
      (node (ref "P6") (pin "P$39") (pinfunction "P$1_P$39") (pintype "power_in"))
      (node (ref "P6") (pin "P$390") (pinfunction "P$1_P$390") (pintype "power_in"))
      (node (ref "P6") (pin "P$391") (pinfunction "P$1_P$391") (pintype "power_in"))
      (node (ref "P6") (pin "P$392") (pinfunction "P$1_P$392") (pintype "power_in"))
      (node (ref "P6") (pin "P$393") (pinfunction "P$1_P$393") (pintype "power_in"))
      (node (ref "P6") (pin "P$394") (pinfunction "P$1_P$394") (pintype "power_in"))
      (node (ref "P6") (pin "P$395") (pinfunction "P$1_P$395") (pintype "power_in"))
      (node (ref "P6") (pin "P$396") (pinfunction "P$1_P$396") (pintype "power_in"))
      (node (ref "P6") (pin "P$397") (pinfunction "P$1_P$397") (pintype "power_in"))
      (node (ref "P6") (pin "P$398") (pinfunction "P$1_P$398") (pintype "power_in"))
      (node (ref "P6") (pin "P$399") (pinfunction "P$1_P$399") (pintype "power_in"))
      (node (ref "P6") (pin "P$4") (pinfunction "P$1_P$4") (pintype "power_in"))
      (node (ref "P6") (pin "P$40") (pinfunction "P$1_P$40") (pintype "power_in"))
      (node (ref "P6") (pin "P$400") (pinfunction "P$1_P$400") (pintype "power_in"))
      (node (ref "P6") (pin "P$401") (pinfunction "P$1_P$401") (pintype "power_in"))
      (node (ref "P6") (pin "P$402") (pinfunction "P$1_P$402") (pintype "power_in"))
      (node (ref "P6") (pin "P$403") (pinfunction "P$1_P$403") (pintype "power_in"))
      (node (ref "P6") (pin "P$404") (pinfunction "P$1_P$404") (pintype "power_in"))
      (node (ref "P6") (pin "P$405") (pinfunction "P$1_P$405") (pintype "power_in"))
      (node (ref "P6") (pin "P$406") (pinfunction "P$1_P$406") (pintype "power_in"))
      (node (ref "P6") (pin "P$407") (pinfunction "P$1_P$407") (pintype "power_in"))
      (node (ref "P6") (pin "P$408") (pinfunction "P$1_P$408") (pintype "power_in"))
      (node (ref "P6") (pin "P$409") (pinfunction "P$1_P$409") (pintype "power_in"))
      (node (ref "P6") (pin "P$41") (pinfunction "P$1_P$41") (pintype "power_in"))
      (node (ref "P6") (pin "P$410") (pinfunction "P$1_P$410") (pintype "power_in"))
      (node (ref "P6") (pin "P$411") (pinfunction "P$1_P$411") (pintype "power_in"))
      (node (ref "P6") (pin "P$412") (pinfunction "P$1_P$412") (pintype "power_in"))
      (node (ref "P6") (pin "P$413") (pinfunction "P$1_P$413") (pintype "power_in"))
      (node (ref "P6") (pin "P$414") (pinfunction "P$1_P$414") (pintype "power_in"))
      (node (ref "P6") (pin "P$415") (pinfunction "P$1_P$415") (pintype "power_in"))
      (node (ref "P6") (pin "P$416") (pinfunction "P$1_P$416") (pintype "power_in"))
      (node (ref "P6") (pin "P$417") (pinfunction "P$1_P$417") (pintype "power_in"))
      (node (ref "P6") (pin "P$418") (pinfunction "P$1_P$418") (pintype "power_in"))
      (node (ref "P6") (pin "P$419") (pinfunction "P$1_P$419") (pintype "power_in"))
      (node (ref "P6") (pin "P$42") (pinfunction "P$1_P$42") (pintype "power_in"))
      (node (ref "P6") (pin "P$420") (pinfunction "P$1_P$420") (pintype "power_in"))
      (node (ref "P6") (pin "P$421") (pinfunction "P$1_P$421") (pintype "power_in"))
      (node (ref "P6") (pin "P$422") (pinfunction "P$1_P$422") (pintype "power_in"))
      (node (ref "P6") (pin "P$423") (pinfunction "P$1_P$423") (pintype "power_in"))
      (node (ref "P6") (pin "P$424") (pinfunction "P$1_P$424") (pintype "power_in"))
      (node (ref "P6") (pin "P$425") (pinfunction "P$1_P$425") (pintype "power_in"))
      (node (ref "P6") (pin "P$426") (pinfunction "P$1_P$426") (pintype "power_in"))
      (node (ref "P6") (pin "P$427") (pinfunction "P$1_P$427") (pintype "power_in"))
      (node (ref "P6") (pin "P$428") (pinfunction "P$1_P$428") (pintype "power_in"))
      (node (ref "P6") (pin "P$429") (pinfunction "P$1_P$429") (pintype "power_in"))
      (node (ref "P6") (pin "P$43") (pinfunction "P$1_P$43") (pintype "power_in"))
      (node (ref "P6") (pin "P$430") (pinfunction "P$1_P$430") (pintype "power_in"))
      (node (ref "P6") (pin "P$431") (pinfunction "P$1_P$431") (pintype "power_in"))
      (node (ref "P6") (pin "P$432") (pinfunction "P$1_P$432") (pintype "power_in"))
      (node (ref "P6") (pin "P$433") (pinfunction "P$1_P$433") (pintype "power_in"))
      (node (ref "P6") (pin "P$434") (pinfunction "P$1_P$434") (pintype "power_in"))
      (node (ref "P6") (pin "P$435") (pinfunction "P$1_P$435") (pintype "power_in"))
      (node (ref "P6") (pin "P$436") (pinfunction "P$1_P$436") (pintype "power_in"))
      (node (ref "P6") (pin "P$437") (pinfunction "P$1_P$437") (pintype "power_in"))
      (node (ref "P6") (pin "P$438") (pinfunction "P$1_P$438") (pintype "power_in"))
      (node (ref "P6") (pin "P$439") (pinfunction "P$1_P$439") (pintype "power_in"))
      (node (ref "P6") (pin "P$44") (pinfunction "P$1_P$44") (pintype "power_in"))
      (node (ref "P6") (pin "P$440") (pinfunction "P$1_P$440") (pintype "power_in"))
      (node (ref "P6") (pin "P$441") (pinfunction "P$1_P$441") (pintype "power_in"))
      (node (ref "P6") (pin "P$442") (pinfunction "P$1_P$442") (pintype "power_in"))
      (node (ref "P6") (pin "P$443") (pinfunction "P$1_P$443") (pintype "power_in"))
      (node (ref "P6") (pin "P$444") (pinfunction "P$1_P$444") (pintype "power_in"))
      (node (ref "P6") (pin "P$445") (pinfunction "P$1_P$445") (pintype "power_in"))
      (node (ref "P6") (pin "P$446") (pinfunction "P$1_P$446") (pintype "power_in"))
      (node (ref "P6") (pin "P$447") (pinfunction "P$1_P$447") (pintype "power_in"))
      (node (ref "P6") (pin "P$448") (pinfunction "P$1_P$448") (pintype "power_in"))
      (node (ref "P6") (pin "P$449") (pinfunction "P$1_P$449") (pintype "power_in"))
      (node (ref "P6") (pin "P$45") (pinfunction "P$1_P$45") (pintype "power_in"))
      (node (ref "P6") (pin "P$450") (pinfunction "P$1_P$450") (pintype "power_in"))
      (node (ref "P6") (pin "P$451") (pinfunction "P$1_P$451") (pintype "power_in"))
      (node (ref "P6") (pin "P$452") (pinfunction "P$1_P$452") (pintype "power_in"))
      (node (ref "P6") (pin "P$453") (pinfunction "P$1_P$453") (pintype "power_in"))
      (node (ref "P6") (pin "P$454") (pinfunction "P$1_P$454") (pintype "power_in"))
      (node (ref "P6") (pin "P$455") (pinfunction "P$1_P$455") (pintype "power_in"))
      (node (ref "P6") (pin "P$456") (pinfunction "P$1_P$456") (pintype "power_in"))
      (node (ref "P6") (pin "P$457") (pinfunction "P$1_P$457") (pintype "power_in"))
      (node (ref "P6") (pin "P$458") (pinfunction "P$1_P$458") (pintype "power_in"))
      (node (ref "P6") (pin "P$459") (pinfunction "P$1_P$459") (pintype "power_in"))
      (node (ref "P6") (pin "P$46") (pinfunction "P$1_P$46") (pintype "power_in"))
      (node (ref "P6") (pin "P$460") (pinfunction "P$1_P$460") (pintype "power_in"))
      (node (ref "P6") (pin "P$461") (pinfunction "P$1_P$461") (pintype "power_in"))
      (node (ref "P6") (pin "P$462") (pinfunction "P$1_P$462") (pintype "power_in"))
      (node (ref "P6") (pin "P$463") (pinfunction "P$1_P$463") (pintype "power_in"))
      (node (ref "P6") (pin "P$464") (pinfunction "P$1_P$464") (pintype "power_in"))
      (node (ref "P6") (pin "P$465") (pinfunction "P$1_P$465") (pintype "power_in"))
      (node (ref "P6") (pin "P$466") (pinfunction "P$1_P$466") (pintype "power_in"))
      (node (ref "P6") (pin "P$467") (pinfunction "P$1_P$467") (pintype "power_in"))
      (node (ref "P6") (pin "P$468") (pinfunction "P$1_P$468") (pintype "power_in"))
      (node (ref "P6") (pin "P$469") (pinfunction "P$1_P$469") (pintype "power_in"))
      (node (ref "P6") (pin "P$47") (pinfunction "P$1_P$47") (pintype "power_in"))
      (node (ref "P6") (pin "P$470") (pinfunction "P$1_P$470") (pintype "power_in"))
      (node (ref "P6") (pin "P$471") (pinfunction "P$1_P$471") (pintype "power_in"))
      (node (ref "P6") (pin "P$472") (pinfunction "P$1_P$472") (pintype "power_in"))
      (node (ref "P6") (pin "P$473") (pinfunction "P$1_P$473") (pintype "power_in"))
      (node (ref "P6") (pin "P$474") (pinfunction "P$1_P$474") (pintype "power_in"))
      (node (ref "P6") (pin "P$475") (pinfunction "P$1_P$475") (pintype "power_in"))
      (node (ref "P6") (pin "P$476") (pinfunction "P$1_P$476") (pintype "power_in"))
      (node (ref "P6") (pin "P$477") (pinfunction "P$1_P$477") (pintype "power_in"))
      (node (ref "P6") (pin "P$478") (pinfunction "P$1_P$478") (pintype "power_in"))
      (node (ref "P6") (pin "P$479") (pinfunction "P$1_P$479") (pintype "power_in"))
      (node (ref "P6") (pin "P$48") (pinfunction "P$1_P$48") (pintype "power_in"))
      (node (ref "P6") (pin "P$480") (pinfunction "P$1_P$480") (pintype "power_in"))
      (node (ref "P6") (pin "P$481") (pinfunction "P$1_P$481") (pintype "power_in"))
      (node (ref "P6") (pin "P$482") (pinfunction "P$1_P$482") (pintype "power_in"))
      (node (ref "P6") (pin "P$483") (pinfunction "P$1_P$483") (pintype "power_in"))
      (node (ref "P6") (pin "P$484") (pinfunction "P$1_P$484") (pintype "power_in"))
      (node (ref "P6") (pin "P$485") (pinfunction "P$1_P$485") (pintype "power_in"))
      (node (ref "P6") (pin "P$486") (pinfunction "P$1_P$486") (pintype "power_in"))
      (node (ref "P6") (pin "P$487") (pinfunction "P$1_P$487") (pintype "power_in"))
      (node (ref "P6") (pin "P$488") (pinfunction "P$1_P$488") (pintype "power_in"))
      (node (ref "P6") (pin "P$489") (pinfunction "P$1_P$489") (pintype "power_in"))
      (node (ref "P6") (pin "P$49") (pinfunction "P$1_P$49") (pintype "power_in"))
      (node (ref "P6") (pin "P$490") (pinfunction "P$1_P$490") (pintype "power_in"))
      (node (ref "P6") (pin "P$491") (pinfunction "P$1_P$491") (pintype "power_in"))
      (node (ref "P6") (pin "P$492") (pinfunction "P$1_P$492") (pintype "power_in"))
      (node (ref "P6") (pin "P$493") (pinfunction "P$1_P$493") (pintype "power_in"))
      (node (ref "P6") (pin "P$494") (pinfunction "P$1_P$494") (pintype "power_in"))
      (node (ref "P6") (pin "P$495") (pinfunction "P$1_P$495") (pintype "power_in"))
      (node (ref "P6") (pin "P$496") (pinfunction "P$1_P$496") (pintype "power_in"))
      (node (ref "P6") (pin "P$497") (pinfunction "P$1_P$497") (pintype "power_in"))
      (node (ref "P6") (pin "P$498") (pinfunction "P$1_P$498") (pintype "power_in"))
      (node (ref "P6") (pin "P$499") (pinfunction "P$1_P$499") (pintype "power_in"))
      (node (ref "P6") (pin "P$5") (pinfunction "P$1_P$5") (pintype "power_in"))
      (node (ref "P6") (pin "P$50") (pinfunction "P$1_P$50") (pintype "power_in"))
      (node (ref "P6") (pin "P$500") (pinfunction "P$1_P$500") (pintype "power_in"))
      (node (ref "P6") (pin "P$501") (pinfunction "P$1_P$501") (pintype "power_in"))
      (node (ref "P6") (pin "P$502") (pinfunction "P$1_P$502") (pintype "power_in"))
      (node (ref "P6") (pin "P$503") (pinfunction "P$1_P$503") (pintype "power_in"))
      (node (ref "P6") (pin "P$504") (pinfunction "P$1_P$504") (pintype "power_in"))
      (node (ref "P6") (pin "P$505") (pinfunction "P$1_P$505") (pintype "power_in"))
      (node (ref "P6") (pin "P$506") (pinfunction "P$1_P$506") (pintype "power_in"))
      (node (ref "P6") (pin "P$507") (pinfunction "P$1_P$507") (pintype "power_in"))
      (node (ref "P6") (pin "P$508") (pinfunction "P$1_P$508") (pintype "power_in"))
      (node (ref "P6") (pin "P$509") (pinfunction "P$1_P$509") (pintype "power_in"))
      (node (ref "P6") (pin "P$51") (pinfunction "P$1_P$51") (pintype "power_in"))
      (node (ref "P6") (pin "P$510") (pinfunction "P$1_P$510") (pintype "power_in"))
      (node (ref "P6") (pin "P$511") (pinfunction "P$1_P$511") (pintype "power_in"))
      (node (ref "P6") (pin "P$512") (pinfunction "P$1_P$512") (pintype "power_in"))
      (node (ref "P6") (pin "P$513") (pinfunction "P$1_P$513") (pintype "power_in"))
      (node (ref "P6") (pin "P$514") (pinfunction "P$1_P$514") (pintype "power_in"))
      (node (ref "P6") (pin "P$515") (pinfunction "P$1_P$515") (pintype "power_in"))
      (node (ref "P6") (pin "P$516") (pinfunction "P$1_P$516") (pintype "power_in"))
      (node (ref "P6") (pin "P$517") (pinfunction "P$1_P$517") (pintype "power_in"))
      (node (ref "P6") (pin "P$518") (pinfunction "P$1_P$518") (pintype "power_in"))
      (node (ref "P6") (pin "P$519") (pinfunction "P$1_P$519") (pintype "power_in"))
      (node (ref "P6") (pin "P$52") (pinfunction "P$1_P$52") (pintype "power_in"))
      (node (ref "P6") (pin "P$520") (pinfunction "P$1_P$520") (pintype "power_in"))
      (node (ref "P6") (pin "P$521") (pinfunction "P$1_P$521") (pintype "power_in"))
      (node (ref "P6") (pin "P$522") (pinfunction "P$1_P$522") (pintype "power_in"))
      (node (ref "P6") (pin "P$523") (pinfunction "P$1_P$523") (pintype "power_in"))
      (node (ref "P6") (pin "P$524") (pinfunction "P$1_P$524") (pintype "power_in"))
      (node (ref "P6") (pin "P$525") (pinfunction "P$1_P$525") (pintype "power_in"))
      (node (ref "P6") (pin "P$526") (pinfunction "P$1_P$526") (pintype "power_in"))
      (node (ref "P6") (pin "P$527") (pinfunction "P$1_P$527") (pintype "power_in"))
      (node (ref "P6") (pin "P$528") (pinfunction "P$1_P$528") (pintype "power_in"))
      (node (ref "P6") (pin "P$529") (pinfunction "P$1_P$529") (pintype "power_in"))
      (node (ref "P6") (pin "P$53") (pinfunction "P$1_P$53") (pintype "power_in"))
      (node (ref "P6") (pin "P$530") (pinfunction "P$1_P$530") (pintype "power_in"))
      (node (ref "P6") (pin "P$531") (pinfunction "P$1_P$531") (pintype "power_in"))
      (node (ref "P6") (pin "P$532") (pinfunction "P$1_P$532") (pintype "power_in"))
      (node (ref "P6") (pin "P$533") (pinfunction "P$1_P$533") (pintype "power_in"))
      (node (ref "P6") (pin "P$534") (pinfunction "P$1_P$534") (pintype "power_in"))
      (node (ref "P6") (pin "P$535") (pinfunction "P$1_P$535") (pintype "power_in"))
      (node (ref "P6") (pin "P$536") (pinfunction "P$1_P$536") (pintype "power_in"))
      (node (ref "P6") (pin "P$537") (pinfunction "P$1_P$537") (pintype "power_in"))
      (node (ref "P6") (pin "P$538") (pinfunction "P$1_P$538") (pintype "power_in"))
      (node (ref "P6") (pin "P$539") (pinfunction "P$1_P$539") (pintype "power_in"))
      (node (ref "P6") (pin "P$54") (pinfunction "P$1_P$54") (pintype "power_in"))
      (node (ref "P6") (pin "P$540") (pinfunction "P$1_P$540") (pintype "power_in"))
      (node (ref "P6") (pin "P$541") (pinfunction "P$1_P$541") (pintype "power_in"))
      (node (ref "P6") (pin "P$542") (pinfunction "P$1_P$542") (pintype "power_in"))
      (node (ref "P6") (pin "P$543") (pinfunction "P$1_P$543") (pintype "power_in"))
      (node (ref "P6") (pin "P$544") (pinfunction "P$1_P$544") (pintype "power_in"))
      (node (ref "P6") (pin "P$545") (pinfunction "P$1_P$545") (pintype "power_in"))
      (node (ref "P6") (pin "P$546") (pinfunction "P$1_P$546") (pintype "power_in"))
      (node (ref "P6") (pin "P$547") (pinfunction "P$1_P$547") (pintype "power_in"))
      (node (ref "P6") (pin "P$548") (pinfunction "P$1_P$548") (pintype "power_in"))
      (node (ref "P6") (pin "P$549") (pinfunction "P$1_P$549") (pintype "power_in"))
      (node (ref "P6") (pin "P$55") (pinfunction "P$1_P$55") (pintype "power_in"))
      (node (ref "P6") (pin "P$550") (pinfunction "P$1_P$550") (pintype "power_in"))
      (node (ref "P6") (pin "P$551") (pinfunction "P$1_P$551") (pintype "power_in"))
      (node (ref "P6") (pin "P$552") (pinfunction "P$1_P$552") (pintype "power_in"))
      (node (ref "P6") (pin "P$553") (pinfunction "P$1_P$553") (pintype "power_in"))
      (node (ref "P6") (pin "P$554") (pinfunction "P$1_P$554") (pintype "power_in"))
      (node (ref "P6") (pin "P$555") (pinfunction "P$1_P$555") (pintype "power_in"))
      (node (ref "P6") (pin "P$556") (pinfunction "P$1_P$556") (pintype "power_in"))
      (node (ref "P6") (pin "P$557") (pinfunction "P$1_P$557") (pintype "power_in"))
      (node (ref "P6") (pin "P$558") (pinfunction "P$1_P$558") (pintype "power_in"))
      (node (ref "P6") (pin "P$559") (pinfunction "P$1_P$559") (pintype "power_in"))
      (node (ref "P6") (pin "P$56") (pinfunction "P$1_P$56") (pintype "power_in"))
      (node (ref "P6") (pin "P$560") (pinfunction "P$1_P$560") (pintype "power_in"))
      (node (ref "P6") (pin "P$561") (pinfunction "P$1_P$561") (pintype "power_in"))
      (node (ref "P6") (pin "P$562") (pinfunction "P$1_P$562") (pintype "power_in"))
      (node (ref "P6") (pin "P$563") (pinfunction "P$1_P$563") (pintype "power_in"))
      (node (ref "P6") (pin "P$564") (pinfunction "P$1_P$564") (pintype "power_in"))
      (node (ref "P6") (pin "P$565") (pinfunction "P$1_P$565") (pintype "power_in"))
      (node (ref "P6") (pin "P$566") (pinfunction "P$1_P$566") (pintype "power_in"))
      (node (ref "P6") (pin "P$567") (pinfunction "P$1_P$567") (pintype "power_in"))
      (node (ref "P6") (pin "P$568") (pinfunction "P$1_P$568") (pintype "power_in"))
      (node (ref "P6") (pin "P$569") (pinfunction "P$1_P$569") (pintype "power_in"))
      (node (ref "P6") (pin "P$57") (pinfunction "P$1_P$57") (pintype "power_in"))
      (node (ref "P6") (pin "P$570") (pinfunction "P$1_P$570") (pintype "power_in"))
      (node (ref "P6") (pin "P$571") (pinfunction "P$1_P$571") (pintype "power_in"))
      (node (ref "P6") (pin "P$572") (pinfunction "P$1_P$572") (pintype "power_in"))
      (node (ref "P6") (pin "P$573") (pinfunction "P$1_P$573") (pintype "power_in"))
      (node (ref "P6") (pin "P$574") (pinfunction "P$1_P$574") (pintype "power_in"))
      (node (ref "P6") (pin "P$575") (pinfunction "P$1_P$575") (pintype "power_in"))
      (node (ref "P6") (pin "P$576") (pinfunction "P$1_P$576") (pintype "power_in"))
      (node (ref "P6") (pin "P$577") (pinfunction "P$1_P$577") (pintype "power_in"))
      (node (ref "P6") (pin "P$578") (pinfunction "P$1_P$578") (pintype "power_in"))
      (node (ref "P6") (pin "P$579") (pinfunction "P$1_P$579") (pintype "power_in"))
      (node (ref "P6") (pin "P$58") (pinfunction "P$1_P$58") (pintype "power_in"))
      (node (ref "P6") (pin "P$580") (pinfunction "P$1_P$580") (pintype "power_in"))
      (node (ref "P6") (pin "P$581") (pinfunction "P$1_P$581") (pintype "power_in"))
      (node (ref "P6") (pin "P$582") (pinfunction "P$1_P$582") (pintype "power_in"))
      (node (ref "P6") (pin "P$583") (pinfunction "P$1_P$583") (pintype "power_in"))
      (node (ref "P6") (pin "P$584") (pinfunction "P$1_P$584") (pintype "power_in"))
      (node (ref "P6") (pin "P$585") (pinfunction "P$1_P$585") (pintype "power_in"))
      (node (ref "P6") (pin "P$586") (pinfunction "P$1_P$586") (pintype "power_in"))
      (node (ref "P6") (pin "P$587") (pinfunction "P$1_P$587") (pintype "power_in"))
      (node (ref "P6") (pin "P$588") (pinfunction "P$1_P$588") (pintype "power_in"))
      (node (ref "P6") (pin "P$589") (pinfunction "P$1_P$589") (pintype "power_in"))
      (node (ref "P6") (pin "P$59") (pinfunction "P$1_P$59") (pintype "power_in"))
      (node (ref "P6") (pin "P$590") (pinfunction "P$1_P$590") (pintype "power_in"))
      (node (ref "P6") (pin "P$591") (pinfunction "P$1_P$591") (pintype "power_in"))
      (node (ref "P6") (pin "P$592") (pinfunction "P$1_P$592") (pintype "power_in"))
      (node (ref "P6") (pin "P$593") (pinfunction "P$1_P$593") (pintype "power_in"))
      (node (ref "P6") (pin "P$594") (pinfunction "P$1_P$594") (pintype "power_in"))
      (node (ref "P6") (pin "P$595") (pinfunction "P$1_P$595") (pintype "power_in"))
      (node (ref "P6") (pin "P$596") (pinfunction "P$1_P$596") (pintype "power_in"))
      (node (ref "P6") (pin "P$597") (pinfunction "P$1_P$597") (pintype "power_in"))
      (node (ref "P6") (pin "P$598") (pinfunction "P$1_P$598") (pintype "power_in"))
      (node (ref "P6") (pin "P$599") (pinfunction "P$1_P$599") (pintype "power_in"))
      (node (ref "P6") (pin "P$6") (pinfunction "P$1_P$6") (pintype "power_in"))
      (node (ref "P6") (pin "P$60") (pinfunction "P$1_P$60") (pintype "power_in"))
      (node (ref "P6") (pin "P$600") (pinfunction "P$1_P$600") (pintype "power_in"))
      (node (ref "P6") (pin "P$601") (pinfunction "P$1_P$601") (pintype "power_in"))
      (node (ref "P6") (pin "P$602") (pinfunction "P$1_P$602") (pintype "power_in"))
      (node (ref "P6") (pin "P$603") (pinfunction "P$1_P$603") (pintype "power_in"))
      (node (ref "P6") (pin "P$604") (pinfunction "P$1_P$604") (pintype "power_in"))
      (node (ref "P6") (pin "P$605") (pinfunction "P$1_P$605") (pintype "power_in"))
      (node (ref "P6") (pin "P$606") (pinfunction "P$1_P$606") (pintype "power_in"))
      (node (ref "P6") (pin "P$607") (pinfunction "P$1_P$607") (pintype "power_in"))
      (node (ref "P6") (pin "P$608") (pinfunction "P$1_P$608") (pintype "power_in"))
      (node (ref "P6") (pin "P$609") (pinfunction "P$1_P$609") (pintype "power_in"))
      (node (ref "P6") (pin "P$61") (pinfunction "P$1_P$61") (pintype "power_in"))
      (node (ref "P6") (pin "P$610") (pinfunction "P$1_P$610") (pintype "power_in"))
      (node (ref "P6") (pin "P$611") (pinfunction "P$1_P$611") (pintype "power_in"))
      (node (ref "P6") (pin "P$612") (pinfunction "P$1_P$612") (pintype "power_in"))
      (node (ref "P6") (pin "P$613") (pinfunction "P$1_P$613") (pintype "power_in"))
      (node (ref "P6") (pin "P$614") (pinfunction "P$1_P$614") (pintype "power_in"))
      (node (ref "P6") (pin "P$615") (pinfunction "P$1_P$615") (pintype "power_in"))
      (node (ref "P6") (pin "P$616") (pinfunction "P$1_P$616") (pintype "power_in"))
      (node (ref "P6") (pin "P$617") (pinfunction "P$1_P$617") (pintype "power_in"))
      (node (ref "P6") (pin "P$618") (pinfunction "P$1_P$618") (pintype "power_in"))
      (node (ref "P6") (pin "P$619") (pinfunction "P$1_P$619") (pintype "power_in"))
      (node (ref "P6") (pin "P$62") (pinfunction "P$1_P$62") (pintype "power_in"))
      (node (ref "P6") (pin "P$620") (pinfunction "P$1_P$620") (pintype "power_in"))
      (node (ref "P6") (pin "P$621") (pinfunction "P$1_P$621") (pintype "power_in"))
      (node (ref "P6") (pin "P$622") (pinfunction "P$1_P$622") (pintype "power_in"))
      (node (ref "P6") (pin "P$623") (pinfunction "P$1_P$623") (pintype "power_in"))
      (node (ref "P6") (pin "P$624") (pinfunction "P$1_P$624") (pintype "power_in"))
      (node (ref "P6") (pin "P$625") (pinfunction "P$1_P$625") (pintype "power_in"))
      (node (ref "P6") (pin "P$626") (pinfunction "P$1_P$626") (pintype "power_in"))
      (node (ref "P6") (pin "P$627") (pinfunction "P$1_P$627") (pintype "power_in"))
      (node (ref "P6") (pin "P$628") (pinfunction "P$1_P$628") (pintype "power_in"))
      (node (ref "P6") (pin "P$629") (pinfunction "P$1_P$629") (pintype "power_in"))
      (node (ref "P6") (pin "P$63") (pinfunction "P$1_P$63") (pintype "power_in"))
      (node (ref "P6") (pin "P$630") (pinfunction "P$1_P$630") (pintype "power_in"))
      (node (ref "P6") (pin "P$631") (pinfunction "P$1_P$631") (pintype "power_in"))
      (node (ref "P6") (pin "P$632") (pinfunction "P$1_P$632") (pintype "power_in"))
      (node (ref "P6") (pin "P$633") (pinfunction "P$1_P$633") (pintype "power_in"))
      (node (ref "P6") (pin "P$634") (pinfunction "P$1_P$634") (pintype "power_in"))
      (node (ref "P6") (pin "P$635") (pinfunction "P$1_P$635") (pintype "power_in"))
      (node (ref "P6") (pin "P$636") (pinfunction "P$1_P$636") (pintype "power_in"))
      (node (ref "P6") (pin "P$637") (pinfunction "P$1_P$637") (pintype "power_in"))
      (node (ref "P6") (pin "P$638") (pinfunction "P$1_P$638") (pintype "power_in"))
      (node (ref "P6") (pin "P$639") (pinfunction "P$1_P$639") (pintype "power_in"))
      (node (ref "P6") (pin "P$64") (pinfunction "P$1_P$64") (pintype "power_in"))
      (node (ref "P6") (pin "P$640") (pinfunction "P$1_P$640") (pintype "power_in"))
      (node (ref "P6") (pin "P$641") (pinfunction "P$1_P$641") (pintype "power_in"))
      (node (ref "P6") (pin "P$642") (pinfunction "P$1_P$642") (pintype "power_in"))
      (node (ref "P6") (pin "P$643") (pinfunction "P$1_P$643") (pintype "power_in"))
      (node (ref "P6") (pin "P$644") (pinfunction "P$1_P$644") (pintype "power_in"))
      (node (ref "P6") (pin "P$645") (pinfunction "P$1_P$645") (pintype "power_in"))
      (node (ref "P6") (pin "P$646") (pinfunction "P$1_P$646") (pintype "power_in"))
      (node (ref "P6") (pin "P$647") (pinfunction "P$1_P$647") (pintype "power_in"))
      (node (ref "P6") (pin "P$648") (pinfunction "P$1_P$648") (pintype "power_in"))
      (node (ref "P6") (pin "P$649") (pinfunction "P$1_P$649") (pintype "power_in"))
      (node (ref "P6") (pin "P$65") (pinfunction "P$1_P$65") (pintype "power_in"))
      (node (ref "P6") (pin "P$650") (pinfunction "P$1_P$650") (pintype "power_in"))
      (node (ref "P6") (pin "P$651") (pinfunction "P$1_P$651") (pintype "power_in"))
      (node (ref "P6") (pin "P$652") (pinfunction "P$1_P$652") (pintype "power_in"))
      (node (ref "P6") (pin "P$653") (pinfunction "P$1_P$653") (pintype "power_in"))
      (node (ref "P6") (pin "P$654") (pinfunction "P$1_P$654") (pintype "power_in"))
      (node (ref "P6") (pin "P$655") (pinfunction "P$1_P$655") (pintype "power_in"))
      (node (ref "P6") (pin "P$656") (pinfunction "P$1_P$656") (pintype "power_in"))
      (node (ref "P6") (pin "P$657") (pinfunction "P$1_P$657") (pintype "power_in"))
      (node (ref "P6") (pin "P$658") (pinfunction "P$1_P$658") (pintype "power_in"))
      (node (ref "P6") (pin "P$659") (pinfunction "P$1_P$659") (pintype "power_in"))
      (node (ref "P6") (pin "P$66") (pinfunction "P$1_P$66") (pintype "power_in"))
      (node (ref "P6") (pin "P$660") (pinfunction "P$1_P$660") (pintype "power_in"))
      (node (ref "P6") (pin "P$661") (pinfunction "P$1_P$661") (pintype "power_in"))
      (node (ref "P6") (pin "P$662") (pinfunction "P$1_P$662") (pintype "power_in"))
      (node (ref "P6") (pin "P$663") (pinfunction "P$1_P$663") (pintype "power_in"))
      (node (ref "P6") (pin "P$664") (pinfunction "P$1_P$664") (pintype "power_in"))
      (node (ref "P6") (pin "P$665") (pinfunction "P$1_P$665") (pintype "power_in"))
      (node (ref "P6") (pin "P$666") (pinfunction "P$1_P$666") (pintype "power_in"))
      (node (ref "P6") (pin "P$667") (pinfunction "P$1_P$667") (pintype "power_in"))
      (node (ref "P6") (pin "P$668") (pinfunction "P$1_P$668") (pintype "power_in"))
      (node (ref "P6") (pin "P$669") (pinfunction "P$1_P$669") (pintype "power_in"))
      (node (ref "P6") (pin "P$67") (pinfunction "P$1_P$67") (pintype "power_in"))
      (node (ref "P6") (pin "P$670") (pinfunction "P$1_P$670") (pintype "power_in"))
      (node (ref "P6") (pin "P$671") (pinfunction "P$1_P$671") (pintype "power_in"))
      (node (ref "P6") (pin "P$672") (pinfunction "P$1_P$672") (pintype "power_in"))
      (node (ref "P6") (pin "P$673") (pinfunction "P$1_P$673") (pintype "power_in"))
      (node (ref "P6") (pin "P$674") (pinfunction "P$1_P$674") (pintype "power_in"))
      (node (ref "P6") (pin "P$675") (pinfunction "P$1_P$675") (pintype "power_in"))
      (node (ref "P6") (pin "P$676") (pinfunction "P$1_P$676") (pintype "power_in"))
      (node (ref "P6") (pin "P$677") (pinfunction "P$1_P$677") (pintype "power_in"))
      (node (ref "P6") (pin "P$678") (pinfunction "P$1_P$678") (pintype "power_in"))
      (node (ref "P6") (pin "P$679") (pinfunction "P$1_P$679") (pintype "power_in"))
      (node (ref "P6") (pin "P$68") (pinfunction "P$1_P$68") (pintype "power_in"))
      (node (ref "P6") (pin "P$680") (pinfunction "P$1_P$680") (pintype "power_in"))
      (node (ref "P6") (pin "P$681") (pinfunction "P$1_P$681") (pintype "power_in"))
      (node (ref "P6") (pin "P$682") (pinfunction "P$1_P$682") (pintype "power_in"))
      (node (ref "P6") (pin "P$683") (pinfunction "P$1_P$683") (pintype "power_in"))
      (node (ref "P6") (pin "P$684") (pinfunction "P$1_P$684") (pintype "power_in"))
      (node (ref "P6") (pin "P$685") (pinfunction "P$1_P$685") (pintype "power_in"))
      (node (ref "P6") (pin "P$686") (pinfunction "P$1_P$686") (pintype "power_in"))
      (node (ref "P6") (pin "P$687") (pinfunction "P$1_P$687") (pintype "power_in"))
      (node (ref "P6") (pin "P$688") (pinfunction "P$1_P$688") (pintype "power_in"))
      (node (ref "P6") (pin "P$689") (pinfunction "P$1_P$689") (pintype "power_in"))
      (node (ref "P6") (pin "P$69") (pinfunction "P$1_P$69") (pintype "power_in"))
      (node (ref "P6") (pin "P$690") (pinfunction "P$1_P$690") (pintype "power_in"))
      (node (ref "P6") (pin "P$691") (pinfunction "P$1_P$691") (pintype "power_in"))
      (node (ref "P6") (pin "P$692") (pinfunction "P$1_P$692") (pintype "power_in"))
      (node (ref "P6") (pin "P$693") (pinfunction "P$1_P$693") (pintype "power_in"))
      (node (ref "P6") (pin "P$694") (pinfunction "P$1_P$694") (pintype "power_in"))
      (node (ref "P6") (pin "P$695") (pinfunction "P$1_P$695") (pintype "power_in"))
      (node (ref "P6") (pin "P$696") (pinfunction "P$1_P$696") (pintype "power_in"))
      (node (ref "P6") (pin "P$697") (pinfunction "P$1_P$697") (pintype "power_in"))
      (node (ref "P6") (pin "P$698") (pinfunction "P$1_P$698") (pintype "power_in"))
      (node (ref "P6") (pin "P$699") (pinfunction "P$1_P$699") (pintype "power_in"))
      (node (ref "P6") (pin "P$7") (pinfunction "P$1_P$7") (pintype "power_in"))
      (node (ref "P6") (pin "P$70") (pinfunction "P$1_P$70") (pintype "power_in"))
      (node (ref "P6") (pin "P$700") (pinfunction "P$1_P$700") (pintype "power_in"))
      (node (ref "P6") (pin "P$701") (pinfunction "P$1_P$701") (pintype "power_in"))
      (node (ref "P6") (pin "P$702") (pinfunction "P$1_P$702") (pintype "power_in"))
      (node (ref "P6") (pin "P$703") (pinfunction "P$1_P$703") (pintype "power_in"))
      (node (ref "P6") (pin "P$704") (pinfunction "P$1_P$704") (pintype "power_in"))
      (node (ref "P6") (pin "P$705") (pinfunction "P$1_P$705") (pintype "power_in"))
      (node (ref "P6") (pin "P$706") (pinfunction "P$1_P$706") (pintype "power_in"))
      (node (ref "P6") (pin "P$707") (pinfunction "P$1_P$707") (pintype "power_in"))
      (node (ref "P6") (pin "P$708") (pinfunction "P$1_P$708") (pintype "power_in"))
      (node (ref "P6") (pin "P$709") (pinfunction "P$1_P$709") (pintype "power_in"))
      (node (ref "P6") (pin "P$71") (pinfunction "P$1_P$71") (pintype "power_in"))
      (node (ref "P6") (pin "P$710") (pinfunction "P$1_P$710") (pintype "power_in"))
      (node (ref "P6") (pin "P$711") (pinfunction "P$1_P$711") (pintype "power_in"))
      (node (ref "P6") (pin "P$712") (pinfunction "P$1_P$712") (pintype "power_in"))
      (node (ref "P6") (pin "P$713") (pinfunction "P$1_P$713") (pintype "power_in"))
      (node (ref "P6") (pin "P$714") (pinfunction "P$1_P$714") (pintype "power_in"))
      (node (ref "P6") (pin "P$715") (pinfunction "P$1_P$715") (pintype "power_in"))
      (node (ref "P6") (pin "P$716") (pinfunction "P$1_P$716") (pintype "power_in"))
      (node (ref "P6") (pin "P$717") (pinfunction "P$1_P$717") (pintype "power_in"))
      (node (ref "P6") (pin "P$718") (pinfunction "P$1_P$718") (pintype "power_in"))
      (node (ref "P6") (pin "P$719") (pinfunction "P$1_P$719") (pintype "power_in"))
      (node (ref "P6") (pin "P$72") (pinfunction "P$1_P$72") (pintype "power_in"))
      (node (ref "P6") (pin "P$720") (pinfunction "P$1_P$720") (pintype "power_in"))
      (node (ref "P6") (pin "P$73") (pinfunction "P$1_P$73") (pintype "power_in"))
      (node (ref "P6") (pin "P$74") (pinfunction "P$1_P$74") (pintype "power_in"))
      (node (ref "P6") (pin "P$75") (pinfunction "P$1_P$75") (pintype "power_in"))
      (node (ref "P6") (pin "P$76") (pinfunction "P$1_P$76") (pintype "power_in"))
      (node (ref "P6") (pin "P$77") (pinfunction "P$1_P$77") (pintype "power_in"))
      (node (ref "P6") (pin "P$78") (pinfunction "P$1_P$78") (pintype "power_in"))
      (node (ref "P6") (pin "P$79") (pinfunction "P$1_P$79") (pintype "power_in"))
      (node (ref "P6") (pin "P$8") (pinfunction "P$1_P$8") (pintype "power_in"))
      (node (ref "P6") (pin "P$80") (pinfunction "P$1_P$80") (pintype "power_in"))
      (node (ref "P6") (pin "P$81") (pinfunction "P$1_P$81") (pintype "power_in"))
      (node (ref "P6") (pin "P$82") (pinfunction "P$1_P$82") (pintype "power_in"))
      (node (ref "P6") (pin "P$83") (pinfunction "P$1_P$83") (pintype "power_in"))
      (node (ref "P6") (pin "P$84") (pinfunction "P$1_P$84") (pintype "power_in"))
      (node (ref "P6") (pin "P$85") (pinfunction "P$1_P$85") (pintype "power_in"))
      (node (ref "P6") (pin "P$86") (pinfunction "P$1_P$86") (pintype "power_in"))
      (node (ref "P6") (pin "P$87") (pinfunction "P$1_P$87") (pintype "power_in"))
      (node (ref "P6") (pin "P$88") (pinfunction "P$1_P$88") (pintype "power_in"))
      (node (ref "P6") (pin "P$89") (pinfunction "P$1_P$89") (pintype "power_in"))
      (node (ref "P6") (pin "P$9") (pinfunction "P$1_P$9") (pintype "power_in"))
      (node (ref "P6") (pin "P$90") (pinfunction "P$1_P$90") (pintype "power_in"))
      (node (ref "P6") (pin "P$91") (pinfunction "P$1_P$91") (pintype "power_in"))
      (node (ref "P6") (pin "P$92") (pinfunction "P$1_P$92") (pintype "power_in"))
      (node (ref "P6") (pin "P$93") (pinfunction "P$1_P$93") (pintype "power_in"))
      (node (ref "P6") (pin "P$94") (pinfunction "P$1_P$94") (pintype "power_in"))
      (node (ref "P6") (pin "P$95") (pinfunction "P$1_P$95") (pintype "power_in"))
      (node (ref "P6") (pin "P$96") (pinfunction "P$1_P$96") (pintype "power_in"))
      (node (ref "P6") (pin "P$97") (pinfunction "P$1_P$97") (pintype "power_in"))
      (node (ref "P6") (pin "P$98") (pinfunction "P$1_P$98") (pintype "power_in"))
      (node (ref "P6") (pin "P$99") (pinfunction "P$1_P$99") (pintype "power_in"))
    )
    (net (code "9") (name "/P7") (class "Default")
      (node (ref "JP1") (pin "P$8") (pinfunction "7_P$8") (pintype "bidirectional"))
      (node (ref "P7") (pin "P$1") (pinfunction "P$1_P$1") (pintype "power_in"))
      (node (ref "P7") (pin "P$10") (pinfunction "P$1_P$10") (pintype "power_in"))
      (node (ref "P7") (pin "P$100") (pinfunction "P$1_P$100") (pintype "power_in"))
      (node (ref "P7") (pin "P$101") (pinfunction "P$1_P$101") (pintype "power_in"))
      (node (ref "P7") (pin "P$102") (pinfunction "P$1_P$102") (pintype "power_in"))
      (node (ref "P7") (pin "P$103") (pinfunction "P$1_P$103") (pintype "power_in"))
      (node (ref "P7") (pin "P$104") (pinfunction "P$1_P$104") (pintype "power_in"))
      (node (ref "P7") (pin "P$105") (pinfunction "P$1_P$105") (pintype "power_in"))
      (node (ref "P7") (pin "P$106") (pinfunction "P$1_P$106") (pintype "power_in"))
      (node (ref "P7") (pin "P$107") (pinfunction "P$1_P$107") (pintype "power_in"))
      (node (ref "P7") (pin "P$108") (pinfunction "P$1_P$108") (pintype "power_in"))
      (node (ref "P7") (pin "P$109") (pinfunction "P$1_P$109") (pintype "power_in"))
      (node (ref "P7") (pin "P$11") (pinfunction "P$1_P$11") (pintype "power_in"))
      (node (ref "P7") (pin "P$110") (pinfunction "P$1_P$110") (pintype "power_in"))
      (node (ref "P7") (pin "P$111") (pinfunction "P$1_P$111") (pintype "power_in"))
      (node (ref "P7") (pin "P$112") (pinfunction "P$1_P$112") (pintype "power_in"))
      (node (ref "P7") (pin "P$113") (pinfunction "P$1_P$113") (pintype "power_in"))
      (node (ref "P7") (pin "P$114") (pinfunction "P$1_P$114") (pintype "power_in"))
      (node (ref "P7") (pin "P$115") (pinfunction "P$1_P$115") (pintype "power_in"))
      (node (ref "P7") (pin "P$116") (pinfunction "P$1_P$116") (pintype "power_in"))
      (node (ref "P7") (pin "P$117") (pinfunction "P$1_P$117") (pintype "power_in"))
      (node (ref "P7") (pin "P$118") (pinfunction "P$1_P$118") (pintype "power_in"))
      (node (ref "P7") (pin "P$119") (pinfunction "P$1_P$119") (pintype "power_in"))
      (node (ref "P7") (pin "P$12") (pinfunction "P$1_P$12") (pintype "power_in"))
      (node (ref "P7") (pin "P$120") (pinfunction "P$1_P$120") (pintype "power_in"))
      (node (ref "P7") (pin "P$121") (pinfunction "P$1_P$121") (pintype "power_in"))
      (node (ref "P7") (pin "P$122") (pinfunction "P$1_P$122") (pintype "power_in"))
      (node (ref "P7") (pin "P$123") (pinfunction "P$1_P$123") (pintype "power_in"))
      (node (ref "P7") (pin "P$124") (pinfunction "P$1_P$124") (pintype "power_in"))
      (node (ref "P7") (pin "P$125") (pinfunction "P$1_P$125") (pintype "power_in"))
      (node (ref "P7") (pin "P$126") (pinfunction "P$1_P$126") (pintype "power_in"))
      (node (ref "P7") (pin "P$127") (pinfunction "P$1_P$127") (pintype "power_in"))
      (node (ref "P7") (pin "P$128") (pinfunction "P$1_P$128") (pintype "power_in"))
      (node (ref "P7") (pin "P$129") (pinfunction "P$1_P$129") (pintype "power_in"))
      (node (ref "P7") (pin "P$13") (pinfunction "P$1_P$13") (pintype "power_in"))
      (node (ref "P7") (pin "P$130") (pinfunction "P$1_P$130") (pintype "power_in"))
      (node (ref "P7") (pin "P$131") (pinfunction "P$1_P$131") (pintype "power_in"))
      (node (ref "P7") (pin "P$132") (pinfunction "P$1_P$132") (pintype "power_in"))
      (node (ref "P7") (pin "P$133") (pinfunction "P$1_P$133") (pintype "power_in"))
      (node (ref "P7") (pin "P$134") (pinfunction "P$1_P$134") (pintype "power_in"))
      (node (ref "P7") (pin "P$135") (pinfunction "P$1_P$135") (pintype "power_in"))
      (node (ref "P7") (pin "P$136") (pinfunction "P$1_P$136") (pintype "power_in"))
      (node (ref "P7") (pin "P$137") (pinfunction "P$1_P$137") (pintype "power_in"))
      (node (ref "P7") (pin "P$138") (pinfunction "P$1_P$138") (pintype "power_in"))
      (node (ref "P7") (pin "P$139") (pinfunction "P$1_P$139") (pintype "power_in"))
      (node (ref "P7") (pin "P$14") (pinfunction "P$1_P$14") (pintype "power_in"))
      (node (ref "P7") (pin "P$140") (pinfunction "P$1_P$140") (pintype "power_in"))
      (node (ref "P7") (pin "P$141") (pinfunction "P$1_P$141") (pintype "power_in"))
      (node (ref "P7") (pin "P$142") (pinfunction "P$1_P$142") (pintype "power_in"))
      (node (ref "P7") (pin "P$143") (pinfunction "P$1_P$143") (pintype "power_in"))
      (node (ref "P7") (pin "P$144") (pinfunction "P$1_P$144") (pintype "power_in"))
      (node (ref "P7") (pin "P$145") (pinfunction "P$1_P$145") (pintype "power_in"))
      (node (ref "P7") (pin "P$146") (pinfunction "P$1_P$146") (pintype "power_in"))
      (node (ref "P7") (pin "P$147") (pinfunction "P$1_P$147") (pintype "power_in"))
      (node (ref "P7") (pin "P$148") (pinfunction "P$1_P$148") (pintype "power_in"))
      (node (ref "P7") (pin "P$149") (pinfunction "P$1_P$149") (pintype "power_in"))
      (node (ref "P7") (pin "P$15") (pinfunction "P$1_P$15") (pintype "power_in"))
      (node (ref "P7") (pin "P$150") (pinfunction "P$1_P$150") (pintype "power_in"))
      (node (ref "P7") (pin "P$151") (pinfunction "P$1_P$151") (pintype "power_in"))
      (node (ref "P7") (pin "P$152") (pinfunction "P$1_P$152") (pintype "power_in"))
      (node (ref "P7") (pin "P$153") (pinfunction "P$1_P$153") (pintype "power_in"))
      (node (ref "P7") (pin "P$154") (pinfunction "P$1_P$154") (pintype "power_in"))
      (node (ref "P7") (pin "P$155") (pinfunction "P$1_P$155") (pintype "power_in"))
      (node (ref "P7") (pin "P$156") (pinfunction "P$1_P$156") (pintype "power_in"))
      (node (ref "P7") (pin "P$157") (pinfunction "P$1_P$157") (pintype "power_in"))
      (node (ref "P7") (pin "P$158") (pinfunction "P$1_P$158") (pintype "power_in"))
      (node (ref "P7") (pin "P$159") (pinfunction "P$1_P$159") (pintype "power_in"))
      (node (ref "P7") (pin "P$16") (pinfunction "P$1_P$16") (pintype "power_in"))
      (node (ref "P7") (pin "P$160") (pinfunction "P$1_P$160") (pintype "power_in"))
      (node (ref "P7") (pin "P$161") (pinfunction "P$1_P$161") (pintype "power_in"))
      (node (ref "P7") (pin "P$162") (pinfunction "P$1_P$162") (pintype "power_in"))
      (node (ref "P7") (pin "P$163") (pinfunction "P$1_P$163") (pintype "power_in"))
      (node (ref "P7") (pin "P$164") (pinfunction "P$1_P$164") (pintype "power_in"))
      (node (ref "P7") (pin "P$165") (pinfunction "P$1_P$165") (pintype "power_in"))
      (node (ref "P7") (pin "P$166") (pinfunction "P$1_P$166") (pintype "power_in"))
      (node (ref "P7") (pin "P$167") (pinfunction "P$1_P$167") (pintype "power_in"))
      (node (ref "P7") (pin "P$168") (pinfunction "P$1_P$168") (pintype "power_in"))
      (node (ref "P7") (pin "P$169") (pinfunction "P$1_P$169") (pintype "power_in"))
      (node (ref "P7") (pin "P$17") (pinfunction "P$1_P$17") (pintype "power_in"))
      (node (ref "P7") (pin "P$170") (pinfunction "P$1_P$170") (pintype "power_in"))
      (node (ref "P7") (pin "P$171") (pinfunction "P$1_P$171") (pintype "power_in"))
      (node (ref "P7") (pin "P$172") (pinfunction "P$1_P$172") (pintype "power_in"))
      (node (ref "P7") (pin "P$173") (pinfunction "P$1_P$173") (pintype "power_in"))
      (node (ref "P7") (pin "P$174") (pinfunction "P$1_P$174") (pintype "power_in"))
      (node (ref "P7") (pin "P$175") (pinfunction "P$1_P$175") (pintype "power_in"))
      (node (ref "P7") (pin "P$176") (pinfunction "P$1_P$176") (pintype "power_in"))
      (node (ref "P7") (pin "P$177") (pinfunction "P$1_P$177") (pintype "power_in"))
      (node (ref "P7") (pin "P$178") (pinfunction "P$1_P$178") (pintype "power_in"))
      (node (ref "P7") (pin "P$179") (pinfunction "P$1_P$179") (pintype "power_in"))
      (node (ref "P7") (pin "P$18") (pinfunction "P$1_P$18") (pintype "power_in"))
      (node (ref "P7") (pin "P$180") (pinfunction "P$1_P$180") (pintype "power_in"))
      (node (ref "P7") (pin "P$181") (pinfunction "P$1_P$181") (pintype "power_in"))
      (node (ref "P7") (pin "P$182") (pinfunction "P$1_P$182") (pintype "power_in"))
      (node (ref "P7") (pin "P$183") (pinfunction "P$1_P$183") (pintype "power_in"))
      (node (ref "P7") (pin "P$184") (pinfunction "P$1_P$184") (pintype "power_in"))
      (node (ref "P7") (pin "P$185") (pinfunction "P$1_P$185") (pintype "power_in"))
      (node (ref "P7") (pin "P$186") (pinfunction "P$1_P$186") (pintype "power_in"))
      (node (ref "P7") (pin "P$187") (pinfunction "P$1_P$187") (pintype "power_in"))
      (node (ref "P7") (pin "P$188") (pinfunction "P$1_P$188") (pintype "power_in"))
      (node (ref "P7") (pin "P$189") (pinfunction "P$1_P$189") (pintype "power_in"))
      (node (ref "P7") (pin "P$19") (pinfunction "P$1_P$19") (pintype "power_in"))
      (node (ref "P7") (pin "P$190") (pinfunction "P$1_P$190") (pintype "power_in"))
      (node (ref "P7") (pin "P$191") (pinfunction "P$1_P$191") (pintype "power_in"))
      (node (ref "P7") (pin "P$192") (pinfunction "P$1_P$192") (pintype "power_in"))
      (node (ref "P7") (pin "P$193") (pinfunction "P$1_P$193") (pintype "power_in"))
      (node (ref "P7") (pin "P$194") (pinfunction "P$1_P$194") (pintype "power_in"))
      (node (ref "P7") (pin "P$195") (pinfunction "P$1_P$195") (pintype "power_in"))
      (node (ref "P7") (pin "P$196") (pinfunction "P$1_P$196") (pintype "power_in"))
      (node (ref "P7") (pin "P$197") (pinfunction "P$1_P$197") (pintype "power_in"))
      (node (ref "P7") (pin "P$198") (pinfunction "P$1_P$198") (pintype "power_in"))
      (node (ref "P7") (pin "P$199") (pinfunction "P$1_P$199") (pintype "power_in"))
      (node (ref "P7") (pin "P$2") (pinfunction "P$1_P$2") (pintype "power_in"))
      (node (ref "P7") (pin "P$20") (pinfunction "P$1_P$20") (pintype "power_in"))
      (node (ref "P7") (pin "P$200") (pinfunction "P$1_P$200") (pintype "power_in"))
      (node (ref "P7") (pin "P$201") (pinfunction "P$1_P$201") (pintype "power_in"))
      (node (ref "P7") (pin "P$202") (pinfunction "P$1_P$202") (pintype "power_in"))
      (node (ref "P7") (pin "P$203") (pinfunction "P$1_P$203") (pintype "power_in"))
      (node (ref "P7") (pin "P$204") (pinfunction "P$1_P$204") (pintype "power_in"))
      (node (ref "P7") (pin "P$205") (pinfunction "P$1_P$205") (pintype "power_in"))
      (node (ref "P7") (pin "P$206") (pinfunction "P$1_P$206") (pintype "power_in"))
      (node (ref "P7") (pin "P$207") (pinfunction "P$1_P$207") (pintype "power_in"))
      (node (ref "P7") (pin "P$208") (pinfunction "P$1_P$208") (pintype "power_in"))
      (node (ref "P7") (pin "P$209") (pinfunction "P$1_P$209") (pintype "power_in"))
      (node (ref "P7") (pin "P$21") (pinfunction "P$1_P$21") (pintype "power_in"))
      (node (ref "P7") (pin "P$210") (pinfunction "P$1_P$210") (pintype "power_in"))
      (node (ref "P7") (pin "P$211") (pinfunction "P$1_P$211") (pintype "power_in"))
      (node (ref "P7") (pin "P$212") (pinfunction "P$1_P$212") (pintype "power_in"))
      (node (ref "P7") (pin "P$213") (pinfunction "P$1_P$213") (pintype "power_in"))
      (node (ref "P7") (pin "P$214") (pinfunction "P$1_P$214") (pintype "power_in"))
      (node (ref "P7") (pin "P$215") (pinfunction "P$1_P$215") (pintype "power_in"))
      (node (ref "P7") (pin "P$216") (pinfunction "P$1_P$216") (pintype "power_in"))
      (node (ref "P7") (pin "P$217") (pinfunction "P$1_P$217") (pintype "power_in"))
      (node (ref "P7") (pin "P$218") (pinfunction "P$1_P$218") (pintype "power_in"))
      (node (ref "P7") (pin "P$219") (pinfunction "P$1_P$219") (pintype "power_in"))
      (node (ref "P7") (pin "P$22") (pinfunction "P$1_P$22") (pintype "power_in"))
      (node (ref "P7") (pin "P$220") (pinfunction "P$1_P$220") (pintype "power_in"))
      (node (ref "P7") (pin "P$221") (pinfunction "P$1_P$221") (pintype "power_in"))
      (node (ref "P7") (pin "P$222") (pinfunction "P$1_P$222") (pintype "power_in"))
      (node (ref "P7") (pin "P$223") (pinfunction "P$1_P$223") (pintype "power_in"))
      (node (ref "P7") (pin "P$224") (pinfunction "P$1_P$224") (pintype "power_in"))
      (node (ref "P7") (pin "P$225") (pinfunction "P$1_P$225") (pintype "power_in"))
      (node (ref "P7") (pin "P$226") (pinfunction "P$1_P$226") (pintype "power_in"))
      (node (ref "P7") (pin "P$227") (pinfunction "P$1_P$227") (pintype "power_in"))
      (node (ref "P7") (pin "P$228") (pinfunction "P$1_P$228") (pintype "power_in"))
      (node (ref "P7") (pin "P$229") (pinfunction "P$1_P$229") (pintype "power_in"))
      (node (ref "P7") (pin "P$23") (pinfunction "P$1_P$23") (pintype "power_in"))
      (node (ref "P7") (pin "P$230") (pinfunction "P$1_P$230") (pintype "power_in"))
      (node (ref "P7") (pin "P$231") (pinfunction "P$1_P$231") (pintype "power_in"))
      (node (ref "P7") (pin "P$232") (pinfunction "P$1_P$232") (pintype "power_in"))
      (node (ref "P7") (pin "P$233") (pinfunction "P$1_P$233") (pintype "power_in"))
      (node (ref "P7") (pin "P$234") (pinfunction "P$1_P$234") (pintype "power_in"))
      (node (ref "P7") (pin "P$235") (pinfunction "P$1_P$235") (pintype "power_in"))
      (node (ref "P7") (pin "P$236") (pinfunction "P$1_P$236") (pintype "power_in"))
      (node (ref "P7") (pin "P$237") (pinfunction "P$1_P$237") (pintype "power_in"))
      (node (ref "P7") (pin "P$238") (pinfunction "P$1_P$238") (pintype "power_in"))
      (node (ref "P7") (pin "P$239") (pinfunction "P$1_P$239") (pintype "power_in"))
      (node (ref "P7") (pin "P$24") (pinfunction "P$1_P$24") (pintype "power_in"))
      (node (ref "P7") (pin "P$240") (pinfunction "P$1_P$240") (pintype "power_in"))
      (node (ref "P7") (pin "P$241") (pinfunction "P$1_P$241") (pintype "power_in"))
      (node (ref "P7") (pin "P$242") (pinfunction "P$1_P$242") (pintype "power_in"))
      (node (ref "P7") (pin "P$243") (pinfunction "P$1_P$243") (pintype "power_in"))
      (node (ref "P7") (pin "P$244") (pinfunction "P$1_P$244") (pintype "power_in"))
      (node (ref "P7") (pin "P$245") (pinfunction "P$1_P$245") (pintype "power_in"))
      (node (ref "P7") (pin "P$246") (pinfunction "P$1_P$246") (pintype "power_in"))
      (node (ref "P7") (pin "P$247") (pinfunction "P$1_P$247") (pintype "power_in"))
      (node (ref "P7") (pin "P$248") (pinfunction "P$1_P$248") (pintype "power_in"))
      (node (ref "P7") (pin "P$249") (pinfunction "P$1_P$249") (pintype "power_in"))
      (node (ref "P7") (pin "P$25") (pinfunction "P$1_P$25") (pintype "power_in"))
      (node (ref "P7") (pin "P$250") (pinfunction "P$1_P$250") (pintype "power_in"))
      (node (ref "P7") (pin "P$251") (pinfunction "P$1_P$251") (pintype "power_in"))
      (node (ref "P7") (pin "P$252") (pinfunction "P$1_P$252") (pintype "power_in"))
      (node (ref "P7") (pin "P$253") (pinfunction "P$1_P$253") (pintype "power_in"))
      (node (ref "P7") (pin "P$254") (pinfunction "P$1_P$254") (pintype "power_in"))
      (node (ref "P7") (pin "P$255") (pinfunction "P$1_P$255") (pintype "power_in"))
      (node (ref "P7") (pin "P$256") (pinfunction "P$1_P$256") (pintype "power_in"))
      (node (ref "P7") (pin "P$257") (pinfunction "P$1_P$257") (pintype "power_in"))
      (node (ref "P7") (pin "P$258") (pinfunction "P$1_P$258") (pintype "power_in"))
      (node (ref "P7") (pin "P$259") (pinfunction "P$1_P$259") (pintype "power_in"))
      (node (ref "P7") (pin "P$26") (pinfunction "P$1_P$26") (pintype "power_in"))
      (node (ref "P7") (pin "P$260") (pinfunction "P$1_P$260") (pintype "power_in"))
      (node (ref "P7") (pin "P$261") (pinfunction "P$1_P$261") (pintype "power_in"))
      (node (ref "P7") (pin "P$262") (pinfunction "P$1_P$262") (pintype "power_in"))
      (node (ref "P7") (pin "P$263") (pinfunction "P$1_P$263") (pintype "power_in"))
      (node (ref "P7") (pin "P$264") (pinfunction "P$1_P$264") (pintype "power_in"))
      (node (ref "P7") (pin "P$265") (pinfunction "P$1_P$265") (pintype "power_in"))
      (node (ref "P7") (pin "P$266") (pinfunction "P$1_P$266") (pintype "power_in"))
      (node (ref "P7") (pin "P$267") (pinfunction "P$1_P$267") (pintype "power_in"))
      (node (ref "P7") (pin "P$268") (pinfunction "P$1_P$268") (pintype "power_in"))
      (node (ref "P7") (pin "P$269") (pinfunction "P$1_P$269") (pintype "power_in"))
      (node (ref "P7") (pin "P$27") (pinfunction "P$1_P$27") (pintype "power_in"))
      (node (ref "P7") (pin "P$270") (pinfunction "P$1_P$270") (pintype "power_in"))
      (node (ref "P7") (pin "P$271") (pinfunction "P$1_P$271") (pintype "power_in"))
      (node (ref "P7") (pin "P$272") (pinfunction "P$1_P$272") (pintype "power_in"))
      (node (ref "P7") (pin "P$273") (pinfunction "P$1_P$273") (pintype "power_in"))
      (node (ref "P7") (pin "P$274") (pinfunction "P$1_P$274") (pintype "power_in"))
      (node (ref "P7") (pin "P$275") (pinfunction "P$1_P$275") (pintype "power_in"))
      (node (ref "P7") (pin "P$276") (pinfunction "P$1_P$276") (pintype "power_in"))
      (node (ref "P7") (pin "P$277") (pinfunction "P$1_P$277") (pintype "power_in"))
      (node (ref "P7") (pin "P$278") (pinfunction "P$1_P$278") (pintype "power_in"))
      (node (ref "P7") (pin "P$279") (pinfunction "P$1_P$279") (pintype "power_in"))
      (node (ref "P7") (pin "P$28") (pinfunction "P$1_P$28") (pintype "power_in"))
      (node (ref "P7") (pin "P$280") (pinfunction "P$1_P$280") (pintype "power_in"))
      (node (ref "P7") (pin "P$281") (pinfunction "P$1_P$281") (pintype "power_in"))
      (node (ref "P7") (pin "P$282") (pinfunction "P$1_P$282") (pintype "power_in"))
      (node (ref "P7") (pin "P$283") (pinfunction "P$1_P$283") (pintype "power_in"))
      (node (ref "P7") (pin "P$284") (pinfunction "P$1_P$284") (pintype "power_in"))
      (node (ref "P7") (pin "P$285") (pinfunction "P$1_P$285") (pintype "power_in"))
      (node (ref "P7") (pin "P$286") (pinfunction "P$1_P$286") (pintype "power_in"))
      (node (ref "P7") (pin "P$287") (pinfunction "P$1_P$287") (pintype "power_in"))
      (node (ref "P7") (pin "P$288") (pinfunction "P$1_P$288") (pintype "power_in"))
      (node (ref "P7") (pin "P$29") (pinfunction "P$1_P$29") (pintype "power_in"))
      (node (ref "P7") (pin "P$3") (pinfunction "P$1_P$3") (pintype "power_in"))
      (node (ref "P7") (pin "P$30") (pinfunction "P$1_P$30") (pintype "power_in"))
      (node (ref "P7") (pin "P$31") (pinfunction "P$1_P$31") (pintype "power_in"))
      (node (ref "P7") (pin "P$32") (pinfunction "P$1_P$32") (pintype "power_in"))
      (node (ref "P7") (pin "P$33") (pinfunction "P$1_P$33") (pintype "power_in"))
      (node (ref "P7") (pin "P$34") (pinfunction "P$1_P$34") (pintype "power_in"))
      (node (ref "P7") (pin "P$35") (pinfunction "P$1_P$35") (pintype "power_in"))
      (node (ref "P7") (pin "P$36") (pinfunction "P$1_P$36") (pintype "power_in"))
      (node (ref "P7") (pin "P$37") (pinfunction "P$1_P$37") (pintype "power_in"))
      (node (ref "P7") (pin "P$38") (pinfunction "P$1_P$38") (pintype "power_in"))
      (node (ref "P7") (pin "P$39") (pinfunction "P$1_P$39") (pintype "power_in"))
      (node (ref "P7") (pin "P$4") (pinfunction "P$1_P$4") (pintype "power_in"))
      (node (ref "P7") (pin "P$40") (pinfunction "P$1_P$40") (pintype "power_in"))
      (node (ref "P7") (pin "P$41") (pinfunction "P$1_P$41") (pintype "power_in"))
      (node (ref "P7") (pin "P$42") (pinfunction "P$1_P$42") (pintype "power_in"))
      (node (ref "P7") (pin "P$43") (pinfunction "P$1_P$43") (pintype "power_in"))
      (node (ref "P7") (pin "P$44") (pinfunction "P$1_P$44") (pintype "power_in"))
      (node (ref "P7") (pin "P$45") (pinfunction "P$1_P$45") (pintype "power_in"))
      (node (ref "P7") (pin "P$46") (pinfunction "P$1_P$46") (pintype "power_in"))
      (node (ref "P7") (pin "P$47") (pinfunction "P$1_P$47") (pintype "power_in"))
      (node (ref "P7") (pin "P$48") (pinfunction "P$1_P$48") (pintype "power_in"))
      (node (ref "P7") (pin "P$49") (pinfunction "P$1_P$49") (pintype "power_in"))
      (node (ref "P7") (pin "P$5") (pinfunction "P$1_P$5") (pintype "power_in"))
      (node (ref "P7") (pin "P$50") (pinfunction "P$1_P$50") (pintype "power_in"))
      (node (ref "P7") (pin "P$51") (pinfunction "P$1_P$51") (pintype "power_in"))
      (node (ref "P7") (pin "P$52") (pinfunction "P$1_P$52") (pintype "power_in"))
      (node (ref "P7") (pin "P$53") (pinfunction "P$1_P$53") (pintype "power_in"))
      (node (ref "P7") (pin "P$54") (pinfunction "P$1_P$54") (pintype "power_in"))
      (node (ref "P7") (pin "P$55") (pinfunction "P$1_P$55") (pintype "power_in"))
      (node (ref "P7") (pin "P$56") (pinfunction "P$1_P$56") (pintype "power_in"))
      (node (ref "P7") (pin "P$57") (pinfunction "P$1_P$57") (pintype "power_in"))
      (node (ref "P7") (pin "P$58") (pinfunction "P$1_P$58") (pintype "power_in"))
      (node (ref "P7") (pin "P$59") (pinfunction "P$1_P$59") (pintype "power_in"))
      (node (ref "P7") (pin "P$6") (pinfunction "P$1_P$6") (pintype "power_in"))
      (node (ref "P7") (pin "P$60") (pinfunction "P$1_P$60") (pintype "power_in"))
      (node (ref "P7") (pin "P$61") (pinfunction "P$1_P$61") (pintype "power_in"))
      (node (ref "P7") (pin "P$62") (pinfunction "P$1_P$62") (pintype "power_in"))
      (node (ref "P7") (pin "P$63") (pinfunction "P$1_P$63") (pintype "power_in"))
      (node (ref "P7") (pin "P$64") (pinfunction "P$1_P$64") (pintype "power_in"))
      (node (ref "P7") (pin "P$65") (pinfunction "P$1_P$65") (pintype "power_in"))
      (node (ref "P7") (pin "P$66") (pinfunction "P$1_P$66") (pintype "power_in"))
      (node (ref "P7") (pin "P$67") (pinfunction "P$1_P$67") (pintype "power_in"))
      (node (ref "P7") (pin "P$68") (pinfunction "P$1_P$68") (pintype "power_in"))
      (node (ref "P7") (pin "P$69") (pinfunction "P$1_P$69") (pintype "power_in"))
      (node (ref "P7") (pin "P$7") (pinfunction "P$1_P$7") (pintype "power_in"))
      (node (ref "P7") (pin "P$70") (pinfunction "P$1_P$70") (pintype "power_in"))
      (node (ref "P7") (pin "P$71") (pinfunction "P$1_P$71") (pintype "power_in"))
      (node (ref "P7") (pin "P$72") (pinfunction "P$1_P$72") (pintype "power_in"))
      (node (ref "P7") (pin "P$73") (pinfunction "P$1_P$73") (pintype "power_in"))
      (node (ref "P7") (pin "P$74") (pinfunction "P$1_P$74") (pintype "power_in"))
      (node (ref "P7") (pin "P$75") (pinfunction "P$1_P$75") (pintype "power_in"))
      (node (ref "P7") (pin "P$76") (pinfunction "P$1_P$76") (pintype "power_in"))
      (node (ref "P7") (pin "P$77") (pinfunction "P$1_P$77") (pintype "power_in"))
      (node (ref "P7") (pin "P$78") (pinfunction "P$1_P$78") (pintype "power_in"))
      (node (ref "P7") (pin "P$79") (pinfunction "P$1_P$79") (pintype "power_in"))
      (node (ref "P7") (pin "P$8") (pinfunction "P$1_P$8") (pintype "power_in"))
      (node (ref "P7") (pin "P$80") (pinfunction "P$1_P$80") (pintype "power_in"))
      (node (ref "P7") (pin "P$81") (pinfunction "P$1_P$81") (pintype "power_in"))
      (node (ref "P7") (pin "P$82") (pinfunction "P$1_P$82") (pintype "power_in"))
      (node (ref "P7") (pin "P$83") (pinfunction "P$1_P$83") (pintype "power_in"))
      (node (ref "P7") (pin "P$84") (pinfunction "P$1_P$84") (pintype "power_in"))
      (node (ref "P7") (pin "P$85") (pinfunction "P$1_P$85") (pintype "power_in"))
      (node (ref "P7") (pin "P$86") (pinfunction "P$1_P$86") (pintype "power_in"))
      (node (ref "P7") (pin "P$87") (pinfunction "P$1_P$87") (pintype "power_in"))
      (node (ref "P7") (pin "P$88") (pinfunction "P$1_P$88") (pintype "power_in"))
      (node (ref "P7") (pin "P$89") (pinfunction "P$1_P$89") (pintype "power_in"))
      (node (ref "P7") (pin "P$9") (pinfunction "P$1_P$9") (pintype "power_in"))
      (node (ref "P7") (pin "P$90") (pinfunction "P$1_P$90") (pintype "power_in"))
      (node (ref "P7") (pin "P$91") (pinfunction "P$1_P$91") (pintype "power_in"))
      (node (ref "P7") (pin "P$92") (pinfunction "P$1_P$92") (pintype "power_in"))
      (node (ref "P7") (pin "P$93") (pinfunction "P$1_P$93") (pintype "power_in"))
      (node (ref "P7") (pin "P$94") (pinfunction "P$1_P$94") (pintype "power_in"))
      (node (ref "P7") (pin "P$95") (pinfunction "P$1_P$95") (pintype "power_in"))
      (node (ref "P7") (pin "P$96") (pinfunction "P$1_P$96") (pintype "power_in"))
      (node (ref "P7") (pin "P$97") (pinfunction "P$1_P$97") (pintype "power_in"))
      (node (ref "P7") (pin "P$98") (pinfunction "P$1_P$98") (pintype "power_in"))
      (node (ref "P7") (pin "P$99") (pinfunction "P$1_P$99") (pintype "power_in"))
    )
    (net (code "10") (name "/P8") (class "Default")
      (node (ref "JP1") (pin "P$9") (pinfunction "8_P$9") (pintype "bidirectional"))
      (node (ref "P8") (pin "P$1") (pinfunction "P$1_P$1") (pintype "power_in"))
      (node (ref "P8") (pin "P$10") (pinfunction "P$1_P$10") (pintype "power_in"))
      (node (ref "P8") (pin "P$100") (pinfunction "P$1_P$100") (pintype "power_in"))
      (node (ref "P8") (pin "P$101") (pinfunction "P$1_P$101") (pintype "power_in"))
      (node (ref "P8") (pin "P$102") (pinfunction "P$1_P$102") (pintype "power_in"))
      (node (ref "P8") (pin "P$103") (pinfunction "P$1_P$103") (pintype "power_in"))
      (node (ref "P8") (pin "P$104") (pinfunction "P$1_P$104") (pintype "power_in"))
      (node (ref "P8") (pin "P$105") (pinfunction "P$1_P$105") (pintype "power_in"))
      (node (ref "P8") (pin "P$106") (pinfunction "P$1_P$106") (pintype "power_in"))
      (node (ref "P8") (pin "P$107") (pinfunction "P$1_P$107") (pintype "power_in"))
      (node (ref "P8") (pin "P$108") (pinfunction "P$1_P$108") (pintype "power_in"))
      (node (ref "P8") (pin "P$109") (pinfunction "P$1_P$109") (pintype "power_in"))
      (node (ref "P8") (pin "P$11") (pinfunction "P$1_P$11") (pintype "power_in"))
      (node (ref "P8") (pin "P$110") (pinfunction "P$1_P$110") (pintype "power_in"))
      (node (ref "P8") (pin "P$111") (pinfunction "P$1_P$111") (pintype "power_in"))
      (node (ref "P8") (pin "P$112") (pinfunction "P$1_P$112") (pintype "power_in"))
      (node (ref "P8") (pin "P$113") (pinfunction "P$1_P$113") (pintype "power_in"))
      (node (ref "P8") (pin "P$114") (pinfunction "P$1_P$114") (pintype "power_in"))
      (node (ref "P8") (pin "P$115") (pinfunction "P$1_P$115") (pintype "power_in"))
      (node (ref "P8") (pin "P$116") (pinfunction "P$1_P$116") (pintype "power_in"))
      (node (ref "P8") (pin "P$117") (pinfunction "P$1_P$117") (pintype "power_in"))
      (node (ref "P8") (pin "P$118") (pinfunction "P$1_P$118") (pintype "power_in"))
      (node (ref "P8") (pin "P$119") (pinfunction "P$1_P$119") (pintype "power_in"))
      (node (ref "P8") (pin "P$12") (pinfunction "P$1_P$12") (pintype "power_in"))
      (node (ref "P8") (pin "P$120") (pinfunction "P$1_P$120") (pintype "power_in"))
      (node (ref "P8") (pin "P$121") (pinfunction "P$1_P$121") (pintype "power_in"))
      (node (ref "P8") (pin "P$122") (pinfunction "P$1_P$122") (pintype "power_in"))
      (node (ref "P8") (pin "P$123") (pinfunction "P$1_P$123") (pintype "power_in"))
      (node (ref "P8") (pin "P$124") (pinfunction "P$1_P$124") (pintype "power_in"))
      (node (ref "P8") (pin "P$125") (pinfunction "P$1_P$125") (pintype "power_in"))
      (node (ref "P8") (pin "P$126") (pinfunction "P$1_P$126") (pintype "power_in"))
      (node (ref "P8") (pin "P$127") (pinfunction "P$1_P$127") (pintype "power_in"))
      (node (ref "P8") (pin "P$128") (pinfunction "P$1_P$128") (pintype "power_in"))
      (node (ref "P8") (pin "P$129") (pinfunction "P$1_P$129") (pintype "power_in"))
      (node (ref "P8") (pin "P$13") (pinfunction "P$1_P$13") (pintype "power_in"))
      (node (ref "P8") (pin "P$130") (pinfunction "P$1_P$130") (pintype "power_in"))
      (node (ref "P8") (pin "P$131") (pinfunction "P$1_P$131") (pintype "power_in"))
      (node (ref "P8") (pin "P$132") (pinfunction "P$1_P$132") (pintype "power_in"))
      (node (ref "P8") (pin "P$133") (pinfunction "P$1_P$133") (pintype "power_in"))
      (node (ref "P8") (pin "P$134") (pinfunction "P$1_P$134") (pintype "power_in"))
      (node (ref "P8") (pin "P$135") (pinfunction "P$1_P$135") (pintype "power_in"))
      (node (ref "P8") (pin "P$136") (pinfunction "P$1_P$136") (pintype "power_in"))
      (node (ref "P8") (pin "P$137") (pinfunction "P$1_P$137") (pintype "power_in"))
      (node (ref "P8") (pin "P$138") (pinfunction "P$1_P$138") (pintype "power_in"))
      (node (ref "P8") (pin "P$139") (pinfunction "P$1_P$139") (pintype "power_in"))
      (node (ref "P8") (pin "P$14") (pinfunction "P$1_P$14") (pintype "power_in"))
      (node (ref "P8") (pin "P$140") (pinfunction "P$1_P$140") (pintype "power_in"))
      (node (ref "P8") (pin "P$141") (pinfunction "P$1_P$141") (pintype "power_in"))
      (node (ref "P8") (pin "P$142") (pinfunction "P$1_P$142") (pintype "power_in"))
      (node (ref "P8") (pin "P$143") (pinfunction "P$1_P$143") (pintype "power_in"))
      (node (ref "P8") (pin "P$144") (pinfunction "P$1_P$144") (pintype "power_in"))
      (node (ref "P8") (pin "P$145") (pinfunction "P$1_P$145") (pintype "power_in"))
      (node (ref "P8") (pin "P$146") (pinfunction "P$1_P$146") (pintype "power_in"))
      (node (ref "P8") (pin "P$147") (pinfunction "P$1_P$147") (pintype "power_in"))
      (node (ref "P8") (pin "P$148") (pinfunction "P$1_P$148") (pintype "power_in"))
      (node (ref "P8") (pin "P$149") (pinfunction "P$1_P$149") (pintype "power_in"))
      (node (ref "P8") (pin "P$15") (pinfunction "P$1_P$15") (pintype "power_in"))
      (node (ref "P8") (pin "P$150") (pinfunction "P$1_P$150") (pintype "power_in"))
      (node (ref "P8") (pin "P$151") (pinfunction "P$1_P$151") (pintype "power_in"))
      (node (ref "P8") (pin "P$152") (pinfunction "P$1_P$152") (pintype "power_in"))
      (node (ref "P8") (pin "P$153") (pinfunction "P$1_P$153") (pintype "power_in"))
      (node (ref "P8") (pin "P$154") (pinfunction "P$1_P$154") (pintype "power_in"))
      (node (ref "P8") (pin "P$155") (pinfunction "P$1_P$155") (pintype "power_in"))
      (node (ref "P8") (pin "P$156") (pinfunction "P$1_P$156") (pintype "power_in"))
      (node (ref "P8") (pin "P$157") (pinfunction "P$1_P$157") (pintype "power_in"))
      (node (ref "P8") (pin "P$158") (pinfunction "P$1_P$158") (pintype "power_in"))
      (node (ref "P8") (pin "P$159") (pinfunction "P$1_P$159") (pintype "power_in"))
      (node (ref "P8") (pin "P$16") (pinfunction "P$1_P$16") (pintype "power_in"))
      (node (ref "P8") (pin "P$160") (pinfunction "P$1_P$160") (pintype "power_in"))
      (node (ref "P8") (pin "P$161") (pinfunction "P$1_P$161") (pintype "power_in"))
      (node (ref "P8") (pin "P$162") (pinfunction "P$1_P$162") (pintype "power_in"))
      (node (ref "P8") (pin "P$163") (pinfunction "P$1_P$163") (pintype "power_in"))
      (node (ref "P8") (pin "P$164") (pinfunction "P$1_P$164") (pintype "power_in"))
      (node (ref "P8") (pin "P$165") (pinfunction "P$1_P$165") (pintype "power_in"))
      (node (ref "P8") (pin "P$166") (pinfunction "P$1_P$166") (pintype "power_in"))
      (node (ref "P8") (pin "P$167") (pinfunction "P$1_P$167") (pintype "power_in"))
      (node (ref "P8") (pin "P$168") (pinfunction "P$1_P$168") (pintype "power_in"))
      (node (ref "P8") (pin "P$169") (pinfunction "P$1_P$169") (pintype "power_in"))
      (node (ref "P8") (pin "P$17") (pinfunction "P$1_P$17") (pintype "power_in"))
      (node (ref "P8") (pin "P$170") (pinfunction "P$1_P$170") (pintype "power_in"))
      (node (ref "P8") (pin "P$171") (pinfunction "P$1_P$171") (pintype "power_in"))
      (node (ref "P8") (pin "P$172") (pinfunction "P$1_P$172") (pintype "power_in"))
      (node (ref "P8") (pin "P$173") (pinfunction "P$1_P$173") (pintype "power_in"))
      (node (ref "P8") (pin "P$174") (pinfunction "P$1_P$174") (pintype "power_in"))
      (node (ref "P8") (pin "P$175") (pinfunction "P$1_P$175") (pintype "power_in"))
      (node (ref "P8") (pin "P$176") (pinfunction "P$1_P$176") (pintype "power_in"))
      (node (ref "P8") (pin "P$177") (pinfunction "P$1_P$177") (pintype "power_in"))
      (node (ref "P8") (pin "P$178") (pinfunction "P$1_P$178") (pintype "power_in"))
      (node (ref "P8") (pin "P$179") (pinfunction "P$1_P$179") (pintype "power_in"))
      (node (ref "P8") (pin "P$18") (pinfunction "P$1_P$18") (pintype "power_in"))
      (node (ref "P8") (pin "P$180") (pinfunction "P$1_P$180") (pintype "power_in"))
      (node (ref "P8") (pin "P$181") (pinfunction "P$1_P$181") (pintype "power_in"))
      (node (ref "P8") (pin "P$182") (pinfunction "P$1_P$182") (pintype "power_in"))
      (node (ref "P8") (pin "P$183") (pinfunction "P$1_P$183") (pintype "power_in"))
      (node (ref "P8") (pin "P$184") (pinfunction "P$1_P$184") (pintype "power_in"))
      (node (ref "P8") (pin "P$185") (pinfunction "P$1_P$185") (pintype "power_in"))
      (node (ref "P8") (pin "P$186") (pinfunction "P$1_P$186") (pintype "power_in"))
      (node (ref "P8") (pin "P$187") (pinfunction "P$1_P$187") (pintype "power_in"))
      (node (ref "P8") (pin "P$188") (pinfunction "P$1_P$188") (pintype "power_in"))
      (node (ref "P8") (pin "P$189") (pinfunction "P$1_P$189") (pintype "power_in"))
      (node (ref "P8") (pin "P$19") (pinfunction "P$1_P$19") (pintype "power_in"))
      (node (ref "P8") (pin "P$190") (pinfunction "P$1_P$190") (pintype "power_in"))
      (node (ref "P8") (pin "P$191") (pinfunction "P$1_P$191") (pintype "power_in"))
      (node (ref "P8") (pin "P$192") (pinfunction "P$1_P$192") (pintype "power_in"))
      (node (ref "P8") (pin "P$193") (pinfunction "P$1_P$193") (pintype "power_in"))
      (node (ref "P8") (pin "P$194") (pinfunction "P$1_P$194") (pintype "power_in"))
      (node (ref "P8") (pin "P$195") (pinfunction "P$1_P$195") (pintype "power_in"))
      (node (ref "P8") (pin "P$196") (pinfunction "P$1_P$196") (pintype "power_in"))
      (node (ref "P8") (pin "P$197") (pinfunction "P$1_P$197") (pintype "power_in"))
      (node (ref "P8") (pin "P$198") (pinfunction "P$1_P$198") (pintype "power_in"))
      (node (ref "P8") (pin "P$199") (pinfunction "P$1_P$199") (pintype "power_in"))
      (node (ref "P8") (pin "P$2") (pinfunction "P$1_P$2") (pintype "power_in"))
      (node (ref "P8") (pin "P$20") (pinfunction "P$1_P$20") (pintype "power_in"))
      (node (ref "P8") (pin "P$200") (pinfunction "P$1_P$200") (pintype "power_in"))
      (node (ref "P8") (pin "P$201") (pinfunction "P$1_P$201") (pintype "power_in"))
      (node (ref "P8") (pin "P$202") (pinfunction "P$1_P$202") (pintype "power_in"))
      (node (ref "P8") (pin "P$203") (pinfunction "P$1_P$203") (pintype "power_in"))
      (node (ref "P8") (pin "P$204") (pinfunction "P$1_P$204") (pintype "power_in"))
      (node (ref "P8") (pin "P$205") (pinfunction "P$1_P$205") (pintype "power_in"))
      (node (ref "P8") (pin "P$206") (pinfunction "P$1_P$206") (pintype "power_in"))
      (node (ref "P8") (pin "P$207") (pinfunction "P$1_P$207") (pintype "power_in"))
      (node (ref "P8") (pin "P$208") (pinfunction "P$1_P$208") (pintype "power_in"))
      (node (ref "P8") (pin "P$209") (pinfunction "P$1_P$209") (pintype "power_in"))
      (node (ref "P8") (pin "P$21") (pinfunction "P$1_P$21") (pintype "power_in"))
      (node (ref "P8") (pin "P$210") (pinfunction "P$1_P$210") (pintype "power_in"))
      (node (ref "P8") (pin "P$211") (pinfunction "P$1_P$211") (pintype "power_in"))
      (node (ref "P8") (pin "P$212") (pinfunction "P$1_P$212") (pintype "power_in"))
      (node (ref "P8") (pin "P$213") (pinfunction "P$1_P$213") (pintype "power_in"))
      (node (ref "P8") (pin "P$214") (pinfunction "P$1_P$214") (pintype "power_in"))
      (node (ref "P8") (pin "P$215") (pinfunction "P$1_P$215") (pintype "power_in"))
      (node (ref "P8") (pin "P$216") (pinfunction "P$1_P$216") (pintype "power_in"))
      (node (ref "P8") (pin "P$217") (pinfunction "P$1_P$217") (pintype "power_in"))
      (node (ref "P8") (pin "P$218") (pinfunction "P$1_P$218") (pintype "power_in"))
      (node (ref "P8") (pin "P$219") (pinfunction "P$1_P$219") (pintype "power_in"))
      (node (ref "P8") (pin "P$22") (pinfunction "P$1_P$22") (pintype "power_in"))
      (node (ref "P8") (pin "P$220") (pinfunction "P$1_P$220") (pintype "power_in"))
      (node (ref "P8") (pin "P$221") (pinfunction "P$1_P$221") (pintype "power_in"))
      (node (ref "P8") (pin "P$222") (pinfunction "P$1_P$222") (pintype "power_in"))
      (node (ref "P8") (pin "P$223") (pinfunction "P$1_P$223") (pintype "power_in"))
      (node (ref "P8") (pin "P$224") (pinfunction "P$1_P$224") (pintype "power_in"))
      (node (ref "P8") (pin "P$225") (pinfunction "P$1_P$225") (pintype "power_in"))
      (node (ref "P8") (pin "P$226") (pinfunction "P$1_P$226") (pintype "power_in"))
      (node (ref "P8") (pin "P$227") (pinfunction "P$1_P$227") (pintype "power_in"))
      (node (ref "P8") (pin "P$228") (pinfunction "P$1_P$228") (pintype "power_in"))
      (node (ref "P8") (pin "P$229") (pinfunction "P$1_P$229") (pintype "power_in"))
      (node (ref "P8") (pin "P$23") (pinfunction "P$1_P$23") (pintype "power_in"))
      (node (ref "P8") (pin "P$230") (pinfunction "P$1_P$230") (pintype "power_in"))
      (node (ref "P8") (pin "P$231") (pinfunction "P$1_P$231") (pintype "power_in"))
      (node (ref "P8") (pin "P$232") (pinfunction "P$1_P$232") (pintype "power_in"))
      (node (ref "P8") (pin "P$233") (pinfunction "P$1_P$233") (pintype "power_in"))
      (node (ref "P8") (pin "P$234") (pinfunction "P$1_P$234") (pintype "power_in"))
      (node (ref "P8") (pin "P$235") (pinfunction "P$1_P$235") (pintype "power_in"))
      (node (ref "P8") (pin "P$236") (pinfunction "P$1_P$236") (pintype "power_in"))
      (node (ref "P8") (pin "P$237") (pinfunction "P$1_P$237") (pintype "power_in"))
      (node (ref "P8") (pin "P$238") (pinfunction "P$1_P$238") (pintype "power_in"))
      (node (ref "P8") (pin "P$239") (pinfunction "P$1_P$239") (pintype "power_in"))
      (node (ref "P8") (pin "P$24") (pinfunction "P$1_P$24") (pintype "power_in"))
      (node (ref "P8") (pin "P$240") (pinfunction "P$1_P$240") (pintype "power_in"))
      (node (ref "P8") (pin "P$241") (pinfunction "P$1_P$241") (pintype "power_in"))
      (node (ref "P8") (pin "P$242") (pinfunction "P$1_P$242") (pintype "power_in"))
      (node (ref "P8") (pin "P$243") (pinfunction "P$1_P$243") (pintype "power_in"))
      (node (ref "P8") (pin "P$244") (pinfunction "P$1_P$244") (pintype "power_in"))
      (node (ref "P8") (pin "P$245") (pinfunction "P$1_P$245") (pintype "power_in"))
      (node (ref "P8") (pin "P$246") (pinfunction "P$1_P$246") (pintype "power_in"))
      (node (ref "P8") (pin "P$247") (pinfunction "P$1_P$247") (pintype "power_in"))
      (node (ref "P8") (pin "P$248") (pinfunction "P$1_P$248") (pintype "power_in"))
      (node (ref "P8") (pin "P$249") (pinfunction "P$1_P$249") (pintype "power_in"))
      (node (ref "P8") (pin "P$25") (pinfunction "P$1_P$25") (pintype "power_in"))
      (node (ref "P8") (pin "P$250") (pinfunction "P$1_P$250") (pintype "power_in"))
      (node (ref "P8") (pin "P$251") (pinfunction "P$1_P$251") (pintype "power_in"))
      (node (ref "P8") (pin "P$252") (pinfunction "P$1_P$252") (pintype "power_in"))
      (node (ref "P8") (pin "P$253") (pinfunction "P$1_P$253") (pintype "power_in"))
      (node (ref "P8") (pin "P$254") (pinfunction "P$1_P$254") (pintype "power_in"))
      (node (ref "P8") (pin "P$255") (pinfunction "P$1_P$255") (pintype "power_in"))
      (node (ref "P8") (pin "P$256") (pinfunction "P$1_P$256") (pintype "power_in"))
      (node (ref "P8") (pin "P$257") (pinfunction "P$1_P$257") (pintype "power_in"))
      (node (ref "P8") (pin "P$258") (pinfunction "P$1_P$258") (pintype "power_in"))
      (node (ref "P8") (pin "P$259") (pinfunction "P$1_P$259") (pintype "power_in"))
      (node (ref "P8") (pin "P$26") (pinfunction "P$1_P$26") (pintype "power_in"))
      (node (ref "P8") (pin "P$260") (pinfunction "P$1_P$260") (pintype "power_in"))
      (node (ref "P8") (pin "P$261") (pinfunction "P$1_P$261") (pintype "power_in"))
      (node (ref "P8") (pin "P$262") (pinfunction "P$1_P$262") (pintype "power_in"))
      (node (ref "P8") (pin "P$263") (pinfunction "P$1_P$263") (pintype "power_in"))
      (node (ref "P8") (pin "P$264") (pinfunction "P$1_P$264") (pintype "power_in"))
      (node (ref "P8") (pin "P$265") (pinfunction "P$1_P$265") (pintype "power_in"))
      (node (ref "P8") (pin "P$266") (pinfunction "P$1_P$266") (pintype "power_in"))
      (node (ref "P8") (pin "P$267") (pinfunction "P$1_P$267") (pintype "power_in"))
      (node (ref "P8") (pin "P$268") (pinfunction "P$1_P$268") (pintype "power_in"))
      (node (ref "P8") (pin "P$269") (pinfunction "P$1_P$269") (pintype "power_in"))
      (node (ref "P8") (pin "P$27") (pinfunction "P$1_P$27") (pintype "power_in"))
      (node (ref "P8") (pin "P$270") (pinfunction "P$1_P$270") (pintype "power_in"))
      (node (ref "P8") (pin "P$271") (pinfunction "P$1_P$271") (pintype "power_in"))
      (node (ref "P8") (pin "P$272") (pinfunction "P$1_P$272") (pintype "power_in"))
      (node (ref "P8") (pin "P$273") (pinfunction "P$1_P$273") (pintype "power_in"))
      (node (ref "P8") (pin "P$274") (pinfunction "P$1_P$274") (pintype "power_in"))
      (node (ref "P8") (pin "P$275") (pinfunction "P$1_P$275") (pintype "power_in"))
      (node (ref "P8") (pin "P$276") (pinfunction "P$1_P$276") (pintype "power_in"))
      (node (ref "P8") (pin "P$277") (pinfunction "P$1_P$277") (pintype "power_in"))
      (node (ref "P8") (pin "P$278") (pinfunction "P$1_P$278") (pintype "power_in"))
      (node (ref "P8") (pin "P$279") (pinfunction "P$1_P$279") (pintype "power_in"))
      (node (ref "P8") (pin "P$28") (pinfunction "P$1_P$28") (pintype "power_in"))
      (node (ref "P8") (pin "P$280") (pinfunction "P$1_P$280") (pintype "power_in"))
      (node (ref "P8") (pin "P$281") (pinfunction "P$1_P$281") (pintype "power_in"))
      (node (ref "P8") (pin "P$282") (pinfunction "P$1_P$282") (pintype "power_in"))
      (node (ref "P8") (pin "P$283") (pinfunction "P$1_P$283") (pintype "power_in"))
      (node (ref "P8") (pin "P$284") (pinfunction "P$1_P$284") (pintype "power_in"))
      (node (ref "P8") (pin "P$285") (pinfunction "P$1_P$285") (pintype "power_in"))
      (node (ref "P8") (pin "P$286") (pinfunction "P$1_P$286") (pintype "power_in"))
      (node (ref "P8") (pin "P$287") (pinfunction "P$1_P$287") (pintype "power_in"))
      (node (ref "P8") (pin "P$288") (pinfunction "P$1_P$288") (pintype "power_in"))
      (node (ref "P8") (pin "P$29") (pinfunction "P$1_P$29") (pintype "power_in"))
      (node (ref "P8") (pin "P$3") (pinfunction "P$1_P$3") (pintype "power_in"))
      (node (ref "P8") (pin "P$30") (pinfunction "P$1_P$30") (pintype "power_in"))
      (node (ref "P8") (pin "P$31") (pinfunction "P$1_P$31") (pintype "power_in"))
      (node (ref "P8") (pin "P$32") (pinfunction "P$1_P$32") (pintype "power_in"))
      (node (ref "P8") (pin "P$33") (pinfunction "P$1_P$33") (pintype "power_in"))
      (node (ref "P8") (pin "P$34") (pinfunction "P$1_P$34") (pintype "power_in"))
      (node (ref "P8") (pin "P$35") (pinfunction "P$1_P$35") (pintype "power_in"))
      (node (ref "P8") (pin "P$36") (pinfunction "P$1_P$36") (pintype "power_in"))
      (node (ref "P8") (pin "P$37") (pinfunction "P$1_P$37") (pintype "power_in"))
      (node (ref "P8") (pin "P$38") (pinfunction "P$1_P$38") (pintype "power_in"))
      (node (ref "P8") (pin "P$39") (pinfunction "P$1_P$39") (pintype "power_in"))
      (node (ref "P8") (pin "P$4") (pinfunction "P$1_P$4") (pintype "power_in"))
      (node (ref "P8") (pin "P$40") (pinfunction "P$1_P$40") (pintype "power_in"))
      (node (ref "P8") (pin "P$41") (pinfunction "P$1_P$41") (pintype "power_in"))
      (node (ref "P8") (pin "P$42") (pinfunction "P$1_P$42") (pintype "power_in"))
      (node (ref "P8") (pin "P$43") (pinfunction "P$1_P$43") (pintype "power_in"))
      (node (ref "P8") (pin "P$44") (pinfunction "P$1_P$44") (pintype "power_in"))
      (node (ref "P8") (pin "P$45") (pinfunction "P$1_P$45") (pintype "power_in"))
      (node (ref "P8") (pin "P$46") (pinfunction "P$1_P$46") (pintype "power_in"))
      (node (ref "P8") (pin "P$47") (pinfunction "P$1_P$47") (pintype "power_in"))
      (node (ref "P8") (pin "P$48") (pinfunction "P$1_P$48") (pintype "power_in"))
      (node (ref "P8") (pin "P$49") (pinfunction "P$1_P$49") (pintype "power_in"))
      (node (ref "P8") (pin "P$5") (pinfunction "P$1_P$5") (pintype "power_in"))
      (node (ref "P8") (pin "P$50") (pinfunction "P$1_P$50") (pintype "power_in"))
      (node (ref "P8") (pin "P$51") (pinfunction "P$1_P$51") (pintype "power_in"))
      (node (ref "P8") (pin "P$52") (pinfunction "P$1_P$52") (pintype "power_in"))
      (node (ref "P8") (pin "P$53") (pinfunction "P$1_P$53") (pintype "power_in"))
      (node (ref "P8") (pin "P$54") (pinfunction "P$1_P$54") (pintype "power_in"))
      (node (ref "P8") (pin "P$55") (pinfunction "P$1_P$55") (pintype "power_in"))
      (node (ref "P8") (pin "P$56") (pinfunction "P$1_P$56") (pintype "power_in"))
      (node (ref "P8") (pin "P$57") (pinfunction "P$1_P$57") (pintype "power_in"))
      (node (ref "P8") (pin "P$58") (pinfunction "P$1_P$58") (pintype "power_in"))
      (node (ref "P8") (pin "P$59") (pinfunction "P$1_P$59") (pintype "power_in"))
      (node (ref "P8") (pin "P$6") (pinfunction "P$1_P$6") (pintype "power_in"))
      (node (ref "P8") (pin "P$60") (pinfunction "P$1_P$60") (pintype "power_in"))
      (node (ref "P8") (pin "P$61") (pinfunction "P$1_P$61") (pintype "power_in"))
      (node (ref "P8") (pin "P$62") (pinfunction "P$1_P$62") (pintype "power_in"))
      (node (ref "P8") (pin "P$63") (pinfunction "P$1_P$63") (pintype "power_in"))
      (node (ref "P8") (pin "P$64") (pinfunction "P$1_P$64") (pintype "power_in"))
      (node (ref "P8") (pin "P$65") (pinfunction "P$1_P$65") (pintype "power_in"))
      (node (ref "P8") (pin "P$66") (pinfunction "P$1_P$66") (pintype "power_in"))
      (node (ref "P8") (pin "P$67") (pinfunction "P$1_P$67") (pintype "power_in"))
      (node (ref "P8") (pin "P$68") (pinfunction "P$1_P$68") (pintype "power_in"))
      (node (ref "P8") (pin "P$69") (pinfunction "P$1_P$69") (pintype "power_in"))
      (node (ref "P8") (pin "P$7") (pinfunction "P$1_P$7") (pintype "power_in"))
      (node (ref "P8") (pin "P$70") (pinfunction "P$1_P$70") (pintype "power_in"))
      (node (ref "P8") (pin "P$71") (pinfunction "P$1_P$71") (pintype "power_in"))
      (node (ref "P8") (pin "P$72") (pinfunction "P$1_P$72") (pintype "power_in"))
      (node (ref "P8") (pin "P$73") (pinfunction "P$1_P$73") (pintype "power_in"))
      (node (ref "P8") (pin "P$74") (pinfunction "P$1_P$74") (pintype "power_in"))
      (node (ref "P8") (pin "P$75") (pinfunction "P$1_P$75") (pintype "power_in"))
      (node (ref "P8") (pin "P$76") (pinfunction "P$1_P$76") (pintype "power_in"))
      (node (ref "P8") (pin "P$77") (pinfunction "P$1_P$77") (pintype "power_in"))
      (node (ref "P8") (pin "P$78") (pinfunction "P$1_P$78") (pintype "power_in"))
      (node (ref "P8") (pin "P$79") (pinfunction "P$1_P$79") (pintype "power_in"))
      (node (ref "P8") (pin "P$8") (pinfunction "P$1_P$8") (pintype "power_in"))
      (node (ref "P8") (pin "P$80") (pinfunction "P$1_P$80") (pintype "power_in"))
      (node (ref "P8") (pin "P$81") (pinfunction "P$1_P$81") (pintype "power_in"))
      (node (ref "P8") (pin "P$82") (pinfunction "P$1_P$82") (pintype "power_in"))
      (node (ref "P8") (pin "P$83") (pinfunction "P$1_P$83") (pintype "power_in"))
      (node (ref "P8") (pin "P$84") (pinfunction "P$1_P$84") (pintype "power_in"))
      (node (ref "P8") (pin "P$85") (pinfunction "P$1_P$85") (pintype "power_in"))
      (node (ref "P8") (pin "P$86") (pinfunction "P$1_P$86") (pintype "power_in"))
      (node (ref "P8") (pin "P$87") (pinfunction "P$1_P$87") (pintype "power_in"))
      (node (ref "P8") (pin "P$88") (pinfunction "P$1_P$88") (pintype "power_in"))
      (node (ref "P8") (pin "P$89") (pinfunction "P$1_P$89") (pintype "power_in"))
      (node (ref "P8") (pin "P$9") (pinfunction "P$1_P$9") (pintype "power_in"))
      (node (ref "P8") (pin "P$90") (pinfunction "P$1_P$90") (pintype "power_in"))
      (node (ref "P8") (pin "P$91") (pinfunction "P$1_P$91") (pintype "power_in"))
      (node (ref "P8") (pin "P$92") (pinfunction "P$1_P$92") (pintype "power_in"))
      (node (ref "P8") (pin "P$93") (pinfunction "P$1_P$93") (pintype "power_in"))
      (node (ref "P8") (pin "P$94") (pinfunction "P$1_P$94") (pintype "power_in"))
      (node (ref "P8") (pin "P$95") (pinfunction "P$1_P$95") (pintype "power_in"))
      (node (ref "P8") (pin "P$96") (pinfunction "P$1_P$96") (pintype "power_in"))
      (node (ref "P8") (pin "P$97") (pinfunction "P$1_P$97") (pintype "power_in"))
      (node (ref "P8") (pin "P$98") (pinfunction "P$1_P$98") (pintype "power_in"))
      (node (ref "P8") (pin "P$99") (pinfunction "P$1_P$99") (pintype "power_in"))
    )
    (net (code "11") (name "/P9") (class "Default")
      (node (ref "JP1") (pin "P$10") (pinfunction "9_P$10") (pintype "bidirectional"))
      (node (ref "P9") (pin "P$1") (pinfunction "P$1_P$1") (pintype "power_in"))
      (node (ref "P9") (pin "P$10") (pinfunction "P$1_P$10") (pintype "power_in"))
      (node (ref "P9") (pin "P$100") (pinfunction "P$1_P$100") (pintype "power_in"))
      (node (ref "P9") (pin "P$101") (pinfunction "P$1_P$101") (pintype "power_in"))
      (node (ref "P9") (pin "P$102") (pinfunction "P$1_P$102") (pintype "power_in"))
      (node (ref "P9") (pin "P$103") (pinfunction "P$1_P$103") (pintype "power_in"))
      (node (ref "P9") (pin "P$104") (pinfunction "P$1_P$104") (pintype "power_in"))
      (node (ref "P9") (pin "P$105") (pinfunction "P$1_P$105") (pintype "power_in"))
      (node (ref "P9") (pin "P$106") (pinfunction "P$1_P$106") (pintype "power_in"))
      (node (ref "P9") (pin "P$107") (pinfunction "P$1_P$107") (pintype "power_in"))
      (node (ref "P9") (pin "P$108") (pinfunction "P$1_P$108") (pintype "power_in"))
      (node (ref "P9") (pin "P$109") (pinfunction "P$1_P$109") (pintype "power_in"))
      (node (ref "P9") (pin "P$11") (pinfunction "P$1_P$11") (pintype "power_in"))
      (node (ref "P9") (pin "P$110") (pinfunction "P$1_P$110") (pintype "power_in"))
      (node (ref "P9") (pin "P$111") (pinfunction "P$1_P$111") (pintype "power_in"))
      (node (ref "P9") (pin "P$112") (pinfunction "P$1_P$112") (pintype "power_in"))
      (node (ref "P9") (pin "P$113") (pinfunction "P$1_P$113") (pintype "power_in"))
      (node (ref "P9") (pin "P$114") (pinfunction "P$1_P$114") (pintype "power_in"))
      (node (ref "P9") (pin "P$115") (pinfunction "P$1_P$115") (pintype "power_in"))
      (node (ref "P9") (pin "P$116") (pinfunction "P$1_P$116") (pintype "power_in"))
      (node (ref "P9") (pin "P$117") (pinfunction "P$1_P$117") (pintype "power_in"))
      (node (ref "P9") (pin "P$118") (pinfunction "P$1_P$118") (pintype "power_in"))
      (node (ref "P9") (pin "P$119") (pinfunction "P$1_P$119") (pintype "power_in"))
      (node (ref "P9") (pin "P$12") (pinfunction "P$1_P$12") (pintype "power_in"))
      (node (ref "P9") (pin "P$120") (pinfunction "P$1_P$120") (pintype "power_in"))
      (node (ref "P9") (pin "P$121") (pinfunction "P$1_P$121") (pintype "power_in"))
      (node (ref "P9") (pin "P$122") (pinfunction "P$1_P$122") (pintype "power_in"))
      (node (ref "P9") (pin "P$123") (pinfunction "P$1_P$123") (pintype "power_in"))
      (node (ref "P9") (pin "P$124") (pinfunction "P$1_P$124") (pintype "power_in"))
      (node (ref "P9") (pin "P$125") (pinfunction "P$1_P$125") (pintype "power_in"))
      (node (ref "P9") (pin "P$126") (pinfunction "P$1_P$126") (pintype "power_in"))
      (node (ref "P9") (pin "P$127") (pinfunction "P$1_P$127") (pintype "power_in"))
      (node (ref "P9") (pin "P$128") (pinfunction "P$1_P$128") (pintype "power_in"))
      (node (ref "P9") (pin "P$129") (pinfunction "P$1_P$129") (pintype "power_in"))
      (node (ref "P9") (pin "P$13") (pinfunction "P$1_P$13") (pintype "power_in"))
      (node (ref "P9") (pin "P$130") (pinfunction "P$1_P$130") (pintype "power_in"))
      (node (ref "P9") (pin "P$131") (pinfunction "P$1_P$131") (pintype "power_in"))
      (node (ref "P9") (pin "P$132") (pinfunction "P$1_P$132") (pintype "power_in"))
      (node (ref "P9") (pin "P$133") (pinfunction "P$1_P$133") (pintype "power_in"))
      (node (ref "P9") (pin "P$134") (pinfunction "P$1_P$134") (pintype "power_in"))
      (node (ref "P9") (pin "P$135") (pinfunction "P$1_P$135") (pintype "power_in"))
      (node (ref "P9") (pin "P$136") (pinfunction "P$1_P$136") (pintype "power_in"))
      (node (ref "P9") (pin "P$137") (pinfunction "P$1_P$137") (pintype "power_in"))
      (node (ref "P9") (pin "P$138") (pinfunction "P$1_P$138") (pintype "power_in"))
      (node (ref "P9") (pin "P$139") (pinfunction "P$1_P$139") (pintype "power_in"))
      (node (ref "P9") (pin "P$14") (pinfunction "P$1_P$14") (pintype "power_in"))
      (node (ref "P9") (pin "P$140") (pinfunction "P$1_P$140") (pintype "power_in"))
      (node (ref "P9") (pin "P$141") (pinfunction "P$1_P$141") (pintype "power_in"))
      (node (ref "P9") (pin "P$142") (pinfunction "P$1_P$142") (pintype "power_in"))
      (node (ref "P9") (pin "P$143") (pinfunction "P$1_P$143") (pintype "power_in"))
      (node (ref "P9") (pin "P$144") (pinfunction "P$1_P$144") (pintype "power_in"))
      (node (ref "P9") (pin "P$145") (pinfunction "P$1_P$145") (pintype "power_in"))
      (node (ref "P9") (pin "P$146") (pinfunction "P$1_P$146") (pintype "power_in"))
      (node (ref "P9") (pin "P$147") (pinfunction "P$1_P$147") (pintype "power_in"))
      (node (ref "P9") (pin "P$148") (pinfunction "P$1_P$148") (pintype "power_in"))
      (node (ref "P9") (pin "P$149") (pinfunction "P$1_P$149") (pintype "power_in"))
      (node (ref "P9") (pin "P$15") (pinfunction "P$1_P$15") (pintype "power_in"))
      (node (ref "P9") (pin "P$150") (pinfunction "P$1_P$150") (pintype "power_in"))
      (node (ref "P9") (pin "P$151") (pinfunction "P$1_P$151") (pintype "power_in"))
      (node (ref "P9") (pin "P$152") (pinfunction "P$1_P$152") (pintype "power_in"))
      (node (ref "P9") (pin "P$153") (pinfunction "P$1_P$153") (pintype "power_in"))
      (node (ref "P9") (pin "P$154") (pinfunction "P$1_P$154") (pintype "power_in"))
      (node (ref "P9") (pin "P$155") (pinfunction "P$1_P$155") (pintype "power_in"))
      (node (ref "P9") (pin "P$156") (pinfunction "P$1_P$156") (pintype "power_in"))
      (node (ref "P9") (pin "P$157") (pinfunction "P$1_P$157") (pintype "power_in"))
      (node (ref "P9") (pin "P$158") (pinfunction "P$1_P$158") (pintype "power_in"))
      (node (ref "P9") (pin "P$159") (pinfunction "P$1_P$159") (pintype "power_in"))
      (node (ref "P9") (pin "P$16") (pinfunction "P$1_P$16") (pintype "power_in"))
      (node (ref "P9") (pin "P$160") (pinfunction "P$1_P$160") (pintype "power_in"))
      (node (ref "P9") (pin "P$161") (pinfunction "P$1_P$161") (pintype "power_in"))
      (node (ref "P9") (pin "P$162") (pinfunction "P$1_P$162") (pintype "power_in"))
      (node (ref "P9") (pin "P$163") (pinfunction "P$1_P$163") (pintype "power_in"))
      (node (ref "P9") (pin "P$164") (pinfunction "P$1_P$164") (pintype "power_in"))
      (node (ref "P9") (pin "P$165") (pinfunction "P$1_P$165") (pintype "power_in"))
      (node (ref "P9") (pin "P$166") (pinfunction "P$1_P$166") (pintype "power_in"))
      (node (ref "P9") (pin "P$167") (pinfunction "P$1_P$167") (pintype "power_in"))
      (node (ref "P9") (pin "P$168") (pinfunction "P$1_P$168") (pintype "power_in"))
      (node (ref "P9") (pin "P$169") (pinfunction "P$1_P$169") (pintype "power_in"))
      (node (ref "P9") (pin "P$17") (pinfunction "P$1_P$17") (pintype "power_in"))
      (node (ref "P9") (pin "P$170") (pinfunction "P$1_P$170") (pintype "power_in"))
      (node (ref "P9") (pin "P$171") (pinfunction "P$1_P$171") (pintype "power_in"))
      (node (ref "P9") (pin "P$172") (pinfunction "P$1_P$172") (pintype "power_in"))
      (node (ref "P9") (pin "P$173") (pinfunction "P$1_P$173") (pintype "power_in"))
      (node (ref "P9") (pin "P$174") (pinfunction "P$1_P$174") (pintype "power_in"))
      (node (ref "P9") (pin "P$175") (pinfunction "P$1_P$175") (pintype "power_in"))
      (node (ref "P9") (pin "P$176") (pinfunction "P$1_P$176") (pintype "power_in"))
      (node (ref "P9") (pin "P$177") (pinfunction "P$1_P$177") (pintype "power_in"))
      (node (ref "P9") (pin "P$178") (pinfunction "P$1_P$178") (pintype "power_in"))
      (node (ref "P9") (pin "P$179") (pinfunction "P$1_P$179") (pintype "power_in"))
      (node (ref "P9") (pin "P$18") (pinfunction "P$1_P$18") (pintype "power_in"))
      (node (ref "P9") (pin "P$180") (pinfunction "P$1_P$180") (pintype "power_in"))
      (node (ref "P9") (pin "P$181") (pinfunction "P$1_P$181") (pintype "power_in"))
      (node (ref "P9") (pin "P$182") (pinfunction "P$1_P$182") (pintype "power_in"))
      (node (ref "P9") (pin "P$183") (pinfunction "P$1_P$183") (pintype "power_in"))
      (node (ref "P9") (pin "P$184") (pinfunction "P$1_P$184") (pintype "power_in"))
      (node (ref "P9") (pin "P$185") (pinfunction "P$1_P$185") (pintype "power_in"))
      (node (ref "P9") (pin "P$186") (pinfunction "P$1_P$186") (pintype "power_in"))
      (node (ref "P9") (pin "P$187") (pinfunction "P$1_P$187") (pintype "power_in"))
      (node (ref "P9") (pin "P$188") (pinfunction "P$1_P$188") (pintype "power_in"))
      (node (ref "P9") (pin "P$189") (pinfunction "P$1_P$189") (pintype "power_in"))
      (node (ref "P9") (pin "P$19") (pinfunction "P$1_P$19") (pintype "power_in"))
      (node (ref "P9") (pin "P$190") (pinfunction "P$1_P$190") (pintype "power_in"))
      (node (ref "P9") (pin "P$191") (pinfunction "P$1_P$191") (pintype "power_in"))
      (node (ref "P9") (pin "P$192") (pinfunction "P$1_P$192") (pintype "power_in"))
      (node (ref "P9") (pin "P$193") (pinfunction "P$1_P$193") (pintype "power_in"))
      (node (ref "P9") (pin "P$194") (pinfunction "P$1_P$194") (pintype "power_in"))
      (node (ref "P9") (pin "P$195") (pinfunction "P$1_P$195") (pintype "power_in"))
      (node (ref "P9") (pin "P$196") (pinfunction "P$1_P$196") (pintype "power_in"))
      (node (ref "P9") (pin "P$197") (pinfunction "P$1_P$197") (pintype "power_in"))
      (node (ref "P9") (pin "P$198") (pinfunction "P$1_P$198") (pintype "power_in"))
      (node (ref "P9") (pin "P$199") (pinfunction "P$1_P$199") (pintype "power_in"))
      (node (ref "P9") (pin "P$2") (pinfunction "P$1_P$2") (pintype "power_in"))
      (node (ref "P9") (pin "P$20") (pinfunction "P$1_P$20") (pintype "power_in"))
      (node (ref "P9") (pin "P$200") (pinfunction "P$1_P$200") (pintype "power_in"))
      (node (ref "P9") (pin "P$201") (pinfunction "P$1_P$201") (pintype "power_in"))
      (node (ref "P9") (pin "P$202") (pinfunction "P$1_P$202") (pintype "power_in"))
      (node (ref "P9") (pin "P$203") (pinfunction "P$1_P$203") (pintype "power_in"))
      (node (ref "P9") (pin "P$204") (pinfunction "P$1_P$204") (pintype "power_in"))
      (node (ref "P9") (pin "P$205") (pinfunction "P$1_P$205") (pintype "power_in"))
      (node (ref "P9") (pin "P$206") (pinfunction "P$1_P$206") (pintype "power_in"))
      (node (ref "P9") (pin "P$207") (pinfunction "P$1_P$207") (pintype "power_in"))
      (node (ref "P9") (pin "P$208") (pinfunction "P$1_P$208") (pintype "power_in"))
      (node (ref "P9") (pin "P$209") (pinfunction "P$1_P$209") (pintype "power_in"))
      (node (ref "P9") (pin "P$21") (pinfunction "P$1_P$21") (pintype "power_in"))
      (node (ref "P9") (pin "P$210") (pinfunction "P$1_P$210") (pintype "power_in"))
      (node (ref "P9") (pin "P$211") (pinfunction "P$1_P$211") (pintype "power_in"))
      (node (ref "P9") (pin "P$212") (pinfunction "P$1_P$212") (pintype "power_in"))
      (node (ref "P9") (pin "P$213") (pinfunction "P$1_P$213") (pintype "power_in"))
      (node (ref "P9") (pin "P$214") (pinfunction "P$1_P$214") (pintype "power_in"))
      (node (ref "P9") (pin "P$215") (pinfunction "P$1_P$215") (pintype "power_in"))
      (node (ref "P9") (pin "P$216") (pinfunction "P$1_P$216") (pintype "power_in"))
      (node (ref "P9") (pin "P$217") (pinfunction "P$1_P$217") (pintype "power_in"))
      (node (ref "P9") (pin "P$218") (pinfunction "P$1_P$218") (pintype "power_in"))
      (node (ref "P9") (pin "P$219") (pinfunction "P$1_P$219") (pintype "power_in"))
      (node (ref "P9") (pin "P$22") (pinfunction "P$1_P$22") (pintype "power_in"))
      (node (ref "P9") (pin "P$220") (pinfunction "P$1_P$220") (pintype "power_in"))
      (node (ref "P9") (pin "P$221") (pinfunction "P$1_P$221") (pintype "power_in"))
      (node (ref "P9") (pin "P$222") (pinfunction "P$1_P$222") (pintype "power_in"))
      (node (ref "P9") (pin "P$223") (pinfunction "P$1_P$223") (pintype "power_in"))
      (node (ref "P9") (pin "P$224") (pinfunction "P$1_P$224") (pintype "power_in"))
      (node (ref "P9") (pin "P$225") (pinfunction "P$1_P$225") (pintype "power_in"))
      (node (ref "P9") (pin "P$226") (pinfunction "P$1_P$226") (pintype "power_in"))
      (node (ref "P9") (pin "P$227") (pinfunction "P$1_P$227") (pintype "power_in"))
      (node (ref "P9") (pin "P$228") (pinfunction "P$1_P$228") (pintype "power_in"))
      (node (ref "P9") (pin "P$229") (pinfunction "P$1_P$229") (pintype "power_in"))
      (node (ref "P9") (pin "P$23") (pinfunction "P$1_P$23") (pintype "power_in"))
      (node (ref "P9") (pin "P$230") (pinfunction "P$1_P$230") (pintype "power_in"))
      (node (ref "P9") (pin "P$231") (pinfunction "P$1_P$231") (pintype "power_in"))
      (node (ref "P9") (pin "P$232") (pinfunction "P$1_P$232") (pintype "power_in"))
      (node (ref "P9") (pin "P$233") (pinfunction "P$1_P$233") (pintype "power_in"))
      (node (ref "P9") (pin "P$234") (pinfunction "P$1_P$234") (pintype "power_in"))
      (node (ref "P9") (pin "P$235") (pinfunction "P$1_P$235") (pintype "power_in"))
      (node (ref "P9") (pin "P$236") (pinfunction "P$1_P$236") (pintype "power_in"))
      (node (ref "P9") (pin "P$237") (pinfunction "P$1_P$237") (pintype "power_in"))
      (node (ref "P9") (pin "P$238") (pinfunction "P$1_P$238") (pintype "power_in"))
      (node (ref "P9") (pin "P$239") (pinfunction "P$1_P$239") (pintype "power_in"))
      (node (ref "P9") (pin "P$24") (pinfunction "P$1_P$24") (pintype "power_in"))
      (node (ref "P9") (pin "P$240") (pinfunction "P$1_P$240") (pintype "power_in"))
      (node (ref "P9") (pin "P$241") (pinfunction "P$1_P$241") (pintype "power_in"))
      (node (ref "P9") (pin "P$242") (pinfunction "P$1_P$242") (pintype "power_in"))
      (node (ref "P9") (pin "P$243") (pinfunction "P$1_P$243") (pintype "power_in"))
      (node (ref "P9") (pin "P$244") (pinfunction "P$1_P$244") (pintype "power_in"))
      (node (ref "P9") (pin "P$245") (pinfunction "P$1_P$245") (pintype "power_in"))
      (node (ref "P9") (pin "P$246") (pinfunction "P$1_P$246") (pintype "power_in"))
      (node (ref "P9") (pin "P$247") (pinfunction "P$1_P$247") (pintype "power_in"))
      (node (ref "P9") (pin "P$248") (pinfunction "P$1_P$248") (pintype "power_in"))
      (node (ref "P9") (pin "P$249") (pinfunction "P$1_P$249") (pintype "power_in"))
      (node (ref "P9") (pin "P$25") (pinfunction "P$1_P$25") (pintype "power_in"))
      (node (ref "P9") (pin "P$250") (pinfunction "P$1_P$250") (pintype "power_in"))
      (node (ref "P9") (pin "P$251") (pinfunction "P$1_P$251") (pintype "power_in"))
      (node (ref "P9") (pin "P$252") (pinfunction "P$1_P$252") (pintype "power_in"))
      (node (ref "P9") (pin "P$253") (pinfunction "P$1_P$253") (pintype "power_in"))
      (node (ref "P9") (pin "P$254") (pinfunction "P$1_P$254") (pintype "power_in"))
      (node (ref "P9") (pin "P$255") (pinfunction "P$1_P$255") (pintype "power_in"))
      (node (ref "P9") (pin "P$256") (pinfunction "P$1_P$256") (pintype "power_in"))
      (node (ref "P9") (pin "P$257") (pinfunction "P$1_P$257") (pintype "power_in"))
      (node (ref "P9") (pin "P$258") (pinfunction "P$1_P$258") (pintype "power_in"))
      (node (ref "P9") (pin "P$259") (pinfunction "P$1_P$259") (pintype "power_in"))
      (node (ref "P9") (pin "P$26") (pinfunction "P$1_P$26") (pintype "power_in"))
      (node (ref "P9") (pin "P$260") (pinfunction "P$1_P$260") (pintype "power_in"))
      (node (ref "P9") (pin "P$261") (pinfunction "P$1_P$261") (pintype "power_in"))
      (node (ref "P9") (pin "P$262") (pinfunction "P$1_P$262") (pintype "power_in"))
      (node (ref "P9") (pin "P$263") (pinfunction "P$1_P$263") (pintype "power_in"))
      (node (ref "P9") (pin "P$264") (pinfunction "P$1_P$264") (pintype "power_in"))
      (node (ref "P9") (pin "P$265") (pinfunction "P$1_P$265") (pintype "power_in"))
      (node (ref "P9") (pin "P$266") (pinfunction "P$1_P$266") (pintype "power_in"))
      (node (ref "P9") (pin "P$267") (pinfunction "P$1_P$267") (pintype "power_in"))
      (node (ref "P9") (pin "P$268") (pinfunction "P$1_P$268") (pintype "power_in"))
      (node (ref "P9") (pin "P$269") (pinfunction "P$1_P$269") (pintype "power_in"))
      (node (ref "P9") (pin "P$27") (pinfunction "P$1_P$27") (pintype "power_in"))
      (node (ref "P9") (pin "P$270") (pinfunction "P$1_P$270") (pintype "power_in"))
      (node (ref "P9") (pin "P$271") (pinfunction "P$1_P$271") (pintype "power_in"))
      (node (ref "P9") (pin "P$272") (pinfunction "P$1_P$272") (pintype "power_in"))
      (node (ref "P9") (pin "P$273") (pinfunction "P$1_P$273") (pintype "power_in"))
      (node (ref "P9") (pin "P$274") (pinfunction "P$1_P$274") (pintype "power_in"))
      (node (ref "P9") (pin "P$275") (pinfunction "P$1_P$275") (pintype "power_in"))
      (node (ref "P9") (pin "P$276") (pinfunction "P$1_P$276") (pintype "power_in"))
      (node (ref "P9") (pin "P$277") (pinfunction "P$1_P$277") (pintype "power_in"))
      (node (ref "P9") (pin "P$278") (pinfunction "P$1_P$278") (pintype "power_in"))
      (node (ref "P9") (pin "P$279") (pinfunction "P$1_P$279") (pintype "power_in"))
      (node (ref "P9") (pin "P$28") (pinfunction "P$1_P$28") (pintype "power_in"))
      (node (ref "P9") (pin "P$280") (pinfunction "P$1_P$280") (pintype "power_in"))
      (node (ref "P9") (pin "P$281") (pinfunction "P$1_P$281") (pintype "power_in"))
      (node (ref "P9") (pin "P$282") (pinfunction "P$1_P$282") (pintype "power_in"))
      (node (ref "P9") (pin "P$283") (pinfunction "P$1_P$283") (pintype "power_in"))
      (node (ref "P9") (pin "P$284") (pinfunction "P$1_P$284") (pintype "power_in"))
      (node (ref "P9") (pin "P$285") (pinfunction "P$1_P$285") (pintype "power_in"))
      (node (ref "P9") (pin "P$286") (pinfunction "P$1_P$286") (pintype "power_in"))
      (node (ref "P9") (pin "P$287") (pinfunction "P$1_P$287") (pintype "power_in"))
      (node (ref "P9") (pin "P$288") (pinfunction "P$1_P$288") (pintype "power_in"))
      (node (ref "P9") (pin "P$29") (pinfunction "P$1_P$29") (pintype "power_in"))
      (node (ref "P9") (pin "P$3") (pinfunction "P$1_P$3") (pintype "power_in"))
      (node (ref "P9") (pin "P$30") (pinfunction "P$1_P$30") (pintype "power_in"))
      (node (ref "P9") (pin "P$31") (pinfunction "P$1_P$31") (pintype "power_in"))
      (node (ref "P9") (pin "P$32") (pinfunction "P$1_P$32") (pintype "power_in"))
      (node (ref "P9") (pin "P$33") (pinfunction "P$1_P$33") (pintype "power_in"))
      (node (ref "P9") (pin "P$34") (pinfunction "P$1_P$34") (pintype "power_in"))
      (node (ref "P9") (pin "P$35") (pinfunction "P$1_P$35") (pintype "power_in"))
      (node (ref "P9") (pin "P$36") (pinfunction "P$1_P$36") (pintype "power_in"))
      (node (ref "P9") (pin "P$37") (pinfunction "P$1_P$37") (pintype "power_in"))
      (node (ref "P9") (pin "P$38") (pinfunction "P$1_P$38") (pintype "power_in"))
      (node (ref "P9") (pin "P$39") (pinfunction "P$1_P$39") (pintype "power_in"))
      (node (ref "P9") (pin "P$4") (pinfunction "P$1_P$4") (pintype "power_in"))
      (node (ref "P9") (pin "P$40") (pinfunction "P$1_P$40") (pintype "power_in"))
      (node (ref "P9") (pin "P$41") (pinfunction "P$1_P$41") (pintype "power_in"))
      (node (ref "P9") (pin "P$42") (pinfunction "P$1_P$42") (pintype "power_in"))
      (node (ref "P9") (pin "P$43") (pinfunction "P$1_P$43") (pintype "power_in"))
      (node (ref "P9") (pin "P$44") (pinfunction "P$1_P$44") (pintype "power_in"))
      (node (ref "P9") (pin "P$45") (pinfunction "P$1_P$45") (pintype "power_in"))
      (node (ref "P9") (pin "P$46") (pinfunction "P$1_P$46") (pintype "power_in"))
      (node (ref "P9") (pin "P$47") (pinfunction "P$1_P$47") (pintype "power_in"))
      (node (ref "P9") (pin "P$48") (pinfunction "P$1_P$48") (pintype "power_in"))
      (node (ref "P9") (pin "P$49") (pinfunction "P$1_P$49") (pintype "power_in"))
      (node (ref "P9") (pin "P$5") (pinfunction "P$1_P$5") (pintype "power_in"))
      (node (ref "P9") (pin "P$50") (pinfunction "P$1_P$50") (pintype "power_in"))
      (node (ref "P9") (pin "P$51") (pinfunction "P$1_P$51") (pintype "power_in"))
      (node (ref "P9") (pin "P$52") (pinfunction "P$1_P$52") (pintype "power_in"))
      (node (ref "P9") (pin "P$53") (pinfunction "P$1_P$53") (pintype "power_in"))
      (node (ref "P9") (pin "P$54") (pinfunction "P$1_P$54") (pintype "power_in"))
      (node (ref "P9") (pin "P$55") (pinfunction "P$1_P$55") (pintype "power_in"))
      (node (ref "P9") (pin "P$56") (pinfunction "P$1_P$56") (pintype "power_in"))
      (node (ref "P9") (pin "P$57") (pinfunction "P$1_P$57") (pintype "power_in"))
      (node (ref "P9") (pin "P$58") (pinfunction "P$1_P$58") (pintype "power_in"))
      (node (ref "P9") (pin "P$59") (pinfunction "P$1_P$59") (pintype "power_in"))
      (node (ref "P9") (pin "P$6") (pinfunction "P$1_P$6") (pintype "power_in"))
      (node (ref "P9") (pin "P$60") (pinfunction "P$1_P$60") (pintype "power_in"))
      (node (ref "P9") (pin "P$61") (pinfunction "P$1_P$61") (pintype "power_in"))
      (node (ref "P9") (pin "P$62") (pinfunction "P$1_P$62") (pintype "power_in"))
      (node (ref "P9") (pin "P$63") (pinfunction "P$1_P$63") (pintype "power_in"))
      (node (ref "P9") (pin "P$64") (pinfunction "P$1_P$64") (pintype "power_in"))
      (node (ref "P9") (pin "P$65") (pinfunction "P$1_P$65") (pintype "power_in"))
      (node (ref "P9") (pin "P$66") (pinfunction "P$1_P$66") (pintype "power_in"))
      (node (ref "P9") (pin "P$67") (pinfunction "P$1_P$67") (pintype "power_in"))
      (node (ref "P9") (pin "P$68") (pinfunction "P$1_P$68") (pintype "power_in"))
      (node (ref "P9") (pin "P$69") (pinfunction "P$1_P$69") (pintype "power_in"))
      (node (ref "P9") (pin "P$7") (pinfunction "P$1_P$7") (pintype "power_in"))
      (node (ref "P9") (pin "P$70") (pinfunction "P$1_P$70") (pintype "power_in"))
      (node (ref "P9") (pin "P$71") (pinfunction "P$1_P$71") (pintype "power_in"))
      (node (ref "P9") (pin "P$72") (pinfunction "P$1_P$72") (pintype "power_in"))
      (node (ref "P9") (pin "P$73") (pinfunction "P$1_P$73") (pintype "power_in"))
      (node (ref "P9") (pin "P$74") (pinfunction "P$1_P$74") (pintype "power_in"))
      (node (ref "P9") (pin "P$75") (pinfunction "P$1_P$75") (pintype "power_in"))
      (node (ref "P9") (pin "P$76") (pinfunction "P$1_P$76") (pintype "power_in"))
      (node (ref "P9") (pin "P$77") (pinfunction "P$1_P$77") (pintype "power_in"))
      (node (ref "P9") (pin "P$78") (pinfunction "P$1_P$78") (pintype "power_in"))
      (node (ref "P9") (pin "P$79") (pinfunction "P$1_P$79") (pintype "power_in"))
      (node (ref "P9") (pin "P$8") (pinfunction "P$1_P$8") (pintype "power_in"))
      (node (ref "P9") (pin "P$80") (pinfunction "P$1_P$80") (pintype "power_in"))
      (node (ref "P9") (pin "P$81") (pinfunction "P$1_P$81") (pintype "power_in"))
      (node (ref "P9") (pin "P$82") (pinfunction "P$1_P$82") (pintype "power_in"))
      (node (ref "P9") (pin "P$83") (pinfunction "P$1_P$83") (pintype "power_in"))
      (node (ref "P9") (pin "P$84") (pinfunction "P$1_P$84") (pintype "power_in"))
      (node (ref "P9") (pin "P$85") (pinfunction "P$1_P$85") (pintype "power_in"))
      (node (ref "P9") (pin "P$86") (pinfunction "P$1_P$86") (pintype "power_in"))
      (node (ref "P9") (pin "P$87") (pinfunction "P$1_P$87") (pintype "power_in"))
      (node (ref "P9") (pin "P$88") (pinfunction "P$1_P$88") (pintype "power_in"))
      (node (ref "P9") (pin "P$89") (pinfunction "P$1_P$89") (pintype "power_in"))
      (node (ref "P9") (pin "P$9") (pinfunction "P$1_P$9") (pintype "power_in"))
      (node (ref "P9") (pin "P$90") (pinfunction "P$1_P$90") (pintype "power_in"))
      (node (ref "P9") (pin "P$91") (pinfunction "P$1_P$91") (pintype "power_in"))
      (node (ref "P9") (pin "P$92") (pinfunction "P$1_P$92") (pintype "power_in"))
      (node (ref "P9") (pin "P$93") (pinfunction "P$1_P$93") (pintype "power_in"))
      (node (ref "P9") (pin "P$94") (pinfunction "P$1_P$94") (pintype "power_in"))
      (node (ref "P9") (pin "P$95") (pinfunction "P$1_P$95") (pintype "power_in"))
      (node (ref "P9") (pin "P$96") (pinfunction "P$1_P$96") (pintype "power_in"))
      (node (ref "P9") (pin "P$97") (pinfunction "P$1_P$97") (pintype "power_in"))
      (node (ref "P9") (pin "P$98") (pinfunction "P$1_P$98") (pintype "power_in"))
      (node (ref "P9") (pin "P$99") (pinfunction "P$1_P$99") (pintype "power_in"))
    )
    (net (code "12") (name "/P10") (class "Default")
      (node (ref "JP1") (pin "P$11") (pinfunction "10_P$11") (pintype "bidirectional"))
      (node (ref "P10") (pin "P$1") (pinfunction "P$1_P$1") (pintype "power_in"))
      (node (ref "P10") (pin "P$10") (pinfunction "P$1_P$10") (pintype "power_in"))
      (node (ref "P10") (pin "P$100") (pinfunction "P$1_P$100") (pintype "power_in"))
      (node (ref "P10") (pin "P$101") (pinfunction "P$1_P$101") (pintype "power_in"))
      (node (ref "P10") (pin "P$102") (pinfunction "P$1_P$102") (pintype "power_in"))
      (node (ref "P10") (pin "P$103") (pinfunction "P$1_P$103") (pintype "power_in"))
      (node (ref "P10") (pin "P$104") (pinfunction "P$1_P$104") (pintype "power_in"))
      (node (ref "P10") (pin "P$105") (pinfunction "P$1_P$105") (pintype "power_in"))
      (node (ref "P10") (pin "P$106") (pinfunction "P$1_P$106") (pintype "power_in"))
      (node (ref "P10") (pin "P$107") (pinfunction "P$1_P$107") (pintype "power_in"))
      (node (ref "P10") (pin "P$108") (pinfunction "P$1_P$108") (pintype "power_in"))
      (node (ref "P10") (pin "P$109") (pinfunction "P$1_P$109") (pintype "power_in"))
      (node (ref "P10") (pin "P$11") (pinfunction "P$1_P$11") (pintype "power_in"))
      (node (ref "P10") (pin "P$110") (pinfunction "P$1_P$110") (pintype "power_in"))
      (node (ref "P10") (pin "P$111") (pinfunction "P$1_P$111") (pintype "power_in"))
      (node (ref "P10") (pin "P$112") (pinfunction "P$1_P$112") (pintype "power_in"))
      (node (ref "P10") (pin "P$113") (pinfunction "P$1_P$113") (pintype "power_in"))
      (node (ref "P10") (pin "P$114") (pinfunction "P$1_P$114") (pintype "power_in"))
      (node (ref "P10") (pin "P$115") (pinfunction "P$1_P$115") (pintype "power_in"))
      (node (ref "P10") (pin "P$116") (pinfunction "P$1_P$116") (pintype "power_in"))
      (node (ref "P10") (pin "P$117") (pinfunction "P$1_P$117") (pintype "power_in"))
      (node (ref "P10") (pin "P$118") (pinfunction "P$1_P$118") (pintype "power_in"))
      (node (ref "P10") (pin "P$119") (pinfunction "P$1_P$119") (pintype "power_in"))
      (node (ref "P10") (pin "P$12") (pinfunction "P$1_P$12") (pintype "power_in"))
      (node (ref "P10") (pin "P$120") (pinfunction "P$1_P$120") (pintype "power_in"))
      (node (ref "P10") (pin "P$121") (pinfunction "P$1_P$121") (pintype "power_in"))
      (node (ref "P10") (pin "P$122") (pinfunction "P$1_P$122") (pintype "power_in"))
      (node (ref "P10") (pin "P$123") (pinfunction "P$1_P$123") (pintype "power_in"))
      (node (ref "P10") (pin "P$124") (pinfunction "P$1_P$124") (pintype "power_in"))
      (node (ref "P10") (pin "P$125") (pinfunction "P$1_P$125") (pintype "power_in"))
      (node (ref "P10") (pin "P$126") (pinfunction "P$1_P$126") (pintype "power_in"))
      (node (ref "P10") (pin "P$127") (pinfunction "P$1_P$127") (pintype "power_in"))
      (node (ref "P10") (pin "P$128") (pinfunction "P$1_P$128") (pintype "power_in"))
      (node (ref "P10") (pin "P$129") (pinfunction "P$1_P$129") (pintype "power_in"))
      (node (ref "P10") (pin "P$13") (pinfunction "P$1_P$13") (pintype "power_in"))
      (node (ref "P10") (pin "P$130") (pinfunction "P$1_P$130") (pintype "power_in"))
      (node (ref "P10") (pin "P$131") (pinfunction "P$1_P$131") (pintype "power_in"))
      (node (ref "P10") (pin "P$132") (pinfunction "P$1_P$132") (pintype "power_in"))
      (node (ref "P10") (pin "P$133") (pinfunction "P$1_P$133") (pintype "power_in"))
      (node (ref "P10") (pin "P$134") (pinfunction "P$1_P$134") (pintype "power_in"))
      (node (ref "P10") (pin "P$135") (pinfunction "P$1_P$135") (pintype "power_in"))
      (node (ref "P10") (pin "P$136") (pinfunction "P$1_P$136") (pintype "power_in"))
      (node (ref "P10") (pin "P$137") (pinfunction "P$1_P$137") (pintype "power_in"))
      (node (ref "P10") (pin "P$138") (pinfunction "P$1_P$138") (pintype "power_in"))
      (node (ref "P10") (pin "P$139") (pinfunction "P$1_P$139") (pintype "power_in"))
      (node (ref "P10") (pin "P$14") (pinfunction "P$1_P$14") (pintype "power_in"))
      (node (ref "P10") (pin "P$140") (pinfunction "P$1_P$140") (pintype "power_in"))
      (node (ref "P10") (pin "P$141") (pinfunction "P$1_P$141") (pintype "power_in"))
      (node (ref "P10") (pin "P$142") (pinfunction "P$1_P$142") (pintype "power_in"))
      (node (ref "P10") (pin "P$143") (pinfunction "P$1_P$143") (pintype "power_in"))
      (node (ref "P10") (pin "P$144") (pinfunction "P$1_P$144") (pintype "power_in"))
      (node (ref "P10") (pin "P$145") (pinfunction "P$1_P$145") (pintype "power_in"))
      (node (ref "P10") (pin "P$146") (pinfunction "P$1_P$146") (pintype "power_in"))
      (node (ref "P10") (pin "P$147") (pinfunction "P$1_P$147") (pintype "power_in"))
      (node (ref "P10") (pin "P$148") (pinfunction "P$1_P$148") (pintype "power_in"))
      (node (ref "P10") (pin "P$149") (pinfunction "P$1_P$149") (pintype "power_in"))
      (node (ref "P10") (pin "P$15") (pinfunction "P$1_P$15") (pintype "power_in"))
      (node (ref "P10") (pin "P$150") (pinfunction "P$1_P$150") (pintype "power_in"))
      (node (ref "P10") (pin "P$151") (pinfunction "P$1_P$151") (pintype "power_in"))
      (node (ref "P10") (pin "P$152") (pinfunction "P$1_P$152") (pintype "power_in"))
      (node (ref "P10") (pin "P$153") (pinfunction "P$1_P$153") (pintype "power_in"))
      (node (ref "P10") (pin "P$154") (pinfunction "P$1_P$154") (pintype "power_in"))
      (node (ref "P10") (pin "P$155") (pinfunction "P$1_P$155") (pintype "power_in"))
      (node (ref "P10") (pin "P$156") (pinfunction "P$1_P$156") (pintype "power_in"))
      (node (ref "P10") (pin "P$157") (pinfunction "P$1_P$157") (pintype "power_in"))
      (node (ref "P10") (pin "P$158") (pinfunction "P$1_P$158") (pintype "power_in"))
      (node (ref "P10") (pin "P$159") (pinfunction "P$1_P$159") (pintype "power_in"))
      (node (ref "P10") (pin "P$16") (pinfunction "P$1_P$16") (pintype "power_in"))
      (node (ref "P10") (pin "P$160") (pinfunction "P$1_P$160") (pintype "power_in"))
      (node (ref "P10") (pin "P$161") (pinfunction "P$1_P$161") (pintype "power_in"))
      (node (ref "P10") (pin "P$162") (pinfunction "P$1_P$162") (pintype "power_in"))
      (node (ref "P10") (pin "P$163") (pinfunction "P$1_P$163") (pintype "power_in"))
      (node (ref "P10") (pin "P$164") (pinfunction "P$1_P$164") (pintype "power_in"))
      (node (ref "P10") (pin "P$165") (pinfunction "P$1_P$165") (pintype "power_in"))
      (node (ref "P10") (pin "P$166") (pinfunction "P$1_P$166") (pintype "power_in"))
      (node (ref "P10") (pin "P$167") (pinfunction "P$1_P$167") (pintype "power_in"))
      (node (ref "P10") (pin "P$168") (pinfunction "P$1_P$168") (pintype "power_in"))
      (node (ref "P10") (pin "P$169") (pinfunction "P$1_P$169") (pintype "power_in"))
      (node (ref "P10") (pin "P$17") (pinfunction "P$1_P$17") (pintype "power_in"))
      (node (ref "P10") (pin "P$170") (pinfunction "P$1_P$170") (pintype "power_in"))
      (node (ref "P10") (pin "P$171") (pinfunction "P$1_P$171") (pintype "power_in"))
      (node (ref "P10") (pin "P$172") (pinfunction "P$1_P$172") (pintype "power_in"))
      (node (ref "P10") (pin "P$173") (pinfunction "P$1_P$173") (pintype "power_in"))
      (node (ref "P10") (pin "P$174") (pinfunction "P$1_P$174") (pintype "power_in"))
      (node (ref "P10") (pin "P$175") (pinfunction "P$1_P$175") (pintype "power_in"))
      (node (ref "P10") (pin "P$176") (pinfunction "P$1_P$176") (pintype "power_in"))
      (node (ref "P10") (pin "P$177") (pinfunction "P$1_P$177") (pintype "power_in"))
      (node (ref "P10") (pin "P$178") (pinfunction "P$1_P$178") (pintype "power_in"))
      (node (ref "P10") (pin "P$179") (pinfunction "P$1_P$179") (pintype "power_in"))
      (node (ref "P10") (pin "P$18") (pinfunction "P$1_P$18") (pintype "power_in"))
      (node (ref "P10") (pin "P$180") (pinfunction "P$1_P$180") (pintype "power_in"))
      (node (ref "P10") (pin "P$181") (pinfunction "P$1_P$181") (pintype "power_in"))
      (node (ref "P10") (pin "P$182") (pinfunction "P$1_P$182") (pintype "power_in"))
      (node (ref "P10") (pin "P$183") (pinfunction "P$1_P$183") (pintype "power_in"))
      (node (ref "P10") (pin "P$184") (pinfunction "P$1_P$184") (pintype "power_in"))
      (node (ref "P10") (pin "P$185") (pinfunction "P$1_P$185") (pintype "power_in"))
      (node (ref "P10") (pin "P$186") (pinfunction "P$1_P$186") (pintype "power_in"))
      (node (ref "P10") (pin "P$187") (pinfunction "P$1_P$187") (pintype "power_in"))
      (node (ref "P10") (pin "P$188") (pinfunction "P$1_P$188") (pintype "power_in"))
      (node (ref "P10") (pin "P$189") (pinfunction "P$1_P$189") (pintype "power_in"))
      (node (ref "P10") (pin "P$19") (pinfunction "P$1_P$19") (pintype "power_in"))
      (node (ref "P10") (pin "P$190") (pinfunction "P$1_P$190") (pintype "power_in"))
      (node (ref "P10") (pin "P$191") (pinfunction "P$1_P$191") (pintype "power_in"))
      (node (ref "P10") (pin "P$192") (pinfunction "P$1_P$192") (pintype "power_in"))
      (node (ref "P10") (pin "P$193") (pinfunction "P$1_P$193") (pintype "power_in"))
      (node (ref "P10") (pin "P$194") (pinfunction "P$1_P$194") (pintype "power_in"))
      (node (ref "P10") (pin "P$195") (pinfunction "P$1_P$195") (pintype "power_in"))
      (node (ref "P10") (pin "P$196") (pinfunction "P$1_P$196") (pintype "power_in"))
      (node (ref "P10") (pin "P$197") (pinfunction "P$1_P$197") (pintype "power_in"))
      (node (ref "P10") (pin "P$198") (pinfunction "P$1_P$198") (pintype "power_in"))
      (node (ref "P10") (pin "P$199") (pinfunction "P$1_P$199") (pintype "power_in"))
      (node (ref "P10") (pin "P$2") (pinfunction "P$1_P$2") (pintype "power_in"))
      (node (ref "P10") (pin "P$20") (pinfunction "P$1_P$20") (pintype "power_in"))
      (node (ref "P10") (pin "P$200") (pinfunction "P$1_P$200") (pintype "power_in"))
      (node (ref "P10") (pin "P$201") (pinfunction "P$1_P$201") (pintype "power_in"))
      (node (ref "P10") (pin "P$202") (pinfunction "P$1_P$202") (pintype "power_in"))
      (node (ref "P10") (pin "P$203") (pinfunction "P$1_P$203") (pintype "power_in"))
      (node (ref "P10") (pin "P$204") (pinfunction "P$1_P$204") (pintype "power_in"))
      (node (ref "P10") (pin "P$205") (pinfunction "P$1_P$205") (pintype "power_in"))
      (node (ref "P10") (pin "P$206") (pinfunction "P$1_P$206") (pintype "power_in"))
      (node (ref "P10") (pin "P$207") (pinfunction "P$1_P$207") (pintype "power_in"))
      (node (ref "P10") (pin "P$208") (pinfunction "P$1_P$208") (pintype "power_in"))
      (node (ref "P10") (pin "P$209") (pinfunction "P$1_P$209") (pintype "power_in"))
      (node (ref "P10") (pin "P$21") (pinfunction "P$1_P$21") (pintype "power_in"))
      (node (ref "P10") (pin "P$210") (pinfunction "P$1_P$210") (pintype "power_in"))
      (node (ref "P10") (pin "P$211") (pinfunction "P$1_P$211") (pintype "power_in"))
      (node (ref "P10") (pin "P$212") (pinfunction "P$1_P$212") (pintype "power_in"))
      (node (ref "P10") (pin "P$213") (pinfunction "P$1_P$213") (pintype "power_in"))
      (node (ref "P10") (pin "P$214") (pinfunction "P$1_P$214") (pintype "power_in"))
      (node (ref "P10") (pin "P$215") (pinfunction "P$1_P$215") (pintype "power_in"))
      (node (ref "P10") (pin "P$216") (pinfunction "P$1_P$216") (pintype "power_in"))
      (node (ref "P10") (pin "P$217") (pinfunction "P$1_P$217") (pintype "power_in"))
      (node (ref "P10") (pin "P$218") (pinfunction "P$1_P$218") (pintype "power_in"))
      (node (ref "P10") (pin "P$219") (pinfunction "P$1_P$219") (pintype "power_in"))
      (node (ref "P10") (pin "P$22") (pinfunction "P$1_P$22") (pintype "power_in"))
      (node (ref "P10") (pin "P$220") (pinfunction "P$1_P$220") (pintype "power_in"))
      (node (ref "P10") (pin "P$221") (pinfunction "P$1_P$221") (pintype "power_in"))
      (node (ref "P10") (pin "P$222") (pinfunction "P$1_P$222") (pintype "power_in"))
      (node (ref "P10") (pin "P$223") (pinfunction "P$1_P$223") (pintype "power_in"))
      (node (ref "P10") (pin "P$224") (pinfunction "P$1_P$224") (pintype "power_in"))
      (node (ref "P10") (pin "P$225") (pinfunction "P$1_P$225") (pintype "power_in"))
      (node (ref "P10") (pin "P$226") (pinfunction "P$1_P$226") (pintype "power_in"))
      (node (ref "P10") (pin "P$227") (pinfunction "P$1_P$227") (pintype "power_in"))
      (node (ref "P10") (pin "P$228") (pinfunction "P$1_P$228") (pintype "power_in"))
      (node (ref "P10") (pin "P$229") (pinfunction "P$1_P$229") (pintype "power_in"))
      (node (ref "P10") (pin "P$23") (pinfunction "P$1_P$23") (pintype "power_in"))
      (node (ref "P10") (pin "P$230") (pinfunction "P$1_P$230") (pintype "power_in"))
      (node (ref "P10") (pin "P$231") (pinfunction "P$1_P$231") (pintype "power_in"))
      (node (ref "P10") (pin "P$232") (pinfunction "P$1_P$232") (pintype "power_in"))
      (node (ref "P10") (pin "P$233") (pinfunction "P$1_P$233") (pintype "power_in"))
      (node (ref "P10") (pin "P$234") (pinfunction "P$1_P$234") (pintype "power_in"))
      (node (ref "P10") (pin "P$235") (pinfunction "P$1_P$235") (pintype "power_in"))
      (node (ref "P10") (pin "P$236") (pinfunction "P$1_P$236") (pintype "power_in"))
      (node (ref "P10") (pin "P$237") (pinfunction "P$1_P$237") (pintype "power_in"))
      (node (ref "P10") (pin "P$238") (pinfunction "P$1_P$238") (pintype "power_in"))
      (node (ref "P10") (pin "P$239") (pinfunction "P$1_P$239") (pintype "power_in"))
      (node (ref "P10") (pin "P$24") (pinfunction "P$1_P$24") (pintype "power_in"))
      (node (ref "P10") (pin "P$240") (pinfunction "P$1_P$240") (pintype "power_in"))
      (node (ref "P10") (pin "P$241") (pinfunction "P$1_P$241") (pintype "power_in"))
      (node (ref "P10") (pin "P$242") (pinfunction "P$1_P$242") (pintype "power_in"))
      (node (ref "P10") (pin "P$243") (pinfunction "P$1_P$243") (pintype "power_in"))
      (node (ref "P10") (pin "P$244") (pinfunction "P$1_P$244") (pintype "power_in"))
      (node (ref "P10") (pin "P$245") (pinfunction "P$1_P$245") (pintype "power_in"))
      (node (ref "P10") (pin "P$246") (pinfunction "P$1_P$246") (pintype "power_in"))
      (node (ref "P10") (pin "P$247") (pinfunction "P$1_P$247") (pintype "power_in"))
      (node (ref "P10") (pin "P$248") (pinfunction "P$1_P$248") (pintype "power_in"))
      (node (ref "P10") (pin "P$249") (pinfunction "P$1_P$249") (pintype "power_in"))
      (node (ref "P10") (pin "P$25") (pinfunction "P$1_P$25") (pintype "power_in"))
      (node (ref "P10") (pin "P$250") (pinfunction "P$1_P$250") (pintype "power_in"))
      (node (ref "P10") (pin "P$251") (pinfunction "P$1_P$251") (pintype "power_in"))
      (node (ref "P10") (pin "P$252") (pinfunction "P$1_P$252") (pintype "power_in"))
      (node (ref "P10") (pin "P$253") (pinfunction "P$1_P$253") (pintype "power_in"))
      (node (ref "P10") (pin "P$254") (pinfunction "P$1_P$254") (pintype "power_in"))
      (node (ref "P10") (pin "P$255") (pinfunction "P$1_P$255") (pintype "power_in"))
      (node (ref "P10") (pin "P$256") (pinfunction "P$1_P$256") (pintype "power_in"))
      (node (ref "P10") (pin "P$257") (pinfunction "P$1_P$257") (pintype "power_in"))
      (node (ref "P10") (pin "P$258") (pinfunction "P$1_P$258") (pintype "power_in"))
      (node (ref "P10") (pin "P$259") (pinfunction "P$1_P$259") (pintype "power_in"))
      (node (ref "P10") (pin "P$26") (pinfunction "P$1_P$26") (pintype "power_in"))
      (node (ref "P10") (pin "P$260") (pinfunction "P$1_P$260") (pintype "power_in"))
      (node (ref "P10") (pin "P$261") (pinfunction "P$1_P$261") (pintype "power_in"))
      (node (ref "P10") (pin "P$262") (pinfunction "P$1_P$262") (pintype "power_in"))
      (node (ref "P10") (pin "P$263") (pinfunction "P$1_P$263") (pintype "power_in"))
      (node (ref "P10") (pin "P$264") (pinfunction "P$1_P$264") (pintype "power_in"))
      (node (ref "P10") (pin "P$265") (pinfunction "P$1_P$265") (pintype "power_in"))
      (node (ref "P10") (pin "P$266") (pinfunction "P$1_P$266") (pintype "power_in"))
      (node (ref "P10") (pin "P$267") (pinfunction "P$1_P$267") (pintype "power_in"))
      (node (ref "P10") (pin "P$268") (pinfunction "P$1_P$268") (pintype "power_in"))
      (node (ref "P10") (pin "P$269") (pinfunction "P$1_P$269") (pintype "power_in"))
      (node (ref "P10") (pin "P$27") (pinfunction "P$1_P$27") (pintype "power_in"))
      (node (ref "P10") (pin "P$270") (pinfunction "P$1_P$270") (pintype "power_in"))
      (node (ref "P10") (pin "P$271") (pinfunction "P$1_P$271") (pintype "power_in"))
      (node (ref "P10") (pin "P$272") (pinfunction "P$1_P$272") (pintype "power_in"))
      (node (ref "P10") (pin "P$273") (pinfunction "P$1_P$273") (pintype "power_in"))
      (node (ref "P10") (pin "P$274") (pinfunction "P$1_P$274") (pintype "power_in"))
      (node (ref "P10") (pin "P$275") (pinfunction "P$1_P$275") (pintype "power_in"))
      (node (ref "P10") (pin "P$276") (pinfunction "P$1_P$276") (pintype "power_in"))
      (node (ref "P10") (pin "P$277") (pinfunction "P$1_P$277") (pintype "power_in"))
      (node (ref "P10") (pin "P$278") (pinfunction "P$1_P$278") (pintype "power_in"))
      (node (ref "P10") (pin "P$279") (pinfunction "P$1_P$279") (pintype "power_in"))
      (node (ref "P10") (pin "P$28") (pinfunction "P$1_P$28") (pintype "power_in"))
      (node (ref "P10") (pin "P$280") (pinfunction "P$1_P$280") (pintype "power_in"))
      (node (ref "P10") (pin "P$281") (pinfunction "P$1_P$281") (pintype "power_in"))
      (node (ref "P10") (pin "P$282") (pinfunction "P$1_P$282") (pintype "power_in"))
      (node (ref "P10") (pin "P$283") (pinfunction "P$1_P$283") (pintype "power_in"))
      (node (ref "P10") (pin "P$284") (pinfunction "P$1_P$284") (pintype "power_in"))
      (node (ref "P10") (pin "P$285") (pinfunction "P$1_P$285") (pintype "power_in"))
      (node (ref "P10") (pin "P$286") (pinfunction "P$1_P$286") (pintype "power_in"))
      (node (ref "P10") (pin "P$287") (pinfunction "P$1_P$287") (pintype "power_in"))
      (node (ref "P10") (pin "P$288") (pinfunction "P$1_P$288") (pintype "power_in"))
      (node (ref "P10") (pin "P$29") (pinfunction "P$1_P$29") (pintype "power_in"))
      (node (ref "P10") (pin "P$3") (pinfunction "P$1_P$3") (pintype "power_in"))
      (node (ref "P10") (pin "P$30") (pinfunction "P$1_P$30") (pintype "power_in"))
      (node (ref "P10") (pin "P$31") (pinfunction "P$1_P$31") (pintype "power_in"))
      (node (ref "P10") (pin "P$32") (pinfunction "P$1_P$32") (pintype "power_in"))
      (node (ref "P10") (pin "P$33") (pinfunction "P$1_P$33") (pintype "power_in"))
      (node (ref "P10") (pin "P$34") (pinfunction "P$1_P$34") (pintype "power_in"))
      (node (ref "P10") (pin "P$35") (pinfunction "P$1_P$35") (pintype "power_in"))
      (node (ref "P10") (pin "P$36") (pinfunction "P$1_P$36") (pintype "power_in"))
      (node (ref "P10") (pin "P$37") (pinfunction "P$1_P$37") (pintype "power_in"))
      (node (ref "P10") (pin "P$38") (pinfunction "P$1_P$38") (pintype "power_in"))
      (node (ref "P10") (pin "P$39") (pinfunction "P$1_P$39") (pintype "power_in"))
      (node (ref "P10") (pin "P$4") (pinfunction "P$1_P$4") (pintype "power_in"))
      (node (ref "P10") (pin "P$40") (pinfunction "P$1_P$40") (pintype "power_in"))
      (node (ref "P10") (pin "P$41") (pinfunction "P$1_P$41") (pintype "power_in"))
      (node (ref "P10") (pin "P$42") (pinfunction "P$1_P$42") (pintype "power_in"))
      (node (ref "P10") (pin "P$43") (pinfunction "P$1_P$43") (pintype "power_in"))
      (node (ref "P10") (pin "P$44") (pinfunction "P$1_P$44") (pintype "power_in"))
      (node (ref "P10") (pin "P$45") (pinfunction "P$1_P$45") (pintype "power_in"))
      (node (ref "P10") (pin "P$46") (pinfunction "P$1_P$46") (pintype "power_in"))
      (node (ref "P10") (pin "P$47") (pinfunction "P$1_P$47") (pintype "power_in"))
      (node (ref "P10") (pin "P$48") (pinfunction "P$1_P$48") (pintype "power_in"))
      (node (ref "P10") (pin "P$49") (pinfunction "P$1_P$49") (pintype "power_in"))
      (node (ref "P10") (pin "P$5") (pinfunction "P$1_P$5") (pintype "power_in"))
      (node (ref "P10") (pin "P$50") (pinfunction "P$1_P$50") (pintype "power_in"))
      (node (ref "P10") (pin "P$51") (pinfunction "P$1_P$51") (pintype "power_in"))
      (node (ref "P10") (pin "P$52") (pinfunction "P$1_P$52") (pintype "power_in"))
      (node (ref "P10") (pin "P$53") (pinfunction "P$1_P$53") (pintype "power_in"))
      (node (ref "P10") (pin "P$54") (pinfunction "P$1_P$54") (pintype "power_in"))
      (node (ref "P10") (pin "P$55") (pinfunction "P$1_P$55") (pintype "power_in"))
      (node (ref "P10") (pin "P$56") (pinfunction "P$1_P$56") (pintype "power_in"))
      (node (ref "P10") (pin "P$57") (pinfunction "P$1_P$57") (pintype "power_in"))
      (node (ref "P10") (pin "P$58") (pinfunction "P$1_P$58") (pintype "power_in"))
      (node (ref "P10") (pin "P$59") (pinfunction "P$1_P$59") (pintype "power_in"))
      (node (ref "P10") (pin "P$6") (pinfunction "P$1_P$6") (pintype "power_in"))
      (node (ref "P10") (pin "P$60") (pinfunction "P$1_P$60") (pintype "power_in"))
      (node (ref "P10") (pin "P$61") (pinfunction "P$1_P$61") (pintype "power_in"))
      (node (ref "P10") (pin "P$62") (pinfunction "P$1_P$62") (pintype "power_in"))
      (node (ref "P10") (pin "P$63") (pinfunction "P$1_P$63") (pintype "power_in"))
      (node (ref "P10") (pin "P$64") (pinfunction "P$1_P$64") (pintype "power_in"))
      (node (ref "P10") (pin "P$65") (pinfunction "P$1_P$65") (pintype "power_in"))
      (node (ref "P10") (pin "P$66") (pinfunction "P$1_P$66") (pintype "power_in"))
      (node (ref "P10") (pin "P$67") (pinfunction "P$1_P$67") (pintype "power_in"))
      (node (ref "P10") (pin "P$68") (pinfunction "P$1_P$68") (pintype "power_in"))
      (node (ref "P10") (pin "P$69") (pinfunction "P$1_P$69") (pintype "power_in"))
      (node (ref "P10") (pin "P$7") (pinfunction "P$1_P$7") (pintype "power_in"))
      (node (ref "P10") (pin "P$70") (pinfunction "P$1_P$70") (pintype "power_in"))
      (node (ref "P10") (pin "P$71") (pinfunction "P$1_P$71") (pintype "power_in"))
      (node (ref "P10") (pin "P$72") (pinfunction "P$1_P$72") (pintype "power_in"))
      (node (ref "P10") (pin "P$73") (pinfunction "P$1_P$73") (pintype "power_in"))
      (node (ref "P10") (pin "P$74") (pinfunction "P$1_P$74") (pintype "power_in"))
      (node (ref "P10") (pin "P$75") (pinfunction "P$1_P$75") (pintype "power_in"))
      (node (ref "P10") (pin "P$76") (pinfunction "P$1_P$76") (pintype "power_in"))
      (node (ref "P10") (pin "P$77") (pinfunction "P$1_P$77") (pintype "power_in"))
      (node (ref "P10") (pin "P$78") (pinfunction "P$1_P$78") (pintype "power_in"))
      (node (ref "P10") (pin "P$79") (pinfunction "P$1_P$79") (pintype "power_in"))
      (node (ref "P10") (pin "P$8") (pinfunction "P$1_P$8") (pintype "power_in"))
      (node (ref "P10") (pin "P$80") (pinfunction "P$1_P$80") (pintype "power_in"))
      (node (ref "P10") (pin "P$81") (pinfunction "P$1_P$81") (pintype "power_in"))
      (node (ref "P10") (pin "P$82") (pinfunction "P$1_P$82") (pintype "power_in"))
      (node (ref "P10") (pin "P$83") (pinfunction "P$1_P$83") (pintype "power_in"))
      (node (ref "P10") (pin "P$84") (pinfunction "P$1_P$84") (pintype "power_in"))
      (node (ref "P10") (pin "P$85") (pinfunction "P$1_P$85") (pintype "power_in"))
      (node (ref "P10") (pin "P$86") (pinfunction "P$1_P$86") (pintype "power_in"))
      (node (ref "P10") (pin "P$87") (pinfunction "P$1_P$87") (pintype "power_in"))
      (node (ref "P10") (pin "P$88") (pinfunction "P$1_P$88") (pintype "power_in"))
      (node (ref "P10") (pin "P$89") (pinfunction "P$1_P$89") (pintype "power_in"))
      (node (ref "P10") (pin "P$9") (pinfunction "P$1_P$9") (pintype "power_in"))
      (node (ref "P10") (pin "P$90") (pinfunction "P$1_P$90") (pintype "power_in"))
      (node (ref "P10") (pin "P$91") (pinfunction "P$1_P$91") (pintype "power_in"))
      (node (ref "P10") (pin "P$92") (pinfunction "P$1_P$92") (pintype "power_in"))
      (node (ref "P10") (pin "P$93") (pinfunction "P$1_P$93") (pintype "power_in"))
      (node (ref "P10") (pin "P$94") (pinfunction "P$1_P$94") (pintype "power_in"))
      (node (ref "P10") (pin "P$95") (pinfunction "P$1_P$95") (pintype "power_in"))
      (node (ref "P10") (pin "P$96") (pinfunction "P$1_P$96") (pintype "power_in"))
      (node (ref "P10") (pin "P$97") (pinfunction "P$1_P$97") (pintype "power_in"))
      (node (ref "P10") (pin "P$98") (pinfunction "P$1_P$98") (pintype "power_in"))
      (node (ref "P10") (pin "P$99") (pinfunction "P$1_P$99") (pintype "power_in"))
    )
    (net (code "13") (name "/P11") (class "Default")
      (node (ref "JP1") (pin "P$12") (pinfunction "11_P$12") (pintype "bidirectional"))
      (node (ref "P11") (pin "P$1") (pinfunction "P$1_P$1") (pintype "power_in"))
      (node (ref "P11") (pin "P$10") (pinfunction "P$1_P$10") (pintype "power_in"))
      (node (ref "P11") (pin "P$100") (pinfunction "P$1_P$100") (pintype "power_in"))
      (node (ref "P11") (pin "P$101") (pinfunction "P$1_P$101") (pintype "power_in"))
      (node (ref "P11") (pin "P$102") (pinfunction "P$1_P$102") (pintype "power_in"))
      (node (ref "P11") (pin "P$103") (pinfunction "P$1_P$103") (pintype "power_in"))
      (node (ref "P11") (pin "P$104") (pinfunction "P$1_P$104") (pintype "power_in"))
      (node (ref "P11") (pin "P$105") (pinfunction "P$1_P$105") (pintype "power_in"))
      (node (ref "P11") (pin "P$106") (pinfunction "P$1_P$106") (pintype "power_in"))
      (node (ref "P11") (pin "P$107") (pinfunction "P$1_P$107") (pintype "power_in"))
      (node (ref "P11") (pin "P$108") (pinfunction "P$1_P$108") (pintype "power_in"))
      (node (ref "P11") (pin "P$109") (pinfunction "P$1_P$109") (pintype "power_in"))
      (node (ref "P11") (pin "P$11") (pinfunction "P$1_P$11") (pintype "power_in"))
      (node (ref "P11") (pin "P$110") (pinfunction "P$1_P$110") (pintype "power_in"))
      (node (ref "P11") (pin "P$111") (pinfunction "P$1_P$111") (pintype "power_in"))
      (node (ref "P11") (pin "P$112") (pinfunction "P$1_P$112") (pintype "power_in"))
      (node (ref "P11") (pin "P$113") (pinfunction "P$1_P$113") (pintype "power_in"))
      (node (ref "P11") (pin "P$114") (pinfunction "P$1_P$114") (pintype "power_in"))
      (node (ref "P11") (pin "P$115") (pinfunction "P$1_P$115") (pintype "power_in"))
      (node (ref "P11") (pin "P$116") (pinfunction "P$1_P$116") (pintype "power_in"))
      (node (ref "P11") (pin "P$117") (pinfunction "P$1_P$117") (pintype "power_in"))
      (node (ref "P11") (pin "P$118") (pinfunction "P$1_P$118") (pintype "power_in"))
      (node (ref "P11") (pin "P$119") (pinfunction "P$1_P$119") (pintype "power_in"))
      (node (ref "P11") (pin "P$12") (pinfunction "P$1_P$12") (pintype "power_in"))
      (node (ref "P11") (pin "P$120") (pinfunction "P$1_P$120") (pintype "power_in"))
      (node (ref "P11") (pin "P$121") (pinfunction "P$1_P$121") (pintype "power_in"))
      (node (ref "P11") (pin "P$122") (pinfunction "P$1_P$122") (pintype "power_in"))
      (node (ref "P11") (pin "P$123") (pinfunction "P$1_P$123") (pintype "power_in"))
      (node (ref "P11") (pin "P$124") (pinfunction "P$1_P$124") (pintype "power_in"))
      (node (ref "P11") (pin "P$125") (pinfunction "P$1_P$125") (pintype "power_in"))
      (node (ref "P11") (pin "P$126") (pinfunction "P$1_P$126") (pintype "power_in"))
      (node (ref "P11") (pin "P$127") (pinfunction "P$1_P$127") (pintype "power_in"))
      (node (ref "P11") (pin "P$128") (pinfunction "P$1_P$128") (pintype "power_in"))
      (node (ref "P11") (pin "P$129") (pinfunction "P$1_P$129") (pintype "power_in"))
      (node (ref "P11") (pin "P$13") (pinfunction "P$1_P$13") (pintype "power_in"))
      (node (ref "P11") (pin "P$130") (pinfunction "P$1_P$130") (pintype "power_in"))
      (node (ref "P11") (pin "P$131") (pinfunction "P$1_P$131") (pintype "power_in"))
      (node (ref "P11") (pin "P$132") (pinfunction "P$1_P$132") (pintype "power_in"))
      (node (ref "P11") (pin "P$133") (pinfunction "P$1_P$133") (pintype "power_in"))
      (node (ref "P11") (pin "P$134") (pinfunction "P$1_P$134") (pintype "power_in"))
      (node (ref "P11") (pin "P$135") (pinfunction "P$1_P$135") (pintype "power_in"))
      (node (ref "P11") (pin "P$136") (pinfunction "P$1_P$136") (pintype "power_in"))
      (node (ref "P11") (pin "P$137") (pinfunction "P$1_P$137") (pintype "power_in"))
      (node (ref "P11") (pin "P$138") (pinfunction "P$1_P$138") (pintype "power_in"))
      (node (ref "P11") (pin "P$139") (pinfunction "P$1_P$139") (pintype "power_in"))
      (node (ref "P11") (pin "P$14") (pinfunction "P$1_P$14") (pintype "power_in"))
      (node (ref "P11") (pin "P$140") (pinfunction "P$1_P$140") (pintype "power_in"))
      (node (ref "P11") (pin "P$141") (pinfunction "P$1_P$141") (pintype "power_in"))
      (node (ref "P11") (pin "P$142") (pinfunction "P$1_P$142") (pintype "power_in"))
      (node (ref "P11") (pin "P$143") (pinfunction "P$1_P$143") (pintype "power_in"))
      (node (ref "P11") (pin "P$144") (pinfunction "P$1_P$144") (pintype "power_in"))
      (node (ref "P11") (pin "P$145") (pinfunction "P$1_P$145") (pintype "power_in"))
      (node (ref "P11") (pin "P$146") (pinfunction "P$1_P$146") (pintype "power_in"))
      (node (ref "P11") (pin "P$147") (pinfunction "P$1_P$147") (pintype "power_in"))
      (node (ref "P11") (pin "P$148") (pinfunction "P$1_P$148") (pintype "power_in"))
      (node (ref "P11") (pin "P$149") (pinfunction "P$1_P$149") (pintype "power_in"))
      (node (ref "P11") (pin "P$15") (pinfunction "P$1_P$15") (pintype "power_in"))
      (node (ref "P11") (pin "P$150") (pinfunction "P$1_P$150") (pintype "power_in"))
      (node (ref "P11") (pin "P$151") (pinfunction "P$1_P$151") (pintype "power_in"))
      (node (ref "P11") (pin "P$152") (pinfunction "P$1_P$152") (pintype "power_in"))
      (node (ref "P11") (pin "P$153") (pinfunction "P$1_P$153") (pintype "power_in"))
      (node (ref "P11") (pin "P$154") (pinfunction "P$1_P$154") (pintype "power_in"))
      (node (ref "P11") (pin "P$155") (pinfunction "P$1_P$155") (pintype "power_in"))
      (node (ref "P11") (pin "P$156") (pinfunction "P$1_P$156") (pintype "power_in"))
      (node (ref "P11") (pin "P$157") (pinfunction "P$1_P$157") (pintype "power_in"))
      (node (ref "P11") (pin "P$158") (pinfunction "P$1_P$158") (pintype "power_in"))
      (node (ref "P11") (pin "P$159") (pinfunction "P$1_P$159") (pintype "power_in"))
      (node (ref "P11") (pin "P$16") (pinfunction "P$1_P$16") (pintype "power_in"))
      (node (ref "P11") (pin "P$160") (pinfunction "P$1_P$160") (pintype "power_in"))
      (node (ref "P11") (pin "P$161") (pinfunction "P$1_P$161") (pintype "power_in"))
      (node (ref "P11") (pin "P$162") (pinfunction "P$1_P$162") (pintype "power_in"))
      (node (ref "P11") (pin "P$163") (pinfunction "P$1_P$163") (pintype "power_in"))
      (node (ref "P11") (pin "P$164") (pinfunction "P$1_P$164") (pintype "power_in"))
      (node (ref "P11") (pin "P$165") (pinfunction "P$1_P$165") (pintype "power_in"))
      (node (ref "P11") (pin "P$166") (pinfunction "P$1_P$166") (pintype "power_in"))
      (node (ref "P11") (pin "P$167") (pinfunction "P$1_P$167") (pintype "power_in"))
      (node (ref "P11") (pin "P$168") (pinfunction "P$1_P$168") (pintype "power_in"))
      (node (ref "P11") (pin "P$169") (pinfunction "P$1_P$169") (pintype "power_in"))
      (node (ref "P11") (pin "P$17") (pinfunction "P$1_P$17") (pintype "power_in"))
      (node (ref "P11") (pin "P$170") (pinfunction "P$1_P$170") (pintype "power_in"))
      (node (ref "P11") (pin "P$171") (pinfunction "P$1_P$171") (pintype "power_in"))
      (node (ref "P11") (pin "P$172") (pinfunction "P$1_P$172") (pintype "power_in"))
      (node (ref "P11") (pin "P$173") (pinfunction "P$1_P$173") (pintype "power_in"))
      (node (ref "P11") (pin "P$174") (pinfunction "P$1_P$174") (pintype "power_in"))
      (node (ref "P11") (pin "P$175") (pinfunction "P$1_P$175") (pintype "power_in"))
      (node (ref "P11") (pin "P$176") (pinfunction "P$1_P$176") (pintype "power_in"))
      (node (ref "P11") (pin "P$177") (pinfunction "P$1_P$177") (pintype "power_in"))
      (node (ref "P11") (pin "P$178") (pinfunction "P$1_P$178") (pintype "power_in"))
      (node (ref "P11") (pin "P$179") (pinfunction "P$1_P$179") (pintype "power_in"))
      (node (ref "P11") (pin "P$18") (pinfunction "P$1_P$18") (pintype "power_in"))
      (node (ref "P11") (pin "P$180") (pinfunction "P$1_P$180") (pintype "power_in"))
      (node (ref "P11") (pin "P$181") (pinfunction "P$1_P$181") (pintype "power_in"))
      (node (ref "P11") (pin "P$182") (pinfunction "P$1_P$182") (pintype "power_in"))
      (node (ref "P11") (pin "P$183") (pinfunction "P$1_P$183") (pintype "power_in"))
      (node (ref "P11") (pin "P$184") (pinfunction "P$1_P$184") (pintype "power_in"))
      (node (ref "P11") (pin "P$185") (pinfunction "P$1_P$185") (pintype "power_in"))
      (node (ref "P11") (pin "P$186") (pinfunction "P$1_P$186") (pintype "power_in"))
      (node (ref "P11") (pin "P$187") (pinfunction "P$1_P$187") (pintype "power_in"))
      (node (ref "P11") (pin "P$188") (pinfunction "P$1_P$188") (pintype "power_in"))
      (node (ref "P11") (pin "P$189") (pinfunction "P$1_P$189") (pintype "power_in"))
      (node (ref "P11") (pin "P$19") (pinfunction "P$1_P$19") (pintype "power_in"))
      (node (ref "P11") (pin "P$190") (pinfunction "P$1_P$190") (pintype "power_in"))
      (node (ref "P11") (pin "P$191") (pinfunction "P$1_P$191") (pintype "power_in"))
      (node (ref "P11") (pin "P$192") (pinfunction "P$1_P$192") (pintype "power_in"))
      (node (ref "P11") (pin "P$193") (pinfunction "P$1_P$193") (pintype "power_in"))
      (node (ref "P11") (pin "P$194") (pinfunction "P$1_P$194") (pintype "power_in"))
      (node (ref "P11") (pin "P$195") (pinfunction "P$1_P$195") (pintype "power_in"))
      (node (ref "P11") (pin "P$196") (pinfunction "P$1_P$196") (pintype "power_in"))
      (node (ref "P11") (pin "P$197") (pinfunction "P$1_P$197") (pintype "power_in"))
      (node (ref "P11") (pin "P$198") (pinfunction "P$1_P$198") (pintype "power_in"))
      (node (ref "P11") (pin "P$199") (pinfunction "P$1_P$199") (pintype "power_in"))
      (node (ref "P11") (pin "P$2") (pinfunction "P$1_P$2") (pintype "power_in"))
      (node (ref "P11") (pin "P$20") (pinfunction "P$1_P$20") (pintype "power_in"))
      (node (ref "P11") (pin "P$200") (pinfunction "P$1_P$200") (pintype "power_in"))
      (node (ref "P11") (pin "P$201") (pinfunction "P$1_P$201") (pintype "power_in"))
      (node (ref "P11") (pin "P$202") (pinfunction "P$1_P$202") (pintype "power_in"))
      (node (ref "P11") (pin "P$203") (pinfunction "P$1_P$203") (pintype "power_in"))
      (node (ref "P11") (pin "P$204") (pinfunction "P$1_P$204") (pintype "power_in"))
      (node (ref "P11") (pin "P$205") (pinfunction "P$1_P$205") (pintype "power_in"))
      (node (ref "P11") (pin "P$206") (pinfunction "P$1_P$206") (pintype "power_in"))
      (node (ref "P11") (pin "P$207") (pinfunction "P$1_P$207") (pintype "power_in"))
      (node (ref "P11") (pin "P$208") (pinfunction "P$1_P$208") (pintype "power_in"))
      (node (ref "P11") (pin "P$209") (pinfunction "P$1_P$209") (pintype "power_in"))
      (node (ref "P11") (pin "P$21") (pinfunction "P$1_P$21") (pintype "power_in"))
      (node (ref "P11") (pin "P$210") (pinfunction "P$1_P$210") (pintype "power_in"))
      (node (ref "P11") (pin "P$211") (pinfunction "P$1_P$211") (pintype "power_in"))
      (node (ref "P11") (pin "P$212") (pinfunction "P$1_P$212") (pintype "power_in"))
      (node (ref "P11") (pin "P$213") (pinfunction "P$1_P$213") (pintype "power_in"))
      (node (ref "P11") (pin "P$214") (pinfunction "P$1_P$214") (pintype "power_in"))
      (node (ref "P11") (pin "P$215") (pinfunction "P$1_P$215") (pintype "power_in"))
      (node (ref "P11") (pin "P$216") (pinfunction "P$1_P$216") (pintype "power_in"))
      (node (ref "P11") (pin "P$217") (pinfunction "P$1_P$217") (pintype "power_in"))
      (node (ref "P11") (pin "P$218") (pinfunction "P$1_P$218") (pintype "power_in"))
      (node (ref "P11") (pin "P$219") (pinfunction "P$1_P$219") (pintype "power_in"))
      (node (ref "P11") (pin "P$22") (pinfunction "P$1_P$22") (pintype "power_in"))
      (node (ref "P11") (pin "P$220") (pinfunction "P$1_P$220") (pintype "power_in"))
      (node (ref "P11") (pin "P$221") (pinfunction "P$1_P$221") (pintype "power_in"))
      (node (ref "P11") (pin "P$222") (pinfunction "P$1_P$222") (pintype "power_in"))
      (node (ref "P11") (pin "P$223") (pinfunction "P$1_P$223") (pintype "power_in"))
      (node (ref "P11") (pin "P$224") (pinfunction "P$1_P$224") (pintype "power_in"))
      (node (ref "P11") (pin "P$225") (pinfunction "P$1_P$225") (pintype "power_in"))
      (node (ref "P11") (pin "P$226") (pinfunction "P$1_P$226") (pintype "power_in"))
      (node (ref "P11") (pin "P$227") (pinfunction "P$1_P$227") (pintype "power_in"))
      (node (ref "P11") (pin "P$228") (pinfunction "P$1_P$228") (pintype "power_in"))
      (node (ref "P11") (pin "P$229") (pinfunction "P$1_P$229") (pintype "power_in"))
      (node (ref "P11") (pin "P$23") (pinfunction "P$1_P$23") (pintype "power_in"))
      (node (ref "P11") (pin "P$230") (pinfunction "P$1_P$230") (pintype "power_in"))
      (node (ref "P11") (pin "P$231") (pinfunction "P$1_P$231") (pintype "power_in"))
      (node (ref "P11") (pin "P$232") (pinfunction "P$1_P$232") (pintype "power_in"))
      (node (ref "P11") (pin "P$233") (pinfunction "P$1_P$233") (pintype "power_in"))
      (node (ref "P11") (pin "P$234") (pinfunction "P$1_P$234") (pintype "power_in"))
      (node (ref "P11") (pin "P$235") (pinfunction "P$1_P$235") (pintype "power_in"))
      (node (ref "P11") (pin "P$236") (pinfunction "P$1_P$236") (pintype "power_in"))
      (node (ref "P11") (pin "P$237") (pinfunction "P$1_P$237") (pintype "power_in"))
      (node (ref "P11") (pin "P$238") (pinfunction "P$1_P$238") (pintype "power_in"))
      (node (ref "P11") (pin "P$239") (pinfunction "P$1_P$239") (pintype "power_in"))
      (node (ref "P11") (pin "P$24") (pinfunction "P$1_P$24") (pintype "power_in"))
      (node (ref "P11") (pin "P$240") (pinfunction "P$1_P$240") (pintype "power_in"))
      (node (ref "P11") (pin "P$241") (pinfunction "P$1_P$241") (pintype "power_in"))
      (node (ref "P11") (pin "P$242") (pinfunction "P$1_P$242") (pintype "power_in"))
      (node (ref "P11") (pin "P$243") (pinfunction "P$1_P$243") (pintype "power_in"))
      (node (ref "P11") (pin "P$244") (pinfunction "P$1_P$244") (pintype "power_in"))
      (node (ref "P11") (pin "P$245") (pinfunction "P$1_P$245") (pintype "power_in"))
      (node (ref "P11") (pin "P$246") (pinfunction "P$1_P$246") (pintype "power_in"))
      (node (ref "P11") (pin "P$247") (pinfunction "P$1_P$247") (pintype "power_in"))
      (node (ref "P11") (pin "P$248") (pinfunction "P$1_P$248") (pintype "power_in"))
      (node (ref "P11") (pin "P$249") (pinfunction "P$1_P$249") (pintype "power_in"))
      (node (ref "P11") (pin "P$25") (pinfunction "P$1_P$25") (pintype "power_in"))
      (node (ref "P11") (pin "P$250") (pinfunction "P$1_P$250") (pintype "power_in"))
      (node (ref "P11") (pin "P$251") (pinfunction "P$1_P$251") (pintype "power_in"))
      (node (ref "P11") (pin "P$252") (pinfunction "P$1_P$252") (pintype "power_in"))
      (node (ref "P11") (pin "P$253") (pinfunction "P$1_P$253") (pintype "power_in"))
      (node (ref "P11") (pin "P$254") (pinfunction "P$1_P$254") (pintype "power_in"))
      (node (ref "P11") (pin "P$255") (pinfunction "P$1_P$255") (pintype "power_in"))
      (node (ref "P11") (pin "P$256") (pinfunction "P$1_P$256") (pintype "power_in"))
      (node (ref "P11") (pin "P$257") (pinfunction "P$1_P$257") (pintype "power_in"))
      (node (ref "P11") (pin "P$258") (pinfunction "P$1_P$258") (pintype "power_in"))
      (node (ref "P11") (pin "P$259") (pinfunction "P$1_P$259") (pintype "power_in"))
      (node (ref "P11") (pin "P$26") (pinfunction "P$1_P$26") (pintype "power_in"))
      (node (ref "P11") (pin "P$260") (pinfunction "P$1_P$260") (pintype "power_in"))
      (node (ref "P11") (pin "P$261") (pinfunction "P$1_P$261") (pintype "power_in"))
      (node (ref "P11") (pin "P$262") (pinfunction "P$1_P$262") (pintype "power_in"))
      (node (ref "P11") (pin "P$263") (pinfunction "P$1_P$263") (pintype "power_in"))
      (node (ref "P11") (pin "P$264") (pinfunction "P$1_P$264") (pintype "power_in"))
      (node (ref "P11") (pin "P$265") (pinfunction "P$1_P$265") (pintype "power_in"))
      (node (ref "P11") (pin "P$266") (pinfunction "P$1_P$266") (pintype "power_in"))
      (node (ref "P11") (pin "P$267") (pinfunction "P$1_P$267") (pintype "power_in"))
      (node (ref "P11") (pin "P$268") (pinfunction "P$1_P$268") (pintype "power_in"))
      (node (ref "P11") (pin "P$269") (pinfunction "P$1_P$269") (pintype "power_in"))
      (node (ref "P11") (pin "P$27") (pinfunction "P$1_P$27") (pintype "power_in"))
      (node (ref "P11") (pin "P$270") (pinfunction "P$1_P$270") (pintype "power_in"))
      (node (ref "P11") (pin "P$271") (pinfunction "P$1_P$271") (pintype "power_in"))
      (node (ref "P11") (pin "P$272") (pinfunction "P$1_P$272") (pintype "power_in"))
      (node (ref "P11") (pin "P$273") (pinfunction "P$1_P$273") (pintype "power_in"))
      (node (ref "P11") (pin "P$274") (pinfunction "P$1_P$274") (pintype "power_in"))
      (node (ref "P11") (pin "P$275") (pinfunction "P$1_P$275") (pintype "power_in"))
      (node (ref "P11") (pin "P$276") (pinfunction "P$1_P$276") (pintype "power_in"))
      (node (ref "P11") (pin "P$277") (pinfunction "P$1_P$277") (pintype "power_in"))
      (node (ref "P11") (pin "P$278") (pinfunction "P$1_P$278") (pintype "power_in"))
      (node (ref "P11") (pin "P$279") (pinfunction "P$1_P$279") (pintype "power_in"))
      (node (ref "P11") (pin "P$28") (pinfunction "P$1_P$28") (pintype "power_in"))
      (node (ref "P11") (pin "P$280") (pinfunction "P$1_P$280") (pintype "power_in"))
      (node (ref "P11") (pin "P$281") (pinfunction "P$1_P$281") (pintype "power_in"))
      (node (ref "P11") (pin "P$282") (pinfunction "P$1_P$282") (pintype "power_in"))
      (node (ref "P11") (pin "P$283") (pinfunction "P$1_P$283") (pintype "power_in"))
      (node (ref "P11") (pin "P$284") (pinfunction "P$1_P$284") (pintype "power_in"))
      (node (ref "P11") (pin "P$285") (pinfunction "P$1_P$285") (pintype "power_in"))
      (node (ref "P11") (pin "P$286") (pinfunction "P$1_P$286") (pintype "power_in"))
      (node (ref "P11") (pin "P$287") (pinfunction "P$1_P$287") (pintype "power_in"))
      (node (ref "P11") (pin "P$288") (pinfunction "P$1_P$288") (pintype "power_in"))
      (node (ref "P11") (pin "P$29") (pinfunction "P$1_P$29") (pintype "power_in"))
      (node (ref "P11") (pin "P$3") (pinfunction "P$1_P$3") (pintype "power_in"))
      (node (ref "P11") (pin "P$30") (pinfunction "P$1_P$30") (pintype "power_in"))
      (node (ref "P11") (pin "P$31") (pinfunction "P$1_P$31") (pintype "power_in"))
      (node (ref "P11") (pin "P$32") (pinfunction "P$1_P$32") (pintype "power_in"))
      (node (ref "P11") (pin "P$33") (pinfunction "P$1_P$33") (pintype "power_in"))
      (node (ref "P11") (pin "P$34") (pinfunction "P$1_P$34") (pintype "power_in"))
      (node (ref "P11") (pin "P$35") (pinfunction "P$1_P$35") (pintype "power_in"))
      (node (ref "P11") (pin "P$36") (pinfunction "P$1_P$36") (pintype "power_in"))
      (node (ref "P11") (pin "P$37") (pinfunction "P$1_P$37") (pintype "power_in"))
      (node (ref "P11") (pin "P$38") (pinfunction "P$1_P$38") (pintype "power_in"))
      (node (ref "P11") (pin "P$39") (pinfunction "P$1_P$39") (pintype "power_in"))
      (node (ref "P11") (pin "P$4") (pinfunction "P$1_P$4") (pintype "power_in"))
      (node (ref "P11") (pin "P$40") (pinfunction "P$1_P$40") (pintype "power_in"))
      (node (ref "P11") (pin "P$41") (pinfunction "P$1_P$41") (pintype "power_in"))
      (node (ref "P11") (pin "P$42") (pinfunction "P$1_P$42") (pintype "power_in"))
      (node (ref "P11") (pin "P$43") (pinfunction "P$1_P$43") (pintype "power_in"))
      (node (ref "P11") (pin "P$44") (pinfunction "P$1_P$44") (pintype "power_in"))
      (node (ref "P11") (pin "P$45") (pinfunction "P$1_P$45") (pintype "power_in"))
      (node (ref "P11") (pin "P$46") (pinfunction "P$1_P$46") (pintype "power_in"))
      (node (ref "P11") (pin "P$47") (pinfunction "P$1_P$47") (pintype "power_in"))
      (node (ref "P11") (pin "P$48") (pinfunction "P$1_P$48") (pintype "power_in"))
      (node (ref "P11") (pin "P$49") (pinfunction "P$1_P$49") (pintype "power_in"))
      (node (ref "P11") (pin "P$5") (pinfunction "P$1_P$5") (pintype "power_in"))
      (node (ref "P11") (pin "P$50") (pinfunction "P$1_P$50") (pintype "power_in"))
      (node (ref "P11") (pin "P$51") (pinfunction "P$1_P$51") (pintype "power_in"))
      (node (ref "P11") (pin "P$52") (pinfunction "P$1_P$52") (pintype "power_in"))
      (node (ref "P11") (pin "P$53") (pinfunction "P$1_P$53") (pintype "power_in"))
      (node (ref "P11") (pin "P$54") (pinfunction "P$1_P$54") (pintype "power_in"))
      (node (ref "P11") (pin "P$55") (pinfunction "P$1_P$55") (pintype "power_in"))
      (node (ref "P11") (pin "P$56") (pinfunction "P$1_P$56") (pintype "power_in"))
      (node (ref "P11") (pin "P$57") (pinfunction "P$1_P$57") (pintype "power_in"))
      (node (ref "P11") (pin "P$58") (pinfunction "P$1_P$58") (pintype "power_in"))
      (node (ref "P11") (pin "P$59") (pinfunction "P$1_P$59") (pintype "power_in"))
      (node (ref "P11") (pin "P$6") (pinfunction "P$1_P$6") (pintype "power_in"))
      (node (ref "P11") (pin "P$60") (pinfunction "P$1_P$60") (pintype "power_in"))
      (node (ref "P11") (pin "P$61") (pinfunction "P$1_P$61") (pintype "power_in"))
      (node (ref "P11") (pin "P$62") (pinfunction "P$1_P$62") (pintype "power_in"))
      (node (ref "P11") (pin "P$63") (pinfunction "P$1_P$63") (pintype "power_in"))
      (node (ref "P11") (pin "P$64") (pinfunction "P$1_P$64") (pintype "power_in"))
      (node (ref "P11") (pin "P$65") (pinfunction "P$1_P$65") (pintype "power_in"))
      (node (ref "P11") (pin "P$66") (pinfunction "P$1_P$66") (pintype "power_in"))
      (node (ref "P11") (pin "P$67") (pinfunction "P$1_P$67") (pintype "power_in"))
      (node (ref "P11") (pin "P$68") (pinfunction "P$1_P$68") (pintype "power_in"))
      (node (ref "P11") (pin "P$69") (pinfunction "P$1_P$69") (pintype "power_in"))
      (node (ref "P11") (pin "P$7") (pinfunction "P$1_P$7") (pintype "power_in"))
      (node (ref "P11") (pin "P$70") (pinfunction "P$1_P$70") (pintype "power_in"))
      (node (ref "P11") (pin "P$71") (pinfunction "P$1_P$71") (pintype "power_in"))
      (node (ref "P11") (pin "P$72") (pinfunction "P$1_P$72") (pintype "power_in"))
      (node (ref "P11") (pin "P$73") (pinfunction "P$1_P$73") (pintype "power_in"))
      (node (ref "P11") (pin "P$74") (pinfunction "P$1_P$74") (pintype "power_in"))
      (node (ref "P11") (pin "P$75") (pinfunction "P$1_P$75") (pintype "power_in"))
      (node (ref "P11") (pin "P$76") (pinfunction "P$1_P$76") (pintype "power_in"))
      (node (ref "P11") (pin "P$77") (pinfunction "P$1_P$77") (pintype "power_in"))
      (node (ref "P11") (pin "P$78") (pinfunction "P$1_P$78") (pintype "power_in"))
      (node (ref "P11") (pin "P$79") (pinfunction "P$1_P$79") (pintype "power_in"))
      (node (ref "P11") (pin "P$8") (pinfunction "P$1_P$8") (pintype "power_in"))
      (node (ref "P11") (pin "P$80") (pinfunction "P$1_P$80") (pintype "power_in"))
      (node (ref "P11") (pin "P$81") (pinfunction "P$1_P$81") (pintype "power_in"))
      (node (ref "P11") (pin "P$82") (pinfunction "P$1_P$82") (pintype "power_in"))
      (node (ref "P11") (pin "P$83") (pinfunction "P$1_P$83") (pintype "power_in"))
      (node (ref "P11") (pin "P$84") (pinfunction "P$1_P$84") (pintype "power_in"))
      (node (ref "P11") (pin "P$85") (pinfunction "P$1_P$85") (pintype "power_in"))
      (node (ref "P11") (pin "P$86") (pinfunction "P$1_P$86") (pintype "power_in"))
      (node (ref "P11") (pin "P$87") (pinfunction "P$1_P$87") (pintype "power_in"))
      (node (ref "P11") (pin "P$88") (pinfunction "P$1_P$88") (pintype "power_in"))
      (node (ref "P11") (pin "P$89") (pinfunction "P$1_P$89") (pintype "power_in"))
      (node (ref "P11") (pin "P$9") (pinfunction "P$1_P$9") (pintype "power_in"))
      (node (ref "P11") (pin "P$90") (pinfunction "P$1_P$90") (pintype "power_in"))
      (node (ref "P11") (pin "P$91") (pinfunction "P$1_P$91") (pintype "power_in"))
      (node (ref "P11") (pin "P$92") (pinfunction "P$1_P$92") (pintype "power_in"))
      (node (ref "P11") (pin "P$93") (pinfunction "P$1_P$93") (pintype "power_in"))
      (node (ref "P11") (pin "P$94") (pinfunction "P$1_P$94") (pintype "power_in"))
      (node (ref "P11") (pin "P$95") (pinfunction "P$1_P$95") (pintype "power_in"))
      (node (ref "P11") (pin "P$96") (pinfunction "P$1_P$96") (pintype "power_in"))
      (node (ref "P11") (pin "P$97") (pinfunction "P$1_P$97") (pintype "power_in"))
      (node (ref "P11") (pin "P$98") (pinfunction "P$1_P$98") (pintype "power_in"))
      (node (ref "P11") (pin "P$99") (pinfunction "P$1_P$99") (pintype "power_in"))
    )
    (net (code "14") (name "/P12+") (class "Default")
      (node (ref "J1") (pin "1") (pinfunction "1_1") (pintype "bidirectional"))
      (node (ref "J1") (pin "10") (pinfunction "10_10") (pintype "bidirectional"))
      (node (ref "J1") (pin "11") (pinfunction "11_11") (pintype "bidirectional"))
      (node (ref "J1") (pin "12") (pinfunction "12_12") (pintype "bidirectional"))
      (node (ref "J1") (pin "2") (pinfunction "2_2") (pintype "bidirectional"))
      (node (ref "J1") (pin "3") (pinfunction "3_3") (pintype "bidirectional"))
      (node (ref "J1") (pin "4") (pinfunction "4_4") (pintype "bidirectional"))
      (node (ref "J1") (pin "5") (pinfunction "5_5") (pintype "bidirectional"))
      (node (ref "J1") (pin "6") (pinfunction "6_6") (pintype "bidirectional"))
      (node (ref "J1") (pin "7") (pinfunction "7_7") (pintype "bidirectional"))
      (node (ref "J1") (pin "8") (pinfunction "8_8") (pintype "bidirectional"))
      (node (ref "J1") (pin "9") (pinfunction "9_9") (pintype "bidirectional"))
      (node (ref "JP1") (pin "P$13") (pinfunction "12_P$13") (pintype "bidirectional"))
      (node (ref "P12") (pin "P$10") (pinfunction "P$0_P$10") (pintype "power_in"))
      (node (ref "P12") (pin "P$100") (pinfunction "P$0_P$100") (pintype "power_in"))
      (node (ref "P12") (pin "P$101") (pinfunction "P$0_P$101") (pintype "power_in"))
      (node (ref "P12") (pin "P$102") (pinfunction "P$0_P$102") (pintype "power_in"))
      (node (ref "P12") (pin "P$103") (pinfunction "P$0_P$103") (pintype "power_in"))
      (node (ref "P12") (pin "P$104") (pinfunction "P$0_P$104") (pintype "power_in"))
      (node (ref "P12") (pin "P$105") (pinfunction "P$0_P$105") (pintype "power_in"))
      (node (ref "P12") (pin "P$106") (pinfunction "P$0_P$106") (pintype "power_in"))
      (node (ref "P12") (pin "P$107") (pinfunction "P$0_P$107") (pintype "power_in"))
      (node (ref "P12") (pin "P$108") (pinfunction "P$0_P$108") (pintype "power_in"))
      (node (ref "P12") (pin "P$109") (pinfunction "P$0_P$109") (pintype "power_in"))
      (node (ref "P12") (pin "P$11") (pinfunction "P$0_P$11") (pintype "power_in"))
      (node (ref "P12") (pin "P$110") (pinfunction "P$0_P$110") (pintype "power_in"))
      (node (ref "P12") (pin "P$12") (pinfunction "P$0_P$12") (pintype "power_in"))
      (node (ref "P12") (pin "P$13") (pinfunction "P$0_P$13") (pintype "power_in"))
      (node (ref "P12") (pin "P$14") (pinfunction "P$0_P$14") (pintype "power_in"))
      (node (ref "P12") (pin "P$15") (pinfunction "P$0_P$15") (pintype "power_in"))
      (node (ref "P12") (pin "P$16") (pinfunction "P$0_P$16") (pintype "power_in"))
      (node (ref "P12") (pin "P$17") (pinfunction "P$0_P$17") (pintype "power_in"))
      (node (ref "P12") (pin "P$18") (pinfunction "P$0_P$18") (pintype "power_in"))
      (node (ref "P12") (pin "P$19") (pinfunction "P$0_P$19") (pintype "power_in"))
      (node (ref "P12") (pin "P$20") (pinfunction "P$0_P$20") (pintype "power_in"))
      (node (ref "P12") (pin "P$21") (pinfunction "P$0_P$21") (pintype "power_in"))
      (node (ref "P12") (pin "P$22") (pinfunction "P$0_P$22") (pintype "power_in"))
      (node (ref "P12") (pin "P$23") (pinfunction "P$0_P$23") (pintype "power_in"))
      (node (ref "P12") (pin "P$24") (pinfunction "P$0_P$24") (pintype "power_in"))
      (node (ref "P12") (pin "P$25") (pinfunction "P$0_P$25") (pintype "power_in"))
      (node (ref "P12") (pin "P$26") (pinfunction "P$0_P$26") (pintype "power_in"))
      (node (ref "P12") (pin "P$27") (pinfunction "P$0_P$27") (pintype "power_in"))
      (node (ref "P12") (pin "P$28") (pinfunction "P$0_P$28") (pintype "power_in"))
      (node (ref "P12") (pin "P$29") (pinfunction "P$0_P$29") (pintype "power_in"))
      (node (ref "P12") (pin "P$3") (pinfunction "P$0_P$3") (pintype "power_in"))
      (node (ref "P12") (pin "P$30") (pinfunction "P$0_P$30") (pintype "power_in"))
      (node (ref "P12") (pin "P$31") (pinfunction "P$0_P$31") (pintype "power_in"))
      (node (ref "P12") (pin "P$32") (pinfunction "P$0_P$32") (pintype "power_in"))
      (node (ref "P12") (pin "P$33") (pinfunction "P$0_P$33") (pintype "power_in"))
      (node (ref "P12") (pin "P$34") (pinfunction "P$0_P$34") (pintype "power_in"))
      (node (ref "P12") (pin "P$35") (pinfunction "P$0_P$35") (pintype "power_in"))
      (node (ref "P12") (pin "P$36") (pinfunction "P$0_P$36") (pintype "power_in"))
      (node (ref "P12") (pin "P$37") (pinfunction "P$0_P$37") (pintype "power_in"))
      (node (ref "P12") (pin "P$38") (pinfunction "P$0_P$38") (pintype "power_in"))
      (node (ref "P12") (pin "P$39") (pinfunction "P$0_P$39") (pintype "power_in"))
      (node (ref "P12") (pin "P$4") (pinfunction "P$0_P$4") (pintype "power_in"))
      (node (ref "P12") (pin "P$40") (pinfunction "P$0_P$40") (pintype "power_in"))
      (node (ref "P12") (pin "P$41") (pinfunction "P$0_P$41") (pintype "power_in"))
      (node (ref "P12") (pin "P$42") (pinfunction "P$0_P$42") (pintype "power_in"))
      (node (ref "P12") (pin "P$43") (pinfunction "P$0_P$43") (pintype "power_in"))
      (node (ref "P12") (pin "P$44") (pinfunction "P$0_P$44") (pintype "power_in"))
      (node (ref "P12") (pin "P$45") (pinfunction "P$0_P$45") (pintype "power_in"))
      (node (ref "P12") (pin "P$46") (pinfunction "P$0_P$46") (pintype "power_in"))
      (node (ref "P12") (pin "P$47") (pinfunction "P$0_P$47") (pintype "power_in"))
      (node (ref "P12") (pin "P$48") (pinfunction "P$0_P$48") (pintype "power_in"))
      (node (ref "P12") (pin "P$49") (pinfunction "P$0_P$49") (pintype "power_in"))
      (node (ref "P12") (pin "P$5") (pinfunction "P$0_P$5") (pintype "power_in"))
      (node (ref "P12") (pin "P$50") (pinfunction "P$0_P$50") (pintype "power_in"))
      (node (ref "P12") (pin "P$51") (pinfunction "P$0_P$51") (pintype "power_in"))
      (node (ref "P12") (pin "P$52") (pinfunction "P$0_P$52") (pintype "power_in"))
      (node (ref "P12") (pin "P$53") (pinfunction "P$0_P$53") (pintype "power_in"))
      (node (ref "P12") (pin "P$54") (pinfunction "P$0_P$54") (pintype "power_in"))
      (node (ref "P12") (pin "P$55") (pinfunction "P$0_P$55") (pintype "power_in"))
      (node (ref "P12") (pin "P$56") (pinfunction "P$0_P$56") (pintype "power_in"))
      (node (ref "P12") (pin "P$57") (pinfunction "P$0_P$57") (pintype "power_in"))
      (node (ref "P12") (pin "P$58") (pinfunction "P$0_P$58") (pintype "power_in"))
      (node (ref "P12") (pin "P$59") (pinfunction "P$0_P$59") (pintype "power_in"))
      (node (ref "P12") (pin "P$6") (pinfunction "P$0_P$6") (pintype "power_in"))
      (node (ref "P12") (pin "P$60") (pinfunction "P$0_P$60") (pintype "power_in"))
      (node (ref "P12") (pin "P$61") (pinfunction "P$0_P$61") (pintype "power_in"))
      (node (ref "P12") (pin "P$62") (pinfunction "P$0_P$62") (pintype "power_in"))
      (node (ref "P12") (pin "P$63") (pinfunction "P$0_P$63") (pintype "power_in"))
      (node (ref "P12") (pin "P$64") (pinfunction "P$0_P$64") (pintype "power_in"))
      (node (ref "P12") (pin "P$65") (pinfunction "P$0_P$65") (pintype "power_in"))
      (node (ref "P12") (pin "P$66") (pinfunction "P$0_P$66") (pintype "power_in"))
      (node (ref "P12") (pin "P$67") (pinfunction "P$0_P$67") (pintype "power_in"))
      (node (ref "P12") (pin "P$68") (pinfunction "P$0_P$68") (pintype "power_in"))
      (node (ref "P12") (pin "P$69") (pinfunction "P$0_P$69") (pintype "power_in"))
      (node (ref "P12") (pin "P$7") (pinfunction "P$0_P$7") (pintype "power_in"))
      (node (ref "P12") (pin "P$70") (pinfunction "P$0_P$70") (pintype "power_in"))
      (node (ref "P12") (pin "P$71") (pinfunction "P$0_P$71") (pintype "power_in"))
      (node (ref "P12") (pin "P$72") (pinfunction "P$0_P$72") (pintype "power_in"))
      (node (ref "P12") (pin "P$73") (pinfunction "P$0_P$73") (pintype "power_in"))
      (node (ref "P12") (pin "P$74") (pinfunction "P$0_P$74") (pintype "power_in"))
      (node (ref "P12") (pin "P$75") (pinfunction "P$0_P$75") (pintype "power_in"))
      (node (ref "P12") (pin "P$76") (pinfunction "P$0_P$76") (pintype "power_in"))
      (node (ref "P12") (pin "P$77") (pinfunction "P$0_P$77") (pintype "power_in"))
      (node (ref "P12") (pin "P$78") (pinfunction "P$0_P$78") (pintype "power_in"))
      (node (ref "P12") (pin "P$79") (pinfunction "P$0_P$79") (pintype "power_in"))
      (node (ref "P12") (pin "P$8") (pinfunction "P$0_P$8") (pintype "power_in"))
      (node (ref "P12") (pin "P$80") (pinfunction "P$0_P$80") (pintype "power_in"))
      (node (ref "P12") (pin "P$81") (pinfunction "P$0_P$81") (pintype "power_in"))
      (node (ref "P12") (pin "P$82") (pinfunction "P$0_P$82") (pintype "power_in"))
      (node (ref "P12") (pin "P$83") (pinfunction "P$0_P$83") (pintype "power_in"))
      (node (ref "P12") (pin "P$84") (pinfunction "P$0_P$84") (pintype "power_in"))
      (node (ref "P12") (pin "P$85") (pinfunction "P$0_P$85") (pintype "power_in"))
      (node (ref "P12") (pin "P$86") (pinfunction "P$0_P$86") (pintype "power_in"))
      (node (ref "P12") (pin "P$87") (pinfunction "P$0_P$87") (pintype "power_in"))
      (node (ref "P12") (pin "P$88") (pinfunction "P$0_P$88") (pintype "power_in"))
      (node (ref "P12") (pin "P$89") (pinfunction "P$0_P$89") (pintype "power_in"))
      (node (ref "P12") (pin "P$9") (pinfunction "P$0_P$9") (pintype "power_in"))
      (node (ref "P12") (pin "P$90") (pinfunction "P$0_P$90") (pintype "power_in"))
      (node (ref "P12") (pin "P$91") (pinfunction "P$0_P$91") (pintype "power_in"))
      (node (ref "P12") (pin "P$92") (pinfunction "P$0_P$92") (pintype "power_in"))
      (node (ref "P12") (pin "P$93") (pinfunction "P$0_P$93") (pintype "power_in"))
      (node (ref "P12") (pin "P$94") (pinfunction "P$0_P$94") (pintype "power_in"))
      (node (ref "P12") (pin "P$95") (pinfunction "P$0_P$95") (pintype "power_in"))
      (node (ref "P12") (pin "P$96") (pinfunction "P$0_P$96") (pintype "power_in"))
      (node (ref "P12") (pin "P$97") (pinfunction "P$0_P$97") (pintype "power_in"))
      (node (ref "P12") (pin "P$98") (pinfunction "P$0_P$98") (pintype "power_in"))
      (node (ref "P12") (pin "P$99") (pinfunction "P$0_P$99") (pintype "power_in"))
    )
  )
)
